# Display_RevA.net
KiCad netlist of a schematic drawn in EAGLE
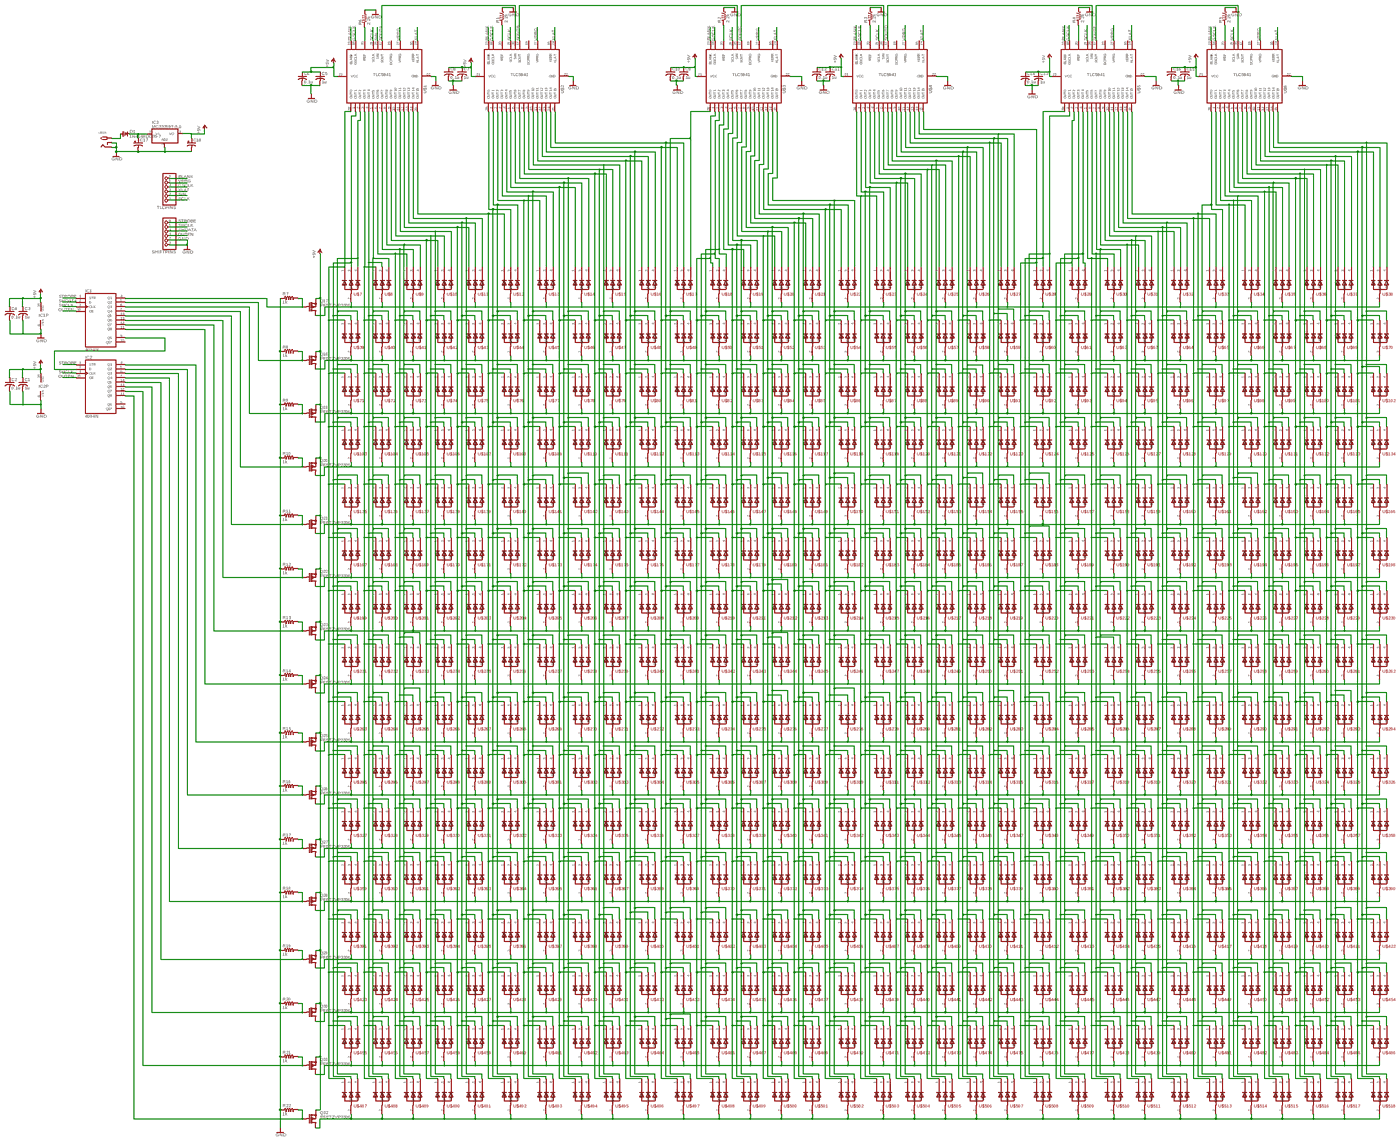
[diagram p0: schematic, sheet 1, overview]
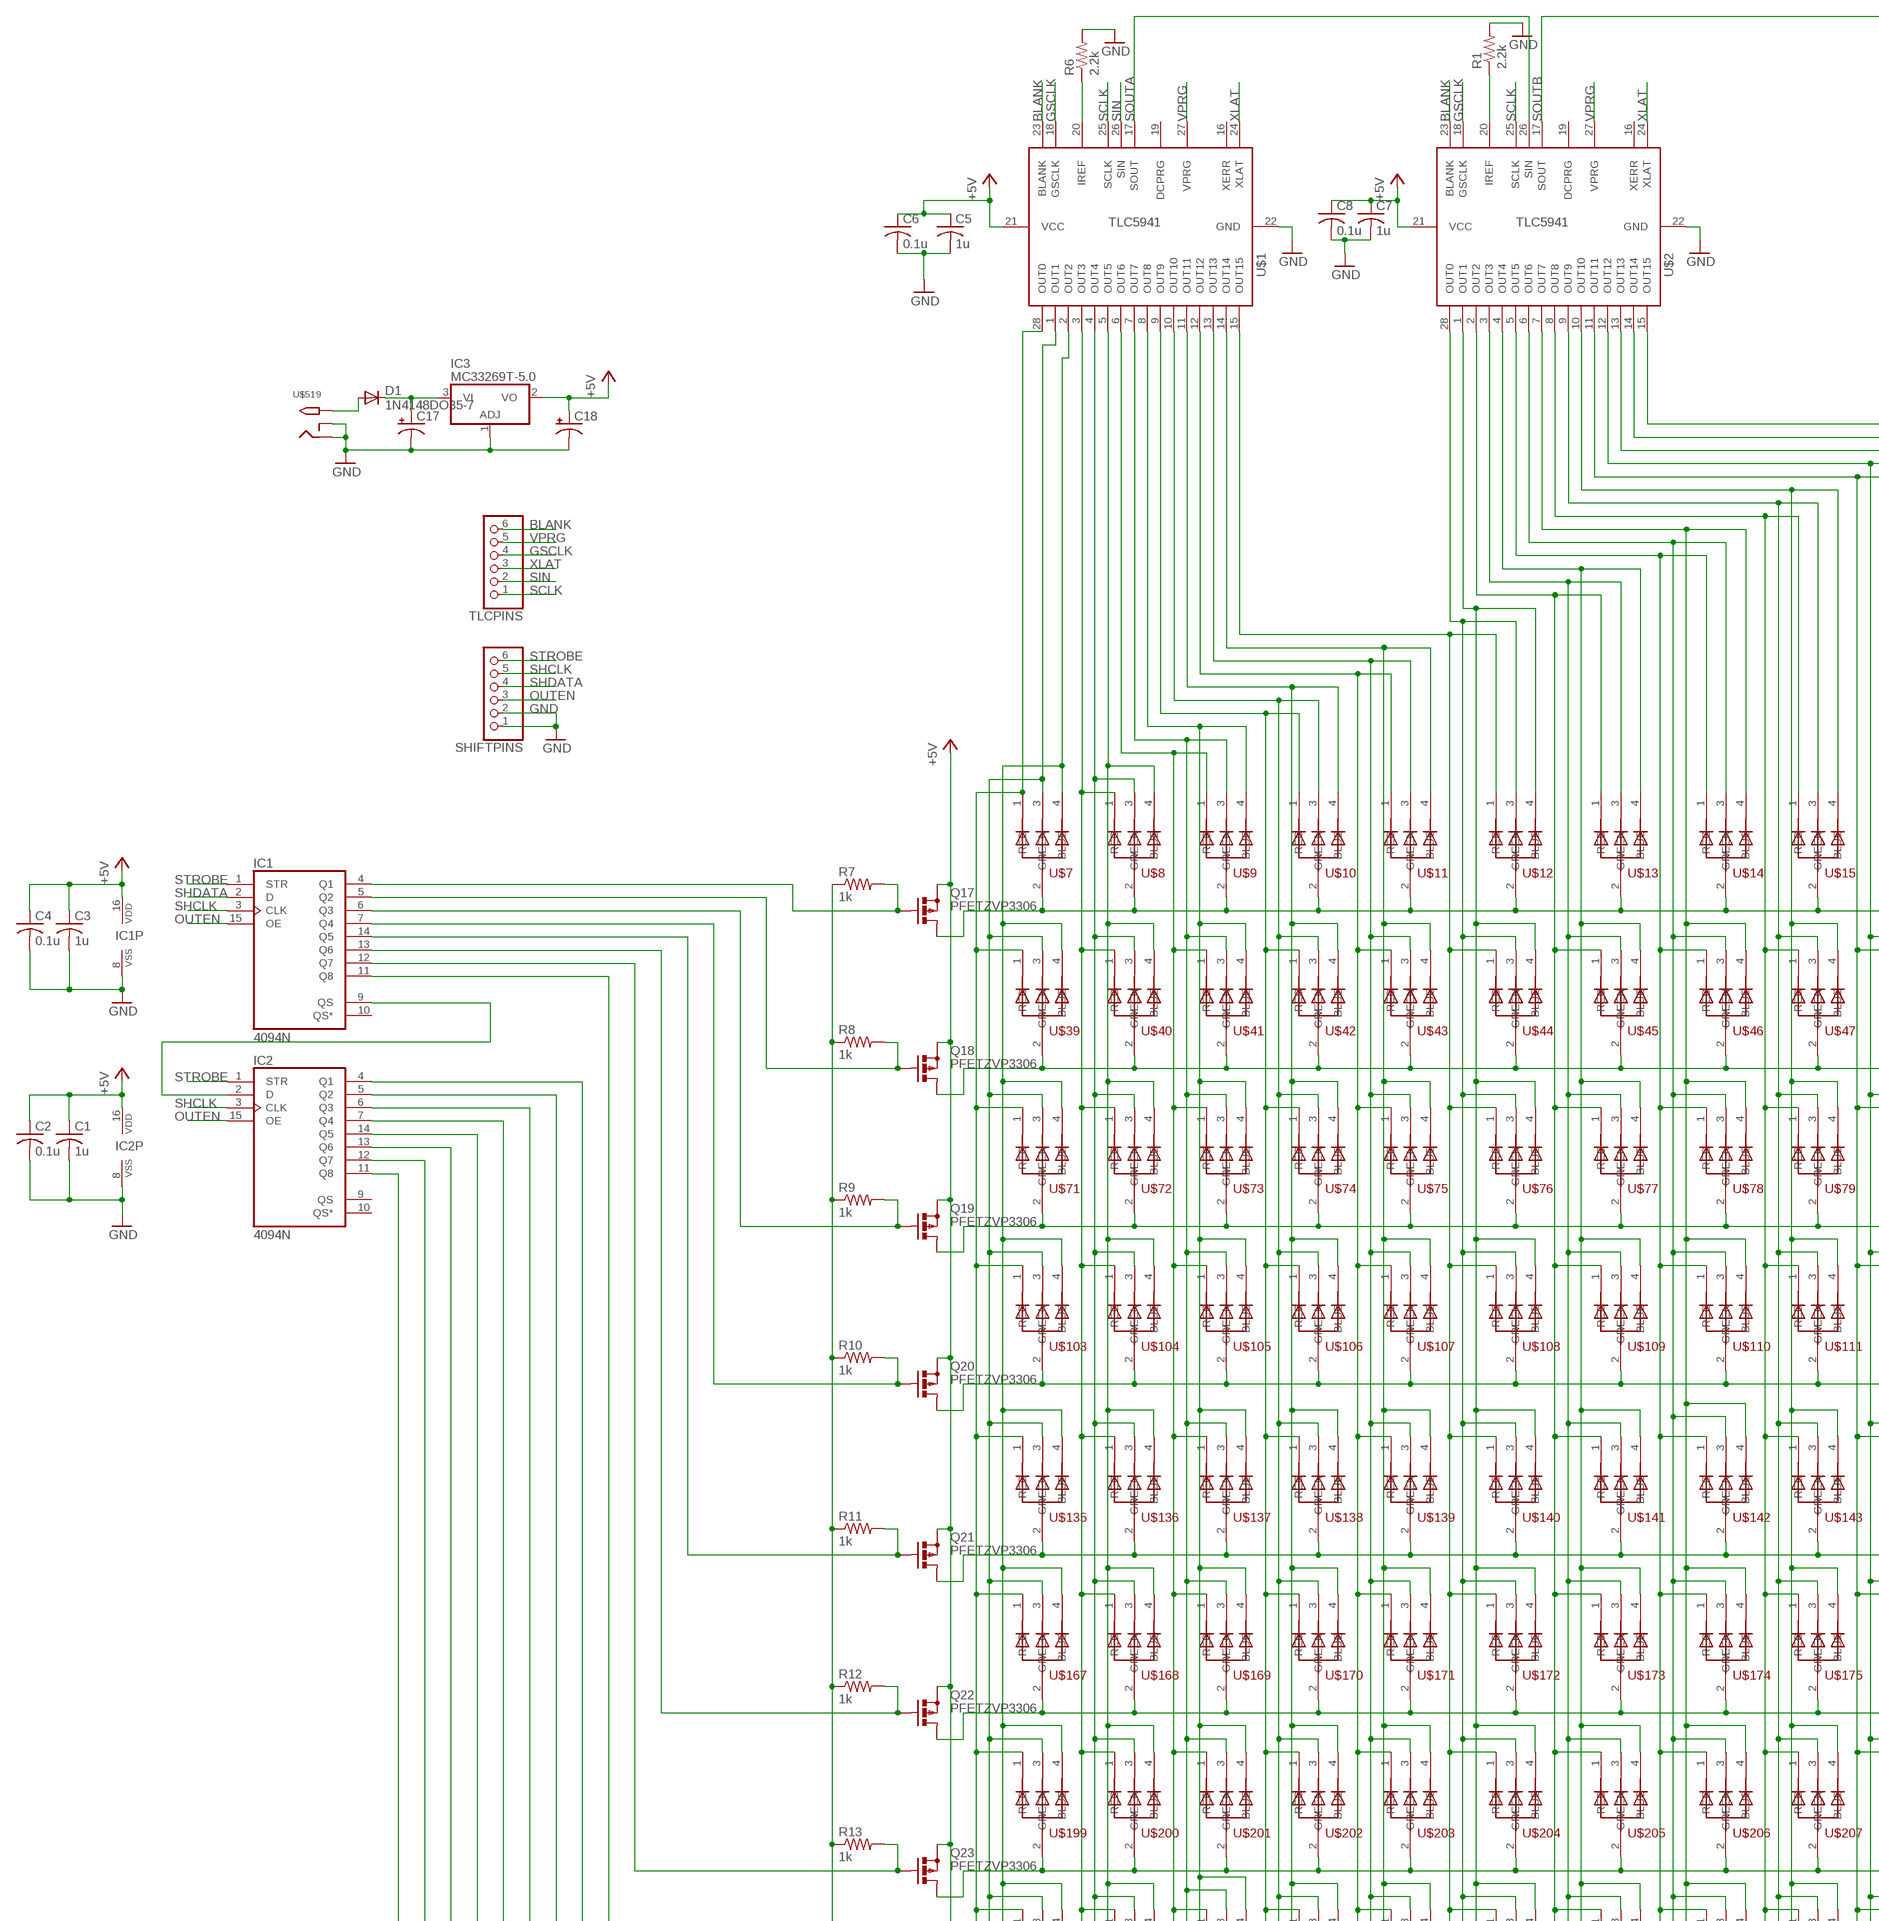
[diagram p1: schematic, sheet 1, part 1 of 4]
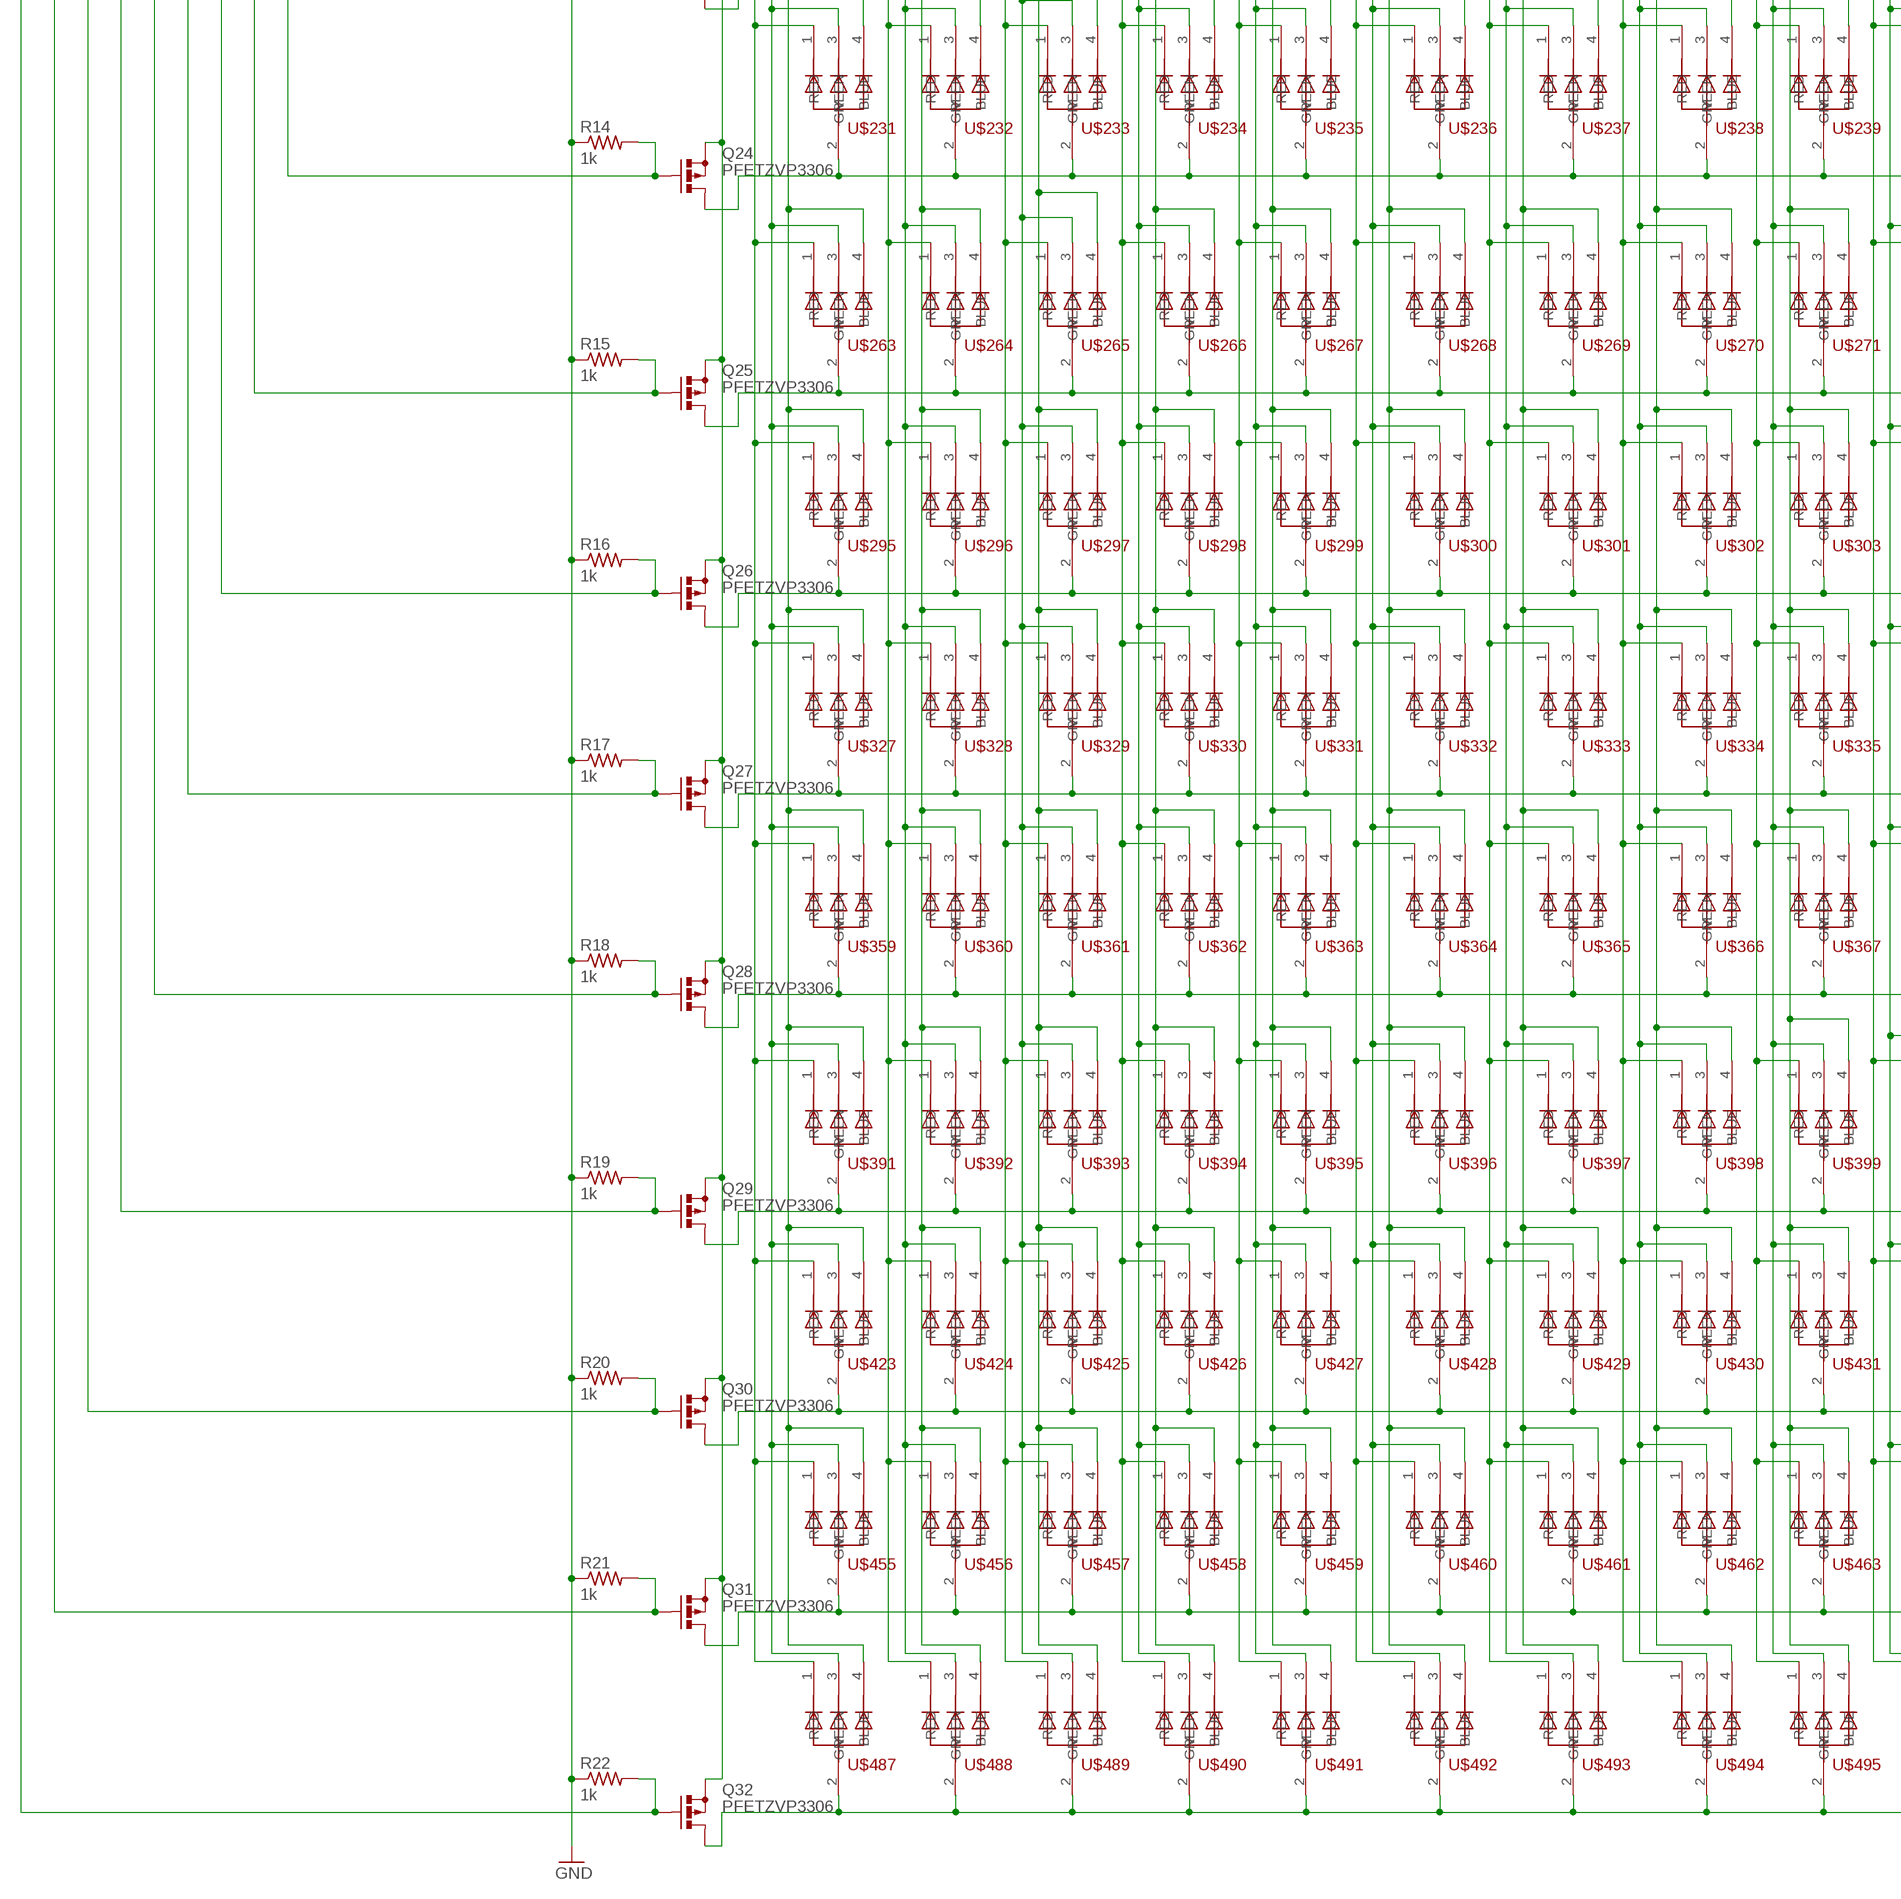
[diagram p2: schematic, sheet 1, part 2 of 4]
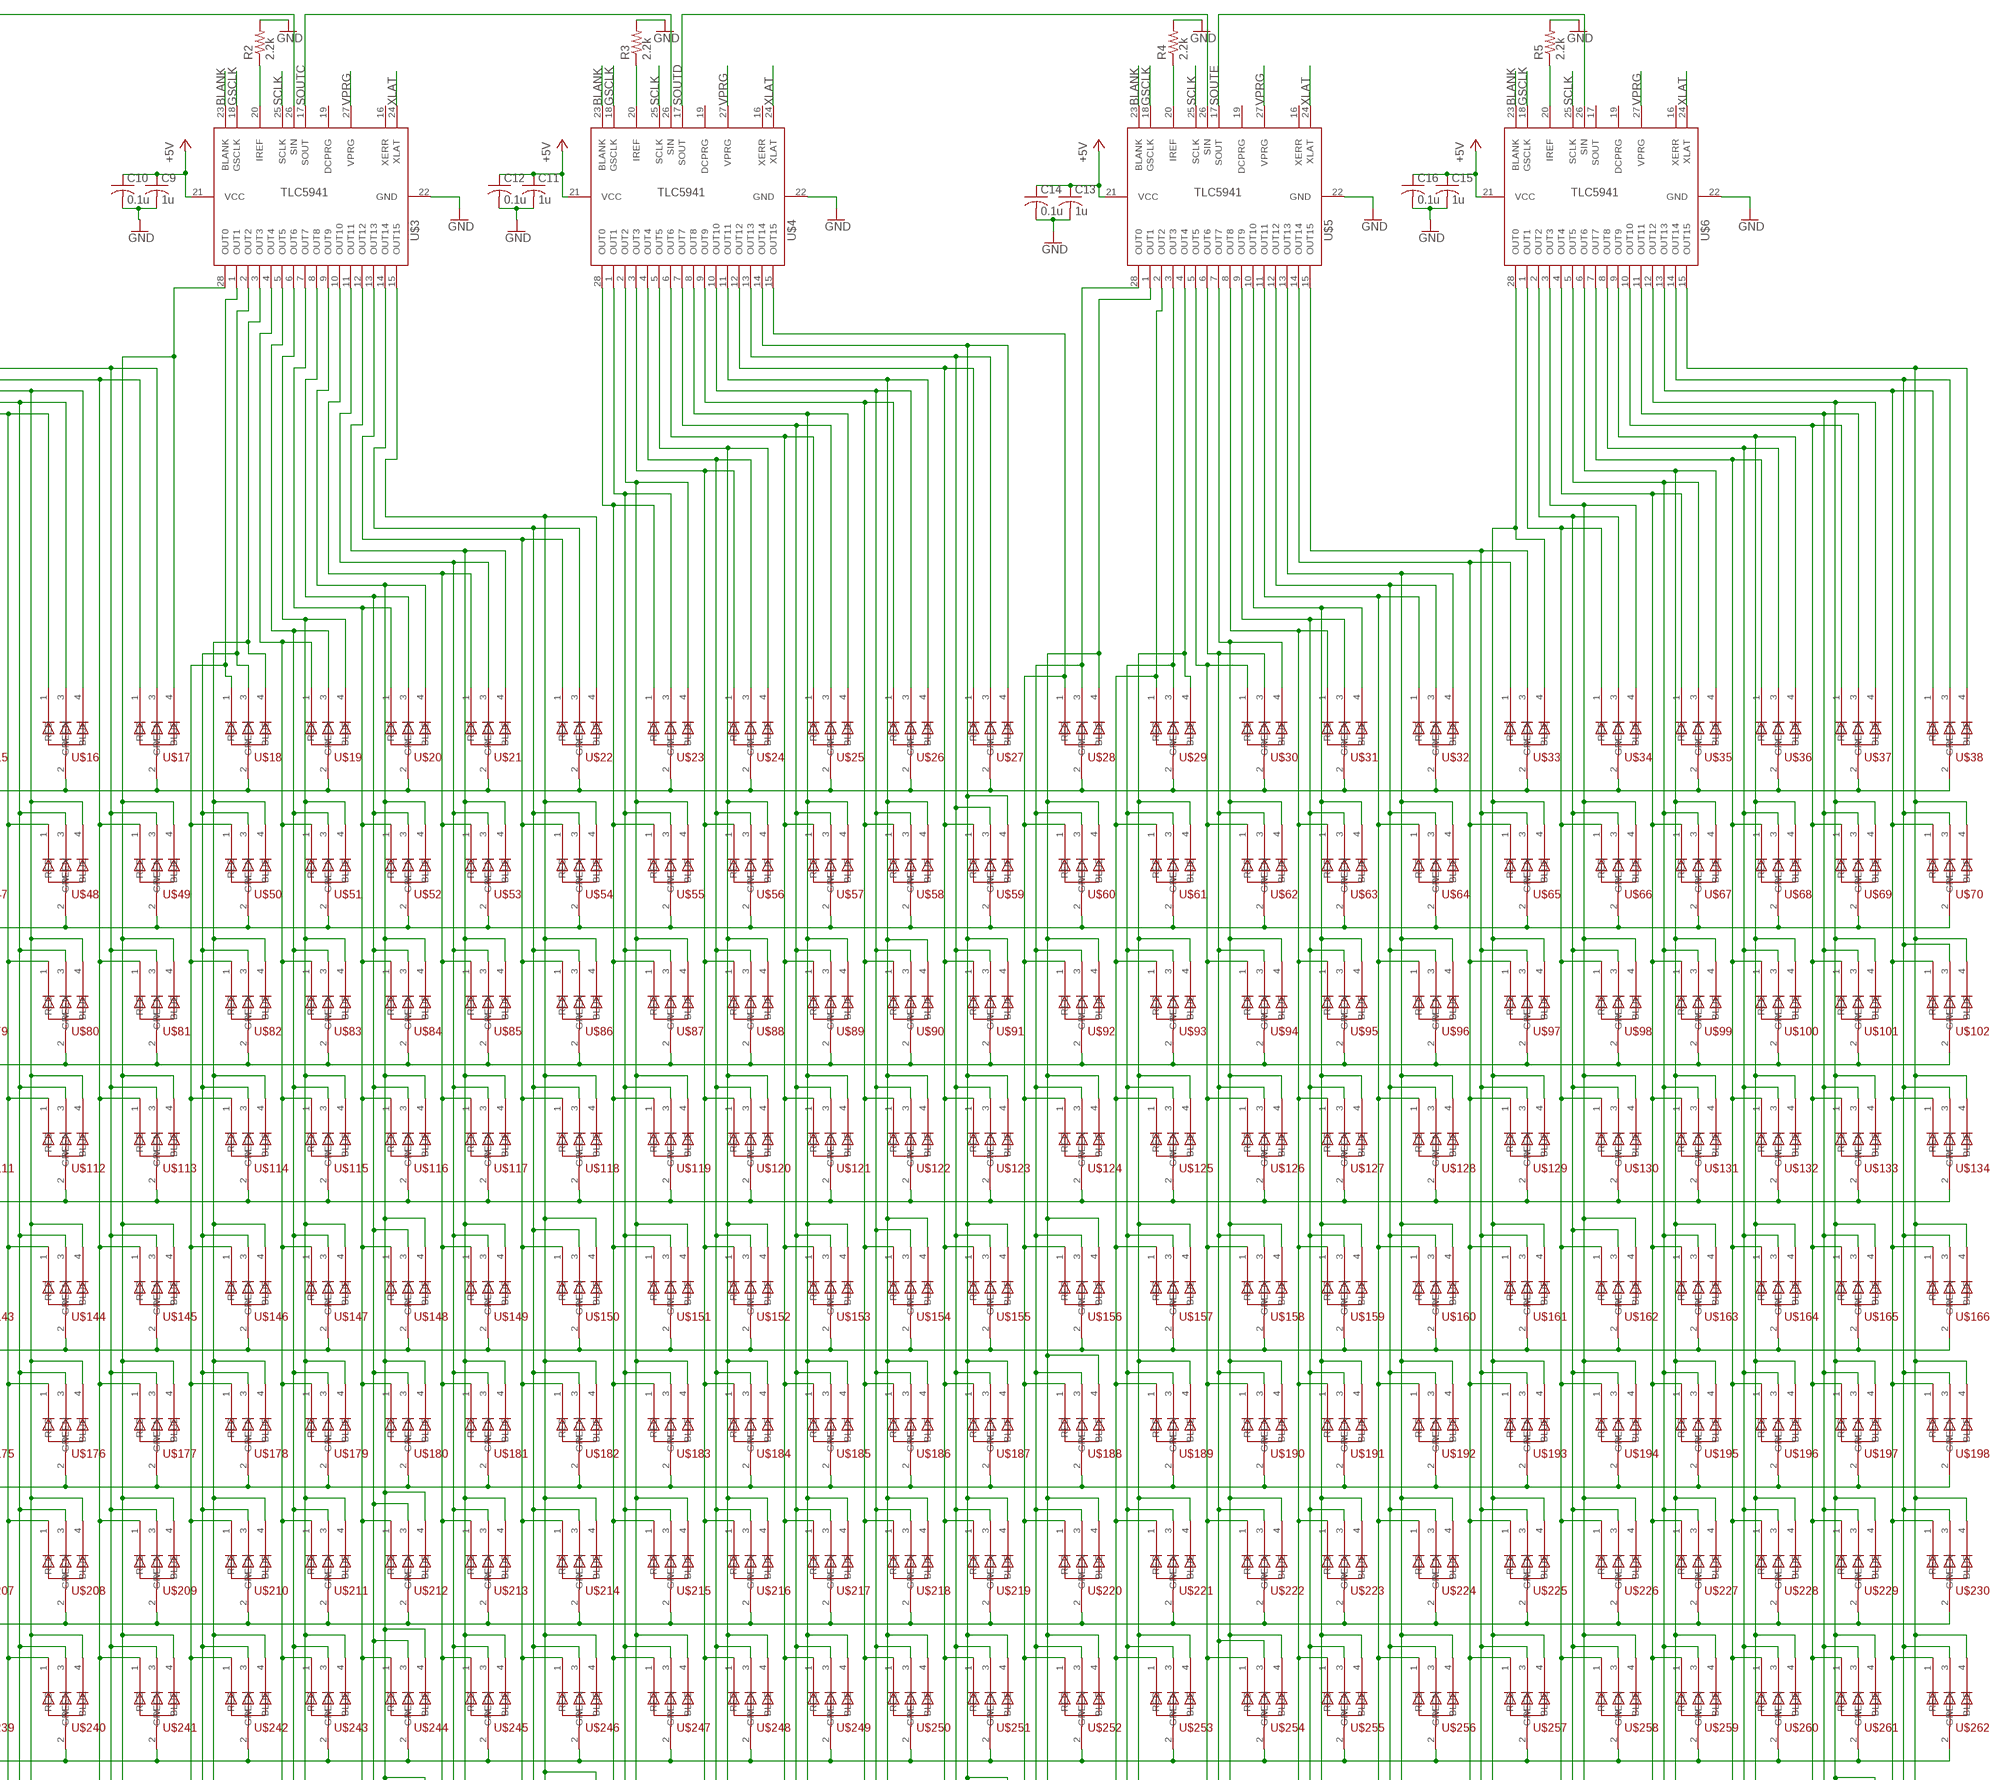
[diagram p3: schematic, sheet 1, part 3 of 4]
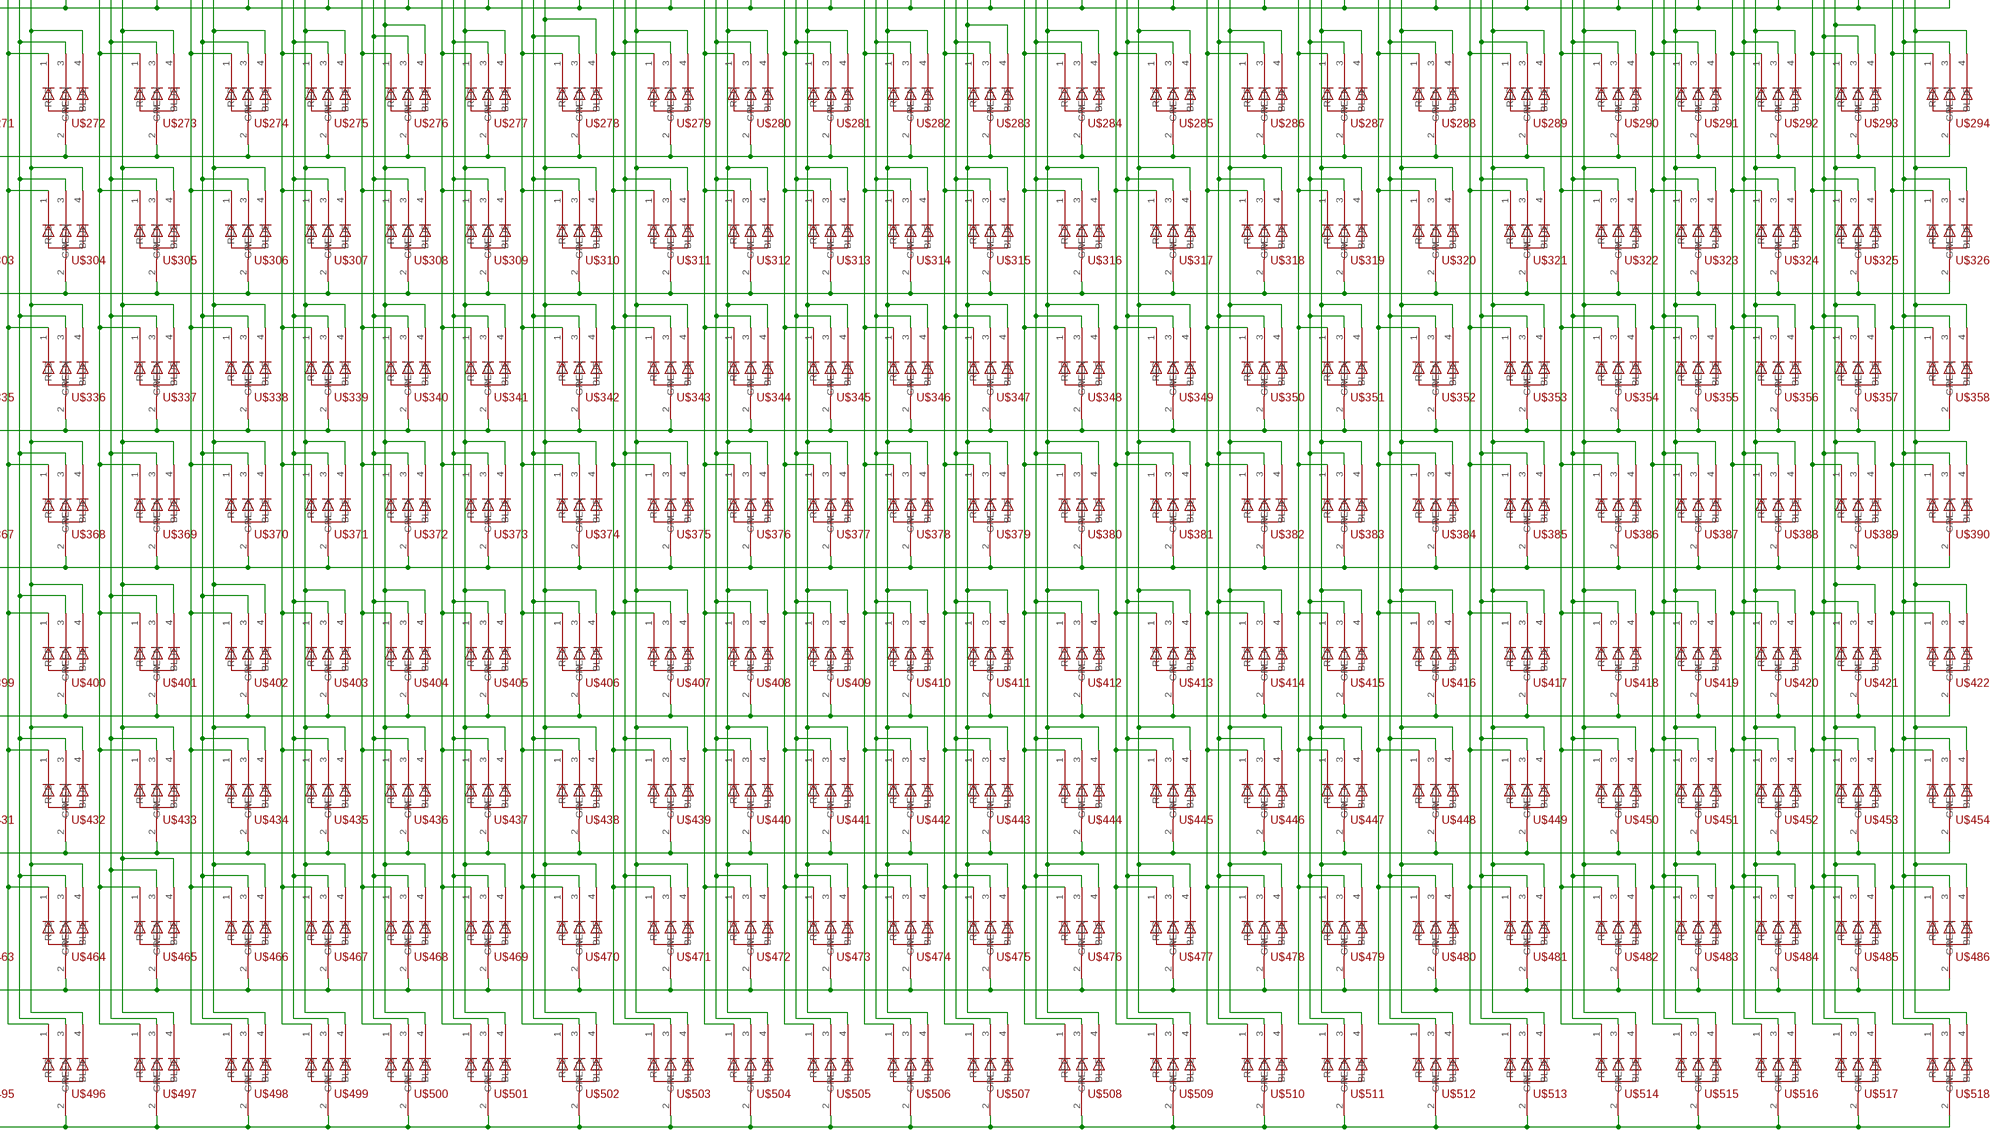
[diagram p4: schematic, sheet 1, part 4 of 4]

(export (version "E")
  (design (tool "Eeschema 10.0.6"))
  (components
    (comp (ref "C1")
      (value "1u")
      (footprint "eagle-import:C0805")
      (libsource (lib "eagle-import") (part "C-USC0805"))
    )
    (comp (ref "C2")
      (value "0.1u")
      (footprint "eagle-import:C0805")
      (libsource (lib "eagle-import") (part "C-USC0805"))
    )
    (comp (ref "C3")
      (value "1u")
      (footprint "eagle-import:C0805")
      (libsource (lib "eagle-import") (part "C-USC0805"))
    )
    (comp (ref "C4")
      (value "0.1u")
      (footprint "eagle-import:C0805")
      (libsource (lib "eagle-import") (part "C-USC0805"))
    )
    (comp (ref "C5")
      (value "1u")
      (footprint "eagle-import:C0805")
      (libsource (lib "eagle-import") (part "C-USC0805"))
    )
    (comp (ref "C6")
      (value "0.1u")
      (footprint "eagle-import:C0805")
      (libsource (lib "eagle-import") (part "C-USC0805"))
    )
    (comp (ref "C7")
      (value "1u")
      (footprint "eagle-import:C0805")
      (libsource (lib "eagle-import") (part "C-USC0805"))
    )
    (comp (ref "C8")
      (value "0.1u")
      (footprint "eagle-import:C0805")
      (libsource (lib "eagle-import") (part "C-USC0805"))
    )
    (comp (ref "C9")
      (value "1u")
      (footprint "eagle-import:C0805")
      (libsource (lib "eagle-import") (part "C-USC0805"))
    )
    (comp (ref "C10")
      (value "0.1u")
      (footprint "eagle-import:C0805")
      (libsource (lib "eagle-import") (part "C-USC0805"))
    )
    (comp (ref "C11")
      (value "1u")
      (footprint "eagle-import:C0805")
      (libsource (lib "eagle-import") (part "C-USC0805"))
    )
    (comp (ref "C12")
      (value "0.1u")
      (footprint "eagle-import:C0805")
      (libsource (lib "eagle-import") (part "C-USC0805"))
    )
    (comp (ref "C13")
      (value "1u")
      (footprint "eagle-import:C0805")
      (libsource (lib "eagle-import") (part "C-USC0805"))
    )
    (comp (ref "C14")
      (value "0.1u")
      (footprint "eagle-import:C0805")
      (libsource (lib "eagle-import") (part "C-USC0805"))
    )
    (comp (ref "C15")
      (value "1u")
      (footprint "eagle-import:C0805")
      (libsource (lib "eagle-import") (part "C-USC0805"))
    )
    (comp (ref "C16")
      (value "0.1u")
      (footprint "eagle-import:C0805")
      (libsource (lib "eagle-import") (part "C-USC0805"))
    )
    (comp (ref "C17")
      (value "CPOL-USE2.5-5")
      (footprint "eagle-import:E2,5-5")
      (libsource (lib "eagle-import") (part "CPOL-USE2.5-5"))
    )
    (comp (ref "C18")
      (value "CPOL-USE2.5-5")
      (footprint "eagle-import:E2,5-5")
      (libsource (lib "eagle-import") (part "CPOL-USE2.5-5"))
    )
    (comp (ref "D1")
      (value "1N4148DO35-7")
      (footprint "eagle-import:DO35-7")
      (libsource (lib "eagle-import") (part "1N4148DO35-7"))
    )
    (comp (ref "IC1")
      (value "4094N")
      (footprint "eagle-import:DIL16")
      (libsource (lib "eagle-import") (part "4094N"))
    )
    (comp (ref "IC2")
      (value "4094N")
      (footprint "eagle-import:DIL16")
      (libsource (lib "eagle-import") (part "4094N"))
    )
    (comp (ref "IC3")
      (value "MC33269T-5.0")
      (footprint "eagle-import:TO220V")
      (libsource (lib "eagle-import") (part "MC33269?T-5.0"))
    )
    (comp (ref "Q17")
      (value "PFETZVP3306")
      (footprint "eagle-import:TO92-OVAL")
      (libsource (lib "eagle-import") (part "PFETZVP3306"))
    )
    (comp (ref "Q18")
      (value "PFETZVP3306")
      (footprint "eagle-import:TO92-OVAL")
      (libsource (lib "eagle-import") (part "PFETZVP3306"))
    )
    (comp (ref "Q19")
      (value "PFETZVP3306")
      (footprint "eagle-import:TO92-OVAL")
      (libsource (lib "eagle-import") (part "PFETZVP3306"))
    )
    (comp (ref "Q20")
      (value "PFETZVP3306")
      (footprint "eagle-import:TO92-OVAL")
      (libsource (lib "eagle-import") (part "PFETZVP3306"))
    )
    (comp (ref "Q21")
      (value "PFETZVP3306")
      (footprint "eagle-import:TO92-OVAL")
      (libsource (lib "eagle-import") (part "PFETZVP3306"))
    )
    (comp (ref "Q22")
      (value "PFETZVP3306")
      (footprint "eagle-import:TO92-OVAL")
      (libsource (lib "eagle-import") (part "PFETZVP3306"))
    )
    (comp (ref "Q23")
      (value "PFETZVP3306")
      (footprint "eagle-import:TO92-OVAL")
      (libsource (lib "eagle-import") (part "PFETZVP3306"))
    )
    (comp (ref "Q24")
      (value "PFETZVP3306")
      (footprint "eagle-import:TO92-OVAL")
      (libsource (lib "eagle-import") (part "PFETZVP3306"))
    )
    (comp (ref "Q25")
      (value "PFETZVP3306")
      (footprint "eagle-import:TO92-OVAL")
      (libsource (lib "eagle-import") (part "PFETZVP3306"))
    )
    (comp (ref "Q26")
      (value "PFETZVP3306")
      (footprint "eagle-import:TO92-OVAL")
      (libsource (lib "eagle-import") (part "PFETZVP3306"))
    )
    (comp (ref "Q27")
      (value "PFETZVP3306")
      (footprint "eagle-import:TO92-OVAL")
      (libsource (lib "eagle-import") (part "PFETZVP3306"))
    )
    (comp (ref "Q28")
      (value "PFETZVP3306")
      (footprint "eagle-import:TO92-OVAL")
      (libsource (lib "eagle-import") (part "PFETZVP3306"))
    )
    (comp (ref "Q29")
      (value "PFETZVP3306")
      (footprint "eagle-import:TO92-OVAL")
      (libsource (lib "eagle-import") (part "PFETZVP3306"))
    )
    (comp (ref "Q30")
      (value "PFETZVP3306")
      (footprint "eagle-import:TO92-OVAL")
      (libsource (lib "eagle-import") (part "PFETZVP3306"))
    )
    (comp (ref "Q31")
      (value "PFETZVP3306")
      (footprint "eagle-import:TO92-OVAL")
      (libsource (lib "eagle-import") (part "PFETZVP3306"))
    )
    (comp (ref "Q32")
      (value "PFETZVP3306")
      (footprint "eagle-import:TO92-OVAL")
      (libsource (lib "eagle-import") (part "PFETZVP3306"))
    )
    (comp (ref "R1")
      (value "2.2k")
      (footprint "eagle-import:R0805")
      (libsource (lib "eagle-import") (part "R-US_R0805"))
    )
    (comp (ref "R2")
      (value "2.2k")
      (footprint "eagle-import:R0805")
      (libsource (lib "eagle-import") (part "R-US_R0805"))
    )
    (comp (ref "R3")
      (value "2.2k")
      (footprint "eagle-import:R0805")
      (libsource (lib "eagle-import") (part "R-US_R0805"))
    )
    (comp (ref "R4")
      (value "2.2k")
      (footprint "eagle-import:R0805")
      (libsource (lib "eagle-import") (part "R-US_R0805"))
    )
    (comp (ref "R5")
      (value "2.2k")
      (footprint "eagle-import:R0805")
      (libsource (lib "eagle-import") (part "R-US_R0805"))
    )
    (comp (ref "R6")
      (value "2.2k")
      (footprint "eagle-import:R0805")
      (libsource (lib "eagle-import") (part "R-US_R0805"))
    )
    (comp (ref "R7")
      (value "1k")
      (footprint "eagle-import:R0805")
      (libsource (lib "eagle-import") (part "R-US_R0805"))
    )
    (comp (ref "R8")
      (value "1k")
      (footprint "eagle-import:R0805")
      (libsource (lib "eagle-import") (part "R-US_R0805"))
    )
    (comp (ref "R9")
      (value "1k")
      (footprint "eagle-import:R0805")
      (libsource (lib "eagle-import") (part "R-US_R0805"))
    )
    (comp (ref "R10")
      (value "1k")
      (footprint "eagle-import:R0805")
      (libsource (lib "eagle-import") (part "R-US_R0805"))
    )
    (comp (ref "R11")
      (value "1k")
      (footprint "eagle-import:R0805")
      (libsource (lib "eagle-import") (part "R-US_R0805"))
    )
    (comp (ref "R12")
      (value "1k")
      (footprint "eagle-import:R0805")
      (libsource (lib "eagle-import") (part "R-US_R0805"))
    )
    (comp (ref "R13")
      (value "1k")
      (footprint "eagle-import:R0805")
      (libsource (lib "eagle-import") (part "R-US_R0805"))
    )
    (comp (ref "R14")
      (value "1k")
      (footprint "eagle-import:R0805")
      (libsource (lib "eagle-import") (part "R-US_R0805"))
    )
    (comp (ref "R15")
      (value "1k")
      (footprint "eagle-import:R0805")
      (libsource (lib "eagle-import") (part "R-US_R0805"))
    )
    (comp (ref "R16")
      (value "1k")
      (footprint "eagle-import:R0805")
      (libsource (lib "eagle-import") (part "R-US_R0805"))
    )
    (comp (ref "R17")
      (value "1k")
      (footprint "eagle-import:R0805")
      (libsource (lib "eagle-import") (part "R-US_R0805"))
    )
    (comp (ref "R18")
      (value "1k")
      (footprint "eagle-import:R0805")
      (libsource (lib "eagle-import") (part "R-US_R0805"))
    )
    (comp (ref "R19")
      (value "1k")
      (footprint "eagle-import:R0805")
      (libsource (lib "eagle-import") (part "R-US_R0805"))
    )
    (comp (ref "R20")
      (value "1k")
      (footprint "eagle-import:R0805")
      (libsource (lib "eagle-import") (part "R-US_R0805"))
    )
    (comp (ref "R21")
      (value "1k")
      (footprint "eagle-import:R0805")
      (libsource (lib "eagle-import") (part "R-US_R0805"))
    )
    (comp (ref "R22")
      (value "1k")
      (footprint "eagle-import:R0805")
      (libsource (lib "eagle-import") (part "R-US_R0805"))
    )
    (comp (ref "SHIFTPINS")
      (value "PINHD-1X6")
      (footprint "eagle-import:1X06")
      (libsource (lib "eagle-import") (part "PINHD-1X6"))
    )
    (comp (ref "TLCPINS")
      (value "PINHD-1X6")
      (footprint "eagle-import:1X06")
      (libsource (lib "eagle-import") (part "PINHD-1X6"))
    )
    (comp (ref "U$1")
      (value "TLC5940")
      (footprint "eagle-import:DIL28-3")
      (libsource (lib "eagle-import") (part "TLC5940"))
    )
    (comp (ref "U$2")
      (value "TLC5940")
      (footprint "eagle-import:DIL28-3")
      (libsource (lib "eagle-import") (part "TLC5940"))
    )
    (comp (ref "U$3")
      (value "TLC5940")
      (footprint "eagle-import:DIL28-3")
      (libsource (lib "eagle-import") (part "TLC5940"))
    )
    (comp (ref "U$4")
      (value "TLC5940")
      (footprint "eagle-import:DIL28-3")
      (libsource (lib "eagle-import") (part "TLC5940"))
    )
    (comp (ref "U$5")
      (value "TLC5940")
      (footprint "eagle-import:DIL28-3")
      (libsource (lib "eagle-import") (part "TLC5940"))
    )
    (comp (ref "U$6")
      (value "TLC5940")
      (footprint "eagle-import:DIL28-3")
      (libsource (lib "eagle-import") (part "TLC5940"))
    )
    (comp (ref "U$7")
      (value "RGBLEDAN")
      (footprint "eagle-import:LED5MMRGB")
      (libsource (lib "eagle-import") (part "RGBLEDAN"))
    )
    (comp (ref "U$8")
      (value "RGBLEDAN")
      (footprint "eagle-import:LED5MMRGB")
      (libsource (lib "eagle-import") (part "RGBLEDAN"))
    )
    (comp (ref "U$9")
      (value "RGBLEDAN")
      (footprint "eagle-import:LED5MMRGB")
      (libsource (lib "eagle-import") (part "RGBLEDAN"))
    )
    (comp (ref "U$10")
      (value "RGBLEDAN")
      (footprint "eagle-import:LED5MMRGB")
      (libsource (lib "eagle-import") (part "RGBLEDAN"))
    )
    (comp (ref "U$11")
      (value "RGBLEDAN")
      (footprint "eagle-import:LED5MMRGB")
      (libsource (lib "eagle-import") (part "RGBLEDAN"))
    )
    (comp (ref "U$12")
      (value "RGBLEDAN")
      (footprint "eagle-import:LED5MMRGB")
      (libsource (lib "eagle-import") (part "RGBLEDAN"))
    )
    (comp (ref "U$13")
      (value "RGBLEDAN")
      (footprint "eagle-import:LED5MMRGB")
      (libsource (lib "eagle-import") (part "RGBLEDAN"))
    )
    (comp (ref "U$14")
      (value "RGBLEDAN")
      (footprint "eagle-import:LED5MMRGB")
      (libsource (lib "eagle-import") (part "RGBLEDAN"))
    )
    (comp (ref "U$15")
      (value "RGBLEDAN")
      (footprint "eagle-import:LED5MMRGB")
      (libsource (lib "eagle-import") (part "RGBLEDAN"))
    )
    (comp (ref "U$16")
      (value "RGBLEDAN")
      (footprint "eagle-import:LED5MMRGB")
      (libsource (lib "eagle-import") (part "RGBLEDAN"))
    )
    (comp (ref "U$17")
      (value "RGBLEDAN")
      (footprint "eagle-import:LED5MMRGB")
      (libsource (lib "eagle-import") (part "RGBLEDAN"))
    )
    (comp (ref "U$18")
      (value "RGBLEDAN")
      (footprint "eagle-import:LED5MMRGB")
      (libsource (lib "eagle-import") (part "RGBLEDAN"))
    )
    (comp (ref "U$19")
      (value "RGBLEDAN")
      (footprint "eagle-import:LED5MMRGB")
      (libsource (lib "eagle-import") (part "RGBLEDAN"))
    )
    (comp (ref "U$20")
      (value "RGBLEDAN")
      (footprint "eagle-import:LED5MMRGB")
      (libsource (lib "eagle-import") (part "RGBLEDAN"))
    )
    (comp (ref "U$21")
      (value "RGBLEDAN")
      (footprint "eagle-import:LED5MMRGB")
      (libsource (lib "eagle-import") (part "RGBLEDAN"))
    )
    (comp (ref "U$22")
      (value "RGBLEDAN")
      (footprint "eagle-import:LED5MMRGB")
      (libsource (lib "eagle-import") (part "RGBLEDAN"))
    )
    (comp (ref "U$23")
      (value "RGBLEDAN")
      (footprint "eagle-import:LED5MMRGB")
      (libsource (lib "eagle-import") (part "RGBLEDAN"))
    )
    (comp (ref "U$24")
      (value "RGBLEDAN")
      (footprint "eagle-import:LED5MMRGB")
      (libsource (lib "eagle-import") (part "RGBLEDAN"))
    )
    (comp (ref "U$25")
      (value "RGBLEDAN")
      (footprint "eagle-import:LED5MMRGB")
      (libsource (lib "eagle-import") (part "RGBLEDAN"))
    )
    (comp (ref "U$26")
      (value "RGBLEDAN")
      (footprint "eagle-import:LED5MMRGB")
      (libsource (lib "eagle-import") (part "RGBLEDAN"))
    )
    (comp (ref "U$27")
      (value "RGBLEDAN")
      (footprint "eagle-import:LED5MMRGB")
      (libsource (lib "eagle-import") (part "RGBLEDAN"))
    )
    (comp (ref "U$28")
      (value "RGBLEDAN")
      (footprint "eagle-import:LED5MMRGB")
      (libsource (lib "eagle-import") (part "RGBLEDAN"))
    )
    (comp (ref "U$29")
      (value "RGBLEDAN")
      (footprint "eagle-import:LED5MMRGB")
      (libsource (lib "eagle-import") (part "RGBLEDAN"))
    )
    (comp (ref "U$30")
      (value "RGBLEDAN")
      (footprint "eagle-import:LED5MMRGB")
      (libsource (lib "eagle-import") (part "RGBLEDAN"))
    )
    (comp (ref "U$31")
      (value "RGBLEDAN")
      (footprint "eagle-import:LED5MMRGB")
      (libsource (lib "eagle-import") (part "RGBLEDAN"))
    )
    (comp (ref "U$32")
      (value "RGBLEDAN")
      (footprint "eagle-import:LED5MMRGB")
      (libsource (lib "eagle-import") (part "RGBLEDAN"))
    )
    (comp (ref "U$33")
      (value "RGBLEDAN")
      (footprint "eagle-import:LED5MMRGB")
      (libsource (lib "eagle-import") (part "RGBLEDAN"))
    )
    (comp (ref "U$34")
      (value "RGBLEDAN")
      (footprint "eagle-import:LED5MMRGB")
      (libsource (lib "eagle-import") (part "RGBLEDAN"))
    )
    (comp (ref "U$35")
      (value "RGBLEDAN")
      (footprint "eagle-import:LED5MMRGB")
      (libsource (lib "eagle-import") (part "RGBLEDAN"))
    )
    (comp (ref "U$36")
      (value "RGBLEDAN")
      (footprint "eagle-import:LED5MMRGB")
      (libsource (lib "eagle-import") (part "RGBLEDAN"))
    )
    (comp (ref "U$37")
      (value "RGBLEDAN")
      (footprint "eagle-import:LED5MMRGB")
      (libsource (lib "eagle-import") (part "RGBLEDAN"))
    )
    (comp (ref "U$38")
      (value "RGBLEDAN")
      (footprint "eagle-import:LED5MMRGB")
      (libsource (lib "eagle-import") (part "RGBLEDAN"))
    )
    (comp (ref "U$39")
      (value "RGBLEDAN")
      (footprint "eagle-import:LED5MMRGB")
      (libsource (lib "eagle-import") (part "RGBLEDAN"))
    )
    (comp (ref "U$40")
      (value "RGBLEDAN")
      (footprint "eagle-import:LED5MMRGB")
      (libsource (lib "eagle-import") (part "RGBLEDAN"))
    )
    (comp (ref "U$41")
      (value "RGBLEDAN")
      (footprint "eagle-import:LED5MMRGB")
      (libsource (lib "eagle-import") (part "RGBLEDAN"))
    )
    (comp (ref "U$42")
      (value "RGBLEDAN")
      (footprint "eagle-import:LED5MMRGB")
      (libsource (lib "eagle-import") (part "RGBLEDAN"))
    )
    (comp (ref "U$43")
      (value "RGBLEDAN")
      (footprint "eagle-import:LED5MMRGB")
      (libsource (lib "eagle-import") (part "RGBLEDAN"))
    )
    (comp (ref "U$44")
      (value "RGBLEDAN")
      (footprint "eagle-import:LED5MMRGB")
      (libsource (lib "eagle-import") (part "RGBLEDAN"))
    )
    (comp (ref "U$45")
      (value "RGBLEDAN")
      (footprint "eagle-import:LED5MMRGB")
      (libsource (lib "eagle-import") (part "RGBLEDAN"))
    )
    (comp (ref "U$46")
      (value "RGBLEDAN")
      (footprint "eagle-import:LED5MMRGB")
      (libsource (lib "eagle-import") (part "RGBLEDAN"))
    )
    (comp (ref "U$47")
      (value "RGBLEDAN")
      (footprint "eagle-import:LED5MMRGB")
      (libsource (lib "eagle-import") (part "RGBLEDAN"))
    )
    (comp (ref "U$48")
      (value "RGBLEDAN")
      (footprint "eagle-import:LED5MMRGB")
      (libsource (lib "eagle-import") (part "RGBLEDAN"))
    )
    (comp (ref "U$49")
      (value "RGBLEDAN")
      (footprint "eagle-import:LED5MMRGB")
      (libsource (lib "eagle-import") (part "RGBLEDAN"))
    )
    (comp (ref "U$50")
      (value "RGBLEDAN")
      (footprint "eagle-import:LED5MMRGB")
      (libsource (lib "eagle-import") (part "RGBLEDAN"))
    )
    (comp (ref "U$51")
      (value "RGBLEDAN")
      (footprint "eagle-import:LED5MMRGB")
      (libsource (lib "eagle-import") (part "RGBLEDAN"))
    )
    (comp (ref "U$52")
      (value "RGBLEDAN")
      (footprint "eagle-import:LED5MMRGB")
      (libsource (lib "eagle-import") (part "RGBLEDAN"))
    )
    (comp (ref "U$53")
      (value "RGBLEDAN")
      (footprint "eagle-import:LED5MMRGB")
      (libsource (lib "eagle-import") (part "RGBLEDAN"))
    )
    (comp (ref "U$54")
      (value "RGBLEDAN")
      (footprint "eagle-import:LED5MMRGB")
      (libsource (lib "eagle-import") (part "RGBLEDAN"))
    )
    (comp (ref "U$55")
      (value "RGBLEDAN")
      (footprint "eagle-import:LED5MMRGB")
      (libsource (lib "eagle-import") (part "RGBLEDAN"))
    )
    (comp (ref "U$56")
      (value "RGBLEDAN")
      (footprint "eagle-import:LED5MMRGB")
      (libsource (lib "eagle-import") (part "RGBLEDAN"))
    )
    (comp (ref "U$57")
      (value "RGBLEDAN")
      (footprint "eagle-import:LED5MMRGB")
      (libsource (lib "eagle-import") (part "RGBLEDAN"))
    )
    (comp (ref "U$58")
      (value "RGBLEDAN")
      (footprint "eagle-import:LED5MMRGB")
      (libsource (lib "eagle-import") (part "RGBLEDAN"))
    )
    (comp (ref "U$59")
      (value "RGBLEDAN")
      (footprint "eagle-import:LED5MMRGB")
      (libsource (lib "eagle-import") (part "RGBLEDAN"))
    )
    (comp (ref "U$60")
      (value "RGBLEDAN")
      (footprint "eagle-import:LED5MMRGB")
      (libsource (lib "eagle-import") (part "RGBLEDAN"))
    )
    (comp (ref "U$61")
      (value "RGBLEDAN")
      (footprint "eagle-import:LED5MMRGB")
      (libsource (lib "eagle-import") (part "RGBLEDAN"))
    )
    (comp (ref "U$62")
      (value "RGBLEDAN")
      (footprint "eagle-import:LED5MMRGB")
      (libsource (lib "eagle-import") (part "RGBLEDAN"))
    )
    (comp (ref "U$63")
      (value "RGBLEDAN")
      (footprint "eagle-import:LED5MMRGB")
      (libsource (lib "eagle-import") (part "RGBLEDAN"))
    )
    (comp (ref "U$64")
      (value "RGBLEDAN")
      (footprint "eagle-import:LED5MMRGB")
      (libsource (lib "eagle-import") (part "RGBLEDAN"))
    )
    (comp (ref "U$65")
      (value "RGBLEDAN")
      (footprint "eagle-import:LED5MMRGB")
      (libsource (lib "eagle-import") (part "RGBLEDAN"))
    )
    (comp (ref "U$66")
      (value "RGBLEDAN")
      (footprint "eagle-import:LED5MMRGB")
      (libsource (lib "eagle-import") (part "RGBLEDAN"))
    )
    (comp (ref "U$67")
      (value "RGBLEDAN")
      (footprint "eagle-import:LED5MMRGB")
      (libsource (lib "eagle-import") (part "RGBLEDAN"))
    )
    (comp (ref "U$68")
      (value "RGBLEDAN")
      (footprint "eagle-import:LED5MMRGB")
      (libsource (lib "eagle-import") (part "RGBLEDAN"))
    )
    (comp (ref "U$69")
      (value "RGBLEDAN")
      (footprint "eagle-import:LED5MMRGB")
      (libsource (lib "eagle-import") (part "RGBLEDAN"))
    )
    (comp (ref "U$70")
      (value "RGBLEDAN")
      (footprint "eagle-import:LED5MMRGB")
      (libsource (lib "eagle-import") (part "RGBLEDAN"))
    )
    (comp (ref "U$71")
      (value "RGBLEDAN")
      (footprint "eagle-import:LED5MMRGB")
      (libsource (lib "eagle-import") (part "RGBLEDAN"))
    )
    (comp (ref "U$72")
      (value "RGBLEDAN")
      (footprint "eagle-import:LED5MMRGB")
      (libsource (lib "eagle-import") (part "RGBLEDAN"))
    )
    (comp (ref "U$73")
      (value "RGBLEDAN")
      (footprint "eagle-import:LED5MMRGB")
      (libsource (lib "eagle-import") (part "RGBLEDAN"))
    )
    (comp (ref "U$74")
      (value "RGBLEDAN")
      (footprint "eagle-import:LED5MMRGB")
      (libsource (lib "eagle-import") (part "RGBLEDAN"))
    )
    (comp (ref "U$75")
      (value "RGBLEDAN")
      (footprint "eagle-import:LED5MMRGB")
      (libsource (lib "eagle-import") (part "RGBLEDAN"))
    )
    (comp (ref "U$76")
      (value "RGBLEDAN")
      (footprint "eagle-import:LED5MMRGB")
      (libsource (lib "eagle-import") (part "RGBLEDAN"))
    )
    (comp (ref "U$77")
      (value "RGBLEDAN")
      (footprint "eagle-import:LED5MMRGB")
      (libsource (lib "eagle-import") (part "RGBLEDAN"))
    )
    (comp (ref "U$78")
      (value "RGBLEDAN")
      (footprint "eagle-import:LED5MMRGB")
      (libsource (lib "eagle-import") (part "RGBLEDAN"))
    )
    (comp (ref "U$79")
      (value "RGBLEDAN")
      (footprint "eagle-import:LED5MMRGB")
      (libsource (lib "eagle-import") (part "RGBLEDAN"))
    )
    (comp (ref "U$80")
      (value "RGBLEDAN")
      (footprint "eagle-import:LED5MMRGB")
      (libsource (lib "eagle-import") (part "RGBLEDAN"))
    )
    (comp (ref "U$81")
      (value "RGBLEDAN")
      (footprint "eagle-import:LED5MMRGB")
      (libsource (lib "eagle-import") (part "RGBLEDAN"))
    )
    (comp (ref "U$82")
      (value "RGBLEDAN")
      (footprint "eagle-import:LED5MMRGB")
      (libsource (lib "eagle-import") (part "RGBLEDAN"))
    )
    (comp (ref "U$83")
      (value "RGBLEDAN")
      (footprint "eagle-import:LED5MMRGB")
      (libsource (lib "eagle-import") (part "RGBLEDAN"))
    )
    (comp (ref "U$84")
      (value "RGBLEDAN")
      (footprint "eagle-import:LED5MMRGB")
      (libsource (lib "eagle-import") (part "RGBLEDAN"))
    )
    (comp (ref "U$85")
      (value "RGBLEDAN")
      (footprint "eagle-import:LED5MMRGB")
      (libsource (lib "eagle-import") (part "RGBLEDAN"))
    )
    (comp (ref "U$86")
      (value "RGBLEDAN")
      (footprint "eagle-import:LED5MMRGB")
      (libsource (lib "eagle-import") (part "RGBLEDAN"))
    )
    (comp (ref "U$87")
      (value "RGBLEDAN")
      (footprint "eagle-import:LED5MMRGB")
      (libsource (lib "eagle-import") (part "RGBLEDAN"))
    )
    (comp (ref "U$88")
      (value "RGBLEDAN")
      (footprint "eagle-import:LED5MMRGB")
      (libsource (lib "eagle-import") (part "RGBLEDAN"))
    )
    (comp (ref "U$89")
      (value "RGBLEDAN")
      (footprint "eagle-import:LED5MMRGB")
      (libsource (lib "eagle-import") (part "RGBLEDAN"))
    )
    (comp (ref "U$90")
      (value "RGBLEDAN")
      (footprint "eagle-import:LED5MMRGB")
      (libsource (lib "eagle-import") (part "RGBLEDAN"))
    )
    (comp (ref "U$91")
      (value "RGBLEDAN")
      (footprint "eagle-import:LED5MMRGB")
      (libsource (lib "eagle-import") (part "RGBLEDAN"))
    )
    (comp (ref "U$92")
      (value "RGBLEDAN")
      (footprint "eagle-import:LED5MMRGB")
      (libsource (lib "eagle-import") (part "RGBLEDAN"))
    )
    (comp (ref "U$93")
      (value "RGBLEDAN")
      (footprint "eagle-import:LED5MMRGB")
      (libsource (lib "eagle-import") (part "RGBLEDAN"))
    )
    (comp (ref "U$94")
      (value "RGBLEDAN")
      (footprint "eagle-import:LED5MMRGB")
      (libsource (lib "eagle-import") (part "RGBLEDAN"))
    )
    (comp (ref "U$95")
      (value "RGBLEDAN")
      (footprint "eagle-import:LED5MMRGB")
      (libsource (lib "eagle-import") (part "RGBLEDAN"))
    )
    (comp (ref "U$96")
      (value "RGBLEDAN")
      (footprint "eagle-import:LED5MMRGB")
      (libsource (lib "eagle-import") (part "RGBLEDAN"))
    )
    (comp (ref "U$97")
      (value "RGBLEDAN")
      (footprint "eagle-import:LED5MMRGB")
      (libsource (lib "eagle-import") (part "RGBLEDAN"))
    )
    (comp (ref "U$98")
      (value "RGBLEDAN")
      (footprint "eagle-import:LED5MMRGB")
      (libsource (lib "eagle-import") (part "RGBLEDAN"))
    )
    (comp (ref "U$99")
      (value "RGBLEDAN")
      (footprint "eagle-import:LED5MMRGB")
      (libsource (lib "eagle-import") (part "RGBLEDAN"))
    )
    (comp (ref "U$100")
      (value "RGBLEDAN")
      (footprint "eagle-import:LED5MMRGB")
      (libsource (lib "eagle-import") (part "RGBLEDAN"))
    )
    (comp (ref "U$101")
      (value "RGBLEDAN")
      (footprint "eagle-import:LED5MMRGB")
      (libsource (lib "eagle-import") (part "RGBLEDAN"))
    )
    (comp (ref "U$102")
      (value "RGBLEDAN")
      (footprint "eagle-import:LED5MMRGB")
      (libsource (lib "eagle-import") (part "RGBLEDAN"))
    )
    (comp (ref "U$103")
      (value "RGBLEDAN")
      (footprint "eagle-import:LED5MMRGB")
      (libsource (lib "eagle-import") (part "RGBLEDAN"))
    )
    (comp (ref "U$104")
      (value "RGBLEDAN")
      (footprint "eagle-import:LED5MMRGB")
      (libsource (lib "eagle-import") (part "RGBLEDAN"))
    )
    (comp (ref "U$105")
      (value "RGBLEDAN")
      (footprint "eagle-import:LED5MMRGB")
      (libsource (lib "eagle-import") (part "RGBLEDAN"))
    )
    (comp (ref "U$106")
      (value "RGBLEDAN")
      (footprint "eagle-import:LED5MMRGB")
      (libsource (lib "eagle-import") (part "RGBLEDAN"))
    )
    (comp (ref "U$107")
      (value "RGBLEDAN")
      (footprint "eagle-import:LED5MMRGB")
      (libsource (lib "eagle-import") (part "RGBLEDAN"))
    )
    (comp (ref "U$108")
      (value "RGBLEDAN")
      (footprint "eagle-import:LED5MMRGB")
      (libsource (lib "eagle-import") (part "RGBLEDAN"))
    )
    (comp (ref "U$109")
      (value "RGBLEDAN")
      (footprint "eagle-import:LED5MMRGB")
      (libsource (lib "eagle-import") (part "RGBLEDAN"))
    )
    (comp (ref "U$110")
      (value "RGBLEDAN")
      (footprint "eagle-import:LED5MMRGB")
      (libsource (lib "eagle-import") (part "RGBLEDAN"))
    )
    (comp (ref "U$111")
      (value "RGBLEDAN")
      (footprint "eagle-import:LED5MMRGB")
      (libsource (lib "eagle-import") (part "RGBLEDAN"))
    )
    (comp (ref "U$112")
      (value "RGBLEDAN")
      (footprint "eagle-import:LED5MMRGB")
      (libsource (lib "eagle-import") (part "RGBLEDAN"))
    )
    (comp (ref "U$113")
      (value "RGBLEDAN")
      (footprint "eagle-import:LED5MMRGB")
      (libsource (lib "eagle-import") (part "RGBLEDAN"))
    )
    (comp (ref "U$114")
      (value "RGBLEDAN")
      (footprint "eagle-import:LED5MMRGB")
      (libsource (lib "eagle-import") (part "RGBLEDAN"))
    )
    (comp (ref "U$115")
      (value "RGBLEDAN")
      (footprint "eagle-import:LED5MMRGB")
      (libsource (lib "eagle-import") (part "RGBLEDAN"))
    )
    (comp (ref "U$116")
      (value "RGBLEDAN")
      (footprint "eagle-import:LED5MMRGB")
      (libsource (lib "eagle-import") (part "RGBLEDAN"))
    )
    (comp (ref "U$117")
      (value "RGBLEDAN")
      (footprint "eagle-import:LED5MMRGB")
      (libsource (lib "eagle-import") (part "RGBLEDAN"))
    )
    (comp (ref "U$118")
      (value "RGBLEDAN")
      (footprint "eagle-import:LED5MMRGB")
      (libsource (lib "eagle-import") (part "RGBLEDAN"))
    )
    (comp (ref "U$119")
      (value "RGBLEDAN")
      (footprint "eagle-import:LED5MMRGB")
      (libsource (lib "eagle-import") (part "RGBLEDAN"))
    )
    (comp (ref "U$120")
      (value "RGBLEDAN")
      (footprint "eagle-import:LED5MMRGB")
      (libsource (lib "eagle-import") (part "RGBLEDAN"))
    )
    (comp (ref "U$121")
      (value "RGBLEDAN")
      (footprint "eagle-import:LED5MMRGB")
      (libsource (lib "eagle-import") (part "RGBLEDAN"))
    )
    (comp (ref "U$122")
      (value "RGBLEDAN")
      (footprint "eagle-import:LED5MMRGB")
      (libsource (lib "eagle-import") (part "RGBLEDAN"))
    )
    (comp (ref "U$123")
      (value "RGBLEDAN")
      (footprint "eagle-import:LED5MMRGB")
      (libsource (lib "eagle-import") (part "RGBLEDAN"))
    )
    (comp (ref "U$124")
      (value "RGBLEDAN")
      (footprint "eagle-import:LED5MMRGB")
      (libsource (lib "eagle-import") (part "RGBLEDAN"))
    )
    (comp (ref "U$125")
      (value "RGBLEDAN")
      (footprint "eagle-import:LED5MMRGB")
      (libsource (lib "eagle-import") (part "RGBLEDAN"))
    )
    (comp (ref "U$126")
      (value "RGBLEDAN")
      (footprint "eagle-import:LED5MMRGB")
      (libsource (lib "eagle-import") (part "RGBLEDAN"))
    )
    (comp (ref "U$127")
      (value "RGBLEDAN")
      (footprint "eagle-import:LED5MMRGB")
      (libsource (lib "eagle-import") (part "RGBLEDAN"))
    )
    (comp (ref "U$128")
      (value "RGBLEDAN")
      (footprint "eagle-import:LED5MMRGB")
      (libsource (lib "eagle-import") (part "RGBLEDAN"))
    )
    (comp (ref "U$129")
      (value "RGBLEDAN")
      (footprint "eagle-import:LED5MMRGB")
      (libsource (lib "eagle-import") (part "RGBLEDAN"))
    )
    (comp (ref "U$130")
      (value "RGBLEDAN")
      (footprint "eagle-import:LED5MMRGB")
      (libsource (lib "eagle-import") (part "RGBLEDAN"))
    )
    (comp (ref "U$131")
      (value "RGBLEDAN")
      (footprint "eagle-import:LED5MMRGB")
      (libsource (lib "eagle-import") (part "RGBLEDAN"))
    )
    (comp (ref "U$132")
      (value "RGBLEDAN")
      (footprint "eagle-import:LED5MMRGB")
      (libsource (lib "eagle-import") (part "RGBLEDAN"))
    )
    (comp (ref "U$133")
      (value "RGBLEDAN")
      (footprint "eagle-import:LED5MMRGB")
      (libsource (lib "eagle-import") (part "RGBLEDAN"))
    )
    (comp (ref "U$134")
      (value "RGBLEDAN")
      (footprint "eagle-import:LED5MMRGB")
      (libsource (lib "eagle-import") (part "RGBLEDAN"))
    )
    (comp (ref "U$135")
      (value "RGBLEDAN")
      (footprint "eagle-import:LED5MMRGB")
      (libsource (lib "eagle-import") (part "RGBLEDAN"))
    )
    (comp (ref "U$136")
      (value "RGBLEDAN")
      (footprint "eagle-import:LED5MMRGB")
      (libsource (lib "eagle-import") (part "RGBLEDAN"))
    )
    (comp (ref "U$137")
      (value "RGBLEDAN")
      (footprint "eagle-import:LED5MMRGB")
      (libsource (lib "eagle-import") (part "RGBLEDAN"))
    )
    (comp (ref "U$138")
      (value "RGBLEDAN")
      (footprint "eagle-import:LED5MMRGB")
      (libsource (lib "eagle-import") (part "RGBLEDAN"))
    )
    (comp (ref "U$139")
      (value "RGBLEDAN")
      (footprint "eagle-import:LED5MMRGB")
      (libsource (lib "eagle-import") (part "RGBLEDAN"))
    )
    (comp (ref "U$140")
      (value "RGBLEDAN")
      (footprint "eagle-import:LED5MMRGB")
      (libsource (lib "eagle-import") (part "RGBLEDAN"))
    )
    (comp (ref "U$141")
      (value "RGBLEDAN")
      (footprint "eagle-import:LED5MMRGB")
      (libsource (lib "eagle-import") (part "RGBLEDAN"))
    )
    (comp (ref "U$142")
      (value "RGBLEDAN")
      (footprint "eagle-import:LED5MMRGB")
      (libsource (lib "eagle-import") (part "RGBLEDAN"))
    )
    (comp (ref "U$143")
      (value "RGBLEDAN")
      (footprint "eagle-import:LED5MMRGB")
      (libsource (lib "eagle-import") (part "RGBLEDAN"))
    )
    (comp (ref "U$144")
      (value "RGBLEDAN")
      (footprint "eagle-import:LED5MMRGB")
      (libsource (lib "eagle-import") (part "RGBLEDAN"))
    )
    (comp (ref "U$145")
      (value "RGBLEDAN")
      (footprint "eagle-import:LED5MMRGB")
      (libsource (lib "eagle-import") (part "RGBLEDAN"))
    )
    (comp (ref "U$146")
      (value "RGBLEDAN")
      (footprint "eagle-import:LED5MMRGB")
      (libsource (lib "eagle-import") (part "RGBLEDAN"))
    )
    (comp (ref "U$147")
      (value "RGBLEDAN")
      (footprint "eagle-import:LED5MMRGB")
      (libsource (lib "eagle-import") (part "RGBLEDAN"))
    )
    (comp (ref "U$148")
      (value "RGBLEDAN")
      (footprint "eagle-import:LED5MMRGB")
      (libsource (lib "eagle-import") (part "RGBLEDAN"))
    )
    (comp (ref "U$149")
      (value "RGBLEDAN")
      (footprint "eagle-import:LED5MMRGB")
      (libsource (lib "eagle-import") (part "RGBLEDAN"))
    )
    (comp (ref "U$150")
      (value "RGBLEDAN")
      (footprint "eagle-import:LED5MMRGB")
      (libsource (lib "eagle-import") (part "RGBLEDAN"))
    )
    (comp (ref "U$151")
      (value "RGBLEDAN")
      (footprint "eagle-import:LED5MMRGB")
      (libsource (lib "eagle-import") (part "RGBLEDAN"))
    )
    (comp (ref "U$152")
      (value "RGBLEDAN")
      (footprint "eagle-import:LED5MMRGB")
      (libsource (lib "eagle-import") (part "RGBLEDAN"))
    )
    (comp (ref "U$153")
      (value "RGBLEDAN")
      (footprint "eagle-import:LED5MMRGB")
      (libsource (lib "eagle-import") (part "RGBLEDAN"))
    )
    (comp (ref "U$154")
      (value "RGBLEDAN")
      (footprint "eagle-import:LED5MMRGB")
      (libsource (lib "eagle-import") (part "RGBLEDAN"))
    )
    (comp (ref "U$155")
      (value "RGBLEDAN")
      (footprint "eagle-import:LED5MMRGB")
      (libsource (lib "eagle-import") (part "RGBLEDAN"))
    )
    (comp (ref "U$156")
      (value "RGBLEDAN")
      (footprint "eagle-import:LED5MMRGB")
      (libsource (lib "eagle-import") (part "RGBLEDAN"))
    )
    (comp (ref "U$157")
      (value "RGBLEDAN")
      (footprint "eagle-import:LED5MMRGB")
      (libsource (lib "eagle-import") (part "RGBLEDAN"))
    )
    (comp (ref "U$158")
      (value "RGBLEDAN")
      (footprint "eagle-import:LED5MMRGB")
      (libsource (lib "eagle-import") (part "RGBLEDAN"))
    )
    (comp (ref "U$159")
      (value "RGBLEDAN")
      (footprint "eagle-import:LED5MMRGB")
      (libsource (lib "eagle-import") (part "RGBLEDAN"))
    )
    (comp (ref "U$160")
      (value "RGBLEDAN")
      (footprint "eagle-import:LED5MMRGB")
      (libsource (lib "eagle-import") (part "RGBLEDAN"))
    )
    (comp (ref "U$161")
      (value "RGBLEDAN")
      (footprint "eagle-import:LED5MMRGB")
      (libsource (lib "eagle-import") (part "RGBLEDAN"))
    )
    (comp (ref "U$162")
      (value "RGBLEDAN")
      (footprint "eagle-import:LED5MMRGB")
      (libsource (lib "eagle-import") (part "RGBLEDAN"))
    )
    (comp (ref "U$163")
      (value "RGBLEDAN")
      (footprint "eagle-import:LED5MMRGB")
      (libsource (lib "eagle-import") (part "RGBLEDAN"))
    )
    (comp (ref "U$164")
      (value "RGBLEDAN")
      (footprint "eagle-import:LED5MMRGB")
      (libsource (lib "eagle-import") (part "RGBLEDAN"))
    )
    (comp (ref "U$165")
      (value "RGBLEDAN")
      (footprint "eagle-import:LED5MMRGB")
      (libsource (lib "eagle-import") (part "RGBLEDAN"))
    )
    (comp (ref "U$166")
      (value "RGBLEDAN")
      (footprint "eagle-import:LED5MMRGB")
      (libsource (lib "eagle-import") (part "RGBLEDAN"))
    )
    (comp (ref "U$167")
      (value "RGBLEDAN")
      (footprint "eagle-import:LED5MMRGB")
      (libsource (lib "eagle-import") (part "RGBLEDAN"))
    )
    (comp (ref "U$168")
      (value "RGBLEDAN")
      (footprint "eagle-import:LED5MMRGB")
      (libsource (lib "eagle-import") (part "RGBLEDAN"))
    )
    (comp (ref "U$169")
      (value "RGBLEDAN")
      (footprint "eagle-import:LED5MMRGB")
      (libsource (lib "eagle-import") (part "RGBLEDAN"))
    )
    (comp (ref "U$170")
      (value "RGBLEDAN")
      (footprint "eagle-import:LED5MMRGB")
      (libsource (lib "eagle-import") (part "RGBLEDAN"))
    )
    (comp (ref "U$171")
      (value "RGBLEDAN")
      (footprint "eagle-import:LED5MMRGB")
      (libsource (lib "eagle-import") (part "RGBLEDAN"))
    )
    (comp (ref "U$172")
      (value "RGBLEDAN")
      (footprint "eagle-import:LED5MMRGB")
      (libsource (lib "eagle-import") (part "RGBLEDAN"))
    )
    (comp (ref "U$173")
      (value "RGBLEDAN")
      (footprint "eagle-import:LED5MMRGB")
      (libsource (lib "eagle-import") (part "RGBLEDAN"))
    )
    (comp (ref "U$174")
      (value "RGBLEDAN")
      (footprint "eagle-import:LED5MMRGB")
      (libsource (lib "eagle-import") (part "RGBLEDAN"))
    )
    (comp (ref "U$175")
      (value "RGBLEDAN")
      (footprint "eagle-import:LED5MMRGB")
      (libsource (lib "eagle-import") (part "RGBLEDAN"))
    )
    (comp (ref "U$176")
      (value "RGBLEDAN")
      (footprint "eagle-import:LED5MMRGB")
      (libsource (lib "eagle-import") (part "RGBLEDAN"))
    )
    (comp (ref "U$177")
      (value "RGBLEDAN")
      (footprint "eagle-import:LED5MMRGB")
      (libsource (lib "eagle-import") (part "RGBLEDAN"))
    )
    (comp (ref "U$178")
      (value "RGBLEDAN")
      (footprint "eagle-import:LED5MMRGB")
      (libsource (lib "eagle-import") (part "RGBLEDAN"))
    )
    (comp (ref "U$179")
      (value "RGBLEDAN")
      (footprint "eagle-import:LED5MMRGB")
      (libsource (lib "eagle-import") (part "RGBLEDAN"))
    )
    (comp (ref "U$180")
      (value "RGBLEDAN")
      (footprint "eagle-import:LED5MMRGB")
      (libsource (lib "eagle-import") (part "RGBLEDAN"))
    )
    (comp (ref "U$181")
      (value "RGBLEDAN")
      (footprint "eagle-import:LED5MMRGB")
      (libsource (lib "eagle-import") (part "RGBLEDAN"))
    )
    (comp (ref "U$182")
      (value "RGBLEDAN")
      (footprint "eagle-import:LED5MMRGB")
      (libsource (lib "eagle-import") (part "RGBLEDAN"))
    )
    (comp (ref "U$183")
      (value "RGBLEDAN")
      (footprint "eagle-import:LED5MMRGB")
      (libsource (lib "eagle-import") (part "RGBLEDAN"))
    )
    (comp (ref "U$184")
      (value "RGBLEDAN")
      (footprint "eagle-import:LED5MMRGB")
      (libsource (lib "eagle-import") (part "RGBLEDAN"))
    )
    (comp (ref "U$185")
      (value "RGBLEDAN")
      (footprint "eagle-import:LED5MMRGB")
      (libsource (lib "eagle-import") (part "RGBLEDAN"))
    )
    (comp (ref "U$186")
      (value "RGBLEDAN")
      (footprint "eagle-import:LED5MMRGB")
      (libsource (lib "eagle-import") (part "RGBLEDAN"))
    )
    (comp (ref "U$187")
      (value "RGBLEDAN")
      (footprint "eagle-import:LED5MMRGB")
      (libsource (lib "eagle-import") (part "RGBLEDAN"))
    )
    (comp (ref "U$188")
      (value "RGBLEDAN")
      (footprint "eagle-import:LED5MMRGB")
      (libsource (lib "eagle-import") (part "RGBLEDAN"))
    )
    (comp (ref "U$189")
      (value "RGBLEDAN")
      (footprint "eagle-import:LED5MMRGB")
      (libsource (lib "eagle-import") (part "RGBLEDAN"))
    )
    (comp (ref "U$190")
      (value "RGBLEDAN")
      (footprint "eagle-import:LED5MMRGB")
      (libsource (lib "eagle-import") (part "RGBLEDAN"))
    )
    (comp (ref "U$191")
      (value "RGBLEDAN")
      (footprint "eagle-import:LED5MMRGB")
      (libsource (lib "eagle-import") (part "RGBLEDAN"))
    )
    (comp (ref "U$192")
      (value "RGBLEDAN")
      (footprint "eagle-import:LED5MMRGB")
      (libsource (lib "eagle-import") (part "RGBLEDAN"))
    )
    (comp (ref "U$193")
      (value "RGBLEDAN")
      (footprint "eagle-import:LED5MMRGB")
      (libsource (lib "eagle-import") (part "RGBLEDAN"))
    )
    (comp (ref "U$194")
      (value "RGBLEDAN")
      (footprint "eagle-import:LED5MMRGB")
      (libsource (lib "eagle-import") (part "RGBLEDAN"))
    )
    (comp (ref "U$195")
      (value "RGBLEDAN")
      (footprint "eagle-import:LED5MMRGB")
      (libsource (lib "eagle-import") (part "RGBLEDAN"))
    )
    (comp (ref "U$196")
      (value "RGBLEDAN")
      (footprint "eagle-import:LED5MMRGB")
      (libsource (lib "eagle-import") (part "RGBLEDAN"))
    )
    (comp (ref "U$197")
      (value "RGBLEDAN")
      (footprint "eagle-import:LED5MMRGB")
      (libsource (lib "eagle-import") (part "RGBLEDAN"))
    )
    (comp (ref "U$198")
      (value "RGBLEDAN")
      (footprint "eagle-import:LED5MMRGB")
      (libsource (lib "eagle-import") (part "RGBLEDAN"))
    )
    (comp (ref "U$199")
      (value "RGBLEDAN")
      (footprint "eagle-import:LED5MMRGB")
      (libsource (lib "eagle-import") (part "RGBLEDAN"))
    )
    (comp (ref "U$200")
      (value "RGBLEDAN")
      (footprint "eagle-import:LED5MMRGB")
      (libsource (lib "eagle-import") (part "RGBLEDAN"))
    )
    (comp (ref "U$201")
      (value "RGBLEDAN")
      (footprint "eagle-import:LED5MMRGB")
      (libsource (lib "eagle-import") (part "RGBLEDAN"))
    )
    (comp (ref "U$202")
      (value "RGBLEDAN")
      (footprint "eagle-import:LED5MMRGB")
      (libsource (lib "eagle-import") (part "RGBLEDAN"))
    )
    (comp (ref "U$203")
      (value "RGBLEDAN")
      (footprint "eagle-import:LED5MMRGB")
      (libsource (lib "eagle-import") (part "RGBLEDAN"))
    )
    (comp (ref "U$204")
      (value "RGBLEDAN")
      (footprint "eagle-import:LED5MMRGB")
      (libsource (lib "eagle-import") (part "RGBLEDAN"))
    )
    (comp (ref "U$205")
      (value "RGBLEDAN")
      (footprint "eagle-import:LED5MMRGB")
      (libsource (lib "eagle-import") (part "RGBLEDAN"))
    )
    (comp (ref "U$206")
      (value "RGBLEDAN")
      (footprint "eagle-import:LED5MMRGB")
      (libsource (lib "eagle-import") (part "RGBLEDAN"))
    )
    (comp (ref "U$207")
      (value "RGBLEDAN")
      (footprint "eagle-import:LED5MMRGB")
      (libsource (lib "eagle-import") (part "RGBLEDAN"))
    )
    (comp (ref "U$208")
      (value "RGBLEDAN")
      (footprint "eagle-import:LED5MMRGB")
      (libsource (lib "eagle-import") (part "RGBLEDAN"))
    )
    (comp (ref "U$209")
      (value "RGBLEDAN")
      (footprint "eagle-import:LED5MMRGB")
      (libsource (lib "eagle-import") (part "RGBLEDAN"))
    )
    (comp (ref "U$210")
      (value "RGBLEDAN")
      (footprint "eagle-import:LED5MMRGB")
      (libsource (lib "eagle-import") (part "RGBLEDAN"))
    )
    (comp (ref "U$211")
      (value "RGBLEDAN")
      (footprint "eagle-import:LED5MMRGB")
      (libsource (lib "eagle-import") (part "RGBLEDAN"))
    )
    (comp (ref "U$212")
      (value "RGBLEDAN")
      (footprint "eagle-import:LED5MMRGB")
      (libsource (lib "eagle-import") (part "RGBLEDAN"))
    )
    (comp (ref "U$213")
      (value "RGBLEDAN")
      (footprint "eagle-import:LED5MMRGB")
      (libsource (lib "eagle-import") (part "RGBLEDAN"))
    )
    (comp (ref "U$214")
      (value "RGBLEDAN")
      (footprint "eagle-import:LED5MMRGB")
      (libsource (lib "eagle-import") (part "RGBLEDAN"))
    )
    (comp (ref "U$215")
      (value "RGBLEDAN")
      (footprint "eagle-import:LED5MMRGB")
      (libsource (lib "eagle-import") (part "RGBLEDAN"))
    )
    (comp (ref "U$216")
      (value "RGBLEDAN")
      (footprint "eagle-import:LED5MMRGB")
      (libsource (lib "eagle-import") (part "RGBLEDAN"))
    )
    (comp (ref "U$217")
      (value "RGBLEDAN")
      (footprint "eagle-import:LED5MMRGB")
      (libsource (lib "eagle-import") (part "RGBLEDAN"))
    )
    (comp (ref "U$218")
      (value "RGBLEDAN")
      (footprint "eagle-import:LED5MMRGB")
      (libsource (lib "eagle-import") (part "RGBLEDAN"))
    )
    (comp (ref "U$219")
      (value "RGBLEDAN")
      (footprint "eagle-import:LED5MMRGB")
      (libsource (lib "eagle-import") (part "RGBLEDAN"))
    )
    (comp (ref "U$220")
      (value "RGBLEDAN")
      (footprint "eagle-import:LED5MMRGB")
      (libsource (lib "eagle-import") (part "RGBLEDAN"))
    )
    (comp (ref "U$221")
      (value "RGBLEDAN")
      (footprint "eagle-import:LED5MMRGB")
      (libsource (lib "eagle-import") (part "RGBLEDAN"))
    )
    (comp (ref "U$222")
      (value "RGBLEDAN")
      (footprint "eagle-import:LED5MMRGB")
      (libsource (lib "eagle-import") (part "RGBLEDAN"))
    )
    (comp (ref "U$223")
      (value "RGBLEDAN")
      (footprint "eagle-import:LED5MMRGB")
      (libsource (lib "eagle-import") (part "RGBLEDAN"))
    )
    (comp (ref "U$224")
      (value "RGBLEDAN")
      (footprint "eagle-import:LED5MMRGB")
      (libsource (lib "eagle-import") (part "RGBLEDAN"))
    )
    (comp (ref "U$225")
      (value "RGBLEDAN")
      (footprint "eagle-import:LED5MMRGB")
      (libsource (lib "eagle-import") (part "RGBLEDAN"))
    )
    (comp (ref "U$226")
      (value "RGBLEDAN")
      (footprint "eagle-import:LED5MMRGB")
      (libsource (lib "eagle-import") (part "RGBLEDAN"))
    )
    (comp (ref "U$227")
      (value "RGBLEDAN")
      (footprint "eagle-import:LED5MMRGB")
      (libsource (lib "eagle-import") (part "RGBLEDAN"))
    )
    (comp (ref "U$228")
      (value "RGBLEDAN")
      (footprint "eagle-import:LED5MMRGB")
      (libsource (lib "eagle-import") (part "RGBLEDAN"))
    )
    (comp (ref "U$229")
      (value "RGBLEDAN")
      (footprint "eagle-import:LED5MMRGB")
      (libsource (lib "eagle-import") (part "RGBLEDAN"))
    )
    (comp (ref "U$230")
      (value "RGBLEDAN")
      (footprint "eagle-import:LED5MMRGB")
      (libsource (lib "eagle-import") (part "RGBLEDAN"))
    )
    (comp (ref "U$231")
      (value "RGBLEDAN")
      (footprint "eagle-import:LED5MMRGB")
      (libsource (lib "eagle-import") (part "RGBLEDAN"))
    )
    (comp (ref "U$232")
      (value "RGBLEDAN")
      (footprint "eagle-import:LED5MMRGB")
      (libsource (lib "eagle-import") (part "RGBLEDAN"))
    )
    (comp (ref "U$233")
      (value "RGBLEDAN")
      (footprint "eagle-import:LED5MMRGB")
      (libsource (lib "eagle-import") (part "RGBLEDAN"))
    )
    (comp (ref "U$234")
      (value "RGBLEDAN")
      (footprint "eagle-import:LED5MMRGB")
      (libsource (lib "eagle-import") (part "RGBLEDAN"))
    )
    (comp (ref "U$235")
      (value "RGBLEDAN")
      (footprint "eagle-import:LED5MMRGB")
      (libsource (lib "eagle-import") (part "RGBLEDAN"))
    )
    (comp (ref "U$236")
      (value "RGBLEDAN")
      (footprint "eagle-import:LED5MMRGB")
      (libsource (lib "eagle-import") (part "RGBLEDAN"))
    )
    (comp (ref "U$237")
      (value "RGBLEDAN")
      (footprint "eagle-import:LED5MMRGB")
      (libsource (lib "eagle-import") (part "RGBLEDAN"))
    )
    (comp (ref "U$238")
      (value "RGBLEDAN")
      (footprint "eagle-import:LED5MMRGB")
      (libsource (lib "eagle-import") (part "RGBLEDAN"))
    )
    (comp (ref "U$239")
      (value "RGBLEDAN")
      (footprint "eagle-import:LED5MMRGB")
      (libsource (lib "eagle-import") (part "RGBLEDAN"))
    )
    (comp (ref "U$240")
      (value "RGBLEDAN")
      (footprint "eagle-import:LED5MMRGB")
      (libsource (lib "eagle-import") (part "RGBLEDAN"))
    )
    (comp (ref "U$241")
      (value "RGBLEDAN")
      (footprint "eagle-import:LED5MMRGB")
      (libsource (lib "eagle-import") (part "RGBLEDAN"))
    )
    (comp (ref "U$242")
      (value "RGBLEDAN")
      (footprint "eagle-import:LED5MMRGB")
      (libsource (lib "eagle-import") (part "RGBLEDAN"))
    )
    (comp (ref "U$243")
      (value "RGBLEDAN")
      (footprint "eagle-import:LED5MMRGB")
      (libsource (lib "eagle-import") (part "RGBLEDAN"))
    )
    (comp (ref "U$244")
      (value "RGBLEDAN")
      (footprint "eagle-import:LED5MMRGB")
      (libsource (lib "eagle-import") (part "RGBLEDAN"))
    )
    (comp (ref "U$245")
      (value "RGBLEDAN")
      (footprint "eagle-import:LED5MMRGB")
      (libsource (lib "eagle-import") (part "RGBLEDAN"))
    )
    (comp (ref "U$246")
      (value "RGBLEDAN")
      (footprint "eagle-import:LED5MMRGB")
      (libsource (lib "eagle-import") (part "RGBLEDAN"))
    )
    (comp (ref "U$247")
      (value "RGBLEDAN")
      (footprint "eagle-import:LED5MMRGB")
      (libsource (lib "eagle-import") (part "RGBLEDAN"))
    )
    (comp (ref "U$248")
      (value "RGBLEDAN")
      (footprint "eagle-import:LED5MMRGB")
      (libsource (lib "eagle-import") (part "RGBLEDAN"))
    )
    (comp (ref "U$249")
      (value "RGBLEDAN")
      (footprint "eagle-import:LED5MMRGB")
      (libsource (lib "eagle-import") (part "RGBLEDAN"))
    )
    (comp (ref "U$250")
      (value "RGBLEDAN")
      (footprint "eagle-import:LED5MMRGB")
      (libsource (lib "eagle-import") (part "RGBLEDAN"))
    )
    (comp (ref "U$251")
      (value "RGBLEDAN")
      (footprint "eagle-import:LED5MMRGB")
      (libsource (lib "eagle-import") (part "RGBLEDAN"))
    )
    (comp (ref "U$252")
      (value "RGBLEDAN")
      (footprint "eagle-import:LED5MMRGB")
      (libsource (lib "eagle-import") (part "RGBLEDAN"))
    )
    (comp (ref "U$253")
      (value "RGBLEDAN")
      (footprint "eagle-import:LED5MMRGB")
      (libsource (lib "eagle-import") (part "RGBLEDAN"))
    )
    (comp (ref "U$254")
      (value "RGBLEDAN")
      (footprint "eagle-import:LED5MMRGB")
      (libsource (lib "eagle-import") (part "RGBLEDAN"))
    )
    (comp (ref "U$255")
      (value "RGBLEDAN")
      (footprint "eagle-import:LED5MMRGB")
      (libsource (lib "eagle-import") (part "RGBLEDAN"))
    )
    (comp (ref "U$256")
      (value "RGBLEDAN")
      (footprint "eagle-import:LED5MMRGB")
      (libsource (lib "eagle-import") (part "RGBLEDAN"))
    )
    (comp (ref "U$257")
      (value "RGBLEDAN")
      (footprint "eagle-import:LED5MMRGB")
      (libsource (lib "eagle-import") (part "RGBLEDAN"))
    )
    (comp (ref "U$258")
      (value "RGBLEDAN")
      (footprint "eagle-import:LED5MMRGB")
      (libsource (lib "eagle-import") (part "RGBLEDAN"))
    )
    (comp (ref "U$259")
      (value "RGBLEDAN")
      (footprint "eagle-import:LED5MMRGB")
      (libsource (lib "eagle-import") (part "RGBLEDAN"))
    )
    (comp (ref "U$260")
      (value "RGBLEDAN")
      (footprint "eagle-import:LED5MMRGB")
      (libsource (lib "eagle-import") (part "RGBLEDAN"))
    )
    (comp (ref "U$261")
      (value "RGBLEDAN")
      (footprint "eagle-import:LED5MMRGB")
      (libsource (lib "eagle-import") (part "RGBLEDAN"))
    )
    (comp (ref "U$262")
      (value "RGBLEDAN")
      (footprint "eagle-import:LED5MMRGB")
      (libsource (lib "eagle-import") (part "RGBLEDAN"))
    )
    (comp (ref "U$263")
      (value "RGBLEDAN")
      (footprint "eagle-import:LED5MMRGB")
      (libsource (lib "eagle-import") (part "RGBLEDAN"))
    )
    (comp (ref "U$264")
      (value "RGBLEDAN")
      (footprint "eagle-import:LED5MMRGB")
      (libsource (lib "eagle-import") (part "RGBLEDAN"))
    )
    (comp (ref "U$265")
      (value "RGBLEDAN")
      (footprint "eagle-import:LED5MMRGB")
      (libsource (lib "eagle-import") (part "RGBLEDAN"))
    )
    (comp (ref "U$266")
      (value "RGBLEDAN")
      (footprint "eagle-import:LED5MMRGB")
      (libsource (lib "eagle-import") (part "RGBLEDAN"))
    )
    (comp (ref "U$267")
      (value "RGBLEDAN")
      (footprint "eagle-import:LED5MMRGB")
      (libsource (lib "eagle-import") (part "RGBLEDAN"))
    )
    (comp (ref "U$268")
      (value "RGBLEDAN")
      (footprint "eagle-import:LED5MMRGB")
      (libsource (lib "eagle-import") (part "RGBLEDAN"))
    )
    (comp (ref "U$269")
      (value "RGBLEDAN")
      (footprint "eagle-import:LED5MMRGB")
      (libsource (lib "eagle-import") (part "RGBLEDAN"))
    )
    (comp (ref "U$270")
      (value "RGBLEDAN")
      (footprint "eagle-import:LED5MMRGB")
      (libsource (lib "eagle-import") (part "RGBLEDAN"))
    )
    (comp (ref "U$271")
      (value "RGBLEDAN")
      (footprint "eagle-import:LED5MMRGB")
      (libsource (lib "eagle-import") (part "RGBLEDAN"))
    )
    (comp (ref "U$272")
      (value "RGBLEDAN")
      (footprint "eagle-import:LED5MMRGB")
      (libsource (lib "eagle-import") (part "RGBLEDAN"))
    )
    (comp (ref "U$273")
      (value "RGBLEDAN")
      (footprint "eagle-import:LED5MMRGB")
      (libsource (lib "eagle-import") (part "RGBLEDAN"))
    )
    (comp (ref "U$274")
      (value "RGBLEDAN")
      (footprint "eagle-import:LED5MMRGB")
      (libsource (lib "eagle-import") (part "RGBLEDAN"))
    )
    (comp (ref "U$275")
      (value "RGBLEDAN")
      (footprint "eagle-import:LED5MMRGB")
      (libsource (lib "eagle-import") (part "RGBLEDAN"))
    )
    (comp (ref "U$276")
      (value "RGBLEDAN")
      (footprint "eagle-import:LED5MMRGB")
      (libsource (lib "eagle-import") (part "RGBLEDAN"))
    )
    (comp (ref "U$277")
      (value "RGBLEDAN")
      (footprint "eagle-import:LED5MMRGB")
      (libsource (lib "eagle-import") (part "RGBLEDAN"))
    )
    (comp (ref "U$278")
      (value "RGBLEDAN")
      (footprint "eagle-import:LED5MMRGB")
      (libsource (lib "eagle-import") (part "RGBLEDAN"))
    )
    (comp (ref "U$279")
      (value "RGBLEDAN")
      (footprint "eagle-import:LED5MMRGB")
      (libsource (lib "eagle-import") (part "RGBLEDAN"))
    )
    (comp (ref "U$280")
      (value "RGBLEDAN")
      (footprint "eagle-import:LED5MMRGB")
      (libsource (lib "eagle-import") (part "RGBLEDAN"))
    )
    (comp (ref "U$281")
      (value "RGBLEDAN")
      (footprint "eagle-import:LED5MMRGB")
      (libsource (lib "eagle-import") (part "RGBLEDAN"))
    )
    (comp (ref "U$282")
      (value "RGBLEDAN")
      (footprint "eagle-import:LED5MMRGB")
      (libsource (lib "eagle-import") (part "RGBLEDAN"))
    )
    (comp (ref "U$283")
      (value "RGBLEDAN")
      (footprint "eagle-import:LED5MMRGB")
      (libsource (lib "eagle-import") (part "RGBLEDAN"))
    )
    (comp (ref "U$284")
      (value "RGBLEDAN")
      (footprint "eagle-import:LED5MMRGB")
      (libsource (lib "eagle-import") (part "RGBLEDAN"))
    )
    (comp (ref "U$285")
      (value "RGBLEDAN")
      (footprint "eagle-import:LED5MMRGB")
      (libsource (lib "eagle-import") (part "RGBLEDAN"))
    )
    (comp (ref "U$286")
      (value "RGBLEDAN")
      (footprint "eagle-import:LED5MMRGB")
      (libsource (lib "eagle-import") (part "RGBLEDAN"))
    )
    (comp (ref "U$287")
      (value "RGBLEDAN")
      (footprint "eagle-import:LED5MMRGB")
      (libsource (lib "eagle-import") (part "RGBLEDAN"))
    )
    (comp (ref "U$288")
      (value "RGBLEDAN")
      (footprint "eagle-import:LED5MMRGB")
      (libsource (lib "eagle-import") (part "RGBLEDAN"))
    )
    (comp (ref "U$289")
      (value "RGBLEDAN")
      (footprint "eagle-import:LED5MMRGB")
      (libsource (lib "eagle-import") (part "RGBLEDAN"))
    )
    (comp (ref "U$290")
      (value "RGBLEDAN")
      (footprint "eagle-import:LED5MMRGB")
      (libsource (lib "eagle-import") (part "RGBLEDAN"))
    )
    (comp (ref "U$291")
      (value "RGBLEDAN")
      (footprint "eagle-import:LED5MMRGB")
      (libsource (lib "eagle-import") (part "RGBLEDAN"))
    )
    (comp (ref "U$292")
      (value "RGBLEDAN")
      (footprint "eagle-import:LED5MMRGB")
      (libsource (lib "eagle-import") (part "RGBLEDAN"))
    )
    (comp (ref "U$293")
      (value "RGBLEDAN")
      (footprint "eagle-import:LED5MMRGB")
      (libsource (lib "eagle-import") (part "RGBLEDAN"))
    )
    (comp (ref "U$294")
      (value "RGBLEDAN")
      (footprint "eagle-import:LED5MMRGB")
      (libsource (lib "eagle-import") (part "RGBLEDAN"))
    )
    (comp (ref "U$295")
      (value "RGBLEDAN")
      (footprint "eagle-import:LED5MMRGB")
      (libsource (lib "eagle-import") (part "RGBLEDAN"))
    )
    (comp (ref "U$296")
      (value "RGBLEDAN")
      (footprint "eagle-import:LED5MMRGB")
      (libsource (lib "eagle-import") (part "RGBLEDAN"))
    )
    (comp (ref "U$297")
      (value "RGBLEDAN")
      (footprint "eagle-import:LED5MMRGB")
      (libsource (lib "eagle-import") (part "RGBLEDAN"))
    )
    (comp (ref "U$298")
      (value "RGBLEDAN")
      (footprint "eagle-import:LED5MMRGB")
      (libsource (lib "eagle-import") (part "RGBLEDAN"))
    )
    (comp (ref "U$299")
      (value "RGBLEDAN")
      (footprint "eagle-import:LED5MMRGB")
      (libsource (lib "eagle-import") (part "RGBLEDAN"))
    )
    (comp (ref "U$300")
      (value "RGBLEDAN")
      (footprint "eagle-import:LED5MMRGB")
      (libsource (lib "eagle-import") (part "RGBLEDAN"))
    )
    (comp (ref "U$301")
      (value "RGBLEDAN")
      (footprint "eagle-import:LED5MMRGB")
      (libsource (lib "eagle-import") (part "RGBLEDAN"))
    )
    (comp (ref "U$302")
      (value "RGBLEDAN")
      (footprint "eagle-import:LED5MMRGB")
      (libsource (lib "eagle-import") (part "RGBLEDAN"))
    )
    (comp (ref "U$303")
      (value "RGBLEDAN")
      (footprint "eagle-import:LED5MMRGB")
      (libsource (lib "eagle-import") (part "RGBLEDAN"))
    )
    (comp (ref "U$304")
      (value "RGBLEDAN")
      (footprint "eagle-import:LED5MMRGB")
      (libsource (lib "eagle-import") (part "RGBLEDAN"))
    )
    (comp (ref "U$305")
      (value "RGBLEDAN")
      (footprint "eagle-import:LED5MMRGB")
      (libsource (lib "eagle-import") (part "RGBLEDAN"))
    )
    (comp (ref "U$306")
      (value "RGBLEDAN")
      (footprint "eagle-import:LED5MMRGB")
      (libsource (lib "eagle-import") (part "RGBLEDAN"))
    )
    (comp (ref "U$307")
      (value "RGBLEDAN")
      (footprint "eagle-import:LED5MMRGB")
      (libsource (lib "eagle-import") (part "RGBLEDAN"))
    )
    (comp (ref "U$308")
      (value "RGBLEDAN")
      (footprint "eagle-import:LED5MMRGB")
      (libsource (lib "eagle-import") (part "RGBLEDAN"))
    )
    (comp (ref "U$309")
      (value "RGBLEDAN")
      (footprint "eagle-import:LED5MMRGB")
      (libsource (lib "eagle-import") (part "RGBLEDAN"))
    )
    (comp (ref "U$310")
      (value "RGBLEDAN")
      (footprint "eagle-import:LED5MMRGB")
      (libsource (lib "eagle-import") (part "RGBLEDAN"))
    )
    (comp (ref "U$311")
      (value "RGBLEDAN")
      (footprint "eagle-import:LED5MMRGB")
      (libsource (lib "eagle-import") (part "RGBLEDAN"))
    )
    (comp (ref "U$312")
      (value "RGBLEDAN")
      (footprint "eagle-import:LED5MMRGB")
      (libsource (lib "eagle-import") (part "RGBLEDAN"))
    )
    (comp (ref "U$313")
      (value "RGBLEDAN")
      (footprint "eagle-import:LED5MMRGB")
      (libsource (lib "eagle-import") (part "RGBLEDAN"))
    )
    (comp (ref "U$314")
      (value "RGBLEDAN")
      (footprint "eagle-import:LED5MMRGB")
      (libsource (lib "eagle-import") (part "RGBLEDAN"))
    )
    (comp (ref "U$315")
      (value "RGBLEDAN")
      (footprint "eagle-import:LED5MMRGB")
      (libsource (lib "eagle-import") (part "RGBLEDAN"))
    )
    (comp (ref "U$316")
      (value "RGBLEDAN")
      (footprint "eagle-import:LED5MMRGB")
      (libsource (lib "eagle-import") (part "RGBLEDAN"))
    )
    (comp (ref "U$317")
      (value "RGBLEDAN")
      (footprint "eagle-import:LED5MMRGB")
      (libsource (lib "eagle-import") (part "RGBLEDAN"))
    )
    (comp (ref "U$318")
      (value "RGBLEDAN")
      (footprint "eagle-import:LED5MMRGB")
      (libsource (lib "eagle-import") (part "RGBLEDAN"))
    )
    (comp (ref "U$319")
      (value "RGBLEDAN")
      (footprint "eagle-import:LED5MMRGB")
      (libsource (lib "eagle-import") (part "RGBLEDAN"))
    )
    (comp (ref "U$320")
      (value "RGBLEDAN")
      (footprint "eagle-import:LED5MMRGB")
      (libsource (lib "eagle-import") (part "RGBLEDAN"))
    )
    (comp (ref "U$321")
      (value "RGBLEDAN")
      (footprint "eagle-import:LED5MMRGB")
      (libsource (lib "eagle-import") (part "RGBLEDAN"))
    )
    (comp (ref "U$322")
      (value "RGBLEDAN")
      (footprint "eagle-import:LED5MMRGB")
      (libsource (lib "eagle-import") (part "RGBLEDAN"))
    )
    (comp (ref "U$323")
      (value "RGBLEDAN")
      (footprint "eagle-import:LED5MMRGB")
      (libsource (lib "eagle-import") (part "RGBLEDAN"))
    )
    (comp (ref "U$324")
      (value "RGBLEDAN")
      (footprint "eagle-import:LED5MMRGB")
      (libsource (lib "eagle-import") (part "RGBLEDAN"))
    )
    (comp (ref "U$325")
      (value "RGBLEDAN")
      (footprint "eagle-import:LED5MMRGB")
      (libsource (lib "eagle-import") (part "RGBLEDAN"))
    )
    (comp (ref "U$326")
      (value "RGBLEDAN")
      (footprint "eagle-import:LED5MMRGB")
      (libsource (lib "eagle-import") (part "RGBLEDAN"))
    )
    (comp (ref "U$327")
      (value "RGBLEDAN")
      (footprint "eagle-import:LED5MMRGB")
      (libsource (lib "eagle-import") (part "RGBLEDAN"))
    )
    (comp (ref "U$328")
      (value "RGBLEDAN")
      (footprint "eagle-import:LED5MMRGB")
      (libsource (lib "eagle-import") (part "RGBLEDAN"))
    )
    (comp (ref "U$329")
      (value "RGBLEDAN")
      (footprint "eagle-import:LED5MMRGB")
      (libsource (lib "eagle-import") (part "RGBLEDAN"))
    )
    (comp (ref "U$330")
      (value "RGBLEDAN")
      (footprint "eagle-import:LED5MMRGB")
      (libsource (lib "eagle-import") (part "RGBLEDAN"))
    )
    (comp (ref "U$331")
      (value "RGBLEDAN")
      (footprint "eagle-import:LED5MMRGB")
      (libsource (lib "eagle-import") (part "RGBLEDAN"))
    )
    (comp (ref "U$332")
      (value "RGBLEDAN")
      (footprint "eagle-import:LED5MMRGB")
      (libsource (lib "eagle-import") (part "RGBLEDAN"))
    )
    (comp (ref "U$333")
      (value "RGBLEDAN")
      (footprint "eagle-import:LED5MMRGB")
      (libsource (lib "eagle-import") (part "RGBLEDAN"))
    )
    (comp (ref "U$334")
      (value "RGBLEDAN")
      (footprint "eagle-import:LED5MMRGB")
      (libsource (lib "eagle-import") (part "RGBLEDAN"))
    )
    (comp (ref "U$335")
      (value "RGBLEDAN")
      (footprint "eagle-import:LED5MMRGB")
      (libsource (lib "eagle-import") (part "RGBLEDAN"))
    )
    (comp (ref "U$336")
      (value "RGBLEDAN")
      (footprint "eagle-import:LED5MMRGB")
      (libsource (lib "eagle-import") (part "RGBLEDAN"))
    )
    (comp (ref "U$337")
      (value "RGBLEDAN")
      (footprint "eagle-import:LED5MMRGB")
      (libsource (lib "eagle-import") (part "RGBLEDAN"))
    )
    (comp (ref "U$338")
      (value "RGBLEDAN")
      (footprint "eagle-import:LED5MMRGB")
      (libsource (lib "eagle-import") (part "RGBLEDAN"))
    )
    (comp (ref "U$339")
      (value "RGBLEDAN")
      (footprint "eagle-import:LED5MMRGB")
      (libsource (lib "eagle-import") (part "RGBLEDAN"))
    )
    (comp (ref "U$340")
      (value "RGBLEDAN")
      (footprint "eagle-import:LED5MMRGB")
      (libsource (lib "eagle-import") (part "RGBLEDAN"))
    )
    (comp (ref "U$341")
      (value "RGBLEDAN")
      (footprint "eagle-import:LED5MMRGB")
      (libsource (lib "eagle-import") (part "RGBLEDAN"))
    )
    (comp (ref "U$342")
      (value "RGBLEDAN")
      (footprint "eagle-import:LED5MMRGB")
      (libsource (lib "eagle-import") (part "RGBLEDAN"))
    )
    (comp (ref "U$343")
      (value "RGBLEDAN")
      (footprint "eagle-import:LED5MMRGB")
      (libsource (lib "eagle-import") (part "RGBLEDAN"))
    )
    (comp (ref "U$344")
      (value "RGBLEDAN")
      (footprint "eagle-import:LED5MMRGB")
      (libsource (lib "eagle-import") (part "RGBLEDAN"))
    )
    (comp (ref "U$345")
      (value "RGBLEDAN")
      (footprint "eagle-import:LED5MMRGB")
      (libsource (lib "eagle-import") (part "RGBLEDAN"))
    )
    (comp (ref "U$346")
      (value "RGBLEDAN")
      (footprint "eagle-import:LED5MMRGB")
      (libsource (lib "eagle-import") (part "RGBLEDAN"))
    )
    (comp (ref "U$347")
      (value "RGBLEDAN")
      (footprint "eagle-import:LED5MMRGB")
      (libsource (lib "eagle-import") (part "RGBLEDAN"))
    )
    (comp (ref "U$348")
      (value "RGBLEDAN")
      (footprint "eagle-import:LED5MMRGB")
      (libsource (lib "eagle-import") (part "RGBLEDAN"))
    )
    (comp (ref "U$349")
      (value "RGBLEDAN")
      (footprint "eagle-import:LED5MMRGB")
      (libsource (lib "eagle-import") (part "RGBLEDAN"))
    )
    (comp (ref "U$350")
      (value "RGBLEDAN")
      (footprint "eagle-import:LED5MMRGB")
      (libsource (lib "eagle-import") (part "RGBLEDAN"))
    )
    (comp (ref "U$351")
      (value "RGBLEDAN")
      (footprint "eagle-import:LED5MMRGB")
      (libsource (lib "eagle-import") (part "RGBLEDAN"))
    )
    (comp (ref "U$352")
      (value "RGBLEDAN")
      (footprint "eagle-import:LED5MMRGB")
      (libsource (lib "eagle-import") (part "RGBLEDAN"))
    )
    (comp (ref "U$353")
      (value "RGBLEDAN")
      (footprint "eagle-import:LED5MMRGB")
      (libsource (lib "eagle-import") (part "RGBLEDAN"))
    )
    (comp (ref "U$354")
      (value "RGBLEDAN")
      (footprint "eagle-import:LED5MMRGB")
      (libsource (lib "eagle-import") (part "RGBLEDAN"))
    )
    (comp (ref "U$355")
      (value "RGBLEDAN")
      (footprint "eagle-import:LED5MMRGB")
      (libsource (lib "eagle-import") (part "RGBLEDAN"))
    )
    (comp (ref "U$356")
      (value "RGBLEDAN")
      (footprint "eagle-import:LED5MMRGB")
      (libsource (lib "eagle-import") (part "RGBLEDAN"))
    )
    (comp (ref "U$357")
      (value "RGBLEDAN")
      (footprint "eagle-import:LED5MMRGB")
      (libsource (lib "eagle-import") (part "RGBLEDAN"))
    )
    (comp (ref "U$358")
      (value "RGBLEDAN")
      (footprint "eagle-import:LED5MMRGB")
      (libsource (lib "eagle-import") (part "RGBLEDAN"))
    )
    (comp (ref "U$359")
      (value "RGBLEDAN")
      (footprint "eagle-import:LED5MMRGB")
      (libsource (lib "eagle-import") (part "RGBLEDAN"))
    )
    (comp (ref "U$360")
      (value "RGBLEDAN")
      (footprint "eagle-import:LED5MMRGB")
      (libsource (lib "eagle-import") (part "RGBLEDAN"))
    )
    (comp (ref "U$361")
      (value "RGBLEDAN")
      (footprint "eagle-import:LED5MMRGB")
      (libsource (lib "eagle-import") (part "RGBLEDAN"))
    )
    (comp (ref "U$362")
      (value "RGBLEDAN")
      (footprint "eagle-import:LED5MMRGB")
      (libsource (lib "eagle-import") (part "RGBLEDAN"))
    )
    (comp (ref "U$363")
      (value "RGBLEDAN")
      (footprint "eagle-import:LED5MMRGB")
      (libsource (lib "eagle-import") (part "RGBLEDAN"))
    )
    (comp (ref "U$364")
      (value "RGBLEDAN")
      (footprint "eagle-import:LED5MMRGB")
      (libsource (lib "eagle-import") (part "RGBLEDAN"))
    )
    (comp (ref "U$365")
      (value "RGBLEDAN")
      (footprint "eagle-import:LED5MMRGB")
      (libsource (lib "eagle-import") (part "RGBLEDAN"))
    )
    (comp (ref "U$366")
      (value "RGBLEDAN")
      (footprint "eagle-import:LED5MMRGB")
      (libsource (lib "eagle-import") (part "RGBLEDAN"))
    )
    (comp (ref "U$367")
      (value "RGBLEDAN")
      (footprint "eagle-import:LED5MMRGB")
      (libsource (lib "eagle-import") (part "RGBLEDAN"))
    )
    (comp (ref "U$368")
      (value "RGBLEDAN")
      (footprint "eagle-import:LED5MMRGB")
      (libsource (lib "eagle-import") (part "RGBLEDAN"))
    )
    (comp (ref "U$369")
      (value "RGBLEDAN")
      (footprint "eagle-import:LED5MMRGB")
      (libsource (lib "eagle-import") (part "RGBLEDAN"))
    )
    (comp (ref "U$370")
      (value "RGBLEDAN")
      (footprint "eagle-import:LED5MMRGB")
      (libsource (lib "eagle-import") (part "RGBLEDAN"))
    )
    (comp (ref "U$371")
      (value "RGBLEDAN")
      (footprint "eagle-import:LED5MMRGB")
      (libsource (lib "eagle-import") (part "RGBLEDAN"))
    )
    (comp (ref "U$372")
      (value "RGBLEDAN")
      (footprint "eagle-import:LED5MMRGB")
      (libsource (lib "eagle-import") (part "RGBLEDAN"))
    )
    (comp (ref "U$373")
      (value "RGBLEDAN")
      (footprint "eagle-import:LED5MMRGB")
      (libsource (lib "eagle-import") (part "RGBLEDAN"))
    )
    (comp (ref "U$374")
      (value "RGBLEDAN")
      (footprint "eagle-import:LED5MMRGB")
      (libsource (lib "eagle-import") (part "RGBLEDAN"))
    )
    (comp (ref "U$375")
      (value "RGBLEDAN")
      (footprint "eagle-import:LED5MMRGB")
      (libsource (lib "eagle-import") (part "RGBLEDAN"))
    )
    (comp (ref "U$376")
      (value "RGBLEDAN")
      (footprint "eagle-import:LED5MMRGB")
      (libsource (lib "eagle-import") (part "RGBLEDAN"))
    )
    (comp (ref "U$377")
      (value "RGBLEDAN")
      (footprint "eagle-import:LED5MMRGB")
      (libsource (lib "eagle-import") (part "RGBLEDAN"))
    )
    (comp (ref "U$378")
      (value "RGBLEDAN")
      (footprint "eagle-import:LED5MMRGB")
      (libsource (lib "eagle-import") (part "RGBLEDAN"))
    )
    (comp (ref "U$379")
      (value "RGBLEDAN")
      (footprint "eagle-import:LED5MMRGB")
      (libsource (lib "eagle-import") (part "RGBLEDAN"))
    )
    (comp (ref "U$380")
      (value "RGBLEDAN")
      (footprint "eagle-import:LED5MMRGB")
      (libsource (lib "eagle-import") (part "RGBLEDAN"))
    )
    (comp (ref "U$381")
      (value "RGBLEDAN")
      (footprint "eagle-import:LED5MMRGB")
      (libsource (lib "eagle-import") (part "RGBLEDAN"))
    )
    (comp (ref "U$382")
      (value "RGBLEDAN")
      (footprint "eagle-import:LED5MMRGB")
      (libsource (lib "eagle-import") (part "RGBLEDAN"))
    )
    (comp (ref "U$383")
      (value "RGBLEDAN")
      (footprint "eagle-import:LED5MMRGB")
      (libsource (lib "eagle-import") (part "RGBLEDAN"))
    )
    (comp (ref "U$384")
      (value "RGBLEDAN")
      (footprint "eagle-import:LED5MMRGB")
      (libsource (lib "eagle-import") (part "RGBLEDAN"))
    )
    (comp (ref "U$385")
      (value "RGBLEDAN")
      (footprint "eagle-import:LED5MMRGB")
      (libsource (lib "eagle-import") (part "RGBLEDAN"))
    )
    (comp (ref "U$386")
      (value "RGBLEDAN")
      (footprint "eagle-import:LED5MMRGB")
      (libsource (lib "eagle-import") (part "RGBLEDAN"))
    )
    (comp (ref "U$387")
      (value "RGBLEDAN")
      (footprint "eagle-import:LED5MMRGB")
      (libsource (lib "eagle-import") (part "RGBLEDAN"))
    )
    (comp (ref "U$388")
      (value "RGBLEDAN")
      (footprint "eagle-import:LED5MMRGB")
      (libsource (lib "eagle-import") (part "RGBLEDAN"))
    )
    (comp (ref "U$389")
      (value "RGBLEDAN")
      (footprint "eagle-import:LED5MMRGB")
      (libsource (lib "eagle-import") (part "RGBLEDAN"))
    )
    (comp (ref "U$390")
      (value "RGBLEDAN")
      (footprint "eagle-import:LED5MMRGB")
      (libsource (lib "eagle-import") (part "RGBLEDAN"))
    )
    (comp (ref "U$391")
      (value "RGBLEDAN")
      (footprint "eagle-import:LED5MMRGB")
      (libsource (lib "eagle-import") (part "RGBLEDAN"))
    )
    (comp (ref "U$392")
      (value "RGBLEDAN")
      (footprint "eagle-import:LED5MMRGB")
      (libsource (lib "eagle-import") (part "RGBLEDAN"))
    )
    (comp (ref "U$393")
      (value "RGBLEDAN")
      (footprint "eagle-import:LED5MMRGB")
      (libsource (lib "eagle-import") (part "RGBLEDAN"))
    )
    (comp (ref "U$394")
      (value "RGBLEDAN")
      (footprint "eagle-import:LED5MMRGB")
      (libsource (lib "eagle-import") (part "RGBLEDAN"))
    )
    (comp (ref "U$395")
      (value "RGBLEDAN")
      (footprint "eagle-import:LED5MMRGB")
      (libsource (lib "eagle-import") (part "RGBLEDAN"))
    )
    (comp (ref "U$396")
      (value "RGBLEDAN")
      (footprint "eagle-import:LED5MMRGB")
      (libsource (lib "eagle-import") (part "RGBLEDAN"))
    )
    (comp (ref "U$397")
      (value "RGBLEDAN")
      (footprint "eagle-import:LED5MMRGB")
      (libsource (lib "eagle-import") (part "RGBLEDAN"))
    )
    (comp (ref "U$398")
      (value "RGBLEDAN")
      (footprint "eagle-import:LED5MMRGB")
      (libsource (lib "eagle-import") (part "RGBLEDAN"))
    )
    (comp (ref "U$399")
      (value "RGBLEDAN")
      (footprint "eagle-import:LED5MMRGB")
      (libsource (lib "eagle-import") (part "RGBLEDAN"))
    )
    (comp (ref "U$400")
      (value "RGBLEDAN")
      (footprint "eagle-import:LED5MMRGB")
      (libsource (lib "eagle-import") (part "RGBLEDAN"))
    )
    (comp (ref "U$401")
      (value "RGBLEDAN")
      (footprint "eagle-import:LED5MMRGB")
      (libsource (lib "eagle-import") (part "RGBLEDAN"))
    )
    (comp (ref "U$402")
      (value "RGBLEDAN")
      (footprint "eagle-import:LED5MMRGB")
      (libsource (lib "eagle-import") (part "RGBLEDAN"))
    )
    (comp (ref "U$403")
      (value "RGBLEDAN")
      (footprint "eagle-import:LED5MMRGB")
      (libsource (lib "eagle-import") (part "RGBLEDAN"))
    )
    (comp (ref "U$404")
      (value "RGBLEDAN")
      (footprint "eagle-import:LED5MMRGB")
      (libsource (lib "eagle-import") (part "RGBLEDAN"))
    )
    (comp (ref "U$405")
      (value "RGBLEDAN")
      (footprint "eagle-import:LED5MMRGB")
      (libsource (lib "eagle-import") (part "RGBLEDAN"))
    )
    (comp (ref "U$406")
      (value "RGBLEDAN")
      (footprint "eagle-import:LED5MMRGB")
      (libsource (lib "eagle-import") (part "RGBLEDAN"))
    )
    (comp (ref "U$407")
      (value "RGBLEDAN")
      (footprint "eagle-import:LED5MMRGB")
      (libsource (lib "eagle-import") (part "RGBLEDAN"))
    )
    (comp (ref "U$408")
      (value "RGBLEDAN")
      (footprint "eagle-import:LED5MMRGB")
      (libsource (lib "eagle-import") (part "RGBLEDAN"))
    )
    (comp (ref "U$409")
      (value "RGBLEDAN")
      (footprint "eagle-import:LED5MMRGB")
      (libsource (lib "eagle-import") (part "RGBLEDAN"))
    )
    (comp (ref "U$410")
      (value "RGBLEDAN")
      (footprint "eagle-import:LED5MMRGB")
      (libsource (lib "eagle-import") (part "RGBLEDAN"))
    )
    (comp (ref "U$411")
      (value "RGBLEDAN")
      (footprint "eagle-import:LED5MMRGB")
      (libsource (lib "eagle-import") (part "RGBLEDAN"))
    )
    (comp (ref "U$412")
      (value "RGBLEDAN")
      (footprint "eagle-import:LED5MMRGB")
      (libsource (lib "eagle-import") (part "RGBLEDAN"))
    )
    (comp (ref "U$413")
      (value "RGBLEDAN")
      (footprint "eagle-import:LED5MMRGB")
      (libsource (lib "eagle-import") (part "RGBLEDAN"))
    )
    (comp (ref "U$414")
      (value "RGBLEDAN")
      (footprint "eagle-import:LED5MMRGB")
      (libsource (lib "eagle-import") (part "RGBLEDAN"))
    )
    (comp (ref "U$415")
      (value "RGBLEDAN")
      (footprint "eagle-import:LED5MMRGB")
      (libsource (lib "eagle-import") (part "RGBLEDAN"))
    )
    (comp (ref "U$416")
      (value "RGBLEDAN")
      (footprint "eagle-import:LED5MMRGB")
      (libsource (lib "eagle-import") (part "RGBLEDAN"))
    )
    (comp (ref "U$417")
      (value "RGBLEDAN")
      (footprint "eagle-import:LED5MMRGB")
      (libsource (lib "eagle-import") (part "RGBLEDAN"))
    )
    (comp (ref "U$418")
      (value "RGBLEDAN")
      (footprint "eagle-import:LED5MMRGB")
      (libsource (lib "eagle-import") (part "RGBLEDAN"))
    )
    (comp (ref "U$419")
      (value "RGBLEDAN")
      (footprint "eagle-import:LED5MMRGB")
      (libsource (lib "eagle-import") (part "RGBLEDAN"))
    )
    (comp (ref "U$420")
      (value "RGBLEDAN")
      (footprint "eagle-import:LED5MMRGB")
      (libsource (lib "eagle-import") (part "RGBLEDAN"))
    )
    (comp (ref "U$421")
      (value "RGBLEDAN")
      (footprint "eagle-import:LED5MMRGB")
      (libsource (lib "eagle-import") (part "RGBLEDAN"))
    )
    (comp (ref "U$422")
      (value "RGBLEDAN")
      (footprint "eagle-import:LED5MMRGB")
      (libsource (lib "eagle-import") (part "RGBLEDAN"))
    )
    (comp (ref "U$423")
      (value "RGBLEDAN")
      (footprint "eagle-import:LED5MMRGB")
      (libsource (lib "eagle-import") (part "RGBLEDAN"))
    )
    (comp (ref "U$424")
      (value "RGBLEDAN")
      (footprint "eagle-import:LED5MMRGB")
      (libsource (lib "eagle-import") (part "RGBLEDAN"))
    )
    (comp (ref "U$425")
      (value "RGBLEDAN")
      (footprint "eagle-import:LED5MMRGB")
      (libsource (lib "eagle-import") (part "RGBLEDAN"))
    )
    (comp (ref "U$426")
      (value "RGBLEDAN")
      (footprint "eagle-import:LED5MMRGB")
      (libsource (lib "eagle-import") (part "RGBLEDAN"))
    )
    (comp (ref "U$427")
      (value "RGBLEDAN")
      (footprint "eagle-import:LED5MMRGB")
      (libsource (lib "eagle-import") (part "RGBLEDAN"))
    )
    (comp (ref "U$428")
      (value "RGBLEDAN")
      (footprint "eagle-import:LED5MMRGB")
      (libsource (lib "eagle-import") (part "RGBLEDAN"))
    )
    (comp (ref "U$429")
      (value "RGBLEDAN")
      (footprint "eagle-import:LED5MMRGB")
      (libsource (lib "eagle-import") (part "RGBLEDAN"))
    )
    (comp (ref "U$430")
      (value "RGBLEDAN")
      (footprint "eagle-import:LED5MMRGB")
      (libsource (lib "eagle-import") (part "RGBLEDAN"))
    )
    (comp (ref "U$431")
      (value "RGBLEDAN")
      (footprint "eagle-import:LED5MMRGB")
      (libsource (lib "eagle-import") (part "RGBLEDAN"))
    )
    (comp (ref "U$432")
      (value "RGBLEDAN")
      (footprint "eagle-import:LED5MMRGB")
      (libsource (lib "eagle-import") (part "RGBLEDAN"))
    )
    (comp (ref "U$433")
      (value "RGBLEDAN")
      (footprint "eagle-import:LED5MMRGB")
      (libsource (lib "eagle-import") (part "RGBLEDAN"))
    )
    (comp (ref "U$434")
      (value "RGBLEDAN")
      (footprint "eagle-import:LED5MMRGB")
      (libsource (lib "eagle-import") (part "RGBLEDAN"))
    )
    (comp (ref "U$435")
      (value "RGBLEDAN")
      (footprint "eagle-import:LED5MMRGB")
      (libsource (lib "eagle-import") (part "RGBLEDAN"))
    )
    (comp (ref "U$436")
      (value "RGBLEDAN")
      (footprint "eagle-import:LED5MMRGB")
      (libsource (lib "eagle-import") (part "RGBLEDAN"))
    )
    (comp (ref "U$437")
      (value "RGBLEDAN")
      (footprint "eagle-import:LED5MMRGB")
      (libsource (lib "eagle-import") (part "RGBLEDAN"))
    )
    (comp (ref "U$438")
      (value "RGBLEDAN")
      (footprint "eagle-import:LED5MMRGB")
      (libsource (lib "eagle-import") (part "RGBLEDAN"))
    )
    (comp (ref "U$439")
      (value "RGBLEDAN")
      (footprint "eagle-import:LED5MMRGB")
      (libsource (lib "eagle-import") (part "RGBLEDAN"))
    )
    (comp (ref "U$440")
      (value "RGBLEDAN")
      (footprint "eagle-import:LED5MMRGB")
      (libsource (lib "eagle-import") (part "RGBLEDAN"))
    )
    (comp (ref "U$441")
      (value "RGBLEDAN")
      (footprint "eagle-import:LED5MMRGB")
      (libsource (lib "eagle-import") (part "RGBLEDAN"))
    )
    (comp (ref "U$442")
      (value "RGBLEDAN")
      (footprint "eagle-import:LED5MMRGB")
      (libsource (lib "eagle-import") (part "RGBLEDAN"))
    )
    (comp (ref "U$443")
      (value "RGBLEDAN")
      (footprint "eagle-import:LED5MMRGB")
      (libsource (lib "eagle-import") (part "RGBLEDAN"))
    )
    (comp (ref "U$444")
      (value "RGBLEDAN")
      (footprint "eagle-import:LED5MMRGB")
      (libsource (lib "eagle-import") (part "RGBLEDAN"))
    )
    (comp (ref "U$445")
      (value "RGBLEDAN")
      (footprint "eagle-import:LED5MMRGB")
      (libsource (lib "eagle-import") (part "RGBLEDAN"))
    )
    (comp (ref "U$446")
      (value "RGBLEDAN")
      (footprint "eagle-import:LED5MMRGB")
      (libsource (lib "eagle-import") (part "RGBLEDAN"))
    )
    (comp (ref "U$447")
      (value "RGBLEDAN")
      (footprint "eagle-import:LED5MMRGB")
      (libsource (lib "eagle-import") (part "RGBLEDAN"))
    )
    (comp (ref "U$448")
      (value "RGBLEDAN")
      (footprint "eagle-import:LED5MMRGB")
      (libsource (lib "eagle-import") (part "RGBLEDAN"))
    )
    (comp (ref "U$449")
      (value "RGBLEDAN")
      (footprint "eagle-import:LED5MMRGB")
      (libsource (lib "eagle-import") (part "RGBLEDAN"))
    )
    (comp (ref "U$450")
      (value "RGBLEDAN")
      (footprint "eagle-import:LED5MMRGB")
      (libsource (lib "eagle-import") (part "RGBLEDAN"))
    )
    (comp (ref "U$451")
      (value "RGBLEDAN")
      (footprint "eagle-import:LED5MMRGB")
      (libsource (lib "eagle-import") (part "RGBLEDAN"))
    )
    (comp (ref "U$452")
      (value "RGBLEDAN")
      (footprint "eagle-import:LED5MMRGB")
      (libsource (lib "eagle-import") (part "RGBLEDAN"))
    )
    (comp (ref "U$453")
      (value "RGBLEDAN")
      (footprint "eagle-import:LED5MMRGB")
      (libsource (lib "eagle-import") (part "RGBLEDAN"))
    )
    (comp (ref "U$454")
      (value "RGBLEDAN")
      (footprint "eagle-import:LED5MMRGB")
      (libsource (lib "eagle-import") (part "RGBLEDAN"))
    )
    (comp (ref "U$455")
      (value "RGBLEDAN")
      (footprint "eagle-import:LED5MMRGB")
      (libsource (lib "eagle-import") (part "RGBLEDAN"))
    )
    (comp (ref "U$456")
      (value "RGBLEDAN")
      (footprint "eagle-import:LED5MMRGB")
      (libsource (lib "eagle-import") (part "RGBLEDAN"))
    )
    (comp (ref "U$457")
      (value "RGBLEDAN")
      (footprint "eagle-import:LED5MMRGB")
      (libsource (lib "eagle-import") (part "RGBLEDAN"))
    )
    (comp (ref "U$458")
      (value "RGBLEDAN")
      (footprint "eagle-import:LED5MMRGB")
      (libsource (lib "eagle-import") (part "RGBLEDAN"))
    )
    (comp (ref "U$459")
      (value "RGBLEDAN")
      (footprint "eagle-import:LED5MMRGB")
      (libsource (lib "eagle-import") (part "RGBLEDAN"))
    )
    (comp (ref "U$460")
      (value "RGBLEDAN")
      (footprint "eagle-import:LED5MMRGB")
      (libsource (lib "eagle-import") (part "RGBLEDAN"))
    )
    (comp (ref "U$461")
      (value "RGBLEDAN")
      (footprint "eagle-import:LED5MMRGB")
      (libsource (lib "eagle-import") (part "RGBLEDAN"))
    )
    (comp (ref "U$462")
      (value "RGBLEDAN")
      (footprint "eagle-import:LED5MMRGB")
      (libsource (lib "eagle-import") (part "RGBLEDAN"))
    )
    (comp (ref "U$463")
      (value "RGBLEDAN")
      (footprint "eagle-import:LED5MMRGB")
      (libsource (lib "eagle-import") (part "RGBLEDAN"))
    )
    (comp (ref "U$464")
      (value "RGBLEDAN")
      (footprint "eagle-import:LED5MMRGB")
      (libsource (lib "eagle-import") (part "RGBLEDAN"))
    )
    (comp (ref "U$465")
      (value "RGBLEDAN")
      (footprint "eagle-import:LED5MMRGB")
      (libsource (lib "eagle-import") (part "RGBLEDAN"))
    )
    (comp (ref "U$466")
      (value "RGBLEDAN")
      (footprint "eagle-import:LED5MMRGB")
      (libsource (lib "eagle-import") (part "RGBLEDAN"))
    )
    (comp (ref "U$467")
      (value "RGBLEDAN")
      (footprint "eagle-import:LED5MMRGB")
      (libsource (lib "eagle-import") (part "RGBLEDAN"))
    )
    (comp (ref "U$468")
      (value "RGBLEDAN")
      (footprint "eagle-import:LED5MMRGB")
      (libsource (lib "eagle-import") (part "RGBLEDAN"))
    )
    (comp (ref "U$469")
      (value "RGBLEDAN")
      (footprint "eagle-import:LED5MMRGB")
      (libsource (lib "eagle-import") (part "RGBLEDAN"))
    )
    (comp (ref "U$470")
      (value "RGBLEDAN")
      (footprint "eagle-import:LED5MMRGB")
      (libsource (lib "eagle-import") (part "RGBLEDAN"))
    )
    (comp (ref "U$471")
      (value "RGBLEDAN")
      (footprint "eagle-import:LED5MMRGB")
      (libsource (lib "eagle-import") (part "RGBLEDAN"))
    )
    (comp (ref "U$472")
      (value "RGBLEDAN")
      (footprint "eagle-import:LED5MMRGB")
      (libsource (lib "eagle-import") (part "RGBLEDAN"))
    )
    (comp (ref "U$473")
      (value "RGBLEDAN")
      (footprint "eagle-import:LED5MMRGB")
      (libsource (lib "eagle-import") (part "RGBLEDAN"))
    )
    (comp (ref "U$474")
      (value "RGBLEDAN")
      (footprint "eagle-import:LED5MMRGB")
      (libsource (lib "eagle-import") (part "RGBLEDAN"))
    )
    (comp (ref "U$475")
      (value "RGBLEDAN")
      (footprint "eagle-import:LED5MMRGB")
      (libsource (lib "eagle-import") (part "RGBLEDAN"))
    )
    (comp (ref "U$476")
      (value "RGBLEDAN")
      (footprint "eagle-import:LED5MMRGB")
      (libsource (lib "eagle-import") (part "RGBLEDAN"))
    )
    (comp (ref "U$477")
      (value "RGBLEDAN")
      (footprint "eagle-import:LED5MMRGB")
      (libsource (lib "eagle-import") (part "RGBLEDAN"))
    )
    (comp (ref "U$478")
      (value "RGBLEDAN")
      (footprint "eagle-import:LED5MMRGB")
      (libsource (lib "eagle-import") (part "RGBLEDAN"))
    )
    (comp (ref "U$479")
      (value "RGBLEDAN")
      (footprint "eagle-import:LED5MMRGB")
      (libsource (lib "eagle-import") (part "RGBLEDAN"))
    )
    (comp (ref "U$480")
      (value "RGBLEDAN")
      (footprint "eagle-import:LED5MMRGB")
      (libsource (lib "eagle-import") (part "RGBLEDAN"))
    )
    (comp (ref "U$481")
      (value "RGBLEDAN")
      (footprint "eagle-import:LED5MMRGB")
      (libsource (lib "eagle-import") (part "RGBLEDAN"))
    )
    (comp (ref "U$482")
      (value "RGBLEDAN")
      (footprint "eagle-import:LED5MMRGB")
      (libsource (lib "eagle-import") (part "RGBLEDAN"))
    )
    (comp (ref "U$483")
      (value "RGBLEDAN")
      (footprint "eagle-import:LED5MMRGB")
      (libsource (lib "eagle-import") (part "RGBLEDAN"))
    )
    (comp (ref "U$484")
      (value "RGBLEDAN")
      (footprint "eagle-import:LED5MMRGB")
      (libsource (lib "eagle-import") (part "RGBLEDAN"))
    )
    (comp (ref "U$485")
      (value "RGBLEDAN")
      (footprint "eagle-import:LED5MMRGB")
      (libsource (lib "eagle-import") (part "RGBLEDAN"))
    )
    (comp (ref "U$486")
      (value "RGBLEDAN")
      (footprint "eagle-import:LED5MMRGB")
      (libsource (lib "eagle-import") (part "RGBLEDAN"))
    )
    (comp (ref "U$487")
      (value "RGBLEDAN")
      (footprint "eagle-import:LED5MMRGB")
      (libsource (lib "eagle-import") (part "RGBLEDAN"))
    )
    (comp (ref "U$488")
      (value "RGBLEDAN")
      (footprint "eagle-import:LED5MMRGB")
      (libsource (lib "eagle-import") (part "RGBLEDAN"))
    )
    (comp (ref "U$489")
      (value "RGBLEDAN")
      (footprint "eagle-import:LED5MMRGB")
      (libsource (lib "eagle-import") (part "RGBLEDAN"))
    )
    (comp (ref "U$490")
      (value "RGBLEDAN")
      (footprint "eagle-import:LED5MMRGB")
      (libsource (lib "eagle-import") (part "RGBLEDAN"))
    )
    (comp (ref "U$491")
      (value "RGBLEDAN")
      (footprint "eagle-import:LED5MMRGB")
      (libsource (lib "eagle-import") (part "RGBLEDAN"))
    )
    (comp (ref "U$492")
      (value "RGBLEDAN")
      (footprint "eagle-import:LED5MMRGB")
      (libsource (lib "eagle-import") (part "RGBLEDAN"))
    )
    (comp (ref "U$493")
      (value "RGBLEDAN")
      (footprint "eagle-import:LED5MMRGB")
      (libsource (lib "eagle-import") (part "RGBLEDAN"))
    )
    (comp (ref "U$494")
      (value "RGBLEDAN")
      (footprint "eagle-import:LED5MMRGB")
      (libsource (lib "eagle-import") (part "RGBLEDAN"))
    )
    (comp (ref "U$495")
      (value "RGBLEDAN")
      (footprint "eagle-import:LED5MMRGB")
      (libsource (lib "eagle-import") (part "RGBLEDAN"))
    )
    (comp (ref "U$496")
      (value "RGBLEDAN")
      (footprint "eagle-import:LED5MMRGB")
      (libsource (lib "eagle-import") (part "RGBLEDAN"))
    )
    (comp (ref "U$497")
      (value "RGBLEDAN")
      (footprint "eagle-import:LED5MMRGB")
      (libsource (lib "eagle-import") (part "RGBLEDAN"))
    )
    (comp (ref "U$498")
      (value "RGBLEDAN")
      (footprint "eagle-import:LED5MMRGB")
      (libsource (lib "eagle-import") (part "RGBLEDAN"))
    )
    (comp (ref "U$499")
      (value "RGBLEDAN")
      (footprint "eagle-import:LED5MMRGB")
      (libsource (lib "eagle-import") (part "RGBLEDAN"))
    )
    (comp (ref "U$500")
      (value "RGBLEDAN")
      (footprint "eagle-import:LED5MMRGB")
      (libsource (lib "eagle-import") (part "RGBLEDAN"))
    )
    (comp (ref "U$501")
      (value "RGBLEDAN")
      (footprint "eagle-import:LED5MMRGB")
      (libsource (lib "eagle-import") (part "RGBLEDAN"))
    )
    (comp (ref "U$502")
      (value "RGBLEDAN")
      (footprint "eagle-import:LED5MMRGB")
      (libsource (lib "eagle-import") (part "RGBLEDAN"))
    )
    (comp (ref "U$503")
      (value "RGBLEDAN")
      (footprint "eagle-import:LED5MMRGB")
      (libsource (lib "eagle-import") (part "RGBLEDAN"))
    )
    (comp (ref "U$504")
      (value "RGBLEDAN")
      (footprint "eagle-import:LED5MMRGB")
      (libsource (lib "eagle-import") (part "RGBLEDAN"))
    )
    (comp (ref "U$505")
      (value "RGBLEDAN")
      (footprint "eagle-import:LED5MMRGB")
      (libsource (lib "eagle-import") (part "RGBLEDAN"))
    )
    (comp (ref "U$506")
      (value "RGBLEDAN")
      (footprint "eagle-import:LED5MMRGB")
      (libsource (lib "eagle-import") (part "RGBLEDAN"))
    )
    (comp (ref "U$507")
      (value "RGBLEDAN")
      (footprint "eagle-import:LED5MMRGB")
      (libsource (lib "eagle-import") (part "RGBLEDAN"))
    )
    (comp (ref "U$508")
      (value "RGBLEDAN")
      (footprint "eagle-import:LED5MMRGB")
      (libsource (lib "eagle-import") (part "RGBLEDAN"))
    )
    (comp (ref "U$509")
      (value "RGBLEDAN")
      (footprint "eagle-import:LED5MMRGB")
      (libsource (lib "eagle-import") (part "RGBLEDAN"))
    )
    (comp (ref "U$510")
      (value "RGBLEDAN")
      (footprint "eagle-import:LED5MMRGB")
      (libsource (lib "eagle-import") (part "RGBLEDAN"))
    )
    (comp (ref "U$511")
      (value "RGBLEDAN")
      (footprint "eagle-import:LED5MMRGB")
      (libsource (lib "eagle-import") (part "RGBLEDAN"))
    )
    (comp (ref "U$512")
      (value "RGBLEDAN")
      (footprint "eagle-import:LED5MMRGB")
      (libsource (lib "eagle-import") (part "RGBLEDAN"))
    )
    (comp (ref "U$513")
      (value "RGBLEDAN")
      (footprint "eagle-import:LED5MMRGB")
      (libsource (lib "eagle-import") (part "RGBLEDAN"))
    )
    (comp (ref "U$514")
      (value "RGBLEDAN")
      (footprint "eagle-import:LED5MMRGB")
      (libsource (lib "eagle-import") (part "RGBLEDAN"))
    )
    (comp (ref "U$515")
      (value "RGBLEDAN")
      (footprint "eagle-import:LED5MMRGB")
      (libsource (lib "eagle-import") (part "RGBLEDAN"))
    )
    (comp (ref "U$516")
      (value "RGBLEDAN")
      (footprint "eagle-import:LED5MMRGB")
      (libsource (lib "eagle-import") (part "RGBLEDAN"))
    )
    (comp (ref "U$517")
      (value "RGBLEDAN")
      (footprint "eagle-import:LED5MMRGB")
      (libsource (lib "eagle-import") (part "RGBLEDAN"))
    )
    (comp (ref "U$518")
      (value "RGBLEDAN")
      (footprint "eagle-import:LED5MMRGB")
      (libsource (lib "eagle-import") (part "RGBLEDAN"))
    )
    (comp (ref "U$519")
      (value "2.1MMJACKTHM")
      (footprint "eagle-import:PJ-102A")
      (libsource (lib "eagle-import") (part "2.1MMJACKTHM"))
    )
  )
  (nets
    (net (code "1") (name "+5V") (class "Default")
      (node (ref "C1") (pin "1") (pinfunction "1_1") (pintype "passive"))
      (node (ref "C10") (pin "1") (pinfunction "1_1") (pintype "passive"))
      (node (ref "C11") (pin "1") (pinfunction "1_1") (pintype "passive"))
      (node (ref "C12") (pin "1") (pinfunction "1_1") (pintype "passive"))
      (node (ref "C13") (pin "1") (pinfunction "1_1") (pintype "passive"))
      (node (ref "C14") (pin "1") (pinfunction "1_1") (pintype "passive"))
      (node (ref "C15") (pin "1") (pinfunction "1_1") (pintype "passive"))
      (node (ref "C16") (pin "1") (pinfunction "1_1") (pintype "passive"))
      (node (ref "C18") (pin "+") (pinfunction "+_+") (pintype "passive"))
      (node (ref "C2") (pin "1") (pinfunction "1_1") (pintype "passive"))
      (node (ref "C3") (pin "1") (pinfunction "1_1") (pintype "passive"))
      (node (ref "C4") (pin "1") (pinfunction "1_1") (pintype "passive"))
      (node (ref "C5") (pin "1") (pinfunction "1_1") (pintype "passive"))
      (node (ref "C6") (pin "1") (pinfunction "1_1") (pintype "passive"))
      (node (ref "C7") (pin "1") (pinfunction "1_1") (pintype "passive"))
      (node (ref "C8") (pin "1") (pinfunction "1_1") (pintype "passive"))
      (node (ref "C9") (pin "1") (pinfunction "1_1") (pintype "passive"))
      (node (ref "IC1") (pin "16") (pinfunction "VDD_16") (pintype "power_in"))
      (node (ref "IC2") (pin "16") (pinfunction "VDD_16") (pintype "power_in"))
      (node (ref "IC3") (pin "2") (pinfunction "VO_2") (pintype "passive"))
      (node (ref "Q17") (pin "1") (pinfunction "S_1") (pintype "passive"))
      (node (ref "Q18") (pin "1") (pinfunction "S_1") (pintype "passive"))
      (node (ref "Q19") (pin "1") (pinfunction "S_1") (pintype "passive"))
      (node (ref "Q20") (pin "1") (pinfunction "S_1") (pintype "passive"))
      (node (ref "Q21") (pin "1") (pinfunction "S_1") (pintype "passive"))
      (node (ref "Q22") (pin "1") (pinfunction "S_1") (pintype "passive"))
      (node (ref "Q23") (pin "1") (pinfunction "S_1") (pintype "passive"))
      (node (ref "Q24") (pin "1") (pinfunction "S_1") (pintype "passive"))
      (node (ref "Q25") (pin "1") (pinfunction "S_1") (pintype "passive"))
      (node (ref "Q26") (pin "1") (pinfunction "S_1") (pintype "passive"))
      (node (ref "Q27") (pin "1") (pinfunction "S_1") (pintype "passive"))
      (node (ref "Q28") (pin "1") (pinfunction "S_1") (pintype "passive"))
      (node (ref "Q29") (pin "1") (pinfunction "S_1") (pintype "passive"))
      (node (ref "Q30") (pin "1") (pinfunction "S_1") (pintype "passive"))
      (node (ref "Q31") (pin "1") (pinfunction "S_1") (pintype "passive"))
      (node (ref "Q32") (pin "1") (pinfunction "S_1") (pintype "passive"))
      (node (ref "U$1") (pin "21") (pinfunction "VCC_21") (pintype "power_in"))
      (node (ref "U$2") (pin "21") (pinfunction "VCC_21") (pintype "power_in"))
      (node (ref "U$3") (pin "21") (pinfunction "VCC_21") (pintype "power_in"))
      (node (ref "U$4") (pin "21") (pinfunction "VCC_21") (pintype "power_in"))
      (node (ref "U$5") (pin "21") (pinfunction "VCC_21") (pintype "power_in"))
      (node (ref "U$6") (pin "21") (pinfunction "VCC_21") (pintype "power_in"))
    )
    (net (code "2") (name "/BLANK") (class "Default")
      (node (ref "TLCPINS") (pin "6") (pinfunction "6_6") (pintype "passive"))
      (node (ref "U$1") (pin "23") (pinfunction "BLANK_23") (pintype "input"))
      (node (ref "U$2") (pin "23") (pinfunction "BLANK_23") (pintype "input"))
      (node (ref "U$3") (pin "23") (pinfunction "BLANK_23") (pintype "input"))
      (node (ref "U$4") (pin "23") (pinfunction "BLANK_23") (pintype "input"))
      (node (ref "U$5") (pin "23") (pinfunction "BLANK_23") (pintype "input"))
      (node (ref "U$6") (pin "23") (pinfunction "BLANK_23") (pintype "input"))
    )
    (net (code "3") (name "/GSCLK") (class "Default")
      (node (ref "TLCPINS") (pin "4") (pinfunction "4_4") (pintype "passive"))
      (node (ref "U$1") (pin "18") (pinfunction "GSCLK_18") (pintype "input"))
      (node (ref "U$2") (pin "18") (pinfunction "GSCLK_18") (pintype "input"))
      (node (ref "U$3") (pin "18") (pinfunction "GSCLK_18") (pintype "input"))
      (node (ref "U$4") (pin "18") (pinfunction "GSCLK_18") (pintype "input"))
      (node (ref "U$5") (pin "18") (pinfunction "GSCLK_18") (pintype "input"))
      (node (ref "U$6") (pin "18") (pinfunction "GSCLK_18") (pintype "input"))
    )
    (net (code "4") (name "/OUTEN") (class "Default")
      (node (ref "IC1") (pin "15") (pinfunction "OE_15") (pintype "input"))
      (node (ref "IC2") (pin "15") (pinfunction "OE_15") (pintype "input"))
      (node (ref "SHIFTPINS") (pin "3") (pinfunction "3_3") (pintype "passive"))
    )
    (net (code "5") (name "/SCLK") (class "Default")
      (node (ref "TLCPINS") (pin "1") (pinfunction "1_1") (pintype "passive"))
      (node (ref "U$1") (pin "25") (pinfunction "SCLK_25") (pintype "input"))
      (node (ref "U$2") (pin "25") (pinfunction "SCLK_25") (pintype "input"))
      (node (ref "U$3") (pin "25") (pinfunction "SCLK_25") (pintype "input"))
      (node (ref "U$4") (pin "25") (pinfunction "SCLK_25") (pintype "input"))
      (node (ref "U$5") (pin "25") (pinfunction "SCLK_25") (pintype "input"))
      (node (ref "U$6") (pin "25") (pinfunction "SCLK_25") (pintype "input"))
    )
    (net (code "6") (name "/SHCLK") (class "Default")
      (node (ref "IC1") (pin "3") (pinfunction "CLK_3") (pintype "input"))
      (node (ref "IC2") (pin "3") (pinfunction "CLK_3") (pintype "input"))
      (node (ref "SHIFTPINS") (pin "5") (pinfunction "5_5") (pintype "passive"))
    )
    (net (code "7") (name "/SHDATA") (class "Default")
      (node (ref "IC1") (pin "2") (pinfunction "D_2") (pintype "input"))
      (node (ref "SHIFTPINS") (pin "4") (pinfunction "4_4") (pintype "passive"))
    )
    (net (code "8") (name "/SIN") (class "Default")
      (node (ref "TLCPINS") (pin "2") (pinfunction "2_2") (pintype "passive"))
      (node (ref "U$1") (pin "26") (pinfunction "SIN_26") (pintype "input"))
    )
    (net (code "9") (name "/SOUTA") (class "Default")
      (node (ref "U$1") (pin "17") (pinfunction "SOUT_17") (pintype "output"))
      (node (ref "U$2") (pin "26") (pinfunction "SIN_26") (pintype "input"))
    )
    (net (code "10") (name "/SOUTB") (class "Default")
      (node (ref "U$2") (pin "17") (pinfunction "SOUT_17") (pintype "output"))
      (node (ref "U$3") (pin "26") (pinfunction "SIN_26") (pintype "input"))
    )
    (net (code "11") (name "/SOUTC") (class "Default")
      (node (ref "U$3") (pin "17") (pinfunction "SOUT_17") (pintype "output"))
      (node (ref "U$4") (pin "26") (pinfunction "SIN_26") (pintype "input"))
    )
    (net (code "12") (name "/SOUTD") (class "Default")
      (node (ref "U$4") (pin "17") (pinfunction "SOUT_17") (pintype "output"))
      (node (ref "U$5") (pin "26") (pinfunction "SIN_26") (pintype "input"))
    )
    (net (code "13") (name "/SOUTE") (class "Default")
      (node (ref "U$5") (pin "17") (pinfunction "SOUT_17") (pintype "output"))
      (node (ref "U$6") (pin "26") (pinfunction "SIN_26") (pintype "input"))
    )
    (net (code "14") (name "/STROBE") (class "Default")
      (node (ref "IC1") (pin "1") (pinfunction "STR_1") (pintype "input"))
      (node (ref "IC2") (pin "1") (pinfunction "STR_1") (pintype "input"))
      (node (ref "SHIFTPINS") (pin "6") (pinfunction "6_6") (pintype "passive"))
    )
    (net (code "15") (name "/VPRG") (class "Default")
      (node (ref "TLCPINS") (pin "5") (pinfunction "5_5") (pintype "passive"))
      (node (ref "U$1") (pin "27") (pinfunction "VPRG_27") (pintype "input"))
      (node (ref "U$2") (pin "27") (pinfunction "VPRG_27") (pintype "input"))
      (node (ref "U$3") (pin "27") (pinfunction "VPRG_27") (pintype "input"))
      (node (ref "U$4") (pin "27") (pinfunction "VPRG_27") (pintype "input"))
      (node (ref "U$5") (pin "27") (pinfunction "VPRG_27") (pintype "input"))
      (node (ref "U$6") (pin "27") (pinfunction "VPRG_27") (pintype "input"))
    )
    (net (code "16") (name "/XLAT") (class "Default")
      (node (ref "TLCPINS") (pin "3") (pinfunction "3_3") (pintype "passive"))
      (node (ref "U$1") (pin "24") (pinfunction "XLAT_24") (pintype "input"))
      (node (ref "U$2") (pin "24") (pinfunction "XLAT_24") (pintype "input"))
      (node (ref "U$3") (pin "24") (pinfunction "XLAT_24") (pintype "input"))
      (node (ref "U$4") (pin "24") (pinfunction "XLAT_24") (pintype "input"))
      (node (ref "U$5") (pin "24") (pinfunction "XLAT_24") (pintype "input"))
      (node (ref "U$6") (pin "24") (pinfunction "XLAT_24") (pintype "input"))
    )
    (net (code "17") (name "GND") (class "Default")
      (node (ref "C1") (pin "2") (pinfunction "2_2") (pintype "passive"))
      (node (ref "C10") (pin "2") (pinfunction "2_2") (pintype "passive"))
      (node (ref "C11") (pin "2") (pinfunction "2_2") (pintype "passive"))
      (node (ref "C12") (pin "2") (pinfunction "2_2") (pintype "passive"))
      (node (ref "C13") (pin "2") (pinfunction "2_2") (pintype "passive"))
      (node (ref "C14") (pin "2") (pinfunction "2_2") (pintype "passive"))
      (node (ref "C15") (pin "2") (pinfunction "2_2") (pintype "passive"))
      (node (ref "C16") (pin "2") (pinfunction "2_2") (pintype "passive"))
      (node (ref "C17") (pin "-") (pinfunction "-_-") (pintype "passive"))
      (node (ref "C18") (pin "-") (pinfunction "-_-") (pintype "passive"))
      (node (ref "C2") (pin "2") (pinfunction "2_2") (pintype "passive"))
      (node (ref "C3") (pin "2") (pinfunction "2_2") (pintype "passive"))
      (node (ref "C4") (pin "2") (pinfunction "2_2") (pintype "passive"))
      (node (ref "C5") (pin "2") (pinfunction "2_2") (pintype "passive"))
      (node (ref "C6") (pin "2") (pinfunction "2_2") (pintype "passive"))
      (node (ref "C7") (pin "2") (pinfunction "2_2") (pintype "passive"))
      (node (ref "C8") (pin "2") (pinfunction "2_2") (pintype "passive"))
      (node (ref "C9") (pin "2") (pinfunction "2_2") (pintype "passive"))
      (node (ref "IC1") (pin "8") (pinfunction "VSS_8") (pintype "power_in"))
      (node (ref "IC2") (pin "8") (pinfunction "VSS_8") (pintype "power_in"))
      (node (ref "IC3") (pin "1") (pinfunction "ADJ_1") (pintype "input"))
      (node (ref "R1") (pin "2") (pinfunction "2_2") (pintype "passive"))
      (node (ref "R10") (pin "1") (pinfunction "1_1") (pintype "passive"))
      (node (ref "R11") (pin "1") (pinfunction "1_1") (pintype "passive"))
      (node (ref "R12") (pin "1") (pinfunction "1_1") (pintype "passive"))
      (node (ref "R13") (pin "1") (pinfunction "1_1") (pintype "passive"))
      (node (ref "R14") (pin "1") (pinfunction "1_1") (pintype "passive"))
      (node (ref "R15") (pin "1") (pinfunction "1_1") (pintype "passive"))
      (node (ref "R16") (pin "1") (pinfunction "1_1") (pintype "passive"))
      (node (ref "R17") (pin "1") (pinfunction "1_1") (pintype "passive"))
      (node (ref "R18") (pin "1") (pinfunction "1_1") (pintype "passive"))
      (node (ref "R19") (pin "1") (pinfunction "1_1") (pintype "passive"))
      (node (ref "R2") (pin "2") (pinfunction "2_2") (pintype "passive"))
      (node (ref "R20") (pin "1") (pinfunction "1_1") (pintype "passive"))
      (node (ref "R21") (pin "1") (pinfunction "1_1") (pintype "passive"))
      (node (ref "R22") (pin "1") (pinfunction "1_1") (pintype "passive"))
      (node (ref "R3") (pin "2") (pinfunction "2_2") (pintype "passive"))
      (node (ref "R4") (pin "2") (pinfunction "2_2") (pintype "passive"))
      (node (ref "R5") (pin "2") (pinfunction "2_2") (pintype "passive"))
      (node (ref "R6") (pin "2") (pinfunction "2_2") (pintype "passive"))
      (node (ref "R7") (pin "1") (pinfunction "1_1") (pintype "passive"))
      (node (ref "R8") (pin "1") (pinfunction "1_1") (pintype "passive"))
      (node (ref "R9") (pin "1") (pinfunction "1_1") (pintype "passive"))
      (node (ref "SHIFTPINS") (pin "1") (pinfunction "1_1") (pintype "passive"))
      (node (ref "SHIFTPINS") (pin "2") (pinfunction "2_2") (pintype "passive"))
      (node (ref "U$1") (pin "22") (pinfunction "GND_22") (pintype "power_in"))
      (node (ref "U$2") (pin "22") (pinfunction "GND_22") (pintype "power_in"))
      (node (ref "U$3") (pin "22") (pinfunction "GND_22") (pintype "power_in"))
      (node (ref "U$4") (pin "22") (pinfunction "GND_22") (pintype "power_in"))
      (node (ref "U$5") (pin "22") (pinfunction "GND_22") (pintype "power_in"))
      (node (ref "U$519") (pin "RING") (pinfunction "RING_RING") (pintype "bidirectional"))
      (node (ref "U$519") (pin "RING_SW") (pinfunction "RING_SW_RING_SW") (pintype "bidirectional"))
      (node (ref "U$6") (pin "22") (pinfunction "GND_22") (pintype "power_in"))
    )
    (net (code "18") (name "Net-(D1-PadA)") (class "Default")
      (node (ref "D1") (pin "A") (pinfunction "A_A") (pintype "passive"))
      (node (ref "U$519") (pin "TIP") (pinfunction "TIP_TIP") (pintype "bidirectional"))
    )
    (net (code "19") (name "Net-(IC1A-Q1)") (class "Default")
      (node (ref "IC1") (pin "4") (pinfunction "Q1_4") (pintype "output"))
      (node (ref "Q17") (pin "2") (pinfunction "G_2") (pintype "passive"))
      (node (ref "R7") (pin "2") (pinfunction "2_2") (pintype "passive"))
    )
    (net (code "20") (name "Net-(IC1A-Q2)") (class "Default")
      (node (ref "IC1") (pin "5") (pinfunction "Q2_5") (pintype "output"))
      (node (ref "Q18") (pin "2") (pinfunction "G_2") (pintype "passive"))
      (node (ref "R8") (pin "2") (pinfunction "2_2") (pintype "passive"))
    )
    (net (code "21") (name "Net-(IC1A-Q3)") (class "Default")
      (node (ref "IC1") (pin "6") (pinfunction "Q3_6") (pintype "output"))
      (node (ref "Q19") (pin "2") (pinfunction "G_2") (pintype "passive"))
      (node (ref "R9") (pin "2") (pinfunction "2_2") (pintype "passive"))
    )
    (net (code "22") (name "Net-(IC1A-Q4)") (class "Default")
      (node (ref "IC1") (pin "7") (pinfunction "Q4_7") (pintype "output"))
      (node (ref "Q20") (pin "2") (pinfunction "G_2") (pintype "passive"))
      (node (ref "R10") (pin "2") (pinfunction "2_2") (pintype "passive"))
    )
    (net (code "23") (name "Net-(IC1A-Q5)") (class "Default")
      (node (ref "IC1") (pin "14") (pinfunction "Q5_14") (pintype "output"))
      (node (ref "Q21") (pin "2") (pinfunction "G_2") (pintype "passive"))
      (node (ref "R11") (pin "2") (pinfunction "2_2") (pintype "passive"))
    )
    (net (code "24") (name "Net-(IC1A-Q6)") (class "Default")
      (node (ref "IC1") (pin "13") (pinfunction "Q6_13") (pintype "output"))
      (node (ref "Q22") (pin "2") (pinfunction "G_2") (pintype "passive"))
      (node (ref "R12") (pin "2") (pinfunction "2_2") (pintype "passive"))
    )
    (net (code "25") (name "Net-(IC1A-Q7)") (class "Default")
      (node (ref "IC1") (pin "12") (pinfunction "Q7_12") (pintype "output"))
      (node (ref "Q23") (pin "2") (pinfunction "G_2") (pintype "passive"))
      (node (ref "R13") (pin "2") (pinfunction "2_2") (pintype "passive"))
    )
    (net (code "26") (name "Net-(IC1A-Q8)") (class "Default")
      (node (ref "IC1") (pin "11") (pinfunction "Q8_11") (pintype "output"))
      (node (ref "Q24") (pin "2") (pinfunction "G_2") (pintype "passive"))
      (node (ref "R14") (pin "2") (pinfunction "2_2") (pintype "passive"))
    )
    (net (code "27") (name "Net-(IC1A-QS)") (class "Default")
      (node (ref "IC1") (pin "9") (pinfunction "QS_9") (pintype "output"))
      (node (ref "IC2") (pin "2") (pinfunction "D_2") (pintype "input"))
    )
    (net (code "28") (name "Net-(IC2A-Q1)") (class "Default")
      (node (ref "IC2") (pin "4") (pinfunction "Q1_4") (pintype "output"))
      (node (ref "Q25") (pin "2") (pinfunction "G_2") (pintype "passive"))
      (node (ref "R15") (pin "2") (pinfunction "2_2") (pintype "passive"))
    )
    (net (code "29") (name "Net-(IC2A-Q2)") (class "Default")
      (node (ref "IC2") (pin "5") (pinfunction "Q2_5") (pintype "output"))
      (node (ref "Q26") (pin "2") (pinfunction "G_2") (pintype "passive"))
      (node (ref "R16") (pin "2") (pinfunction "2_2") (pintype "passive"))
    )
    (net (code "30") (name "Net-(IC2A-Q3)") (class "Default")
      (node (ref "IC2") (pin "6") (pinfunction "Q3_6") (pintype "output"))
      (node (ref "Q27") (pin "2") (pinfunction "G_2") (pintype "passive"))
      (node (ref "R17") (pin "2") (pinfunction "2_2") (pintype "passive"))
    )
    (net (code "31") (name "Net-(IC2A-Q4)") (class "Default")
      (node (ref "IC2") (pin "7") (pinfunction "Q4_7") (pintype "output"))
      (node (ref "Q28") (pin "2") (pinfunction "G_2") (pintype "passive"))
      (node (ref "R18") (pin "2") (pinfunction "2_2") (pintype "passive"))
    )
    (net (code "32") (name "Net-(IC2A-Q5)") (class "Default")
      (node (ref "IC2") (pin "14") (pinfunction "Q5_14") (pintype "output"))
      (node (ref "Q29") (pin "2") (pinfunction "G_2") (pintype "passive"))
      (node (ref "R19") (pin "2") (pinfunction "2_2") (pintype "passive"))
    )
    (net (code "33") (name "Net-(IC2A-Q6)") (class "Default")
      (node (ref "IC2") (pin "13") (pinfunction "Q6_13") (pintype "output"))
      (node (ref "Q30") (pin "2") (pinfunction "G_2") (pintype "passive"))
      (node (ref "R20") (pin "2") (pinfunction "2_2") (pintype "passive"))
    )
    (net (code "34") (name "Net-(IC2A-Q7)") (class "Default")
      (node (ref "IC2") (pin "12") (pinfunction "Q7_12") (pintype "output"))
      (node (ref "Q31") (pin "2") (pinfunction "G_2") (pintype "passive"))
      (node (ref "R21") (pin "2") (pinfunction "2_2") (pintype "passive"))
    )
    (net (code "35") (name "Net-(IC2A-Q8)") (class "Default")
      (node (ref "IC2") (pin "11") (pinfunction "Q8_11") (pintype "output"))
      (node (ref "Q32") (pin "2") (pinfunction "G_2") (pintype "passive"))
      (node (ref "R22") (pin "2") (pinfunction "2_2") (pintype "passive"))
    )
    (net (code "36") (name "Net-(IC3-VI)") (class "Default")
      (node (ref "C17") (pin "+") (pinfunction "+_+") (pintype "passive"))
      (node (ref "D1") (pin "C") (pinfunction "C_C") (pintype "passive"))
      (node (ref "IC3") (pin "3") (pinfunction "VI_3") (pintype "input"))
    )
    (net (code "37") (name "Net-(Q17-D)") (class "Default")
      (node (ref "Q17") (pin "3") (pinfunction "D_3") (pintype "passive"))
      (node (ref "U$10") (pin "2") (pinfunction "V_2") (pintype "bidirectional"))
      (node (ref "U$11") (pin "2") (pinfunction "V_2") (pintype "bidirectional"))
      (node (ref "U$12") (pin "2") (pinfunction "V_2") (pintype "bidirectional"))
      (node (ref "U$13") (pin "2") (pinfunction "V_2") (pintype "bidirectional"))
      (node (ref "U$14") (pin "2") (pinfunction "V_2") (pintype "bidirectional"))
      (node (ref "U$15") (pin "2") (pinfunction "V_2") (pintype "bidirectional"))
      (node (ref "U$16") (pin "2") (pinfunction "V_2") (pintype "bidirectional"))
      (node (ref "U$17") (pin "2") (pinfunction "V_2") (pintype "bidirectional"))
      (node (ref "U$18") (pin "2") (pinfunction "V_2") (pintype "bidirectional"))
      (node (ref "U$19") (pin "2") (pinfunction "V_2") (pintype "bidirectional"))
      (node (ref "U$20") (pin "2") (pinfunction "V_2") (pintype "bidirectional"))
      (node (ref "U$21") (pin "2") (pinfunction "V_2") (pintype "bidirectional"))
      (node (ref "U$22") (pin "2") (pinfunction "V_2") (pintype "bidirectional"))
      (node (ref "U$23") (pin "2") (pinfunction "V_2") (pintype "bidirectional"))
      (node (ref "U$24") (pin "2") (pinfunction "V_2") (pintype "bidirectional"))
      (node (ref "U$25") (pin "2") (pinfunction "V_2") (pintype "bidirectional"))
      (node (ref "U$26") (pin "2") (pinfunction "V_2") (pintype "bidirectional"))
      (node (ref "U$27") (pin "2") (pinfunction "V_2") (pintype "bidirectional"))
      (node (ref "U$28") (pin "2") (pinfunction "V_2") (pintype "bidirectional"))
      (node (ref "U$29") (pin "2") (pinfunction "V_2") (pintype "bidirectional"))
      (node (ref "U$30") (pin "2") (pinfunction "V_2") (pintype "bidirectional"))
      (node (ref "U$31") (pin "2") (pinfunction "V_2") (pintype "bidirectional"))
      (node (ref "U$32") (pin "2") (pinfunction "V_2") (pintype "bidirectional"))
      (node (ref "U$33") (pin "2") (pinfunction "V_2") (pintype "bidirectional"))
      (node (ref "U$34") (pin "2") (pinfunction "V_2") (pintype "bidirectional"))
      (node (ref "U$35") (pin "2") (pinfunction "V_2") (pintype "bidirectional"))
      (node (ref "U$36") (pin "2") (pinfunction "V_2") (pintype "bidirectional"))
      (node (ref "U$37") (pin "2") (pinfunction "V_2") (pintype "bidirectional"))
      (node (ref "U$38") (pin "2") (pinfunction "V_2") (pintype "bidirectional"))
      (node (ref "U$7") (pin "2") (pinfunction "V_2") (pintype "bidirectional"))
      (node (ref "U$8") (pin "2") (pinfunction "V_2") (pintype "bidirectional"))
      (node (ref "U$9") (pin "2") (pinfunction "V_2") (pintype "bidirectional"))
    )
    (net (code "38") (name "Net-(Q18-D)") (class "Default")
      (node (ref "Q18") (pin "3") (pinfunction "D_3") (pintype "passive"))
      (node (ref "U$39") (pin "2") (pinfunction "V_2") (pintype "bidirectional"))
      (node (ref "U$40") (pin "2") (pinfunction "V_2") (pintype "bidirectional"))
      (node (ref "U$41") (pin "2") (pinfunction "V_2") (pintype "bidirectional"))
      (node (ref "U$42") (pin "2") (pinfunction "V_2") (pintype "bidirectional"))
      (node (ref "U$43") (pin "2") (pinfunction "V_2") (pintype "bidirectional"))
      (node (ref "U$44") (pin "2") (pinfunction "V_2") (pintype "bidirectional"))
      (node (ref "U$45") (pin "2") (pinfunction "V_2") (pintype "bidirectional"))
      (node (ref "U$46") (pin "2") (pinfunction "V_2") (pintype "bidirectional"))
      (node (ref "U$47") (pin "2") (pinfunction "V_2") (pintype "bidirectional"))
      (node (ref "U$48") (pin "2") (pinfunction "V_2") (pintype "bidirectional"))
      (node (ref "U$49") (pin "2") (pinfunction "V_2") (pintype "bidirectional"))
      (node (ref "U$50") (pin "2") (pinfunction "V_2") (pintype "bidirectional"))
      (node (ref "U$51") (pin "2") (pinfunction "V_2") (pintype "bidirectional"))
      (node (ref "U$52") (pin "2") (pinfunction "V_2") (pintype "bidirectional"))
      (node (ref "U$53") (pin "2") (pinfunction "V_2") (pintype "bidirectional"))
      (node (ref "U$54") (pin "2") (pinfunction "V_2") (pintype "bidirectional"))
      (node (ref "U$55") (pin "2") (pinfunction "V_2") (pintype "bidirectional"))
      (node (ref "U$56") (pin "2") (pinfunction "V_2") (pintype "bidirectional"))
      (node (ref "U$57") (pin "2") (pinfunction "V_2") (pintype "bidirectional"))
      (node (ref "U$58") (pin "2") (pinfunction "V_2") (pintype "bidirectional"))
      (node (ref "U$59") (pin "2") (pinfunction "V_2") (pintype "bidirectional"))
      (node (ref "U$60") (pin "2") (pinfunction "V_2") (pintype "bidirectional"))
      (node (ref "U$61") (pin "2") (pinfunction "V_2") (pintype "bidirectional"))
      (node (ref "U$62") (pin "2") (pinfunction "V_2") (pintype "bidirectional"))
      (node (ref "U$63") (pin "2") (pinfunction "V_2") (pintype "bidirectional"))
      (node (ref "U$64") (pin "2") (pinfunction "V_2") (pintype "bidirectional"))
      (node (ref "U$65") (pin "2") (pinfunction "V_2") (pintype "bidirectional"))
      (node (ref "U$66") (pin "2") (pinfunction "V_2") (pintype "bidirectional"))
      (node (ref "U$67") (pin "2") (pinfunction "V_2") (pintype "bidirectional"))
      (node (ref "U$68") (pin "2") (pinfunction "V_2") (pintype "bidirectional"))
      (node (ref "U$69") (pin "2") (pinfunction "V_2") (pintype "bidirectional"))
      (node (ref "U$70") (pin "2") (pinfunction "V_2") (pintype "bidirectional"))
    )
    (net (code "39") (name "Net-(Q19-D)") (class "Default")
      (node (ref "Q19") (pin "3") (pinfunction "D_3") (pintype "passive"))
      (node (ref "U$100") (pin "2") (pinfunction "V_2") (pintype "bidirectional"))
      (node (ref "U$101") (pin "2") (pinfunction "V_2") (pintype "bidirectional"))
      (node (ref "U$102") (pin "2") (pinfunction "V_2") (pintype "bidirectional"))
      (node (ref "U$71") (pin "2") (pinfunction "V_2") (pintype "bidirectional"))
      (node (ref "U$72") (pin "2") (pinfunction "V_2") (pintype "bidirectional"))
      (node (ref "U$73") (pin "2") (pinfunction "V_2") (pintype "bidirectional"))
      (node (ref "U$74") (pin "2") (pinfunction "V_2") (pintype "bidirectional"))
      (node (ref "U$75") (pin "2") (pinfunction "V_2") (pintype "bidirectional"))
      (node (ref "U$76") (pin "2") (pinfunction "V_2") (pintype "bidirectional"))
      (node (ref "U$77") (pin "2") (pinfunction "V_2") (pintype "bidirectional"))
      (node (ref "U$78") (pin "2") (pinfunction "V_2") (pintype "bidirectional"))
      (node (ref "U$79") (pin "2") (pinfunction "V_2") (pintype "bidirectional"))
      (node (ref "U$80") (pin "2") (pinfunction "V_2") (pintype "bidirectional"))
      (node (ref "U$81") (pin "2") (pinfunction "V_2") (pintype "bidirectional"))
      (node (ref "U$82") (pin "2") (pinfunction "V_2") (pintype "bidirectional"))
      (node (ref "U$83") (pin "2") (pinfunction "V_2") (pintype "bidirectional"))
      (node (ref "U$84") (pin "2") (pinfunction "V_2") (pintype "bidirectional"))
      (node (ref "U$85") (pin "2") (pinfunction "V_2") (pintype "bidirectional"))
      (node (ref "U$86") (pin "2") (pinfunction "V_2") (pintype "bidirectional"))
      (node (ref "U$87") (pin "2") (pinfunction "V_2") (pintype "bidirectional"))
      (node (ref "U$88") (pin "2") (pinfunction "V_2") (pintype "bidirectional"))
      (node (ref "U$89") (pin "2") (pinfunction "V_2") (pintype "bidirectional"))
      (node (ref "U$90") (pin "2") (pinfunction "V_2") (pintype "bidirectional"))
      (node (ref "U$91") (pin "2") (pinfunction "V_2") (pintype "bidirectional"))
      (node (ref "U$92") (pin "2") (pinfunction "V_2") (pintype "bidirectional"))
      (node (ref "U$93") (pin "2") (pinfunction "V_2") (pintype "bidirectional"))
      (node (ref "U$94") (pin "2") (pinfunction "V_2") (pintype "bidirectional"))
      (node (ref "U$95") (pin "2") (pinfunction "V_2") (pintype "bidirectional"))
      (node (ref "U$96") (pin "2") (pinfunction "V_2") (pintype "bidirectional"))
      (node (ref "U$97") (pin "2") (pinfunction "V_2") (pintype "bidirectional"))
      (node (ref "U$98") (pin "2") (pinfunction "V_2") (pintype "bidirectional"))
      (node (ref "U$99") (pin "2") (pinfunction "V_2") (pintype "bidirectional"))
    )
    (net (code "40") (name "Net-(Q20-D)") (class "Default")
      (node (ref "Q20") (pin "3") (pinfunction "D_3") (pintype "passive"))
      (node (ref "U$103") (pin "2") (pinfunction "V_2") (pintype "bidirectional"))
      (node (ref "U$104") (pin "2") (pinfunction "V_2") (pintype "bidirectional"))
      (node (ref "U$105") (pin "2") (pinfunction "V_2") (pintype "bidirectional"))
      (node (ref "U$106") (pin "2") (pinfunction "V_2") (pintype "bidirectional"))
      (node (ref "U$107") (pin "2") (pinfunction "V_2") (pintype "bidirectional"))
      (node (ref "U$108") (pin "2") (pinfunction "V_2") (pintype "bidirectional"))
      (node (ref "U$109") (pin "2") (pinfunction "V_2") (pintype "bidirectional"))
      (node (ref "U$110") (pin "2") (pinfunction "V_2") (pintype "bidirectional"))
      (node (ref "U$111") (pin "2") (pinfunction "V_2") (pintype "bidirectional"))
      (node (ref "U$112") (pin "2") (pinfunction "V_2") (pintype "bidirectional"))
      (node (ref "U$113") (pin "2") (pinfunction "V_2") (pintype "bidirectional"))
      (node (ref "U$114") (pin "2") (pinfunction "V_2") (pintype "bidirectional"))
      (node (ref "U$115") (pin "2") (pinfunction "V_2") (pintype "bidirectional"))
      (node (ref "U$116") (pin "2") (pinfunction "V_2") (pintype "bidirectional"))
      (node (ref "U$117") (pin "2") (pinfunction "V_2") (pintype "bidirectional"))
      (node (ref "U$118") (pin "2") (pinfunction "V_2") (pintype "bidirectional"))
      (node (ref "U$119") (pin "2") (pinfunction "V_2") (pintype "bidirectional"))
      (node (ref "U$120") (pin "2") (pinfunction "V_2") (pintype "bidirectional"))
      (node (ref "U$121") (pin "2") (pinfunction "V_2") (pintype "bidirectional"))
      (node (ref "U$122") (pin "2") (pinfunction "V_2") (pintype "bidirectional"))
      (node (ref "U$123") (pin "2") (pinfunction "V_2") (pintype "bidirectional"))
      (node (ref "U$124") (pin "2") (pinfunction "V_2") (pintype "bidirectional"))
      (node (ref "U$125") (pin "2") (pinfunction "V_2") (pintype "bidirectional"))
      (node (ref "U$126") (pin "2") (pinfunction "V_2") (pintype "bidirectional"))
      (node (ref "U$127") (pin "2") (pinfunction "V_2") (pintype "bidirectional"))
      (node (ref "U$128") (pin "2") (pinfunction "V_2") (pintype "bidirectional"))
      (node (ref "U$129") (pin "2") (pinfunction "V_2") (pintype "bidirectional"))
      (node (ref "U$130") (pin "2") (pinfunction "V_2") (pintype "bidirectional"))
      (node (ref "U$131") (pin "2") (pinfunction "V_2") (pintype "bidirectional"))
      (node (ref "U$132") (pin "2") (pinfunction "V_2") (pintype "bidirectional"))
      (node (ref "U$133") (pin "2") (pinfunction "V_2") (pintype "bidirectional"))
      (node (ref "U$134") (pin "2") (pinfunction "V_2") (pintype "bidirectional"))
    )
    (net (code "41") (name "Net-(Q21-D)") (class "Default")
      (node (ref "Q21") (pin "3") (pinfunction "D_3") (pintype "passive"))
      (node (ref "U$135") (pin "2") (pinfunction "V_2") (pintype "bidirectional"))
      (node (ref "U$136") (pin "2") (pinfunction "V_2") (pintype "bidirectional"))
      (node (ref "U$137") (pin "2") (pinfunction "V_2") (pintype "bidirectional"))
      (node (ref "U$138") (pin "2") (pinfunction "V_2") (pintype "bidirectional"))
      (node (ref "U$139") (pin "2") (pinfunction "V_2") (pintype "bidirectional"))
      (node (ref "U$140") (pin "2") (pinfunction "V_2") (pintype "bidirectional"))
      (node (ref "U$141") (pin "2") (pinfunction "V_2") (pintype "bidirectional"))
      (node (ref "U$142") (pin "2") (pinfunction "V_2") (pintype "bidirectional"))
      (node (ref "U$143") (pin "2") (pinfunction "V_2") (pintype "bidirectional"))
      (node (ref "U$144") (pin "2") (pinfunction "V_2") (pintype "bidirectional"))
      (node (ref "U$145") (pin "2") (pinfunction "V_2") (pintype "bidirectional"))
      (node (ref "U$146") (pin "2") (pinfunction "V_2") (pintype "bidirectional"))
      (node (ref "U$147") (pin "2") (pinfunction "V_2") (pintype "bidirectional"))
      (node (ref "U$148") (pin "2") (pinfunction "V_2") (pintype "bidirectional"))
      (node (ref "U$149") (pin "2") (pinfunction "V_2") (pintype "bidirectional"))
      (node (ref "U$150") (pin "2") (pinfunction "V_2") (pintype "bidirectional"))
      (node (ref "U$151") (pin "2") (pinfunction "V_2") (pintype "bidirectional"))
      (node (ref "U$152") (pin "2") (pinfunction "V_2") (pintype "bidirectional"))
      (node (ref "U$153") (pin "2") (pinfunction "V_2") (pintype "bidirectional"))
      (node (ref "U$154") (pin "2") (pinfunction "V_2") (pintype "bidirectional"))
      (node (ref "U$155") (pin "2") (pinfunction "V_2") (pintype "bidirectional"))
      (node (ref "U$156") (pin "2") (pinfunction "V_2") (pintype "bidirectional"))
      (node (ref "U$157") (pin "2") (pinfunction "V_2") (pintype "bidirectional"))
      (node (ref "U$158") (pin "2") (pinfunction "V_2") (pintype "bidirectional"))
      (node (ref "U$159") (pin "2") (pinfunction "V_2") (pintype "bidirectional"))
      (node (ref "U$160") (pin "2") (pinfunction "V_2") (pintype "bidirectional"))
      (node (ref "U$161") (pin "2") (pinfunction "V_2") (pintype "bidirectional"))
      (node (ref "U$162") (pin "2") (pinfunction "V_2") (pintype "bidirectional"))
      (node (ref "U$163") (pin "2") (pinfunction "V_2") (pintype "bidirectional"))
      (node (ref "U$164") (pin "2") (pinfunction "V_2") (pintype "bidirectional"))
      (node (ref "U$165") (pin "2") (pinfunction "V_2") (pintype "bidirectional"))
      (node (ref "U$166") (pin "2") (pinfunction "V_2") (pintype "bidirectional"))
    )
    (net (code "42") (name "Net-(Q22-D)") (class "Default")
      (node (ref "Q22") (pin "3") (pinfunction "D_3") (pintype "passive"))
      (node (ref "U$167") (pin "2") (pinfunction "V_2") (pintype "bidirectional"))
      (node (ref "U$168") (pin "2") (pinfunction "V_2") (pintype "bidirectional"))
      (node (ref "U$169") (pin "2") (pinfunction "V_2") (pintype "bidirectional"))
      (node (ref "U$170") (pin "2") (pinfunction "V_2") (pintype "bidirectional"))
      (node (ref "U$171") (pin "2") (pinfunction "V_2") (pintype "bidirectional"))
      (node (ref "U$172") (pin "2") (pinfunction "V_2") (pintype "bidirectional"))
      (node (ref "U$173") (pin "2") (pinfunction "V_2") (pintype "bidirectional"))
      (node (ref "U$174") (pin "2") (pinfunction "V_2") (pintype "bidirectional"))
      (node (ref "U$175") (pin "2") (pinfunction "V_2") (pintype "bidirectional"))
      (node (ref "U$176") (pin "2") (pinfunction "V_2") (pintype "bidirectional"))
      (node (ref "U$177") (pin "2") (pinfunction "V_2") (pintype "bidirectional"))
      (node (ref "U$178") (pin "2") (pinfunction "V_2") (pintype "bidirectional"))
      (node (ref "U$179") (pin "2") (pinfunction "V_2") (pintype "bidirectional"))
      (node (ref "U$180") (pin "2") (pinfunction "V_2") (pintype "bidirectional"))
      (node (ref "U$181") (pin "2") (pinfunction "V_2") (pintype "bidirectional"))
      (node (ref "U$182") (pin "2") (pinfunction "V_2") (pintype "bidirectional"))
      (node (ref "U$183") (pin "2") (pinfunction "V_2") (pintype "bidirectional"))
      (node (ref "U$184") (pin "2") (pinfunction "V_2") (pintype "bidirectional"))
      (node (ref "U$185") (pin "2") (pinfunction "V_2") (pintype "bidirectional"))
      (node (ref "U$186") (pin "2") (pinfunction "V_2") (pintype "bidirectional"))
      (node (ref "U$187") (pin "2") (pinfunction "V_2") (pintype "bidirectional"))
      (node (ref "U$188") (pin "2") (pinfunction "V_2") (pintype "bidirectional"))
      (node (ref "U$189") (pin "2") (pinfunction "V_2") (pintype "bidirectional"))
      (node (ref "U$190") (pin "2") (pinfunction "V_2") (pintype "bidirectional"))
      (node (ref "U$191") (pin "2") (pinfunction "V_2") (pintype "bidirectional"))
      (node (ref "U$192") (pin "2") (pinfunction "V_2") (pintype "bidirectional"))
      (node (ref "U$193") (pin "2") (pinfunction "V_2") (pintype "bidirectional"))
      (node (ref "U$194") (pin "2") (pinfunction "V_2") (pintype "bidirectional"))
      (node (ref "U$195") (pin "2") (pinfunction "V_2") (pintype "bidirectional"))
      (node (ref "U$196") (pin "2") (pinfunction "V_2") (pintype "bidirectional"))
      (node (ref "U$197") (pin "2") (pinfunction "V_2") (pintype "bidirectional"))
      (node (ref "U$198") (pin "2") (pinfunction "V_2") (pintype "bidirectional"))
    )
    (net (code "43") (name "Net-(Q23-D)") (class "Default")
      (node (ref "Q23") (pin "3") (pinfunction "D_3") (pintype "passive"))
      (node (ref "U$199") (pin "2") (pinfunction "V_2") (pintype "bidirectional"))
      (node (ref "U$200") (pin "2") (pinfunction "V_2") (pintype "bidirectional"))
      (node (ref "U$201") (pin "2") (pinfunction "V_2") (pintype "bidirectional"))
      (node (ref "U$202") (pin "2") (pinfunction "V_2") (pintype "bidirectional"))
      (node (ref "U$203") (pin "2") (pinfunction "V_2") (pintype "bidirectional"))
      (node (ref "U$204") (pin "2") (pinfunction "V_2") (pintype "bidirectional"))
      (node (ref "U$205") (pin "2") (pinfunction "V_2") (pintype "bidirectional"))
      (node (ref "U$206") (pin "2") (pinfunction "V_2") (pintype "bidirectional"))
      (node (ref "U$207") (pin "2") (pinfunction "V_2") (pintype "bidirectional"))
      (node (ref "U$208") (pin "2") (pinfunction "V_2") (pintype "bidirectional"))
      (node (ref "U$209") (pin "2") (pinfunction "V_2") (pintype "bidirectional"))
      (node (ref "U$210") (pin "2") (pinfunction "V_2") (pintype "bidirectional"))
      (node (ref "U$211") (pin "2") (pinfunction "V_2") (pintype "bidirectional"))
      (node (ref "U$212") (pin "2") (pinfunction "V_2") (pintype "bidirectional"))
      (node (ref "U$213") (pin "2") (pinfunction "V_2") (pintype "bidirectional"))
      (node (ref "U$214") (pin "2") (pinfunction "V_2") (pintype "bidirectional"))
      (node (ref "U$215") (pin "2") (pinfunction "V_2") (pintype "bidirectional"))
      (node (ref "U$216") (pin "2") (pinfunction "V_2") (pintype "bidirectional"))
      (node (ref "U$217") (pin "2") (pinfunction "V_2") (pintype "bidirectional"))
      (node (ref "U$218") (pin "2") (pinfunction "V_2") (pintype "bidirectional"))
      (node (ref "U$219") (pin "2") (pinfunction "V_2") (pintype "bidirectional"))
      (node (ref "U$220") (pin "2") (pinfunction "V_2") (pintype "bidirectional"))
      (node (ref "U$221") (pin "2") (pinfunction "V_2") (pintype "bidirectional"))
      (node (ref "U$222") (pin "2") (pinfunction "V_2") (pintype "bidirectional"))
      (node (ref "U$223") (pin "2") (pinfunction "V_2") (pintype "bidirectional"))
      (node (ref "U$224") (pin "2") (pinfunction "V_2") (pintype "bidirectional"))
      (node (ref "U$225") (pin "2") (pinfunction "V_2") (pintype "bidirectional"))
      (node (ref "U$226") (pin "2") (pinfunction "V_2") (pintype "bidirectional"))
      (node (ref "U$227") (pin "2") (pinfunction "V_2") (pintype "bidirectional"))
      (node (ref "U$228") (pin "2") (pinfunction "V_2") (pintype "bidirectional"))
      (node (ref "U$229") (pin "2") (pinfunction "V_2") (pintype "bidirectional"))
      (node (ref "U$230") (pin "2") (pinfunction "V_2") (pintype "bidirectional"))
    )
    (net (code "44") (name "Net-(Q24-D)") (class "Default")
      (node (ref "Q24") (pin "3") (pinfunction "D_3") (pintype "passive"))
      (node (ref "U$231") (pin "2") (pinfunction "V_2") (pintype "bidirectional"))
      (node (ref "U$232") (pin "2") (pinfunction "V_2") (pintype "bidirectional"))
      (node (ref "U$233") (pin "2") (pinfunction "V_2") (pintype "bidirectional"))
      (node (ref "U$234") (pin "2") (pinfunction "V_2") (pintype "bidirectional"))
      (node (ref "U$235") (pin "2") (pinfunction "V_2") (pintype "bidirectional"))
      (node (ref "U$236") (pin "2") (pinfunction "V_2") (pintype "bidirectional"))
      (node (ref "U$237") (pin "2") (pinfunction "V_2") (pintype "bidirectional"))
      (node (ref "U$238") (pin "2") (pinfunction "V_2") (pintype "bidirectional"))
      (node (ref "U$239") (pin "2") (pinfunction "V_2") (pintype "bidirectional"))
      (node (ref "U$240") (pin "2") (pinfunction "V_2") (pintype "bidirectional"))
      (node (ref "U$241") (pin "2") (pinfunction "V_2") (pintype "bidirectional"))
      (node (ref "U$242") (pin "2") (pinfunction "V_2") (pintype "bidirectional"))
      (node (ref "U$243") (pin "2") (pinfunction "V_2") (pintype "bidirectional"))
      (node (ref "U$244") (pin "2") (pinfunction "V_2") (pintype "bidirectional"))
      (node (ref "U$245") (pin "2") (pinfunction "V_2") (pintype "bidirectional"))
      (node (ref "U$246") (pin "2") (pinfunction "V_2") (pintype "bidirectional"))
      (node (ref "U$247") (pin "2") (pinfunction "V_2") (pintype "bidirectional"))
      (node (ref "U$248") (pin "2") (pinfunction "V_2") (pintype "bidirectional"))
      (node (ref "U$249") (pin "2") (pinfunction "V_2") (pintype "bidirectional"))
      (node (ref "U$250") (pin "2") (pinfunction "V_2") (pintype "bidirectional"))
      (node (ref "U$251") (pin "2") (pinfunction "V_2") (pintype "bidirectional"))
      (node (ref "U$252") (pin "2") (pinfunction "V_2") (pintype "bidirectional"))
      (node (ref "U$253") (pin "2") (pinfunction "V_2") (pintype "bidirectional"))
      (node (ref "U$254") (pin "2") (pinfunction "V_2") (pintype "bidirectional"))
      (node (ref "U$255") (pin "2") (pinfunction "V_2") (pintype "bidirectional"))
      (node (ref "U$256") (pin "2") (pinfunction "V_2") (pintype "bidirectional"))
      (node (ref "U$257") (pin "2") (pinfunction "V_2") (pintype "bidirectional"))
      (node (ref "U$258") (pin "2") (pinfunction "V_2") (pintype "bidirectional"))
      (node (ref "U$259") (pin "2") (pinfunction "V_2") (pintype "bidirectional"))
      (node (ref "U$260") (pin "2") (pinfunction "V_2") (pintype "bidirectional"))
      (node (ref "U$261") (pin "2") (pinfunction "V_2") (pintype "bidirectional"))
      (node (ref "U$262") (pin "2") (pinfunction "V_2") (pintype "bidirectional"))
    )
    (net (code "45") (name "Net-(Q25-D)") (class "Default")
      (node (ref "Q25") (pin "3") (pinfunction "D_3") (pintype "passive"))
      (node (ref "U$263") (pin "2") (pinfunction "V_2") (pintype "bidirectional"))
      (node (ref "U$264") (pin "2") (pinfunction "V_2") (pintype "bidirectional"))
      (node (ref "U$265") (pin "2") (pinfunction "V_2") (pintype "bidirectional"))
      (node (ref "U$266") (pin "2") (pinfunction "V_2") (pintype "bidirectional"))
      (node (ref "U$267") (pin "2") (pinfunction "V_2") (pintype "bidirectional"))
      (node (ref "U$268") (pin "2") (pinfunction "V_2") (pintype "bidirectional"))
      (node (ref "U$269") (pin "2") (pinfunction "V_2") (pintype "bidirectional"))
      (node (ref "U$270") (pin "2") (pinfunction "V_2") (pintype "bidirectional"))
      (node (ref "U$271") (pin "2") (pinfunction "V_2") (pintype "bidirectional"))
      (node (ref "U$272") (pin "2") (pinfunction "V_2") (pintype "bidirectional"))
      (node (ref "U$273") (pin "2") (pinfunction "V_2") (pintype "bidirectional"))
      (node (ref "U$274") (pin "2") (pinfunction "V_2") (pintype "bidirectional"))
      (node (ref "U$275") (pin "2") (pinfunction "V_2") (pintype "bidirectional"))
      (node (ref "U$276") (pin "2") (pinfunction "V_2") (pintype "bidirectional"))
      (node (ref "U$277") (pin "2") (pinfunction "V_2") (pintype "bidirectional"))
      (node (ref "U$278") (pin "2") (pinfunction "V_2") (pintype "bidirectional"))
      (node (ref "U$279") (pin "2") (pinfunction "V_2") (pintype "bidirectional"))
      (node (ref "U$280") (pin "2") (pinfunction "V_2") (pintype "bidirectional"))
      (node (ref "U$281") (pin "2") (pinfunction "V_2") (pintype "bidirectional"))
      (node (ref "U$282") (pin "2") (pinfunction "V_2") (pintype "bidirectional"))
      (node (ref "U$283") (pin "2") (pinfunction "V_2") (pintype "bidirectional"))
      (node (ref "U$284") (pin "2") (pinfunction "V_2") (pintype "bidirectional"))
      (node (ref "U$285") (pin "2") (pinfunction "V_2") (pintype "bidirectional"))
      (node (ref "U$286") (pin "2") (pinfunction "V_2") (pintype "bidirectional"))
      (node (ref "U$287") (pin "2") (pinfunction "V_2") (pintype "bidirectional"))
      (node (ref "U$288") (pin "2") (pinfunction "V_2") (pintype "bidirectional"))
      (node (ref "U$289") (pin "2") (pinfunction "V_2") (pintype "bidirectional"))
      (node (ref "U$290") (pin "2") (pinfunction "V_2") (pintype "bidirectional"))
      (node (ref "U$291") (pin "2") (pinfunction "V_2") (pintype "bidirectional"))
      (node (ref "U$292") (pin "2") (pinfunction "V_2") (pintype "bidirectional"))
      (node (ref "U$293") (pin "2") (pinfunction "V_2") (pintype "bidirectional"))
      (node (ref "U$294") (pin "2") (pinfunction "V_2") (pintype "bidirectional"))
    )
    (net (code "46") (name "Net-(Q26-D)") (class "Default")
      (node (ref "Q26") (pin "3") (pinfunction "D_3") (pintype "passive"))
      (node (ref "U$295") (pin "2") (pinfunction "V_2") (pintype "bidirectional"))
      (node (ref "U$296") (pin "2") (pinfunction "V_2") (pintype "bidirectional"))
      (node (ref "U$297") (pin "2") (pinfunction "V_2") (pintype "bidirectional"))
      (node (ref "U$298") (pin "2") (pinfunction "V_2") (pintype "bidirectional"))
      (node (ref "U$299") (pin "2") (pinfunction "V_2") (pintype "bidirectional"))
      (node (ref "U$300") (pin "2") (pinfunction "V_2") (pintype "bidirectional"))
      (node (ref "U$301") (pin "2") (pinfunction "V_2") (pintype "bidirectional"))
      (node (ref "U$302") (pin "2") (pinfunction "V_2") (pintype "bidirectional"))
      (node (ref "U$303") (pin "2") (pinfunction "V_2") (pintype "bidirectional"))
      (node (ref "U$304") (pin "2") (pinfunction "V_2") (pintype "bidirectional"))
      (node (ref "U$305") (pin "2") (pinfunction "V_2") (pintype "bidirectional"))
      (node (ref "U$306") (pin "2") (pinfunction "V_2") (pintype "bidirectional"))
      (node (ref "U$307") (pin "2") (pinfunction "V_2") (pintype "bidirectional"))
      (node (ref "U$308") (pin "2") (pinfunction "V_2") (pintype "bidirectional"))
      (node (ref "U$309") (pin "2") (pinfunction "V_2") (pintype "bidirectional"))
      (node (ref "U$310") (pin "2") (pinfunction "V_2") (pintype "bidirectional"))
      (node (ref "U$311") (pin "2") (pinfunction "V_2") (pintype "bidirectional"))
      (node (ref "U$312") (pin "2") (pinfunction "V_2") (pintype "bidirectional"))
      (node (ref "U$313") (pin "2") (pinfunction "V_2") (pintype "bidirectional"))
      (node (ref "U$314") (pin "2") (pinfunction "V_2") (pintype "bidirectional"))
      (node (ref "U$315") (pin "2") (pinfunction "V_2") (pintype "bidirectional"))
      (node (ref "U$316") (pin "2") (pinfunction "V_2") (pintype "bidirectional"))
      (node (ref "U$317") (pin "2") (pinfunction "V_2") (pintype "bidirectional"))
      (node (ref "U$318") (pin "2") (pinfunction "V_2") (pintype "bidirectional"))
      (node (ref "U$319") (pin "2") (pinfunction "V_2") (pintype "bidirectional"))
      (node (ref "U$320") (pin "2") (pinfunction "V_2") (pintype "bidirectional"))
      (node (ref "U$321") (pin "2") (pinfunction "V_2") (pintype "bidirectional"))
      (node (ref "U$322") (pin "2") (pinfunction "V_2") (pintype "bidirectional"))
      (node (ref "U$323") (pin "2") (pinfunction "V_2") (pintype "bidirectional"))
      (node (ref "U$324") (pin "2") (pinfunction "V_2") (pintype "bidirectional"))
      (node (ref "U$325") (pin "2") (pinfunction "V_2") (pintype "bidirectional"))
      (node (ref "U$326") (pin "2") (pinfunction "V_2") (pintype "bidirectional"))
    )
    (net (code "47") (name "Net-(Q27-D)") (class "Default")
      (node (ref "Q27") (pin "3") (pinfunction "D_3") (pintype "passive"))
      (node (ref "U$327") (pin "2") (pinfunction "V_2") (pintype "bidirectional"))
      (node (ref "U$328") (pin "2") (pinfunction "V_2") (pintype "bidirectional"))
      (node (ref "U$329") (pin "2") (pinfunction "V_2") (pintype "bidirectional"))
      (node (ref "U$330") (pin "2") (pinfunction "V_2") (pintype "bidirectional"))
      (node (ref "U$331") (pin "2") (pinfunction "V_2") (pintype "bidirectional"))
      (node (ref "U$332") (pin "2") (pinfunction "V_2") (pintype "bidirectional"))
      (node (ref "U$333") (pin "2") (pinfunction "V_2") (pintype "bidirectional"))
      (node (ref "U$334") (pin "2") (pinfunction "V_2") (pintype "bidirectional"))
      (node (ref "U$335") (pin "2") (pinfunction "V_2") (pintype "bidirectional"))
      (node (ref "U$336") (pin "2") (pinfunction "V_2") (pintype "bidirectional"))
      (node (ref "U$337") (pin "2") (pinfunction "V_2") (pintype "bidirectional"))
      (node (ref "U$338") (pin "2") (pinfunction "V_2") (pintype "bidirectional"))
      (node (ref "U$339") (pin "2") (pinfunction "V_2") (pintype "bidirectional"))
      (node (ref "U$340") (pin "2") (pinfunction "V_2") (pintype "bidirectional"))
      (node (ref "U$341") (pin "2") (pinfunction "V_2") (pintype "bidirectional"))
      (node (ref "U$342") (pin "2") (pinfunction "V_2") (pintype "bidirectional"))
      (node (ref "U$343") (pin "2") (pinfunction "V_2") (pintype "bidirectional"))
      (node (ref "U$344") (pin "2") (pinfunction "V_2") (pintype "bidirectional"))
      (node (ref "U$345") (pin "2") (pinfunction "V_2") (pintype "bidirectional"))
      (node (ref "U$346") (pin "2") (pinfunction "V_2") (pintype "bidirectional"))
      (node (ref "U$347") (pin "2") (pinfunction "V_2") (pintype "bidirectional"))
      (node (ref "U$348") (pin "2") (pinfunction "V_2") (pintype "bidirectional"))
      (node (ref "U$349") (pin "2") (pinfunction "V_2") (pintype "bidirectional"))
      (node (ref "U$350") (pin "2") (pinfunction "V_2") (pintype "bidirectional"))
      (node (ref "U$351") (pin "2") (pinfunction "V_2") (pintype "bidirectional"))
      (node (ref "U$352") (pin "2") (pinfunction "V_2") (pintype "bidirectional"))
      (node (ref "U$353") (pin "2") (pinfunction "V_2") (pintype "bidirectional"))
      (node (ref "U$354") (pin "2") (pinfunction "V_2") (pintype "bidirectional"))
      (node (ref "U$355") (pin "2") (pinfunction "V_2") (pintype "bidirectional"))
      (node (ref "U$356") (pin "2") (pinfunction "V_2") (pintype "bidirectional"))
      (node (ref "U$357") (pin "2") (pinfunction "V_2") (pintype "bidirectional"))
      (node (ref "U$358") (pin "2") (pinfunction "V_2") (pintype "bidirectional"))
    )
    (net (code "48") (name "Net-(Q28-D)") (class "Default")
      (node (ref "Q28") (pin "3") (pinfunction "D_3") (pintype "passive"))
      (node (ref "U$359") (pin "2") (pinfunction "V_2") (pintype "bidirectional"))
      (node (ref "U$360") (pin "2") (pinfunction "V_2") (pintype "bidirectional"))
      (node (ref "U$361") (pin "2") (pinfunction "V_2") (pintype "bidirectional"))
      (node (ref "U$362") (pin "2") (pinfunction "V_2") (pintype "bidirectional"))
      (node (ref "U$363") (pin "2") (pinfunction "V_2") (pintype "bidirectional"))
      (node (ref "U$364") (pin "2") (pinfunction "V_2") (pintype "bidirectional"))
      (node (ref "U$365") (pin "2") (pinfunction "V_2") (pintype "bidirectional"))
      (node (ref "U$366") (pin "2") (pinfunction "V_2") (pintype "bidirectional"))
      (node (ref "U$367") (pin "2") (pinfunction "V_2") (pintype "bidirectional"))
      (node (ref "U$368") (pin "2") (pinfunction "V_2") (pintype "bidirectional"))
      (node (ref "U$369") (pin "2") (pinfunction "V_2") (pintype "bidirectional"))
      (node (ref "U$370") (pin "2") (pinfunction "V_2") (pintype "bidirectional"))
      (node (ref "U$371") (pin "2") (pinfunction "V_2") (pintype "bidirectional"))
      (node (ref "U$372") (pin "2") (pinfunction "V_2") (pintype "bidirectional"))
      (node (ref "U$373") (pin "2") (pinfunction "V_2") (pintype "bidirectional"))
      (node (ref "U$374") (pin "2") (pinfunction "V_2") (pintype "bidirectional"))
      (node (ref "U$375") (pin "2") (pinfunction "V_2") (pintype "bidirectional"))
      (node (ref "U$376") (pin "2") (pinfunction "V_2") (pintype "bidirectional"))
      (node (ref "U$377") (pin "2") (pinfunction "V_2") (pintype "bidirectional"))
      (node (ref "U$378") (pin "2") (pinfunction "V_2") (pintype "bidirectional"))
      (node (ref "U$379") (pin "2") (pinfunction "V_2") (pintype "bidirectional"))
      (node (ref "U$380") (pin "2") (pinfunction "V_2") (pintype "bidirectional"))
      (node (ref "U$381") (pin "2") (pinfunction "V_2") (pintype "bidirectional"))
      (node (ref "U$382") (pin "2") (pinfunction "V_2") (pintype "bidirectional"))
      (node (ref "U$383") (pin "2") (pinfunction "V_2") (pintype "bidirectional"))
      (node (ref "U$384") (pin "2") (pinfunction "V_2") (pintype "bidirectional"))
      (node (ref "U$385") (pin "2") (pinfunction "V_2") (pintype "bidirectional"))
      (node (ref "U$386") (pin "2") (pinfunction "V_2") (pintype "bidirectional"))
      (node (ref "U$387") (pin "2") (pinfunction "V_2") (pintype "bidirectional"))
      (node (ref "U$388") (pin "2") (pinfunction "V_2") (pintype "bidirectional"))
      (node (ref "U$389") (pin "2") (pinfunction "V_2") (pintype "bidirectional"))
      (node (ref "U$390") (pin "2") (pinfunction "V_2") (pintype "bidirectional"))
    )
    (net (code "49") (name "Net-(Q29-D)") (class "Default")
      (node (ref "Q29") (pin "3") (pinfunction "D_3") (pintype "passive"))
      (node (ref "U$391") (pin "2") (pinfunction "V_2") (pintype "bidirectional"))
      (node (ref "U$392") (pin "2") (pinfunction "V_2") (pintype "bidirectional"))
      (node (ref "U$393") (pin "2") (pinfunction "V_2") (pintype "bidirectional"))
      (node (ref "U$394") (pin "2") (pinfunction "V_2") (pintype "bidirectional"))
      (node (ref "U$395") (pin "2") (pinfunction "V_2") (pintype "bidirectional"))
      (node (ref "U$396") (pin "2") (pinfunction "V_2") (pintype "bidirectional"))
      (node (ref "U$397") (pin "2") (pinfunction "V_2") (pintype "bidirectional"))
      (node (ref "U$398") (pin "2") (pinfunction "V_2") (pintype "bidirectional"))
      (node (ref "U$399") (pin "2") (pinfunction "V_2") (pintype "bidirectional"))
      (node (ref "U$400") (pin "2") (pinfunction "V_2") (pintype "bidirectional"))
      (node (ref "U$401") (pin "2") (pinfunction "V_2") (pintype "bidirectional"))
      (node (ref "U$402") (pin "2") (pinfunction "V_2") (pintype "bidirectional"))
      (node (ref "U$403") (pin "2") (pinfunction "V_2") (pintype "bidirectional"))
      (node (ref "U$404") (pin "2") (pinfunction "V_2") (pintype "bidirectional"))
      (node (ref "U$405") (pin "2") (pinfunction "V_2") (pintype "bidirectional"))
      (node (ref "U$406") (pin "2") (pinfunction "V_2") (pintype "bidirectional"))
      (node (ref "U$407") (pin "2") (pinfunction "V_2") (pintype "bidirectional"))
      (node (ref "U$408") (pin "2") (pinfunction "V_2") (pintype "bidirectional"))
      (node (ref "U$409") (pin "2") (pinfunction "V_2") (pintype "bidirectional"))
      (node (ref "U$410") (pin "2") (pinfunction "V_2") (pintype "bidirectional"))
      (node (ref "U$411") (pin "2") (pinfunction "V_2") (pintype "bidirectional"))
      (node (ref "U$412") (pin "2") (pinfunction "V_2") (pintype "bidirectional"))
      (node (ref "U$413") (pin "2") (pinfunction "V_2") (pintype "bidirectional"))
      (node (ref "U$414") (pin "2") (pinfunction "V_2") (pintype "bidirectional"))
      (node (ref "U$415") (pin "2") (pinfunction "V_2") (pintype "bidirectional"))
      (node (ref "U$416") (pin "2") (pinfunction "V_2") (pintype "bidirectional"))
      (node (ref "U$417") (pin "2") (pinfunction "V_2") (pintype "bidirectional"))
      (node (ref "U$418") (pin "2") (pinfunction "V_2") (pintype "bidirectional"))
      (node (ref "U$419") (pin "2") (pinfunction "V_2") (pintype "bidirectional"))
      (node (ref "U$420") (pin "2") (pinfunction "V_2") (pintype "bidirectional"))
      (node (ref "U$421") (pin "2") (pinfunction "V_2") (pintype "bidirectional"))
      (node (ref "U$422") (pin "2") (pinfunction "V_2") (pintype "bidirectional"))
    )
    (net (code "50") (name "Net-(Q30-D)") (class "Default")
      (node (ref "Q30") (pin "3") (pinfunction "D_3") (pintype "passive"))
      (node (ref "U$423") (pin "2") (pinfunction "V_2") (pintype "bidirectional"))
      (node (ref "U$424") (pin "2") (pinfunction "V_2") (pintype "bidirectional"))
      (node (ref "U$425") (pin "2") (pinfunction "V_2") (pintype "bidirectional"))
      (node (ref "U$426") (pin "2") (pinfunction "V_2") (pintype "bidirectional"))
      (node (ref "U$427") (pin "2") (pinfunction "V_2") (pintype "bidirectional"))
      (node (ref "U$428") (pin "2") (pinfunction "V_2") (pintype "bidirectional"))
      (node (ref "U$429") (pin "2") (pinfunction "V_2") (pintype "bidirectional"))
      (node (ref "U$430") (pin "2") (pinfunction "V_2") (pintype "bidirectional"))
      (node (ref "U$431") (pin "2") (pinfunction "V_2") (pintype "bidirectional"))
      (node (ref "U$432") (pin "2") (pinfunction "V_2") (pintype "bidirectional"))
      (node (ref "U$433") (pin "2") (pinfunction "V_2") (pintype "bidirectional"))
      (node (ref "U$434") (pin "2") (pinfunction "V_2") (pintype "bidirectional"))
      (node (ref "U$435") (pin "2") (pinfunction "V_2") (pintype "bidirectional"))
      (node (ref "U$436") (pin "2") (pinfunction "V_2") (pintype "bidirectional"))
      (node (ref "U$437") (pin "2") (pinfunction "V_2") (pintype "bidirectional"))
      (node (ref "U$438") (pin "2") (pinfunction "V_2") (pintype "bidirectional"))
      (node (ref "U$439") (pin "2") (pinfunction "V_2") (pintype "bidirectional"))
      (node (ref "U$440") (pin "2") (pinfunction "V_2") (pintype "bidirectional"))
      (node (ref "U$441") (pin "2") (pinfunction "V_2") (pintype "bidirectional"))
      (node (ref "U$442") (pin "2") (pinfunction "V_2") (pintype "bidirectional"))
      (node (ref "U$443") (pin "2") (pinfunction "V_2") (pintype "bidirectional"))
      (node (ref "U$444") (pin "2") (pinfunction "V_2") (pintype "bidirectional"))
      (node (ref "U$445") (pin "2") (pinfunction "V_2") (pintype "bidirectional"))
      (node (ref "U$446") (pin "2") (pinfunction "V_2") (pintype "bidirectional"))
      (node (ref "U$447") (pin "2") (pinfunction "V_2") (pintype "bidirectional"))
      (node (ref "U$448") (pin "2") (pinfunction "V_2") (pintype "bidirectional"))
      (node (ref "U$449") (pin "2") (pinfunction "V_2") (pintype "bidirectional"))
      (node (ref "U$450") (pin "2") (pinfunction "V_2") (pintype "bidirectional"))
      (node (ref "U$451") (pin "2") (pinfunction "V_2") (pintype "bidirectional"))
      (node (ref "U$452") (pin "2") (pinfunction "V_2") (pintype "bidirectional"))
      (node (ref "U$453") (pin "2") (pinfunction "V_2") (pintype "bidirectional"))
      (node (ref "U$454") (pin "2") (pinfunction "V_2") (pintype "bidirectional"))
    )
    (net (code "51") (name "Net-(Q31-D)") (class "Default")
      (node (ref "Q31") (pin "3") (pinfunction "D_3") (pintype "passive"))
      (node (ref "U$455") (pin "2") (pinfunction "V_2") (pintype "bidirectional"))
      (node (ref "U$456") (pin "2") (pinfunction "V_2") (pintype "bidirectional"))
      (node (ref "U$457") (pin "2") (pinfunction "V_2") (pintype "bidirectional"))
      (node (ref "U$458") (pin "2") (pinfunction "V_2") (pintype "bidirectional"))
      (node (ref "U$459") (pin "2") (pinfunction "V_2") (pintype "bidirectional"))
      (node (ref "U$460") (pin "2") (pinfunction "V_2") (pintype "bidirectional"))
      (node (ref "U$461") (pin "2") (pinfunction "V_2") (pintype "bidirectional"))
      (node (ref "U$462") (pin "2") (pinfunction "V_2") (pintype "bidirectional"))
      (node (ref "U$463") (pin "2") (pinfunction "V_2") (pintype "bidirectional"))
      (node (ref "U$464") (pin "2") (pinfunction "V_2") (pintype "bidirectional"))
      (node (ref "U$465") (pin "2") (pinfunction "V_2") (pintype "bidirectional"))
      (node (ref "U$466") (pin "2") (pinfunction "V_2") (pintype "bidirectional"))
      (node (ref "U$467") (pin "2") (pinfunction "V_2") (pintype "bidirectional"))
      (node (ref "U$468") (pin "2") (pinfunction "V_2") (pintype "bidirectional"))
      (node (ref "U$469") (pin "2") (pinfunction "V_2") (pintype "bidirectional"))
      (node (ref "U$470") (pin "2") (pinfunction "V_2") (pintype "bidirectional"))
      (node (ref "U$471") (pin "2") (pinfunction "V_2") (pintype "bidirectional"))
      (node (ref "U$472") (pin "2") (pinfunction "V_2") (pintype "bidirectional"))
      (node (ref "U$473") (pin "2") (pinfunction "V_2") (pintype "bidirectional"))
      (node (ref "U$474") (pin "2") (pinfunction "V_2") (pintype "bidirectional"))
      (node (ref "U$475") (pin "2") (pinfunction "V_2") (pintype "bidirectional"))
      (node (ref "U$476") (pin "2") (pinfunction "V_2") (pintype "bidirectional"))
      (node (ref "U$477") (pin "2") (pinfunction "V_2") (pintype "bidirectional"))
      (node (ref "U$478") (pin "2") (pinfunction "V_2") (pintype "bidirectional"))
      (node (ref "U$479") (pin "2") (pinfunction "V_2") (pintype "bidirectional"))
      (node (ref "U$480") (pin "2") (pinfunction "V_2") (pintype "bidirectional"))
      (node (ref "U$481") (pin "2") (pinfunction "V_2") (pintype "bidirectional"))
      (node (ref "U$482") (pin "2") (pinfunction "V_2") (pintype "bidirectional"))
      (node (ref "U$483") (pin "2") (pinfunction "V_2") (pintype "bidirectional"))
      (node (ref "U$484") (pin "2") (pinfunction "V_2") (pintype "bidirectional"))
      (node (ref "U$485") (pin "2") (pinfunction "V_2") (pintype "bidirectional"))
      (node (ref "U$486") (pin "2") (pinfunction "V_2") (pintype "bidirectional"))
    )
    (net (code "52") (name "Net-(Q32-D)") (class "Default")
      (node (ref "Q32") (pin "3") (pinfunction "D_3") (pintype "passive"))
      (node (ref "U$487") (pin "2") (pinfunction "V_2") (pintype "bidirectional"))
      (node (ref "U$488") (pin "2") (pinfunction "V_2") (pintype "bidirectional"))
      (node (ref "U$489") (pin "2") (pinfunction "V_2") (pintype "bidirectional"))
      (node (ref "U$490") (pin "2") (pinfunction "V_2") (pintype "bidirectional"))
      (node (ref "U$491") (pin "2") (pinfunction "V_2") (pintype "bidirectional"))
      (node (ref "U$492") (pin "2") (pinfunction "V_2") (pintype "bidirectional"))
      (node (ref "U$493") (pin "2") (pinfunction "V_2") (pintype "bidirectional"))
      (node (ref "U$494") (pin "2") (pinfunction "V_2") (pintype "bidirectional"))
      (node (ref "U$495") (pin "2") (pinfunction "V_2") (pintype "bidirectional"))
      (node (ref "U$496") (pin "2") (pinfunction "V_2") (pintype "bidirectional"))
      (node (ref "U$497") (pin "2") (pinfunction "V_2") (pintype "bidirectional"))
      (node (ref "U$498") (pin "2") (pinfunction "V_2") (pintype "bidirectional"))
      (node (ref "U$499") (pin "2") (pinfunction "V_2") (pintype "bidirectional"))
      (node (ref "U$500") (pin "2") (pinfunction "V_2") (pintype "bidirectional"))
      (node (ref "U$501") (pin "2") (pinfunction "V_2") (pintype "bidirectional"))
      (node (ref "U$502") (pin "2") (pinfunction "V_2") (pintype "bidirectional"))
      (node (ref "U$503") (pin "2") (pinfunction "V_2") (pintype "bidirectional"))
      (node (ref "U$504") (pin "2") (pinfunction "V_2") (pintype "bidirectional"))
      (node (ref "U$505") (pin "2") (pinfunction "V_2") (pintype "bidirectional"))
      (node (ref "U$506") (pin "2") (pinfunction "V_2") (pintype "bidirectional"))
      (node (ref "U$507") (pin "2") (pinfunction "V_2") (pintype "bidirectional"))
      (node (ref "U$508") (pin "2") (pinfunction "V_2") (pintype "bidirectional"))
      (node (ref "U$509") (pin "2") (pinfunction "V_2") (pintype "bidirectional"))
      (node (ref "U$510") (pin "2") (pinfunction "V_2") (pintype "bidirectional"))
      (node (ref "U$511") (pin "2") (pinfunction "V_2") (pintype "bidirectional"))
      (node (ref "U$512") (pin "2") (pinfunction "V_2") (pintype "bidirectional"))
      (node (ref "U$513") (pin "2") (pinfunction "V_2") (pintype "bidirectional"))
      (node (ref "U$514") (pin "2") (pinfunction "V_2") (pintype "bidirectional"))
      (node (ref "U$515") (pin "2") (pinfunction "V_2") (pintype "bidirectional"))
      (node (ref "U$516") (pin "2") (pinfunction "V_2") (pintype "bidirectional"))
      (node (ref "U$517") (pin "2") (pinfunction "V_2") (pintype "bidirectional"))
      (node (ref "U$518") (pin "2") (pinfunction "V_2") (pintype "bidirectional"))
    )
    (net (code "53") (name "Net-(U$1-IREF)") (class "Default")
      (node (ref "R6") (pin "1") (pinfunction "1_1") (pintype "passive"))
      (node (ref "U$1") (pin "20") (pinfunction "IREF_20") (pintype "bidirectional"))
    )
    (net (code "54") (name "Net-(U$1-OUT0)") (class "Default")
      (node (ref "U$1") (pin "28") (pinfunction "OUT0_28") (pintype "output"))
      (node (ref "U$103") (pin "1") (pinfunction "RED_1") (pintype "bidirectional"))
      (node (ref "U$135") (pin "1") (pinfunction "RED_1") (pintype "bidirectional"))
      (node (ref "U$167") (pin "1") (pinfunction "RED_1") (pintype "bidirectional"))
      (node (ref "U$199") (pin "1") (pinfunction "RED_1") (pintype "bidirectional"))
      (node (ref "U$231") (pin "1") (pinfunction "RED_1") (pintype "bidirectional"))
      (node (ref "U$263") (pin "1") (pinfunction "RED_1") (pintype "bidirectional"))
      (node (ref "U$295") (pin "1") (pinfunction "RED_1") (pintype "bidirectional"))
      (node (ref "U$327") (pin "1") (pinfunction "RED_1") (pintype "bidirectional"))
      (node (ref "U$359") (pin "1") (pinfunction "RED_1") (pintype "bidirectional"))
      (node (ref "U$39") (pin "1") (pinfunction "RED_1") (pintype "bidirectional"))
      (node (ref "U$391") (pin "1") (pinfunction "RED_1") (pintype "bidirectional"))
      (node (ref "U$423") (pin "1") (pinfunction "RED_1") (pintype "bidirectional"))
      (node (ref "U$455") (pin "1") (pinfunction "RED_1") (pintype "bidirectional"))
      (node (ref "U$487") (pin "1") (pinfunction "RED_1") (pintype "bidirectional"))
      (node (ref "U$7") (pin "1") (pinfunction "RED_1") (pintype "bidirectional"))
      (node (ref "U$71") (pin "1") (pinfunction "RED_1") (pintype "bidirectional"))
    )
    (net (code "55") (name "Net-(U$1-OUT1)") (class "Default")
      (node (ref "U$1") (pin "1") (pinfunction "OUT1_1") (pintype "output"))
      (node (ref "U$103") (pin "3") (pinfunction "GREEN_3") (pintype "bidirectional"))
      (node (ref "U$135") (pin "3") (pinfunction "GREEN_3") (pintype "bidirectional"))
      (node (ref "U$167") (pin "3") (pinfunction "GREEN_3") (pintype "bidirectional"))
      (node (ref "U$199") (pin "3") (pinfunction "GREEN_3") (pintype "bidirectional"))
      (node (ref "U$231") (pin "3") (pinfunction "GREEN_3") (pintype "bidirectional"))
      (node (ref "U$263") (pin "3") (pinfunction "GREEN_3") (pintype "bidirectional"))
      (node (ref "U$295") (pin "3") (pinfunction "GREEN_3") (pintype "bidirectional"))
      (node (ref "U$327") (pin "3") (pinfunction "GREEN_3") (pintype "bidirectional"))
      (node (ref "U$359") (pin "3") (pinfunction "GREEN_3") (pintype "bidirectional"))
      (node (ref "U$39") (pin "3") (pinfunction "GREEN_3") (pintype "bidirectional"))
      (node (ref "U$391") (pin "3") (pinfunction "GREEN_3") (pintype "bidirectional"))
      (node (ref "U$423") (pin "3") (pinfunction "GREEN_3") (pintype "bidirectional"))
      (node (ref "U$455") (pin "3") (pinfunction "GREEN_3") (pintype "bidirectional"))
      (node (ref "U$487") (pin "3") (pinfunction "GREEN_3") (pintype "bidirectional"))
      (node (ref "U$7") (pin "3") (pinfunction "GREEN_3") (pintype "bidirectional"))
      (node (ref "U$71") (pin "3") (pinfunction "GREEN_3") (pintype "bidirectional"))
    )
    (net (code "56") (name "Net-(U$1-OUT2)") (class "Default")
      (node (ref "U$1") (pin "2") (pinfunction "OUT2_2") (pintype "output"))
      (node (ref "U$103") (pin "4") (pinfunction "BLUE_4") (pintype "bidirectional"))
      (node (ref "U$135") (pin "4") (pinfunction "BLUE_4") (pintype "bidirectional"))
      (node (ref "U$167") (pin "4") (pinfunction "BLUE_4") (pintype "bidirectional"))
      (node (ref "U$199") (pin "4") (pinfunction "BLUE_4") (pintype "bidirectional"))
      (node (ref "U$231") (pin "4") (pinfunction "BLUE_4") (pintype "bidirectional"))
      (node (ref "U$263") (pin "4") (pinfunction "BLUE_4") (pintype "bidirectional"))
      (node (ref "U$295") (pin "4") (pinfunction "BLUE_4") (pintype "bidirectional"))
      (node (ref "U$327") (pin "4") (pinfunction "BLUE_4") (pintype "bidirectional"))
      (node (ref "U$359") (pin "4") (pinfunction "BLUE_4") (pintype "bidirectional"))
      (node (ref "U$39") (pin "4") (pinfunction "BLUE_4") (pintype "bidirectional"))
      (node (ref "U$391") (pin "4") (pinfunction "BLUE_4") (pintype "bidirectional"))
      (node (ref "U$423") (pin "4") (pinfunction "BLUE_4") (pintype "bidirectional"))
      (node (ref "U$455") (pin "4") (pinfunction "BLUE_4") (pintype "bidirectional"))
      (node (ref "U$487") (pin "4") (pinfunction "BLUE_4") (pintype "bidirectional"))
      (node (ref "U$7") (pin "4") (pinfunction "BLUE_4") (pintype "bidirectional"))
      (node (ref "U$71") (pin "4") (pinfunction "BLUE_4") (pintype "bidirectional"))
    )
    (net (code "57") (name "Net-(U$1-OUT3)") (class "Default")
      (node (ref "U$1") (pin "3") (pinfunction "OUT3_3") (pintype "output"))
      (node (ref "U$104") (pin "1") (pinfunction "RED_1") (pintype "bidirectional"))
      (node (ref "U$136") (pin "1") (pinfunction "RED_1") (pintype "bidirectional"))
      (node (ref "U$168") (pin "1") (pinfunction "RED_1") (pintype "bidirectional"))
      (node (ref "U$200") (pin "1") (pinfunction "RED_1") (pintype "bidirectional"))
      (node (ref "U$232") (pin "1") (pinfunction "RED_1") (pintype "bidirectional"))
      (node (ref "U$264") (pin "1") (pinfunction "RED_1") (pintype "bidirectional"))
      (node (ref "U$296") (pin "1") (pinfunction "RED_1") (pintype "bidirectional"))
      (node (ref "U$328") (pin "1") (pinfunction "RED_1") (pintype "bidirectional"))
      (node (ref "U$360") (pin "1") (pinfunction "RED_1") (pintype "bidirectional"))
      (node (ref "U$392") (pin "1") (pinfunction "RED_1") (pintype "bidirectional"))
      (node (ref "U$40") (pin "1") (pinfunction "RED_1") (pintype "bidirectional"))
      (node (ref "U$424") (pin "1") (pinfunction "RED_1") (pintype "bidirectional"))
      (node (ref "U$456") (pin "1") (pinfunction "RED_1") (pintype "bidirectional"))
      (node (ref "U$488") (pin "1") (pinfunction "RED_1") (pintype "bidirectional"))
      (node (ref "U$72") (pin "1") (pinfunction "RED_1") (pintype "bidirectional"))
      (node (ref "U$8") (pin "1") (pinfunction "RED_1") (pintype "bidirectional"))
    )
    (net (code "58") (name "Net-(U$1-OUT4)") (class "Default")
      (node (ref "U$1") (pin "4") (pinfunction "OUT4_4") (pintype "output"))
      (node (ref "U$104") (pin "3") (pinfunction "GREEN_3") (pintype "bidirectional"))
      (node (ref "U$136") (pin "3") (pinfunction "GREEN_3") (pintype "bidirectional"))
      (node (ref "U$168") (pin "3") (pinfunction "GREEN_3") (pintype "bidirectional"))
      (node (ref "U$200") (pin "3") (pinfunction "GREEN_3") (pintype "bidirectional"))
      (node (ref "U$232") (pin "3") (pinfunction "GREEN_3") (pintype "bidirectional"))
      (node (ref "U$264") (pin "3") (pinfunction "GREEN_3") (pintype "bidirectional"))
      (node (ref "U$296") (pin "3") (pinfunction "GREEN_3") (pintype "bidirectional"))
      (node (ref "U$328") (pin "3") (pinfunction "GREEN_3") (pintype "bidirectional"))
      (node (ref "U$360") (pin "3") (pinfunction "GREEN_3") (pintype "bidirectional"))
      (node (ref "U$392") (pin "3") (pinfunction "GREEN_3") (pintype "bidirectional"))
      (node (ref "U$40") (pin "3") (pinfunction "GREEN_3") (pintype "bidirectional"))
      (node (ref "U$424") (pin "3") (pinfunction "GREEN_3") (pintype "bidirectional"))
      (node (ref "U$456") (pin "3") (pinfunction "GREEN_3") (pintype "bidirectional"))
      (node (ref "U$488") (pin "3") (pinfunction "GREEN_3") (pintype "bidirectional"))
      (node (ref "U$72") (pin "3") (pinfunction "GREEN_3") (pintype "bidirectional"))
      (node (ref "U$8") (pin "3") (pinfunction "GREEN_3") (pintype "bidirectional"))
    )
    (net (code "59") (name "Net-(U$1-OUT5)") (class "Default")
      (node (ref "U$1") (pin "5") (pinfunction "OUT5_5") (pintype "output"))
      (node (ref "U$104") (pin "4") (pinfunction "BLUE_4") (pintype "bidirectional"))
      (node (ref "U$136") (pin "4") (pinfunction "BLUE_4") (pintype "bidirectional"))
      (node (ref "U$168") (pin "4") (pinfunction "BLUE_4") (pintype "bidirectional"))
      (node (ref "U$200") (pin "4") (pinfunction "BLUE_4") (pintype "bidirectional"))
      (node (ref "U$232") (pin "4") (pinfunction "BLUE_4") (pintype "bidirectional"))
      (node (ref "U$264") (pin "4") (pinfunction "BLUE_4") (pintype "bidirectional"))
      (node (ref "U$296") (pin "4") (pinfunction "BLUE_4") (pintype "bidirectional"))
      (node (ref "U$328") (pin "4") (pinfunction "BLUE_4") (pintype "bidirectional"))
      (node (ref "U$360") (pin "4") (pinfunction "BLUE_4") (pintype "bidirectional"))
      (node (ref "U$392") (pin "4") (pinfunction "BLUE_4") (pintype "bidirectional"))
      (node (ref "U$40") (pin "4") (pinfunction "BLUE_4") (pintype "bidirectional"))
      (node (ref "U$424") (pin "4") (pinfunction "BLUE_4") (pintype "bidirectional"))
      (node (ref "U$456") (pin "4") (pinfunction "BLUE_4") (pintype "bidirectional"))
      (node (ref "U$488") (pin "4") (pinfunction "BLUE_4") (pintype "bidirectional"))
      (node (ref "U$72") (pin "4") (pinfunction "BLUE_4") (pintype "bidirectional"))
      (node (ref "U$8") (pin "4") (pinfunction "BLUE_4") (pintype "bidirectional"))
    )
    (net (code "60") (name "Net-(U$1-OUT6)") (class "Default")
      (node (ref "U$1") (pin "6") (pinfunction "OUT6_6") (pintype "output"))
      (node (ref "U$105") (pin "1") (pinfunction "RED_1") (pintype "bidirectional"))
      (node (ref "U$137") (pin "1") (pinfunction "RED_1") (pintype "bidirectional"))
      (node (ref "U$169") (pin "1") (pinfunction "RED_1") (pintype "bidirectional"))
      (node (ref "U$201") (pin "1") (pinfunction "RED_1") (pintype "bidirectional"))
      (node (ref "U$233") (pin "1") (pinfunction "RED_1") (pintype "bidirectional"))
      (node (ref "U$265") (pin "1") (pinfunction "RED_1") (pintype "bidirectional"))
      (node (ref "U$297") (pin "1") (pinfunction "RED_1") (pintype "bidirectional"))
      (node (ref "U$329") (pin "1") (pinfunction "RED_1") (pintype "bidirectional"))
      (node (ref "U$361") (pin "1") (pinfunction "RED_1") (pintype "bidirectional"))
      (node (ref "U$393") (pin "1") (pinfunction "RED_1") (pintype "bidirectional"))
      (node (ref "U$41") (pin "1") (pinfunction "RED_1") (pintype "bidirectional"))
      (node (ref "U$425") (pin "1") (pinfunction "RED_1") (pintype "bidirectional"))
      (node (ref "U$457") (pin "1") (pinfunction "RED_1") (pintype "bidirectional"))
      (node (ref "U$489") (pin "1") (pinfunction "RED_1") (pintype "bidirectional"))
      (node (ref "U$73") (pin "1") (pinfunction "RED_1") (pintype "bidirectional"))
      (node (ref "U$9") (pin "1") (pinfunction "RED_1") (pintype "bidirectional"))
    )
    (net (code "61") (name "Net-(U$1-OUT7)") (class "Default")
      (node (ref "U$1") (pin "7") (pinfunction "OUT7_7") (pintype "output"))
      (node (ref "U$105") (pin "3") (pinfunction "GREEN_3") (pintype "bidirectional"))
      (node (ref "U$137") (pin "3") (pinfunction "GREEN_3") (pintype "bidirectional"))
      (node (ref "U$169") (pin "3") (pinfunction "GREEN_3") (pintype "bidirectional"))
      (node (ref "U$201") (pin "3") (pinfunction "GREEN_3") (pintype "bidirectional"))
      (node (ref "U$233") (pin "3") (pinfunction "GREEN_3") (pintype "bidirectional"))
      (node (ref "U$265") (pin "3") (pinfunction "GREEN_3") (pintype "bidirectional"))
      (node (ref "U$297") (pin "3") (pinfunction "GREEN_3") (pintype "bidirectional"))
      (node (ref "U$329") (pin "3") (pinfunction "GREEN_3") (pintype "bidirectional"))
      (node (ref "U$361") (pin "3") (pinfunction "GREEN_3") (pintype "bidirectional"))
      (node (ref "U$393") (pin "3") (pinfunction "GREEN_3") (pintype "bidirectional"))
      (node (ref "U$41") (pin "3") (pinfunction "GREEN_3") (pintype "bidirectional"))
      (node (ref "U$425") (pin "3") (pinfunction "GREEN_3") (pintype "bidirectional"))
      (node (ref "U$457") (pin "3") (pinfunction "GREEN_3") (pintype "bidirectional"))
      (node (ref "U$489") (pin "3") (pinfunction "GREEN_3") (pintype "bidirectional"))
      (node (ref "U$73") (pin "3") (pinfunction "GREEN_3") (pintype "bidirectional"))
      (node (ref "U$9") (pin "3") (pinfunction "GREEN_3") (pintype "bidirectional"))
    )
    (net (code "62") (name "Net-(U$1-OUT8)") (class "Default")
      (node (ref "U$1") (pin "8") (pinfunction "OUT8_8") (pintype "output"))
      (node (ref "U$105") (pin "4") (pinfunction "BLUE_4") (pintype "bidirectional"))
      (node (ref "U$137") (pin "4") (pinfunction "BLUE_4") (pintype "bidirectional"))
      (node (ref "U$169") (pin "4") (pinfunction "BLUE_4") (pintype "bidirectional"))
      (node (ref "U$201") (pin "4") (pinfunction "BLUE_4") (pintype "bidirectional"))
      (node (ref "U$233") (pin "4") (pinfunction "BLUE_4") (pintype "bidirectional"))
      (node (ref "U$265") (pin "4") (pinfunction "BLUE_4") (pintype "bidirectional"))
      (node (ref "U$297") (pin "4") (pinfunction "BLUE_4") (pintype "bidirectional"))
      (node (ref "U$329") (pin "4") (pinfunction "BLUE_4") (pintype "bidirectional"))
      (node (ref "U$361") (pin "4") (pinfunction "BLUE_4") (pintype "bidirectional"))
      (node (ref "U$393") (pin "4") (pinfunction "BLUE_4") (pintype "bidirectional"))
      (node (ref "U$41") (pin "4") (pinfunction "BLUE_4") (pintype "bidirectional"))
      (node (ref "U$425") (pin "4") (pinfunction "BLUE_4") (pintype "bidirectional"))
      (node (ref "U$457") (pin "4") (pinfunction "BLUE_4") (pintype "bidirectional"))
      (node (ref "U$489") (pin "4") (pinfunction "BLUE_4") (pintype "bidirectional"))
      (node (ref "U$73") (pin "4") (pinfunction "BLUE_4") (pintype "bidirectional"))
      (node (ref "U$9") (pin "4") (pinfunction "BLUE_4") (pintype "bidirectional"))
    )
    (net (code "63") (name "Net-(U$1-OUT9)") (class "Default")
      (node (ref "U$1") (pin "9") (pinfunction "OUT9_9") (pintype "output"))
      (node (ref "U$10") (pin "1") (pinfunction "RED_1") (pintype "bidirectional"))
      (node (ref "U$106") (pin "1") (pinfunction "RED_1") (pintype "bidirectional"))
      (node (ref "U$138") (pin "1") (pinfunction "RED_1") (pintype "bidirectional"))
      (node (ref "U$170") (pin "1") (pinfunction "RED_1") (pintype "bidirectional"))
      (node (ref "U$202") (pin "1") (pinfunction "RED_1") (pintype "bidirectional"))
      (node (ref "U$234") (pin "1") (pinfunction "RED_1") (pintype "bidirectional"))
      (node (ref "U$266") (pin "1") (pinfunction "RED_1") (pintype "bidirectional"))
      (node (ref "U$298") (pin "1") (pinfunction "RED_1") (pintype "bidirectional"))
      (node (ref "U$330") (pin "1") (pinfunction "RED_1") (pintype "bidirectional"))
      (node (ref "U$362") (pin "1") (pinfunction "RED_1") (pintype "bidirectional"))
      (node (ref "U$394") (pin "1") (pinfunction "RED_1") (pintype "bidirectional"))
      (node (ref "U$42") (pin "1") (pinfunction "RED_1") (pintype "bidirectional"))
      (node (ref "U$426") (pin "1") (pinfunction "RED_1") (pintype "bidirectional"))
      (node (ref "U$458") (pin "1") (pinfunction "RED_1") (pintype "bidirectional"))
      (node (ref "U$490") (pin "1") (pinfunction "RED_1") (pintype "bidirectional"))
      (node (ref "U$74") (pin "1") (pinfunction "RED_1") (pintype "bidirectional"))
    )
    (net (code "64") (name "Net-(U$1-OUT10)") (class "Default")
      (node (ref "U$1") (pin "10") (pinfunction "OUT10_10") (pintype "output"))
      (node (ref "U$10") (pin "3") (pinfunction "GREEN_3") (pintype "bidirectional"))
      (node (ref "U$106") (pin "3") (pinfunction "GREEN_3") (pintype "bidirectional"))
      (node (ref "U$138") (pin "3") (pinfunction "GREEN_3") (pintype "bidirectional"))
      (node (ref "U$170") (pin "3") (pinfunction "GREEN_3") (pintype "bidirectional"))
      (node (ref "U$202") (pin "3") (pinfunction "GREEN_3") (pintype "bidirectional"))
      (node (ref "U$234") (pin "3") (pinfunction "GREEN_3") (pintype "bidirectional"))
      (node (ref "U$266") (pin "3") (pinfunction "GREEN_3") (pintype "bidirectional"))
      (node (ref "U$298") (pin "3") (pinfunction "GREEN_3") (pintype "bidirectional"))
      (node (ref "U$330") (pin "3") (pinfunction "GREEN_3") (pintype "bidirectional"))
      (node (ref "U$362") (pin "3") (pinfunction "GREEN_3") (pintype "bidirectional"))
      (node (ref "U$394") (pin "3") (pinfunction "GREEN_3") (pintype "bidirectional"))
      (node (ref "U$42") (pin "3") (pinfunction "GREEN_3") (pintype "bidirectional"))
      (node (ref "U$426") (pin "3") (pinfunction "GREEN_3") (pintype "bidirectional"))
      (node (ref "U$458") (pin "3") (pinfunction "GREEN_3") (pintype "bidirectional"))
      (node (ref "U$490") (pin "3") (pinfunction "GREEN_3") (pintype "bidirectional"))
      (node (ref "U$74") (pin "3") (pinfunction "GREEN_3") (pintype "bidirectional"))
    )
    (net (code "65") (name "Net-(U$1-OUT11)") (class "Default")
      (node (ref "U$1") (pin "11") (pinfunction "OUT11_11") (pintype "output"))
      (node (ref "U$10") (pin "4") (pinfunction "BLUE_4") (pintype "bidirectional"))
      (node (ref "U$106") (pin "4") (pinfunction "BLUE_4") (pintype "bidirectional"))
      (node (ref "U$138") (pin "4") (pinfunction "BLUE_4") (pintype "bidirectional"))
      (node (ref "U$170") (pin "4") (pinfunction "BLUE_4") (pintype "bidirectional"))
      (node (ref "U$202") (pin "4") (pinfunction "BLUE_4") (pintype "bidirectional"))
      (node (ref "U$234") (pin "4") (pinfunction "BLUE_4") (pintype "bidirectional"))
      (node (ref "U$266") (pin "4") (pinfunction "BLUE_4") (pintype "bidirectional"))
      (node (ref "U$298") (pin "4") (pinfunction "BLUE_4") (pintype "bidirectional"))
      (node (ref "U$330") (pin "4") (pinfunction "BLUE_4") (pintype "bidirectional"))
      (node (ref "U$362") (pin "4") (pinfunction "BLUE_4") (pintype "bidirectional"))
      (node (ref "U$394") (pin "4") (pinfunction "BLUE_4") (pintype "bidirectional"))
      (node (ref "U$42") (pin "4") (pinfunction "BLUE_4") (pintype "bidirectional"))
      (node (ref "U$426") (pin "4") (pinfunction "BLUE_4") (pintype "bidirectional"))
      (node (ref "U$458") (pin "4") (pinfunction "BLUE_4") (pintype "bidirectional"))
      (node (ref "U$490") (pin "4") (pinfunction "BLUE_4") (pintype "bidirectional"))
      (node (ref "U$74") (pin "4") (pinfunction "BLUE_4") (pintype "bidirectional"))
    )
    (net (code "66") (name "Net-(U$1-OUT12)") (class "Default")
      (node (ref "U$1") (pin "12") (pinfunction "OUT12_12") (pintype "output"))
      (node (ref "U$107") (pin "1") (pinfunction "RED_1") (pintype "bidirectional"))
      (node (ref "U$11") (pin "1") (pinfunction "RED_1") (pintype "bidirectional"))
      (node (ref "U$139") (pin "1") (pinfunction "RED_1") (pintype "bidirectional"))
      (node (ref "U$171") (pin "1") (pinfunction "RED_1") (pintype "bidirectional"))
      (node (ref "U$203") (pin "1") (pinfunction "RED_1") (pintype "bidirectional"))
      (node (ref "U$235") (pin "1") (pinfunction "RED_1") (pintype "bidirectional"))
      (node (ref "U$267") (pin "1") (pinfunction "RED_1") (pintype "bidirectional"))
      (node (ref "U$299") (pin "1") (pinfunction "RED_1") (pintype "bidirectional"))
      (node (ref "U$331") (pin "1") (pinfunction "RED_1") (pintype "bidirectional"))
      (node (ref "U$363") (pin "1") (pinfunction "RED_1") (pintype "bidirectional"))
      (node (ref "U$395") (pin "1") (pinfunction "RED_1") (pintype "bidirectional"))
      (node (ref "U$427") (pin "1") (pinfunction "RED_1") (pintype "bidirectional"))
      (node (ref "U$43") (pin "1") (pinfunction "RED_1") (pintype "bidirectional"))
      (node (ref "U$459") (pin "1") (pinfunction "RED_1") (pintype "bidirectional"))
      (node (ref "U$491") (pin "1") (pinfunction "RED_1") (pintype "bidirectional"))
      (node (ref "U$75") (pin "1") (pinfunction "RED_1") (pintype "bidirectional"))
    )
    (net (code "67") (name "Net-(U$1-OUT13)") (class "Default")
      (node (ref "U$1") (pin "13") (pinfunction "OUT13_13") (pintype "output"))
      (node (ref "U$107") (pin "3") (pinfunction "GREEN_3") (pintype "bidirectional"))
      (node (ref "U$11") (pin "3") (pinfunction "GREEN_3") (pintype "bidirectional"))
      (node (ref "U$139") (pin "3") (pinfunction "GREEN_3") (pintype "bidirectional"))
      (node (ref "U$171") (pin "3") (pinfunction "GREEN_3") (pintype "bidirectional"))
      (node (ref "U$203") (pin "3") (pinfunction "GREEN_3") (pintype "bidirectional"))
      (node (ref "U$235") (pin "3") (pinfunction "GREEN_3") (pintype "bidirectional"))
      (node (ref "U$267") (pin "3") (pinfunction "GREEN_3") (pintype "bidirectional"))
      (node (ref "U$299") (pin "3") (pinfunction "GREEN_3") (pintype "bidirectional"))
      (node (ref "U$331") (pin "3") (pinfunction "GREEN_3") (pintype "bidirectional"))
      (node (ref "U$363") (pin "3") (pinfunction "GREEN_3") (pintype "bidirectional"))
      (node (ref "U$395") (pin "3") (pinfunction "GREEN_3") (pintype "bidirectional"))
      (node (ref "U$427") (pin "3") (pinfunction "GREEN_3") (pintype "bidirectional"))
      (node (ref "U$43") (pin "3") (pinfunction "GREEN_3") (pintype "bidirectional"))
      (node (ref "U$459") (pin "3") (pinfunction "GREEN_3") (pintype "bidirectional"))
      (node (ref "U$491") (pin "3") (pinfunction "GREEN_3") (pintype "bidirectional"))
      (node (ref "U$75") (pin "3") (pinfunction "GREEN_3") (pintype "bidirectional"))
    )
    (net (code "68") (name "Net-(U$1-OUT14)") (class "Default")
      (node (ref "U$1") (pin "14") (pinfunction "OUT14_14") (pintype "output"))
      (node (ref "U$107") (pin "4") (pinfunction "BLUE_4") (pintype "bidirectional"))
      (node (ref "U$11") (pin "4") (pinfunction "BLUE_4") (pintype "bidirectional"))
      (node (ref "U$139") (pin "4") (pinfunction "BLUE_4") (pintype "bidirectional"))
      (node (ref "U$171") (pin "4") (pinfunction "BLUE_4") (pintype "bidirectional"))
      (node (ref "U$203") (pin "4") (pinfunction "BLUE_4") (pintype "bidirectional"))
      (node (ref "U$235") (pin "4") (pinfunction "BLUE_4") (pintype "bidirectional"))
      (node (ref "U$267") (pin "4") (pinfunction "BLUE_4") (pintype "bidirectional"))
      (node (ref "U$299") (pin "4") (pinfunction "BLUE_4") (pintype "bidirectional"))
      (node (ref "U$331") (pin "4") (pinfunction "BLUE_4") (pintype "bidirectional"))
      (node (ref "U$363") (pin "4") (pinfunction "BLUE_4") (pintype "bidirectional"))
      (node (ref "U$395") (pin "4") (pinfunction "BLUE_4") (pintype "bidirectional"))
      (node (ref "U$427") (pin "4") (pinfunction "BLUE_4") (pintype "bidirectional"))
      (node (ref "U$43") (pin "4") (pinfunction "BLUE_4") (pintype "bidirectional"))
      (node (ref "U$459") (pin "4") (pinfunction "BLUE_4") (pintype "bidirectional"))
      (node (ref "U$491") (pin "4") (pinfunction "BLUE_4") (pintype "bidirectional"))
      (node (ref "U$75") (pin "4") (pinfunction "BLUE_4") (pintype "bidirectional"))
    )
    (net (code "69") (name "Net-(U$1-OUT15)") (class "Default")
      (node (ref "U$1") (pin "15") (pinfunction "OUT15_15") (pintype "output"))
      (node (ref "U$108") (pin "1") (pinfunction "RED_1") (pintype "bidirectional"))
      (node (ref "U$12") (pin "1") (pinfunction "RED_1") (pintype "bidirectional"))
      (node (ref "U$140") (pin "1") (pinfunction "RED_1") (pintype "bidirectional"))
      (node (ref "U$172") (pin "1") (pinfunction "RED_1") (pintype "bidirectional"))
      (node (ref "U$204") (pin "1") (pinfunction "RED_1") (pintype "bidirectional"))
      (node (ref "U$236") (pin "1") (pinfunction "RED_1") (pintype "bidirectional"))
      (node (ref "U$268") (pin "1") (pinfunction "RED_1") (pintype "bidirectional"))
      (node (ref "U$300") (pin "1") (pinfunction "RED_1") (pintype "bidirectional"))
      (node (ref "U$332") (pin "1") (pinfunction "RED_1") (pintype "bidirectional"))
      (node (ref "U$364") (pin "1") (pinfunction "RED_1") (pintype "bidirectional"))
      (node (ref "U$396") (pin "1") (pinfunction "RED_1") (pintype "bidirectional"))
      (node (ref "U$428") (pin "1") (pinfunction "RED_1") (pintype "bidirectional"))
      (node (ref "U$44") (pin "1") (pinfunction "RED_1") (pintype "bidirectional"))
      (node (ref "U$460") (pin "1") (pinfunction "RED_1") (pintype "bidirectional"))
      (node (ref "U$492") (pin "1") (pinfunction "RED_1") (pintype "bidirectional"))
      (node (ref "U$76") (pin "1") (pinfunction "RED_1") (pintype "bidirectional"))
    )
    (net (code "70") (name "Net-(U$2-IREF)") (class "Default")
      (node (ref "R1") (pin "1") (pinfunction "1_1") (pintype "passive"))
      (node (ref "U$2") (pin "20") (pinfunction "IREF_20") (pintype "bidirectional"))
    )
    (net (code "71") (name "Net-(U$3-IREF)") (class "Default")
      (node (ref "R2") (pin "1") (pinfunction "1_1") (pintype "passive"))
      (node (ref "U$3") (pin "20") (pinfunction "IREF_20") (pintype "bidirectional"))
    )
    (net (code "72") (name "Net-(U$4-IREF)") (class "Default")
      (node (ref "R3") (pin "1") (pinfunction "1_1") (pintype "passive"))
      (node (ref "U$4") (pin "20") (pinfunction "IREF_20") (pintype "bidirectional"))
    )
    (net (code "73") (name "Net-(U$5-IREF)") (class "Default")
      (node (ref "R4") (pin "1") (pinfunction "1_1") (pintype "passive"))
      (node (ref "U$5") (pin "20") (pinfunction "IREF_20") (pintype "bidirectional"))
    )
    (net (code "74") (name "Net-(U$6-IREF)") (class "Default")
      (node (ref "R5") (pin "1") (pinfunction "1_1") (pintype "passive"))
      (node (ref "U$6") (pin "20") (pinfunction "IREF_20") (pintype "bidirectional"))
    )
    (net (code "75") (name "Net-(U$100-BLUE)") (class "Default")
      (node (ref "U$100") (pin "4") (pinfunction "BLUE_4") (pintype "bidirectional"))
      (node (ref "U$132") (pin "4") (pinfunction "BLUE_4") (pintype "bidirectional"))
      (node (ref "U$164") (pin "4") (pinfunction "BLUE_4") (pintype "bidirectional"))
      (node (ref "U$196") (pin "4") (pinfunction "BLUE_4") (pintype "bidirectional"))
      (node (ref "U$228") (pin "4") (pinfunction "BLUE_4") (pintype "bidirectional"))
      (node (ref "U$260") (pin "4") (pinfunction "BLUE_4") (pintype "bidirectional"))
      (node (ref "U$292") (pin "4") (pinfunction "BLUE_4") (pintype "bidirectional"))
      (node (ref "U$324") (pin "4") (pinfunction "BLUE_4") (pintype "bidirectional"))
      (node (ref "U$356") (pin "4") (pinfunction "BLUE_4") (pintype "bidirectional"))
      (node (ref "U$36") (pin "4") (pinfunction "BLUE_4") (pintype "bidirectional"))
      (node (ref "U$388") (pin "4") (pinfunction "BLUE_4") (pintype "bidirectional"))
      (node (ref "U$420") (pin "4") (pinfunction "BLUE_4") (pintype "bidirectional"))
      (node (ref "U$452") (pin "4") (pinfunction "BLUE_4") (pintype "bidirectional"))
      (node (ref "U$484") (pin "4") (pinfunction "BLUE_4") (pintype "bidirectional"))
      (node (ref "U$516") (pin "4") (pinfunction "BLUE_4") (pintype "bidirectional"))
      (node (ref "U$6") (pin "9") (pinfunction "OUT9_9") (pintype "output"))
      (node (ref "U$68") (pin "4") (pinfunction "BLUE_4") (pintype "bidirectional"))
    )
    (net (code "76") (name "Net-(U$100-GREEN)") (class "Default")
      (node (ref "U$100") (pin "3") (pinfunction "GREEN_3") (pintype "bidirectional"))
      (node (ref "U$132") (pin "3") (pinfunction "GREEN_3") (pintype "bidirectional"))
      (node (ref "U$164") (pin "3") (pinfunction "GREEN_3") (pintype "bidirectional"))
      (node (ref "U$196") (pin "3") (pinfunction "GREEN_3") (pintype "bidirectional"))
      (node (ref "U$228") (pin "3") (pinfunction "GREEN_3") (pintype "bidirectional"))
      (node (ref "U$260") (pin "3") (pinfunction "GREEN_3") (pintype "bidirectional"))
      (node (ref "U$292") (pin "3") (pinfunction "GREEN_3") (pintype "bidirectional"))
      (node (ref "U$324") (pin "3") (pinfunction "GREEN_3") (pintype "bidirectional"))
      (node (ref "U$356") (pin "3") (pinfunction "GREEN_3") (pintype "bidirectional"))
      (node (ref "U$36") (pin "3") (pinfunction "GREEN_3") (pintype "bidirectional"))
      (node (ref "U$388") (pin "3") (pinfunction "GREEN_3") (pintype "bidirectional"))
      (node (ref "U$420") (pin "3") (pinfunction "GREEN_3") (pintype "bidirectional"))
      (node (ref "U$452") (pin "3") (pinfunction "GREEN_3") (pintype "bidirectional"))
      (node (ref "U$484") (pin "3") (pinfunction "GREEN_3") (pintype "bidirectional"))
      (node (ref "U$516") (pin "3") (pinfunction "GREEN_3") (pintype "bidirectional"))
      (node (ref "U$6") (pin "8") (pinfunction "OUT8_8") (pintype "output"))
      (node (ref "U$68") (pin "3") (pinfunction "GREEN_3") (pintype "bidirectional"))
    )
    (net (code "77") (name "Net-(U$100-RED)") (class "Default")
      (node (ref "U$100") (pin "1") (pinfunction "RED_1") (pintype "bidirectional"))
      (node (ref "U$132") (pin "1") (pinfunction "RED_1") (pintype "bidirectional"))
      (node (ref "U$164") (pin "1") (pinfunction "RED_1") (pintype "bidirectional"))
      (node (ref "U$196") (pin "1") (pinfunction "RED_1") (pintype "bidirectional"))
      (node (ref "U$228") (pin "1") (pinfunction "RED_1") (pintype "bidirectional"))
      (node (ref "U$260") (pin "1") (pinfunction "RED_1") (pintype "bidirectional"))
      (node (ref "U$292") (pin "1") (pinfunction "RED_1") (pintype "bidirectional"))
      (node (ref "U$324") (pin "1") (pinfunction "RED_1") (pintype "bidirectional"))
      (node (ref "U$356") (pin "1") (pinfunction "RED_1") (pintype "bidirectional"))
      (node (ref "U$36") (pin "1") (pinfunction "RED_1") (pintype "bidirectional"))
      (node (ref "U$388") (pin "1") (pinfunction "RED_1") (pintype "bidirectional"))
      (node (ref "U$420") (pin "1") (pinfunction "RED_1") (pintype "bidirectional"))
      (node (ref "U$452") (pin "1") (pinfunction "RED_1") (pintype "bidirectional"))
      (node (ref "U$484") (pin "1") (pinfunction "RED_1") (pintype "bidirectional"))
      (node (ref "U$516") (pin "1") (pinfunction "RED_1") (pintype "bidirectional"))
      (node (ref "U$6") (pin "7") (pinfunction "OUT7_7") (pintype "output"))
      (node (ref "U$68") (pin "1") (pinfunction "RED_1") (pintype "bidirectional"))
    )
    (net (code "78") (name "Net-(U$101-BLUE)") (class "Default")
      (node (ref "U$101") (pin "4") (pinfunction "BLUE_4") (pintype "bidirectional"))
      (node (ref "U$133") (pin "4") (pinfunction "BLUE_4") (pintype "bidirectional"))
      (node (ref "U$165") (pin "4") (pinfunction "BLUE_4") (pintype "bidirectional"))
      (node (ref "U$197") (pin "4") (pinfunction "BLUE_4") (pintype "bidirectional"))
      (node (ref "U$229") (pin "4") (pinfunction "BLUE_4") (pintype "bidirectional"))
      (node (ref "U$261") (pin "4") (pinfunction "BLUE_4") (pintype "bidirectional"))
      (node (ref "U$293") (pin "4") (pinfunction "BLUE_4") (pintype "bidirectional"))
      (node (ref "U$325") (pin "4") (pinfunction "BLUE_4") (pintype "bidirectional"))
      (node (ref "U$357") (pin "4") (pinfunction "BLUE_4") (pintype "bidirectional"))
      (node (ref "U$37") (pin "4") (pinfunction "BLUE_4") (pintype "bidirectional"))
      (node (ref "U$389") (pin "4") (pinfunction "BLUE_4") (pintype "bidirectional"))
      (node (ref "U$421") (pin "4") (pinfunction "BLUE_4") (pintype "bidirectional"))
      (node (ref "U$453") (pin "4") (pinfunction "BLUE_4") (pintype "bidirectional"))
      (node (ref "U$485") (pin "4") (pinfunction "BLUE_4") (pintype "bidirectional"))
      (node (ref "U$517") (pin "4") (pinfunction "BLUE_4") (pintype "bidirectional"))
      (node (ref "U$6") (pin "12") (pinfunction "OUT12_12") (pintype "output"))
      (node (ref "U$69") (pin "4") (pinfunction "BLUE_4") (pintype "bidirectional"))
    )
    (net (code "79") (name "Net-(U$101-GREEN)") (class "Default")
      (node (ref "U$101") (pin "3") (pinfunction "GREEN_3") (pintype "bidirectional"))
      (node (ref "U$133") (pin "3") (pinfunction "GREEN_3") (pintype "bidirectional"))
      (node (ref "U$165") (pin "3") (pinfunction "GREEN_3") (pintype "bidirectional"))
      (node (ref "U$197") (pin "3") (pinfunction "GREEN_3") (pintype "bidirectional"))
      (node (ref "U$229") (pin "3") (pinfunction "GREEN_3") (pintype "bidirectional"))
      (node (ref "U$261") (pin "3") (pinfunction "GREEN_3") (pintype "bidirectional"))
      (node (ref "U$293") (pin "3") (pinfunction "GREEN_3") (pintype "bidirectional"))
      (node (ref "U$325") (pin "3") (pinfunction "GREEN_3") (pintype "bidirectional"))
      (node (ref "U$357") (pin "3") (pinfunction "GREEN_3") (pintype "bidirectional"))
      (node (ref "U$37") (pin "3") (pinfunction "GREEN_3") (pintype "bidirectional"))
      (node (ref "U$389") (pin "3") (pinfunction "GREEN_3") (pintype "bidirectional"))
      (node (ref "U$421") (pin "3") (pinfunction "GREEN_3") (pintype "bidirectional"))
      (node (ref "U$453") (pin "3") (pinfunction "GREEN_3") (pintype "bidirectional"))
      (node (ref "U$485") (pin "3") (pinfunction "GREEN_3") (pintype "bidirectional"))
      (node (ref "U$517") (pin "3") (pinfunction "GREEN_3") (pintype "bidirectional"))
      (node (ref "U$6") (pin "11") (pinfunction "OUT11_11") (pintype "output"))
      (node (ref "U$69") (pin "3") (pinfunction "GREEN_3") (pintype "bidirectional"))
    )
    (net (code "80") (name "Net-(U$101-RED)") (class "Default")
      (node (ref "U$101") (pin "1") (pinfunction "RED_1") (pintype "bidirectional"))
      (node (ref "U$133") (pin "1") (pinfunction "RED_1") (pintype "bidirectional"))
      (node (ref "U$165") (pin "1") (pinfunction "RED_1") (pintype "bidirectional"))
      (node (ref "U$197") (pin "1") (pinfunction "RED_1") (pintype "bidirectional"))
      (node (ref "U$229") (pin "1") (pinfunction "RED_1") (pintype "bidirectional"))
      (node (ref "U$261") (pin "1") (pinfunction "RED_1") (pintype "bidirectional"))
      (node (ref "U$293") (pin "1") (pinfunction "RED_1") (pintype "bidirectional"))
      (node (ref "U$325") (pin "1") (pinfunction "RED_1") (pintype "bidirectional"))
      (node (ref "U$357") (pin "1") (pinfunction "RED_1") (pintype "bidirectional"))
      (node (ref "U$37") (pin "1") (pinfunction "RED_1") (pintype "bidirectional"))
      (node (ref "U$389") (pin "1") (pinfunction "RED_1") (pintype "bidirectional"))
      (node (ref "U$421") (pin "1") (pinfunction "RED_1") (pintype "bidirectional"))
      (node (ref "U$453") (pin "1") (pinfunction "RED_1") (pintype "bidirectional"))
      (node (ref "U$485") (pin "1") (pinfunction "RED_1") (pintype "bidirectional"))
      (node (ref "U$517") (pin "1") (pinfunction "RED_1") (pintype "bidirectional"))
      (node (ref "U$6") (pin "10") (pinfunction "OUT10_10") (pintype "output"))
      (node (ref "U$69") (pin "1") (pinfunction "RED_1") (pintype "bidirectional"))
    )
    (net (code "81") (name "Net-(U$102-BLUE)") (class "Default")
      (node (ref "U$102") (pin "4") (pinfunction "BLUE_4") (pintype "bidirectional"))
      (node (ref "U$134") (pin "4") (pinfunction "BLUE_4") (pintype "bidirectional"))
      (node (ref "U$166") (pin "4") (pinfunction "BLUE_4") (pintype "bidirectional"))
      (node (ref "U$198") (pin "4") (pinfunction "BLUE_4") (pintype "bidirectional"))
      (node (ref "U$230") (pin "4") (pinfunction "BLUE_4") (pintype "bidirectional"))
      (node (ref "U$262") (pin "4") (pinfunction "BLUE_4") (pintype "bidirectional"))
      (node (ref "U$294") (pin "4") (pinfunction "BLUE_4") (pintype "bidirectional"))
      (node (ref "U$326") (pin "4") (pinfunction "BLUE_4") (pintype "bidirectional"))
      (node (ref "U$358") (pin "4") (pinfunction "BLUE_4") (pintype "bidirectional"))
      (node (ref "U$38") (pin "4") (pinfunction "BLUE_4") (pintype "bidirectional"))
      (node (ref "U$390") (pin "4") (pinfunction "BLUE_4") (pintype "bidirectional"))
      (node (ref "U$422") (pin "4") (pinfunction "BLUE_4") (pintype "bidirectional"))
      (node (ref "U$454") (pin "4") (pinfunction "BLUE_4") (pintype "bidirectional"))
      (node (ref "U$486") (pin "4") (pinfunction "BLUE_4") (pintype "bidirectional"))
      (node (ref "U$518") (pin "4") (pinfunction "BLUE_4") (pintype "bidirectional"))
      (node (ref "U$6") (pin "15") (pinfunction "OUT15_15") (pintype "output"))
      (node (ref "U$70") (pin "4") (pinfunction "BLUE_4") (pintype "bidirectional"))
    )
    (net (code "82") (name "Net-(U$102-GREEN)") (class "Default")
      (node (ref "U$102") (pin "3") (pinfunction "GREEN_3") (pintype "bidirectional"))
      (node (ref "U$134") (pin "3") (pinfunction "GREEN_3") (pintype "bidirectional"))
      (node (ref "U$166") (pin "3") (pinfunction "GREEN_3") (pintype "bidirectional"))
      (node (ref "U$198") (pin "3") (pinfunction "GREEN_3") (pintype "bidirectional"))
      (node (ref "U$230") (pin "3") (pinfunction "GREEN_3") (pintype "bidirectional"))
      (node (ref "U$262") (pin "3") (pinfunction "GREEN_3") (pintype "bidirectional"))
      (node (ref "U$294") (pin "3") (pinfunction "GREEN_3") (pintype "bidirectional"))
      (node (ref "U$326") (pin "3") (pinfunction "GREEN_3") (pintype "bidirectional"))
      (node (ref "U$358") (pin "3") (pinfunction "GREEN_3") (pintype "bidirectional"))
      (node (ref "U$38") (pin "3") (pinfunction "GREEN_3") (pintype "bidirectional"))
      (node (ref "U$390") (pin "3") (pinfunction "GREEN_3") (pintype "bidirectional"))
      (node (ref "U$422") (pin "3") (pinfunction "GREEN_3") (pintype "bidirectional"))
      (node (ref "U$454") (pin "3") (pinfunction "GREEN_3") (pintype "bidirectional"))
      (node (ref "U$486") (pin "3") (pinfunction "GREEN_3") (pintype "bidirectional"))
      (node (ref "U$518") (pin "3") (pinfunction "GREEN_3") (pintype "bidirectional"))
      (node (ref "U$6") (pin "14") (pinfunction "OUT14_14") (pintype "output"))
      (node (ref "U$70") (pin "3") (pinfunction "GREEN_3") (pintype "bidirectional"))
    )
    (net (code "83") (name "Net-(U$102-RED)") (class "Default")
      (node (ref "U$102") (pin "1") (pinfunction "RED_1") (pintype "bidirectional"))
      (node (ref "U$134") (pin "1") (pinfunction "RED_1") (pintype "bidirectional"))
      (node (ref "U$166") (pin "1") (pinfunction "RED_1") (pintype "bidirectional"))
      (node (ref "U$198") (pin "1") (pinfunction "RED_1") (pintype "bidirectional"))
      (node (ref "U$230") (pin "1") (pinfunction "RED_1") (pintype "bidirectional"))
      (node (ref "U$262") (pin "1") (pinfunction "RED_1") (pintype "bidirectional"))
      (node (ref "U$294") (pin "1") (pinfunction "RED_1") (pintype "bidirectional"))
      (node (ref "U$326") (pin "1") (pinfunction "RED_1") (pintype "bidirectional"))
      (node (ref "U$358") (pin "1") (pinfunction "RED_1") (pintype "bidirectional"))
      (node (ref "U$38") (pin "1") (pinfunction "RED_1") (pintype "bidirectional"))
      (node (ref "U$390") (pin "1") (pinfunction "RED_1") (pintype "bidirectional"))
      (node (ref "U$422") (pin "1") (pinfunction "RED_1") (pintype "bidirectional"))
      (node (ref "U$454") (pin "1") (pinfunction "RED_1") (pintype "bidirectional"))
      (node (ref "U$486") (pin "1") (pinfunction "RED_1") (pintype "bidirectional"))
      (node (ref "U$518") (pin "1") (pinfunction "RED_1") (pintype "bidirectional"))
      (node (ref "U$6") (pin "13") (pinfunction "OUT13_13") (pintype "output"))
      (node (ref "U$70") (pin "1") (pinfunction "RED_1") (pintype "bidirectional"))
    )
    (net (code "84") (name "Net-(U$108-BLUE)") (class "Default")
      (node (ref "U$108") (pin "4") (pinfunction "BLUE_4") (pintype "bidirectional"))
      (node (ref "U$12") (pin "4") (pinfunction "BLUE_4") (pintype "bidirectional"))
      (node (ref "U$140") (pin "4") (pinfunction "BLUE_4") (pintype "bidirectional"))
      (node (ref "U$172") (pin "4") (pinfunction "BLUE_4") (pintype "bidirectional"))
      (node (ref "U$2") (pin "1") (pinfunction "OUT1_1") (pintype "output"))
      (node (ref "U$204") (pin "4") (pinfunction "BLUE_4") (pintype "bidirectional"))
      (node (ref "U$236") (pin "4") (pinfunction "BLUE_4") (pintype "bidirectional"))
      (node (ref "U$268") (pin "4") (pinfunction "BLUE_4") (pintype "bidirectional"))
      (node (ref "U$300") (pin "4") (pinfunction "BLUE_4") (pintype "bidirectional"))
      (node (ref "U$332") (pin "4") (pinfunction "BLUE_4") (pintype "bidirectional"))
      (node (ref "U$364") (pin "4") (pinfunction "BLUE_4") (pintype "bidirectional"))
      (node (ref "U$396") (pin "4") (pinfunction "BLUE_4") (pintype "bidirectional"))
      (node (ref "U$428") (pin "4") (pinfunction "BLUE_4") (pintype "bidirectional"))
      (node (ref "U$44") (pin "4") (pinfunction "BLUE_4") (pintype "bidirectional"))
      (node (ref "U$460") (pin "4") (pinfunction "BLUE_4") (pintype "bidirectional"))
      (node (ref "U$492") (pin "4") (pinfunction "BLUE_4") (pintype "bidirectional"))
      (node (ref "U$76") (pin "4") (pinfunction "BLUE_4") (pintype "bidirectional"))
    )
    (net (code "85") (name "Net-(U$108-GREEN)") (class "Default")
      (node (ref "U$108") (pin "3") (pinfunction "GREEN_3") (pintype "bidirectional"))
      (node (ref "U$12") (pin "3") (pinfunction "GREEN_3") (pintype "bidirectional"))
      (node (ref "U$140") (pin "3") (pinfunction "GREEN_3") (pintype "bidirectional"))
      (node (ref "U$172") (pin "3") (pinfunction "GREEN_3") (pintype "bidirectional"))
      (node (ref "U$2") (pin "28") (pinfunction "OUT0_28") (pintype "output"))
      (node (ref "U$204") (pin "3") (pinfunction "GREEN_3") (pintype "bidirectional"))
      (node (ref "U$236") (pin "3") (pinfunction "GREEN_3") (pintype "bidirectional"))
      (node (ref "U$268") (pin "3") (pinfunction "GREEN_3") (pintype "bidirectional"))
      (node (ref "U$300") (pin "3") (pinfunction "GREEN_3") (pintype "bidirectional"))
      (node (ref "U$332") (pin "3") (pinfunction "GREEN_3") (pintype "bidirectional"))
      (node (ref "U$364") (pin "3") (pinfunction "GREEN_3") (pintype "bidirectional"))
      (node (ref "U$396") (pin "3") (pinfunction "GREEN_3") (pintype "bidirectional"))
      (node (ref "U$428") (pin "3") (pinfunction "GREEN_3") (pintype "bidirectional"))
      (node (ref "U$44") (pin "3") (pinfunction "GREEN_3") (pintype "bidirectional"))
      (node (ref "U$460") (pin "3") (pinfunction "GREEN_3") (pintype "bidirectional"))
      (node (ref "U$492") (pin "3") (pinfunction "GREEN_3") (pintype "bidirectional"))
      (node (ref "U$76") (pin "3") (pinfunction "GREEN_3") (pintype "bidirectional"))
    )
    (net (code "86") (name "Net-(U$109-BLUE)") (class "Default")
      (node (ref "U$109") (pin "4") (pinfunction "BLUE_4") (pintype "bidirectional"))
      (node (ref "U$13") (pin "4") (pinfunction "BLUE_4") (pintype "bidirectional"))
      (node (ref "U$141") (pin "4") (pinfunction "BLUE_4") (pintype "bidirectional"))
      (node (ref "U$173") (pin "4") (pinfunction "BLUE_4") (pintype "bidirectional"))
      (node (ref "U$2") (pin "4") (pinfunction "OUT4_4") (pintype "output"))
      (node (ref "U$205") (pin "4") (pinfunction "BLUE_4") (pintype "bidirectional"))
      (node (ref "U$237") (pin "4") (pinfunction "BLUE_4") (pintype "bidirectional"))
      (node (ref "U$269") (pin "4") (pinfunction "BLUE_4") (pintype "bidirectional"))
      (node (ref "U$301") (pin "4") (pinfunction "BLUE_4") (pintype "bidirectional"))
      (node (ref "U$333") (pin "4") (pinfunction "BLUE_4") (pintype "bidirectional"))
      (node (ref "U$365") (pin "4") (pinfunction "BLUE_4") (pintype "bidirectional"))
      (node (ref "U$397") (pin "4") (pinfunction "BLUE_4") (pintype "bidirectional"))
      (node (ref "U$429") (pin "4") (pinfunction "BLUE_4") (pintype "bidirectional"))
      (node (ref "U$45") (pin "4") (pinfunction "BLUE_4") (pintype "bidirectional"))
      (node (ref "U$461") (pin "4") (pinfunction "BLUE_4") (pintype "bidirectional"))
      (node (ref "U$493") (pin "4") (pinfunction "BLUE_4") (pintype "bidirectional"))
      (node (ref "U$77") (pin "4") (pinfunction "BLUE_4") (pintype "bidirectional"))
    )
    (net (code "87") (name "Net-(U$109-GREEN)") (class "Default")
      (node (ref "U$109") (pin "3") (pinfunction "GREEN_3") (pintype "bidirectional"))
      (node (ref "U$13") (pin "3") (pinfunction "GREEN_3") (pintype "bidirectional"))
      (node (ref "U$141") (pin "3") (pinfunction "GREEN_3") (pintype "bidirectional"))
      (node (ref "U$173") (pin "3") (pinfunction "GREEN_3") (pintype "bidirectional"))
      (node (ref "U$2") (pin "3") (pinfunction "OUT3_3") (pintype "output"))
      (node (ref "U$205") (pin "3") (pinfunction "GREEN_3") (pintype "bidirectional"))
      (node (ref "U$237") (pin "3") (pinfunction "GREEN_3") (pintype "bidirectional"))
      (node (ref "U$269") (pin "3") (pinfunction "GREEN_3") (pintype "bidirectional"))
      (node (ref "U$301") (pin "3") (pinfunction "GREEN_3") (pintype "bidirectional"))
      (node (ref "U$333") (pin "3") (pinfunction "GREEN_3") (pintype "bidirectional"))
      (node (ref "U$365") (pin "3") (pinfunction "GREEN_3") (pintype "bidirectional"))
      (node (ref "U$397") (pin "3") (pinfunction "GREEN_3") (pintype "bidirectional"))
      (node (ref "U$429") (pin "3") (pinfunction "GREEN_3") (pintype "bidirectional"))
      (node (ref "U$45") (pin "3") (pinfunction "GREEN_3") (pintype "bidirectional"))
      (node (ref "U$461") (pin "3") (pinfunction "GREEN_3") (pintype "bidirectional"))
      (node (ref "U$493") (pin "3") (pinfunction "GREEN_3") (pintype "bidirectional"))
      (node (ref "U$77") (pin "3") (pinfunction "GREEN_3") (pintype "bidirectional"))
    )
    (net (code "88") (name "Net-(U$109-RED)") (class "Default")
      (node (ref "U$109") (pin "1") (pinfunction "RED_1") (pintype "bidirectional"))
      (node (ref "U$13") (pin "1") (pinfunction "RED_1") (pintype "bidirectional"))
      (node (ref "U$141") (pin "1") (pinfunction "RED_1") (pintype "bidirectional"))
      (node (ref "U$173") (pin "1") (pinfunction "RED_1") (pintype "bidirectional"))
      (node (ref "U$2") (pin "2") (pinfunction "OUT2_2") (pintype "output"))
      (node (ref "U$205") (pin "1") (pinfunction "RED_1") (pintype "bidirectional"))
      (node (ref "U$237") (pin "1") (pinfunction "RED_1") (pintype "bidirectional"))
      (node (ref "U$269") (pin "1") (pinfunction "RED_1") (pintype "bidirectional"))
      (node (ref "U$301") (pin "1") (pinfunction "RED_1") (pintype "bidirectional"))
      (node (ref "U$333") (pin "1") (pinfunction "RED_1") (pintype "bidirectional"))
      (node (ref "U$365") (pin "1") (pinfunction "RED_1") (pintype "bidirectional"))
      (node (ref "U$397") (pin "1") (pinfunction "RED_1") (pintype "bidirectional"))
      (node (ref "U$429") (pin "1") (pinfunction "RED_1") (pintype "bidirectional"))
      (node (ref "U$45") (pin "1") (pinfunction "RED_1") (pintype "bidirectional"))
      (node (ref "U$461") (pin "1") (pinfunction "RED_1") (pintype "bidirectional"))
      (node (ref "U$493") (pin "1") (pinfunction "RED_1") (pintype "bidirectional"))
      (node (ref "U$77") (pin "1") (pinfunction "RED_1") (pintype "bidirectional"))
    )
    (net (code "89") (name "Net-(U$110-BLUE)") (class "Default")
      (node (ref "U$110") (pin "4") (pinfunction "BLUE_4") (pintype "bidirectional"))
      (node (ref "U$14") (pin "4") (pinfunction "BLUE_4") (pintype "bidirectional"))
      (node (ref "U$142") (pin "4") (pinfunction "BLUE_4") (pintype "bidirectional"))
      (node (ref "U$174") (pin "4") (pinfunction "BLUE_4") (pintype "bidirectional"))
      (node (ref "U$2") (pin "7") (pinfunction "OUT7_7") (pintype "output"))
      (node (ref "U$206") (pin "4") (pinfunction "BLUE_4") (pintype "bidirectional"))
      (node (ref "U$238") (pin "4") (pinfunction "BLUE_4") (pintype "bidirectional"))
      (node (ref "U$270") (pin "4") (pinfunction "BLUE_4") (pintype "bidirectional"))
      (node (ref "U$302") (pin "4") (pinfunction "BLUE_4") (pintype "bidirectional"))
      (node (ref "U$334") (pin "4") (pinfunction "BLUE_4") (pintype "bidirectional"))
      (node (ref "U$366") (pin "4") (pinfunction "BLUE_4") (pintype "bidirectional"))
      (node (ref "U$398") (pin "4") (pinfunction "BLUE_4") (pintype "bidirectional"))
      (node (ref "U$430") (pin "4") (pinfunction "BLUE_4") (pintype "bidirectional"))
      (node (ref "U$46") (pin "4") (pinfunction "BLUE_4") (pintype "bidirectional"))
      (node (ref "U$462") (pin "4") (pinfunction "BLUE_4") (pintype "bidirectional"))
      (node (ref "U$494") (pin "4") (pinfunction "BLUE_4") (pintype "bidirectional"))
      (node (ref "U$78") (pin "4") (pinfunction "BLUE_4") (pintype "bidirectional"))
    )
    (net (code "90") (name "Net-(U$110-GREEN)") (class "Default")
      (node (ref "U$110") (pin "3") (pinfunction "GREEN_3") (pintype "bidirectional"))
      (node (ref "U$14") (pin "3") (pinfunction "GREEN_3") (pintype "bidirectional"))
      (node (ref "U$142") (pin "3") (pinfunction "GREEN_3") (pintype "bidirectional"))
      (node (ref "U$174") (pin "3") (pinfunction "GREEN_3") (pintype "bidirectional"))
      (node (ref "U$2") (pin "6") (pinfunction "OUT6_6") (pintype "output"))
      (node (ref "U$206") (pin "3") (pinfunction "GREEN_3") (pintype "bidirectional"))
      (node (ref "U$238") (pin "3") (pinfunction "GREEN_3") (pintype "bidirectional"))
      (node (ref "U$270") (pin "3") (pinfunction "GREEN_3") (pintype "bidirectional"))
      (node (ref "U$302") (pin "3") (pinfunction "GREEN_3") (pintype "bidirectional"))
      (node (ref "U$334") (pin "3") (pinfunction "GREEN_3") (pintype "bidirectional"))
      (node (ref "U$366") (pin "3") (pinfunction "GREEN_3") (pintype "bidirectional"))
      (node (ref "U$398") (pin "3") (pinfunction "GREEN_3") (pintype "bidirectional"))
      (node (ref "U$430") (pin "3") (pinfunction "GREEN_3") (pintype "bidirectional"))
      (node (ref "U$46") (pin "3") (pinfunction "GREEN_3") (pintype "bidirectional"))
      (node (ref "U$462") (pin "3") (pinfunction "GREEN_3") (pintype "bidirectional"))
      (node (ref "U$494") (pin "3") (pinfunction "GREEN_3") (pintype "bidirectional"))
      (node (ref "U$78") (pin "3") (pinfunction "GREEN_3") (pintype "bidirectional"))
    )
    (net (code "91") (name "Net-(U$110-RED)") (class "Default")
      (node (ref "U$110") (pin "1") (pinfunction "RED_1") (pintype "bidirectional"))
      (node (ref "U$14") (pin "1") (pinfunction "RED_1") (pintype "bidirectional"))
      (node (ref "U$142") (pin "1") (pinfunction "RED_1") (pintype "bidirectional"))
      (node (ref "U$174") (pin "1") (pinfunction "RED_1") (pintype "bidirectional"))
      (node (ref "U$2") (pin "5") (pinfunction "OUT5_5") (pintype "output"))
      (node (ref "U$206") (pin "1") (pinfunction "RED_1") (pintype "bidirectional"))
      (node (ref "U$238") (pin "1") (pinfunction "RED_1") (pintype "bidirectional"))
      (node (ref "U$270") (pin "1") (pinfunction "RED_1") (pintype "bidirectional"))
      (node (ref "U$302") (pin "1") (pinfunction "RED_1") (pintype "bidirectional"))
      (node (ref "U$334") (pin "1") (pinfunction "RED_1") (pintype "bidirectional"))
      (node (ref "U$366") (pin "1") (pinfunction "RED_1") (pintype "bidirectional"))
      (node (ref "U$398") (pin "1") (pinfunction "RED_1") (pintype "bidirectional"))
      (node (ref "U$430") (pin "1") (pinfunction "RED_1") (pintype "bidirectional"))
      (node (ref "U$46") (pin "1") (pinfunction "RED_1") (pintype "bidirectional"))
      (node (ref "U$462") (pin "1") (pinfunction "RED_1") (pintype "bidirectional"))
      (node (ref "U$494") (pin "1") (pinfunction "RED_1") (pintype "bidirectional"))
      (node (ref "U$78") (pin "1") (pinfunction "RED_1") (pintype "bidirectional"))
    )
    (net (code "92") (name "Net-(U$111-BLUE)") (class "Default")
      (node (ref "U$111") (pin "4") (pinfunction "BLUE_4") (pintype "bidirectional"))
      (node (ref "U$143") (pin "4") (pinfunction "BLUE_4") (pintype "bidirectional"))
      (node (ref "U$15") (pin "4") (pinfunction "BLUE_4") (pintype "bidirectional"))
      (node (ref "U$175") (pin "4") (pinfunction "BLUE_4") (pintype "bidirectional"))
      (node (ref "U$2") (pin "10") (pinfunction "OUT10_10") (pintype "output"))
      (node (ref "U$207") (pin "4") (pinfunction "BLUE_4") (pintype "bidirectional"))
      (node (ref "U$239") (pin "4") (pinfunction "BLUE_4") (pintype "bidirectional"))
      (node (ref "U$271") (pin "4") (pinfunction "BLUE_4") (pintype "bidirectional"))
      (node (ref "U$303") (pin "4") (pinfunction "BLUE_4") (pintype "bidirectional"))
      (node (ref "U$335") (pin "4") (pinfunction "BLUE_4") (pintype "bidirectional"))
      (node (ref "U$367") (pin "4") (pinfunction "BLUE_4") (pintype "bidirectional"))
      (node (ref "U$399") (pin "4") (pinfunction "BLUE_4") (pintype "bidirectional"))
      (node (ref "U$431") (pin "4") (pinfunction "BLUE_4") (pintype "bidirectional"))
      (node (ref "U$463") (pin "4") (pinfunction "BLUE_4") (pintype "bidirectional"))
      (node (ref "U$47") (pin "4") (pinfunction "BLUE_4") (pintype "bidirectional"))
      (node (ref "U$495") (pin "4") (pinfunction "BLUE_4") (pintype "bidirectional"))
      (node (ref "U$79") (pin "4") (pinfunction "BLUE_4") (pintype "bidirectional"))
    )
    (net (code "93") (name "Net-(U$111-GREEN)") (class "Default")
      (node (ref "U$111") (pin "3") (pinfunction "GREEN_3") (pintype "bidirectional"))
      (node (ref "U$143") (pin "3") (pinfunction "GREEN_3") (pintype "bidirectional"))
      (node (ref "U$15") (pin "3") (pinfunction "GREEN_3") (pintype "bidirectional"))
      (node (ref "U$175") (pin "3") (pinfunction "GREEN_3") (pintype "bidirectional"))
      (node (ref "U$2") (pin "9") (pinfunction "OUT9_9") (pintype "output"))
      (node (ref "U$207") (pin "3") (pinfunction "GREEN_3") (pintype "bidirectional"))
      (node (ref "U$239") (pin "3") (pinfunction "GREEN_3") (pintype "bidirectional"))
      (node (ref "U$271") (pin "3") (pinfunction "GREEN_3") (pintype "bidirectional"))
      (node (ref "U$303") (pin "3") (pinfunction "GREEN_3") (pintype "bidirectional"))
      (node (ref "U$335") (pin "3") (pinfunction "GREEN_3") (pintype "bidirectional"))
      (node (ref "U$367") (pin "3") (pinfunction "GREEN_3") (pintype "bidirectional"))
      (node (ref "U$399") (pin "3") (pinfunction "GREEN_3") (pintype "bidirectional"))
      (node (ref "U$431") (pin "3") (pinfunction "GREEN_3") (pintype "bidirectional"))
      (node (ref "U$463") (pin "3") (pinfunction "GREEN_3") (pintype "bidirectional"))
      (node (ref "U$47") (pin "3") (pinfunction "GREEN_3") (pintype "bidirectional"))
      (node (ref "U$495") (pin "3") (pinfunction "GREEN_3") (pintype "bidirectional"))
      (node (ref "U$79") (pin "3") (pinfunction "GREEN_3") (pintype "bidirectional"))
    )
    (net (code "94") (name "Net-(U$111-RED)") (class "Default")
      (node (ref "U$111") (pin "1") (pinfunction "RED_1") (pintype "bidirectional"))
      (node (ref "U$143") (pin "1") (pinfunction "RED_1") (pintype "bidirectional"))
      (node (ref "U$15") (pin "1") (pinfunction "RED_1") (pintype "bidirectional"))
      (node (ref "U$175") (pin "1") (pinfunction "RED_1") (pintype "bidirectional"))
      (node (ref "U$2") (pin "8") (pinfunction "OUT8_8") (pintype "output"))
      (node (ref "U$207") (pin "1") (pinfunction "RED_1") (pintype "bidirectional"))
      (node (ref "U$239") (pin "1") (pinfunction "RED_1") (pintype "bidirectional"))
      (node (ref "U$271") (pin "1") (pinfunction "RED_1") (pintype "bidirectional"))
      (node (ref "U$303") (pin "1") (pinfunction "RED_1") (pintype "bidirectional"))
      (node (ref "U$335") (pin "1") (pinfunction "RED_1") (pintype "bidirectional"))
      (node (ref "U$367") (pin "1") (pinfunction "RED_1") (pintype "bidirectional"))
      (node (ref "U$399") (pin "1") (pinfunction "RED_1") (pintype "bidirectional"))
      (node (ref "U$431") (pin "1") (pinfunction "RED_1") (pintype "bidirectional"))
      (node (ref "U$463") (pin "1") (pinfunction "RED_1") (pintype "bidirectional"))
      (node (ref "U$47") (pin "1") (pinfunction "RED_1") (pintype "bidirectional"))
      (node (ref "U$495") (pin "1") (pinfunction "RED_1") (pintype "bidirectional"))
      (node (ref "U$79") (pin "1") (pinfunction "RED_1") (pintype "bidirectional"))
    )
    (net (code "95") (name "Net-(U$112-BLUE)") (class "Default")
      (node (ref "U$112") (pin "4") (pinfunction "BLUE_4") (pintype "bidirectional"))
      (node (ref "U$144") (pin "4") (pinfunction "BLUE_4") (pintype "bidirectional"))
      (node (ref "U$16") (pin "4") (pinfunction "BLUE_4") (pintype "bidirectional"))
      (node (ref "U$176") (pin "4") (pinfunction "BLUE_4") (pintype "bidirectional"))
      (node (ref "U$2") (pin "13") (pinfunction "OUT13_13") (pintype "output"))
      (node (ref "U$208") (pin "4") (pinfunction "BLUE_4") (pintype "bidirectional"))
      (node (ref "U$240") (pin "4") (pinfunction "BLUE_4") (pintype "bidirectional"))
      (node (ref "U$272") (pin "4") (pinfunction "BLUE_4") (pintype "bidirectional"))
      (node (ref "U$304") (pin "4") (pinfunction "BLUE_4") (pintype "bidirectional"))
      (node (ref "U$336") (pin "4") (pinfunction "BLUE_4") (pintype "bidirectional"))
      (node (ref "U$368") (pin "4") (pinfunction "BLUE_4") (pintype "bidirectional"))
      (node (ref "U$400") (pin "4") (pinfunction "BLUE_4") (pintype "bidirectional"))
      (node (ref "U$432") (pin "4") (pinfunction "BLUE_4") (pintype "bidirectional"))
      (node (ref "U$464") (pin "4") (pinfunction "BLUE_4") (pintype "bidirectional"))
      (node (ref "U$48") (pin "4") (pinfunction "BLUE_4") (pintype "bidirectional"))
      (node (ref "U$496") (pin "4") (pinfunction "BLUE_4") (pintype "bidirectional"))
      (node (ref "U$80") (pin "4") (pinfunction "BLUE_4") (pintype "bidirectional"))
    )
    (net (code "96") (name "Net-(U$112-GREEN)") (class "Default")
      (node (ref "U$112") (pin "3") (pinfunction "GREEN_3") (pintype "bidirectional"))
      (node (ref "U$144") (pin "3") (pinfunction "GREEN_3") (pintype "bidirectional"))
      (node (ref "U$16") (pin "3") (pinfunction "GREEN_3") (pintype "bidirectional"))
      (node (ref "U$176") (pin "3") (pinfunction "GREEN_3") (pintype "bidirectional"))
      (node (ref "U$2") (pin "12") (pinfunction "OUT12_12") (pintype "output"))
      (node (ref "U$208") (pin "3") (pinfunction "GREEN_3") (pintype "bidirectional"))
      (node (ref "U$240") (pin "3") (pinfunction "GREEN_3") (pintype "bidirectional"))
      (node (ref "U$272") (pin "3") (pinfunction "GREEN_3") (pintype "bidirectional"))
      (node (ref "U$304") (pin "3") (pinfunction "GREEN_3") (pintype "bidirectional"))
      (node (ref "U$336") (pin "3") (pinfunction "GREEN_3") (pintype "bidirectional"))
      (node (ref "U$368") (pin "3") (pinfunction "GREEN_3") (pintype "bidirectional"))
      (node (ref "U$400") (pin "3") (pinfunction "GREEN_3") (pintype "bidirectional"))
      (node (ref "U$432") (pin "3") (pinfunction "GREEN_3") (pintype "bidirectional"))
      (node (ref "U$464") (pin "3") (pinfunction "GREEN_3") (pintype "bidirectional"))
      (node (ref "U$48") (pin "3") (pinfunction "GREEN_3") (pintype "bidirectional"))
      (node (ref "U$496") (pin "3") (pinfunction "GREEN_3") (pintype "bidirectional"))
      (node (ref "U$80") (pin "3") (pinfunction "GREEN_3") (pintype "bidirectional"))
    )
    (net (code "97") (name "Net-(U$112-RED)") (class "Default")
      (node (ref "U$112") (pin "1") (pinfunction "RED_1") (pintype "bidirectional"))
      (node (ref "U$144") (pin "1") (pinfunction "RED_1") (pintype "bidirectional"))
      (node (ref "U$16") (pin "1") (pinfunction "RED_1") (pintype "bidirectional"))
      (node (ref "U$176") (pin "1") (pinfunction "RED_1") (pintype "bidirectional"))
      (node (ref "U$2") (pin "11") (pinfunction "OUT11_11") (pintype "output"))
      (node (ref "U$208") (pin "1") (pinfunction "RED_1") (pintype "bidirectional"))
      (node (ref "U$240") (pin "1") (pinfunction "RED_1") (pintype "bidirectional"))
      (node (ref "U$272") (pin "1") (pinfunction "RED_1") (pintype "bidirectional"))
      (node (ref "U$304") (pin "1") (pinfunction "RED_1") (pintype "bidirectional"))
      (node (ref "U$336") (pin "1") (pinfunction "RED_1") (pintype "bidirectional"))
      (node (ref "U$368") (pin "1") (pinfunction "RED_1") (pintype "bidirectional"))
      (node (ref "U$400") (pin "1") (pinfunction "RED_1") (pintype "bidirectional"))
      (node (ref "U$432") (pin "1") (pinfunction "RED_1") (pintype "bidirectional"))
      (node (ref "U$464") (pin "1") (pinfunction "RED_1") (pintype "bidirectional"))
      (node (ref "U$48") (pin "1") (pinfunction "RED_1") (pintype "bidirectional"))
      (node (ref "U$496") (pin "1") (pinfunction "RED_1") (pintype "bidirectional"))
      (node (ref "U$80") (pin "1") (pinfunction "RED_1") (pintype "bidirectional"))
    )
    (net (code "98") (name "Net-(U$113-BLUE)") (class "Default")
      (node (ref "U$113") (pin "4") (pinfunction "BLUE_4") (pintype "bidirectional"))
      (node (ref "U$145") (pin "4") (pinfunction "BLUE_4") (pintype "bidirectional"))
      (node (ref "U$17") (pin "4") (pinfunction "BLUE_4") (pintype "bidirectional"))
      (node (ref "U$177") (pin "4") (pinfunction "BLUE_4") (pintype "bidirectional"))
      (node (ref "U$209") (pin "4") (pinfunction "BLUE_4") (pintype "bidirectional"))
      (node (ref "U$241") (pin "4") (pinfunction "BLUE_4") (pintype "bidirectional"))
      (node (ref "U$273") (pin "4") (pinfunction "BLUE_4") (pintype "bidirectional"))
      (node (ref "U$3") (pin "28") (pinfunction "OUT0_28") (pintype "output"))
      (node (ref "U$305") (pin "4") (pinfunction "BLUE_4") (pintype "bidirectional"))
      (node (ref "U$337") (pin "4") (pinfunction "BLUE_4") (pintype "bidirectional"))
      (node (ref "U$369") (pin "4") (pinfunction "BLUE_4") (pintype "bidirectional"))
      (node (ref "U$401") (pin "4") (pinfunction "BLUE_4") (pintype "bidirectional"))
      (node (ref "U$433") (pin "4") (pinfunction "BLUE_4") (pintype "bidirectional"))
      (node (ref "U$465") (pin "4") (pinfunction "BLUE_4") (pintype "bidirectional"))
      (node (ref "U$49") (pin "4") (pinfunction "BLUE_4") (pintype "bidirectional"))
      (node (ref "U$497") (pin "4") (pinfunction "BLUE_4") (pintype "bidirectional"))
      (node (ref "U$81") (pin "4") (pinfunction "BLUE_4") (pintype "bidirectional"))
    )
    (net (code "99") (name "Net-(U$113-GREEN)") (class "Default")
      (node (ref "U$113") (pin "3") (pinfunction "GREEN_3") (pintype "bidirectional"))
      (node (ref "U$145") (pin "3") (pinfunction "GREEN_3") (pintype "bidirectional"))
      (node (ref "U$17") (pin "3") (pinfunction "GREEN_3") (pintype "bidirectional"))
      (node (ref "U$177") (pin "3") (pinfunction "GREEN_3") (pintype "bidirectional"))
      (node (ref "U$2") (pin "15") (pinfunction "OUT15_15") (pintype "output"))
      (node (ref "U$209") (pin "3") (pinfunction "GREEN_3") (pintype "bidirectional"))
      (node (ref "U$241") (pin "3") (pinfunction "GREEN_3") (pintype "bidirectional"))
      (node (ref "U$273") (pin "3") (pinfunction "GREEN_3") (pintype "bidirectional"))
      (node (ref "U$305") (pin "3") (pinfunction "GREEN_3") (pintype "bidirectional"))
      (node (ref "U$337") (pin "3") (pinfunction "GREEN_3") (pintype "bidirectional"))
      (node (ref "U$369") (pin "3") (pinfunction "GREEN_3") (pintype "bidirectional"))
      (node (ref "U$401") (pin "3") (pinfunction "GREEN_3") (pintype "bidirectional"))
      (node (ref "U$433") (pin "3") (pinfunction "GREEN_3") (pintype "bidirectional"))
      (node (ref "U$465") (pin "3") (pinfunction "GREEN_3") (pintype "bidirectional"))
      (node (ref "U$49") (pin "3") (pinfunction "GREEN_3") (pintype "bidirectional"))
      (node (ref "U$497") (pin "3") (pinfunction "GREEN_3") (pintype "bidirectional"))
      (node (ref "U$81") (pin "3") (pinfunction "GREEN_3") (pintype "bidirectional"))
    )
    (net (code "100") (name "Net-(U$113-RED)") (class "Default")
      (node (ref "U$113") (pin "1") (pinfunction "RED_1") (pintype "bidirectional"))
      (node (ref "U$145") (pin "1") (pinfunction "RED_1") (pintype "bidirectional"))
      (node (ref "U$17") (pin "1") (pinfunction "RED_1") (pintype "bidirectional"))
      (node (ref "U$177") (pin "1") (pinfunction "RED_1") (pintype "bidirectional"))
      (node (ref "U$2") (pin "14") (pinfunction "OUT14_14") (pintype "output"))
      (node (ref "U$209") (pin "1") (pinfunction "RED_1") (pintype "bidirectional"))
      (node (ref "U$241") (pin "1") (pinfunction "RED_1") (pintype "bidirectional"))
      (node (ref "U$273") (pin "1") (pinfunction "RED_1") (pintype "bidirectional"))
      (node (ref "U$305") (pin "1") (pinfunction "RED_1") (pintype "bidirectional"))
      (node (ref "U$337") (pin "1") (pinfunction "RED_1") (pintype "bidirectional"))
      (node (ref "U$369") (pin "1") (pinfunction "RED_1") (pintype "bidirectional"))
      (node (ref "U$401") (pin "1") (pinfunction "RED_1") (pintype "bidirectional"))
      (node (ref "U$433") (pin "1") (pinfunction "RED_1") (pintype "bidirectional"))
      (node (ref "U$465") (pin "1") (pinfunction "RED_1") (pintype "bidirectional"))
      (node (ref "U$49") (pin "1") (pinfunction "RED_1") (pintype "bidirectional"))
      (node (ref "U$497") (pin "1") (pinfunction "RED_1") (pintype "bidirectional"))
      (node (ref "U$81") (pin "1") (pinfunction "RED_1") (pintype "bidirectional"))
    )
    (net (code "101") (name "Net-(U$114-BLUE)") (class "Default")
      (node (ref "U$114") (pin "4") (pinfunction "BLUE_4") (pintype "bidirectional"))
      (node (ref "U$146") (pin "4") (pinfunction "BLUE_4") (pintype "bidirectional"))
      (node (ref "U$178") (pin "4") (pinfunction "BLUE_4") (pintype "bidirectional"))
      (node (ref "U$18") (pin "4") (pinfunction "BLUE_4") (pintype "bidirectional"))
      (node (ref "U$210") (pin "4") (pinfunction "BLUE_4") (pintype "bidirectional"))
      (node (ref "U$242") (pin "4") (pinfunction "BLUE_4") (pintype "bidirectional"))
      (node (ref "U$274") (pin "4") (pinfunction "BLUE_4") (pintype "bidirectional"))
      (node (ref "U$3") (pin "3") (pinfunction "OUT3_3") (pintype "output"))
      (node (ref "U$306") (pin "4") (pinfunction "BLUE_4") (pintype "bidirectional"))
      (node (ref "U$338") (pin "4") (pinfunction "BLUE_4") (pintype "bidirectional"))
      (node (ref "U$370") (pin "4") (pinfunction "BLUE_4") (pintype "bidirectional"))
      (node (ref "U$402") (pin "4") (pinfunction "BLUE_4") (pintype "bidirectional"))
      (node (ref "U$434") (pin "4") (pinfunction "BLUE_4") (pintype "bidirectional"))
      (node (ref "U$466") (pin "4") (pinfunction "BLUE_4") (pintype "bidirectional"))
      (node (ref "U$498") (pin "4") (pinfunction "BLUE_4") (pintype "bidirectional"))
      (node (ref "U$50") (pin "4") (pinfunction "BLUE_4") (pintype "bidirectional"))
      (node (ref "U$82") (pin "4") (pinfunction "BLUE_4") (pintype "bidirectional"))
    )
    (net (code "102") (name "Net-(U$114-GREEN)") (class "Default")
      (node (ref "U$114") (pin "3") (pinfunction "GREEN_3") (pintype "bidirectional"))
      (node (ref "U$146") (pin "3") (pinfunction "GREEN_3") (pintype "bidirectional"))
      (node (ref "U$178") (pin "3") (pinfunction "GREEN_3") (pintype "bidirectional"))
      (node (ref "U$18") (pin "3") (pinfunction "GREEN_3") (pintype "bidirectional"))
      (node (ref "U$210") (pin "3") (pinfunction "GREEN_3") (pintype "bidirectional"))
      (node (ref "U$242") (pin "3") (pinfunction "GREEN_3") (pintype "bidirectional"))
      (node (ref "U$274") (pin "3") (pinfunction "GREEN_3") (pintype "bidirectional"))
      (node (ref "U$3") (pin "2") (pinfunction "OUT2_2") (pintype "output"))
      (node (ref "U$306") (pin "3") (pinfunction "GREEN_3") (pintype "bidirectional"))
      (node (ref "U$338") (pin "3") (pinfunction "GREEN_3") (pintype "bidirectional"))
      (node (ref "U$370") (pin "3") (pinfunction "GREEN_3") (pintype "bidirectional"))
      (node (ref "U$402") (pin "3") (pinfunction "GREEN_3") (pintype "bidirectional"))
      (node (ref "U$434") (pin "3") (pinfunction "GREEN_3") (pintype "bidirectional"))
      (node (ref "U$466") (pin "3") (pinfunction "GREEN_3") (pintype "bidirectional"))
      (node (ref "U$498") (pin "3") (pinfunction "GREEN_3") (pintype "bidirectional"))
      (node (ref "U$50") (pin "3") (pinfunction "GREEN_3") (pintype "bidirectional"))
      (node (ref "U$82") (pin "3") (pinfunction "GREEN_3") (pintype "bidirectional"))
    )
    (net (code "103") (name "Net-(U$114-RED)") (class "Default")
      (node (ref "U$114") (pin "1") (pinfunction "RED_1") (pintype "bidirectional"))
      (node (ref "U$146") (pin "1") (pinfunction "RED_1") (pintype "bidirectional"))
      (node (ref "U$178") (pin "1") (pinfunction "RED_1") (pintype "bidirectional"))
      (node (ref "U$18") (pin "1") (pinfunction "RED_1") (pintype "bidirectional"))
      (node (ref "U$210") (pin "1") (pinfunction "RED_1") (pintype "bidirectional"))
      (node (ref "U$242") (pin "1") (pinfunction "RED_1") (pintype "bidirectional"))
      (node (ref "U$274") (pin "1") (pinfunction "RED_1") (pintype "bidirectional"))
      (node (ref "U$3") (pin "1") (pinfunction "OUT1_1") (pintype "output"))
      (node (ref "U$306") (pin "1") (pinfunction "RED_1") (pintype "bidirectional"))
      (node (ref "U$338") (pin "1") (pinfunction "RED_1") (pintype "bidirectional"))
      (node (ref "U$370") (pin "1") (pinfunction "RED_1") (pintype "bidirectional"))
      (node (ref "U$402") (pin "1") (pinfunction "RED_1") (pintype "bidirectional"))
      (node (ref "U$434") (pin "1") (pinfunction "RED_1") (pintype "bidirectional"))
      (node (ref "U$466") (pin "1") (pinfunction "RED_1") (pintype "bidirectional"))
      (node (ref "U$498") (pin "1") (pinfunction "RED_1") (pintype "bidirectional"))
      (node (ref "U$50") (pin "1") (pinfunction "RED_1") (pintype "bidirectional"))
      (node (ref "U$82") (pin "1") (pinfunction "RED_1") (pintype "bidirectional"))
    )
    (net (code "104") (name "Net-(U$115-BLUE)") (class "Default")
      (node (ref "U$115") (pin "4") (pinfunction "BLUE_4") (pintype "bidirectional"))
      (node (ref "U$147") (pin "4") (pinfunction "BLUE_4") (pintype "bidirectional"))
      (node (ref "U$179") (pin "4") (pinfunction "BLUE_4") (pintype "bidirectional"))
      (node (ref "U$19") (pin "4") (pinfunction "BLUE_4") (pintype "bidirectional"))
      (node (ref "U$211") (pin "4") (pinfunction "BLUE_4") (pintype "bidirectional"))
      (node (ref "U$243") (pin "4") (pinfunction "BLUE_4") (pintype "bidirectional"))
      (node (ref "U$275") (pin "4") (pinfunction "BLUE_4") (pintype "bidirectional"))
      (node (ref "U$3") (pin "6") (pinfunction "OUT6_6") (pintype "output"))
      (node (ref "U$307") (pin "4") (pinfunction "BLUE_4") (pintype "bidirectional"))
      (node (ref "U$339") (pin "4") (pinfunction "BLUE_4") (pintype "bidirectional"))
      (node (ref "U$371") (pin "4") (pinfunction "BLUE_4") (pintype "bidirectional"))
      (node (ref "U$403") (pin "4") (pinfunction "BLUE_4") (pintype "bidirectional"))
      (node (ref "U$435") (pin "4") (pinfunction "BLUE_4") (pintype "bidirectional"))
      (node (ref "U$467") (pin "4") (pinfunction "BLUE_4") (pintype "bidirectional"))
      (node (ref "U$499") (pin "4") (pinfunction "BLUE_4") (pintype "bidirectional"))
      (node (ref "U$51") (pin "4") (pinfunction "BLUE_4") (pintype "bidirectional"))
      (node (ref "U$83") (pin "4") (pinfunction "BLUE_4") (pintype "bidirectional"))
    )
    (net (code "105") (name "Net-(U$115-GREEN)") (class "Default")
      (node (ref "U$115") (pin "3") (pinfunction "GREEN_3") (pintype "bidirectional"))
      (node (ref "U$147") (pin "3") (pinfunction "GREEN_3") (pintype "bidirectional"))
      (node (ref "U$179") (pin "3") (pinfunction "GREEN_3") (pintype "bidirectional"))
      (node (ref "U$19") (pin "3") (pinfunction "GREEN_3") (pintype "bidirectional"))
      (node (ref "U$211") (pin "3") (pinfunction "GREEN_3") (pintype "bidirectional"))
      (node (ref "U$243") (pin "3") (pinfunction "GREEN_3") (pintype "bidirectional"))
      (node (ref "U$275") (pin "3") (pinfunction "GREEN_3") (pintype "bidirectional"))
      (node (ref "U$3") (pin "5") (pinfunction "OUT5_5") (pintype "output"))
      (node (ref "U$307") (pin "3") (pinfunction "GREEN_3") (pintype "bidirectional"))
      (node (ref "U$339") (pin "3") (pinfunction "GREEN_3") (pintype "bidirectional"))
      (node (ref "U$371") (pin "3") (pinfunction "GREEN_3") (pintype "bidirectional"))
      (node (ref "U$403") (pin "3") (pinfunction "GREEN_3") (pintype "bidirectional"))
      (node (ref "U$435") (pin "3") (pinfunction "GREEN_3") (pintype "bidirectional"))
      (node (ref "U$467") (pin "3") (pinfunction "GREEN_3") (pintype "bidirectional"))
      (node (ref "U$499") (pin "3") (pinfunction "GREEN_3") (pintype "bidirectional"))
      (node (ref "U$51") (pin "3") (pinfunction "GREEN_3") (pintype "bidirectional"))
      (node (ref "U$83") (pin "3") (pinfunction "GREEN_3") (pintype "bidirectional"))
    )
    (net (code "106") (name "Net-(U$115-RED)") (class "Default")
      (node (ref "U$115") (pin "1") (pinfunction "RED_1") (pintype "bidirectional"))
      (node (ref "U$147") (pin "1") (pinfunction "RED_1") (pintype "bidirectional"))
      (node (ref "U$179") (pin "1") (pinfunction "RED_1") (pintype "bidirectional"))
      (node (ref "U$19") (pin "1") (pinfunction "RED_1") (pintype "bidirectional"))
      (node (ref "U$211") (pin "1") (pinfunction "RED_1") (pintype "bidirectional"))
      (node (ref "U$243") (pin "1") (pinfunction "RED_1") (pintype "bidirectional"))
      (node (ref "U$275") (pin "1") (pinfunction "RED_1") (pintype "bidirectional"))
      (node (ref "U$3") (pin "4") (pinfunction "OUT4_4") (pintype "output"))
      (node (ref "U$307") (pin "1") (pinfunction "RED_1") (pintype "bidirectional"))
      (node (ref "U$339") (pin "1") (pinfunction "RED_1") (pintype "bidirectional"))
      (node (ref "U$371") (pin "1") (pinfunction "RED_1") (pintype "bidirectional"))
      (node (ref "U$403") (pin "1") (pinfunction "RED_1") (pintype "bidirectional"))
      (node (ref "U$435") (pin "1") (pinfunction "RED_1") (pintype "bidirectional"))
      (node (ref "U$467") (pin "1") (pinfunction "RED_1") (pintype "bidirectional"))
      (node (ref "U$499") (pin "1") (pinfunction "RED_1") (pintype "bidirectional"))
      (node (ref "U$51") (pin "1") (pinfunction "RED_1") (pintype "bidirectional"))
      (node (ref "U$83") (pin "1") (pinfunction "RED_1") (pintype "bidirectional"))
    )
    (net (code "107") (name "Net-(U$116-BLUE)") (class "Default")
      (node (ref "U$116") (pin "4") (pinfunction "BLUE_4") (pintype "bidirectional"))
      (node (ref "U$148") (pin "4") (pinfunction "BLUE_4") (pintype "bidirectional"))
      (node (ref "U$180") (pin "4") (pinfunction "BLUE_4") (pintype "bidirectional"))
      (node (ref "U$20") (pin "4") (pinfunction "BLUE_4") (pintype "bidirectional"))
      (node (ref "U$212") (pin "4") (pinfunction "BLUE_4") (pintype "bidirectional"))
      (node (ref "U$244") (pin "4") (pinfunction "BLUE_4") (pintype "bidirectional"))
      (node (ref "U$276") (pin "4") (pinfunction "BLUE_4") (pintype "bidirectional"))
      (node (ref "U$3") (pin "9") (pinfunction "OUT9_9") (pintype "output"))
      (node (ref "U$308") (pin "4") (pinfunction "BLUE_4") (pintype "bidirectional"))
      (node (ref "U$340") (pin "4") (pinfunction "BLUE_4") (pintype "bidirectional"))
      (node (ref "U$372") (pin "4") (pinfunction "BLUE_4") (pintype "bidirectional"))
      (node (ref "U$404") (pin "4") (pinfunction "BLUE_4") (pintype "bidirectional"))
      (node (ref "U$436") (pin "4") (pinfunction "BLUE_4") (pintype "bidirectional"))
      (node (ref "U$468") (pin "4") (pinfunction "BLUE_4") (pintype "bidirectional"))
      (node (ref "U$500") (pin "4") (pinfunction "BLUE_4") (pintype "bidirectional"))
      (node (ref "U$52") (pin "4") (pinfunction "BLUE_4") (pintype "bidirectional"))
      (node (ref "U$84") (pin "4") (pinfunction "BLUE_4") (pintype "bidirectional"))
    )
    (net (code "108") (name "Net-(U$116-GREEN)") (class "Default")
      (node (ref "U$116") (pin "3") (pinfunction "GREEN_3") (pintype "bidirectional"))
      (node (ref "U$148") (pin "3") (pinfunction "GREEN_3") (pintype "bidirectional"))
      (node (ref "U$180") (pin "3") (pinfunction "GREEN_3") (pintype "bidirectional"))
      (node (ref "U$20") (pin "3") (pinfunction "GREEN_3") (pintype "bidirectional"))
      (node (ref "U$212") (pin "3") (pinfunction "GREEN_3") (pintype "bidirectional"))
      (node (ref "U$244") (pin "3") (pinfunction "GREEN_3") (pintype "bidirectional"))
      (node (ref "U$276") (pin "3") (pinfunction "GREEN_3") (pintype "bidirectional"))
      (node (ref "U$3") (pin "8") (pinfunction "OUT8_8") (pintype "output"))
      (node (ref "U$308") (pin "3") (pinfunction "GREEN_3") (pintype "bidirectional"))
      (node (ref "U$340") (pin "3") (pinfunction "GREEN_3") (pintype "bidirectional"))
      (node (ref "U$372") (pin "3") (pinfunction "GREEN_3") (pintype "bidirectional"))
      (node (ref "U$404") (pin "3") (pinfunction "GREEN_3") (pintype "bidirectional"))
      (node (ref "U$436") (pin "3") (pinfunction "GREEN_3") (pintype "bidirectional"))
      (node (ref "U$468") (pin "3") (pinfunction "GREEN_3") (pintype "bidirectional"))
      (node (ref "U$500") (pin "3") (pinfunction "GREEN_3") (pintype "bidirectional"))
      (node (ref "U$52") (pin "3") (pinfunction "GREEN_3") (pintype "bidirectional"))
      (node (ref "U$84") (pin "3") (pinfunction "GREEN_3") (pintype "bidirectional"))
    )
    (net (code "109") (name "Net-(U$116-RED)") (class "Default")
      (node (ref "U$116") (pin "1") (pinfunction "RED_1") (pintype "bidirectional"))
      (node (ref "U$148") (pin "1") (pinfunction "RED_1") (pintype "bidirectional"))
      (node (ref "U$180") (pin "1") (pinfunction "RED_1") (pintype "bidirectional"))
      (node (ref "U$20") (pin "1") (pinfunction "RED_1") (pintype "bidirectional"))
      (node (ref "U$212") (pin "1") (pinfunction "RED_1") (pintype "bidirectional"))
      (node (ref "U$244") (pin "1") (pinfunction "RED_1") (pintype "bidirectional"))
      (node (ref "U$276") (pin "1") (pinfunction "RED_1") (pintype "bidirectional"))
      (node (ref "U$3") (pin "7") (pinfunction "OUT7_7") (pintype "output"))
      (node (ref "U$308") (pin "1") (pinfunction "RED_1") (pintype "bidirectional"))
      (node (ref "U$340") (pin "1") (pinfunction "RED_1") (pintype "bidirectional"))
      (node (ref "U$372") (pin "1") (pinfunction "RED_1") (pintype "bidirectional"))
      (node (ref "U$404") (pin "1") (pinfunction "RED_1") (pintype "bidirectional"))
      (node (ref "U$436") (pin "1") (pinfunction "RED_1") (pintype "bidirectional"))
      (node (ref "U$468") (pin "1") (pinfunction "RED_1") (pintype "bidirectional"))
      (node (ref "U$500") (pin "1") (pinfunction "RED_1") (pintype "bidirectional"))
      (node (ref "U$52") (pin "1") (pinfunction "RED_1") (pintype "bidirectional"))
      (node (ref "U$84") (pin "1") (pinfunction "RED_1") (pintype "bidirectional"))
    )
    (net (code "110") (name "Net-(U$117-BLUE)") (class "Default")
      (node (ref "U$117") (pin "4") (pinfunction "BLUE_4") (pintype "bidirectional"))
      (node (ref "U$149") (pin "4") (pinfunction "BLUE_4") (pintype "bidirectional"))
      (node (ref "U$181") (pin "4") (pinfunction "BLUE_4") (pintype "bidirectional"))
      (node (ref "U$21") (pin "4") (pinfunction "BLUE_4") (pintype "bidirectional"))
      (node (ref "U$213") (pin "4") (pinfunction "BLUE_4") (pintype "bidirectional"))
      (node (ref "U$245") (pin "4") (pinfunction "BLUE_4") (pintype "bidirectional"))
      (node (ref "U$277") (pin "4") (pinfunction "BLUE_4") (pintype "bidirectional"))
      (node (ref "U$3") (pin "12") (pinfunction "OUT12_12") (pintype "output"))
      (node (ref "U$309") (pin "4") (pinfunction "BLUE_4") (pintype "bidirectional"))
      (node (ref "U$341") (pin "4") (pinfunction "BLUE_4") (pintype "bidirectional"))
      (node (ref "U$373") (pin "4") (pinfunction "BLUE_4") (pintype "bidirectional"))
      (node (ref "U$405") (pin "4") (pinfunction "BLUE_4") (pintype "bidirectional"))
      (node (ref "U$437") (pin "4") (pinfunction "BLUE_4") (pintype "bidirectional"))
      (node (ref "U$469") (pin "4") (pinfunction "BLUE_4") (pintype "bidirectional"))
      (node (ref "U$501") (pin "4") (pinfunction "BLUE_4") (pintype "bidirectional"))
      (node (ref "U$53") (pin "4") (pinfunction "BLUE_4") (pintype "bidirectional"))
      (node (ref "U$85") (pin "4") (pinfunction "BLUE_4") (pintype "bidirectional"))
    )
    (net (code "111") (name "Net-(U$117-GREEN)") (class "Default")
      (node (ref "U$117") (pin "3") (pinfunction "GREEN_3") (pintype "bidirectional"))
      (node (ref "U$149") (pin "3") (pinfunction "GREEN_3") (pintype "bidirectional"))
      (node (ref "U$181") (pin "3") (pinfunction "GREEN_3") (pintype "bidirectional"))
      (node (ref "U$21") (pin "3") (pinfunction "GREEN_3") (pintype "bidirectional"))
      (node (ref "U$213") (pin "3") (pinfunction "GREEN_3") (pintype "bidirectional"))
      (node (ref "U$245") (pin "3") (pinfunction "GREEN_3") (pintype "bidirectional"))
      (node (ref "U$277") (pin "3") (pinfunction "GREEN_3") (pintype "bidirectional"))
      (node (ref "U$3") (pin "11") (pinfunction "OUT11_11") (pintype "output"))
      (node (ref "U$309") (pin "3") (pinfunction "GREEN_3") (pintype "bidirectional"))
      (node (ref "U$341") (pin "3") (pinfunction "GREEN_3") (pintype "bidirectional"))
      (node (ref "U$373") (pin "3") (pinfunction "GREEN_3") (pintype "bidirectional"))
      (node (ref "U$405") (pin "3") (pinfunction "GREEN_3") (pintype "bidirectional"))
      (node (ref "U$437") (pin "3") (pinfunction "GREEN_3") (pintype "bidirectional"))
      (node (ref "U$469") (pin "3") (pinfunction "GREEN_3") (pintype "bidirectional"))
      (node (ref "U$501") (pin "3") (pinfunction "GREEN_3") (pintype "bidirectional"))
      (node (ref "U$53") (pin "3") (pinfunction "GREEN_3") (pintype "bidirectional"))
      (node (ref "U$85") (pin "3") (pinfunction "GREEN_3") (pintype "bidirectional"))
    )
    (net (code "112") (name "Net-(U$117-RED)") (class "Default")
      (node (ref "U$117") (pin "1") (pinfunction "RED_1") (pintype "bidirectional"))
      (node (ref "U$149") (pin "1") (pinfunction "RED_1") (pintype "bidirectional"))
      (node (ref "U$181") (pin "1") (pinfunction "RED_1") (pintype "bidirectional"))
      (node (ref "U$21") (pin "1") (pinfunction "RED_1") (pintype "bidirectional"))
      (node (ref "U$213") (pin "1") (pinfunction "RED_1") (pintype "bidirectional"))
      (node (ref "U$245") (pin "1") (pinfunction "RED_1") (pintype "bidirectional"))
      (node (ref "U$277") (pin "1") (pinfunction "RED_1") (pintype "bidirectional"))
      (node (ref "U$3") (pin "10") (pinfunction "OUT10_10") (pintype "output"))
      (node (ref "U$309") (pin "1") (pinfunction "RED_1") (pintype "bidirectional"))
      (node (ref "U$341") (pin "1") (pinfunction "RED_1") (pintype "bidirectional"))
      (node (ref "U$373") (pin "1") (pinfunction "RED_1") (pintype "bidirectional"))
      (node (ref "U$405") (pin "1") (pinfunction "RED_1") (pintype "bidirectional"))
      (node (ref "U$437") (pin "1") (pinfunction "RED_1") (pintype "bidirectional"))
      (node (ref "U$469") (pin "1") (pinfunction "RED_1") (pintype "bidirectional"))
      (node (ref "U$501") (pin "1") (pinfunction "RED_1") (pintype "bidirectional"))
      (node (ref "U$53") (pin "1") (pinfunction "RED_1") (pintype "bidirectional"))
      (node (ref "U$85") (pin "1") (pinfunction "RED_1") (pintype "bidirectional"))
    )
    (net (code "113") (name "Net-(U$118-BLUE)") (class "Default")
      (node (ref "U$118") (pin "4") (pinfunction "BLUE_4") (pintype "bidirectional"))
      (node (ref "U$150") (pin "4") (pinfunction "BLUE_4") (pintype "bidirectional"))
      (node (ref "U$182") (pin "4") (pinfunction "BLUE_4") (pintype "bidirectional"))
      (node (ref "U$214") (pin "4") (pinfunction "BLUE_4") (pintype "bidirectional"))
      (node (ref "U$22") (pin "4") (pinfunction "BLUE_4") (pintype "bidirectional"))
      (node (ref "U$246") (pin "4") (pinfunction "BLUE_4") (pintype "bidirectional"))
      (node (ref "U$278") (pin "4") (pinfunction "BLUE_4") (pintype "bidirectional"))
      (node (ref "U$3") (pin "15") (pinfunction "OUT15_15") (pintype "output"))
      (node (ref "U$310") (pin "4") (pinfunction "BLUE_4") (pintype "bidirectional"))
      (node (ref "U$342") (pin "4") (pinfunction "BLUE_4") (pintype "bidirectional"))
      (node (ref "U$374") (pin "4") (pinfunction "BLUE_4") (pintype "bidirectional"))
      (node (ref "U$406") (pin "4") (pinfunction "BLUE_4") (pintype "bidirectional"))
      (node (ref "U$438") (pin "4") (pinfunction "BLUE_4") (pintype "bidirectional"))
      (node (ref "U$470") (pin "4") (pinfunction "BLUE_4") (pintype "bidirectional"))
      (node (ref "U$502") (pin "4") (pinfunction "BLUE_4") (pintype "bidirectional"))
      (node (ref "U$54") (pin "4") (pinfunction "BLUE_4") (pintype "bidirectional"))
      (node (ref "U$86") (pin "4") (pinfunction "BLUE_4") (pintype "bidirectional"))
    )
    (net (code "114") (name "Net-(U$118-GREEN)") (class "Default")
      (node (ref "U$118") (pin "3") (pinfunction "GREEN_3") (pintype "bidirectional"))
      (node (ref "U$150") (pin "3") (pinfunction "GREEN_3") (pintype "bidirectional"))
      (node (ref "U$182") (pin "3") (pinfunction "GREEN_3") (pintype "bidirectional"))
      (node (ref "U$214") (pin "3") (pinfunction "GREEN_3") (pintype "bidirectional"))
      (node (ref "U$22") (pin "3") (pinfunction "GREEN_3") (pintype "bidirectional"))
      (node (ref "U$246") (pin "3") (pinfunction "GREEN_3") (pintype "bidirectional"))
      (node (ref "U$278") (pin "3") (pinfunction "GREEN_3") (pintype "bidirectional"))
      (node (ref "U$3") (pin "14") (pinfunction "OUT14_14") (pintype "output"))
      (node (ref "U$310") (pin "3") (pinfunction "GREEN_3") (pintype "bidirectional"))
      (node (ref "U$342") (pin "3") (pinfunction "GREEN_3") (pintype "bidirectional"))
      (node (ref "U$374") (pin "3") (pinfunction "GREEN_3") (pintype "bidirectional"))
      (node (ref "U$406") (pin "3") (pinfunction "GREEN_3") (pintype "bidirectional"))
      (node (ref "U$438") (pin "3") (pinfunction "GREEN_3") (pintype "bidirectional"))
      (node (ref "U$470") (pin "3") (pinfunction "GREEN_3") (pintype "bidirectional"))
      (node (ref "U$502") (pin "3") (pinfunction "GREEN_3") (pintype "bidirectional"))
      (node (ref "U$54") (pin "3") (pinfunction "GREEN_3") (pintype "bidirectional"))
      (node (ref "U$86") (pin "3") (pinfunction "GREEN_3") (pintype "bidirectional"))
    )
    (net (code "115") (name "Net-(U$118-RED)") (class "Default")
      (node (ref "U$118") (pin "1") (pinfunction "RED_1") (pintype "bidirectional"))
      (node (ref "U$150") (pin "1") (pinfunction "RED_1") (pintype "bidirectional"))
      (node (ref "U$182") (pin "1") (pinfunction "RED_1") (pintype "bidirectional"))
      (node (ref "U$214") (pin "1") (pinfunction "RED_1") (pintype "bidirectional"))
      (node (ref "U$22") (pin "1") (pinfunction "RED_1") (pintype "bidirectional"))
      (node (ref "U$246") (pin "1") (pinfunction "RED_1") (pintype "bidirectional"))
      (node (ref "U$278") (pin "1") (pinfunction "RED_1") (pintype "bidirectional"))
      (node (ref "U$3") (pin "13") (pinfunction "OUT13_13") (pintype "output"))
      (node (ref "U$310") (pin "1") (pinfunction "RED_1") (pintype "bidirectional"))
      (node (ref "U$342") (pin "1") (pinfunction "RED_1") (pintype "bidirectional"))
      (node (ref "U$374") (pin "1") (pinfunction "RED_1") (pintype "bidirectional"))
      (node (ref "U$406") (pin "1") (pinfunction "RED_1") (pintype "bidirectional"))
      (node (ref "U$438") (pin "1") (pinfunction "RED_1") (pintype "bidirectional"))
      (node (ref "U$470") (pin "1") (pinfunction "RED_1") (pintype "bidirectional"))
      (node (ref "U$502") (pin "1") (pinfunction "RED_1") (pintype "bidirectional"))
      (node (ref "U$54") (pin "1") (pinfunction "RED_1") (pintype "bidirectional"))
      (node (ref "U$86") (pin "1") (pinfunction "RED_1") (pintype "bidirectional"))
    )
    (net (code "116") (name "Net-(U$119-BLUE)") (class "Default")
      (node (ref "U$119") (pin "4") (pinfunction "BLUE_4") (pintype "bidirectional"))
      (node (ref "U$151") (pin "4") (pinfunction "BLUE_4") (pintype "bidirectional"))
      (node (ref "U$183") (pin "4") (pinfunction "BLUE_4") (pintype "bidirectional"))
      (node (ref "U$215") (pin "4") (pinfunction "BLUE_4") (pintype "bidirectional"))
      (node (ref "U$23") (pin "4") (pinfunction "BLUE_4") (pintype "bidirectional"))
      (node (ref "U$247") (pin "4") (pinfunction "BLUE_4") (pintype "bidirectional"))
      (node (ref "U$279") (pin "4") (pinfunction "BLUE_4") (pintype "bidirectional"))
      (node (ref "U$311") (pin "4") (pinfunction "BLUE_4") (pintype "bidirectional"))
      (node (ref "U$343") (pin "4") (pinfunction "BLUE_4") (pintype "bidirectional"))
      (node (ref "U$375") (pin "4") (pinfunction "BLUE_4") (pintype "bidirectional"))
      (node (ref "U$4") (pin "2") (pinfunction "OUT2_2") (pintype "output"))
      (node (ref "U$407") (pin "4") (pinfunction "BLUE_4") (pintype "bidirectional"))
      (node (ref "U$439") (pin "4") (pinfunction "BLUE_4") (pintype "bidirectional"))
      (node (ref "U$471") (pin "4") (pinfunction "BLUE_4") (pintype "bidirectional"))
      (node (ref "U$503") (pin "4") (pinfunction "BLUE_4") (pintype "bidirectional"))
      (node (ref "U$55") (pin "4") (pinfunction "BLUE_4") (pintype "bidirectional"))
      (node (ref "U$87") (pin "4") (pinfunction "BLUE_4") (pintype "bidirectional"))
    )
    (net (code "117") (name "Net-(U$119-GREEN)") (class "Default")
      (node (ref "U$119") (pin "3") (pinfunction "GREEN_3") (pintype "bidirectional"))
      (node (ref "U$151") (pin "3") (pinfunction "GREEN_3") (pintype "bidirectional"))
      (node (ref "U$183") (pin "3") (pinfunction "GREEN_3") (pintype "bidirectional"))
      (node (ref "U$215") (pin "3") (pinfunction "GREEN_3") (pintype "bidirectional"))
      (node (ref "U$23") (pin "3") (pinfunction "GREEN_3") (pintype "bidirectional"))
      (node (ref "U$247") (pin "3") (pinfunction "GREEN_3") (pintype "bidirectional"))
      (node (ref "U$279") (pin "3") (pinfunction "GREEN_3") (pintype "bidirectional"))
      (node (ref "U$311") (pin "3") (pinfunction "GREEN_3") (pintype "bidirectional"))
      (node (ref "U$343") (pin "3") (pinfunction "GREEN_3") (pintype "bidirectional"))
      (node (ref "U$375") (pin "3") (pinfunction "GREEN_3") (pintype "bidirectional"))
      (node (ref "U$4") (pin "1") (pinfunction "OUT1_1") (pintype "output"))
      (node (ref "U$407") (pin "3") (pinfunction "GREEN_3") (pintype "bidirectional"))
      (node (ref "U$439") (pin "3") (pinfunction "GREEN_3") (pintype "bidirectional"))
      (node (ref "U$471") (pin "3") (pinfunction "GREEN_3") (pintype "bidirectional"))
      (node (ref "U$503") (pin "3") (pinfunction "GREEN_3") (pintype "bidirectional"))
      (node (ref "U$55") (pin "3") (pinfunction "GREEN_3") (pintype "bidirectional"))
      (node (ref "U$87") (pin "3") (pinfunction "GREEN_3") (pintype "bidirectional"))
    )
    (net (code "118") (name "Net-(U$119-RED)") (class "Default")
      (node (ref "U$119") (pin "1") (pinfunction "RED_1") (pintype "bidirectional"))
      (node (ref "U$151") (pin "1") (pinfunction "RED_1") (pintype "bidirectional"))
      (node (ref "U$183") (pin "1") (pinfunction "RED_1") (pintype "bidirectional"))
      (node (ref "U$215") (pin "1") (pinfunction "RED_1") (pintype "bidirectional"))
      (node (ref "U$23") (pin "1") (pinfunction "RED_1") (pintype "bidirectional"))
      (node (ref "U$247") (pin "1") (pinfunction "RED_1") (pintype "bidirectional"))
      (node (ref "U$279") (pin "1") (pinfunction "RED_1") (pintype "bidirectional"))
      (node (ref "U$311") (pin "1") (pinfunction "RED_1") (pintype "bidirectional"))
      (node (ref "U$343") (pin "1") (pinfunction "RED_1") (pintype "bidirectional"))
      (node (ref "U$375") (pin "1") (pinfunction "RED_1") (pintype "bidirectional"))
      (node (ref "U$4") (pin "28") (pinfunction "OUT0_28") (pintype "output"))
      (node (ref "U$407") (pin "1") (pinfunction "RED_1") (pintype "bidirectional"))
      (node (ref "U$439") (pin "1") (pinfunction "RED_1") (pintype "bidirectional"))
      (node (ref "U$471") (pin "1") (pinfunction "RED_1") (pintype "bidirectional"))
      (node (ref "U$503") (pin "1") (pinfunction "RED_1") (pintype "bidirectional"))
      (node (ref "U$55") (pin "1") (pinfunction "RED_1") (pintype "bidirectional"))
      (node (ref "U$87") (pin "1") (pinfunction "RED_1") (pintype "bidirectional"))
    )
    (net (code "119") (name "Net-(U$120-BLUE)") (class "Default")
      (node (ref "U$120") (pin "4") (pinfunction "BLUE_4") (pintype "bidirectional"))
      (node (ref "U$152") (pin "4") (pinfunction "BLUE_4") (pintype "bidirectional"))
      (node (ref "U$184") (pin "4") (pinfunction "BLUE_4") (pintype "bidirectional"))
      (node (ref "U$216") (pin "4") (pinfunction "BLUE_4") (pintype "bidirectional"))
      (node (ref "U$24") (pin "4") (pinfunction "BLUE_4") (pintype "bidirectional"))
      (node (ref "U$248") (pin "4") (pinfunction "BLUE_4") (pintype "bidirectional"))
      (node (ref "U$280") (pin "4") (pinfunction "BLUE_4") (pintype "bidirectional"))
      (node (ref "U$312") (pin "4") (pinfunction "BLUE_4") (pintype "bidirectional"))
      (node (ref "U$344") (pin "4") (pinfunction "BLUE_4") (pintype "bidirectional"))
      (node (ref "U$376") (pin "4") (pinfunction "BLUE_4") (pintype "bidirectional"))
      (node (ref "U$4") (pin "5") (pinfunction "OUT5_5") (pintype "output"))
      (node (ref "U$408") (pin "4") (pinfunction "BLUE_4") (pintype "bidirectional"))
      (node (ref "U$440") (pin "4") (pinfunction "BLUE_4") (pintype "bidirectional"))
      (node (ref "U$472") (pin "4") (pinfunction "BLUE_4") (pintype "bidirectional"))
      (node (ref "U$504") (pin "4") (pinfunction "BLUE_4") (pintype "bidirectional"))
      (node (ref "U$56") (pin "4") (pinfunction "BLUE_4") (pintype "bidirectional"))
      (node (ref "U$88") (pin "4") (pinfunction "BLUE_4") (pintype "bidirectional"))
    )
    (net (code "120") (name "Net-(U$120-GREEN)") (class "Default")
      (node (ref "U$120") (pin "3") (pinfunction "GREEN_3") (pintype "bidirectional"))
      (node (ref "U$152") (pin "3") (pinfunction "GREEN_3") (pintype "bidirectional"))
      (node (ref "U$184") (pin "3") (pinfunction "GREEN_3") (pintype "bidirectional"))
      (node (ref "U$216") (pin "3") (pinfunction "GREEN_3") (pintype "bidirectional"))
      (node (ref "U$24") (pin "3") (pinfunction "GREEN_3") (pintype "bidirectional"))
      (node (ref "U$248") (pin "3") (pinfunction "GREEN_3") (pintype "bidirectional"))
      (node (ref "U$280") (pin "3") (pinfunction "GREEN_3") (pintype "bidirectional"))
      (node (ref "U$312") (pin "3") (pinfunction "GREEN_3") (pintype "bidirectional"))
      (node (ref "U$344") (pin "3") (pinfunction "GREEN_3") (pintype "bidirectional"))
      (node (ref "U$376") (pin "3") (pinfunction "GREEN_3") (pintype "bidirectional"))
      (node (ref "U$4") (pin "4") (pinfunction "OUT4_4") (pintype "output"))
      (node (ref "U$408") (pin "3") (pinfunction "GREEN_3") (pintype "bidirectional"))
      (node (ref "U$440") (pin "3") (pinfunction "GREEN_3") (pintype "bidirectional"))
      (node (ref "U$472") (pin "3") (pinfunction "GREEN_3") (pintype "bidirectional"))
      (node (ref "U$504") (pin "3") (pinfunction "GREEN_3") (pintype "bidirectional"))
      (node (ref "U$56") (pin "3") (pinfunction "GREEN_3") (pintype "bidirectional"))
      (node (ref "U$88") (pin "3") (pinfunction "GREEN_3") (pintype "bidirectional"))
    )
    (net (code "121") (name "Net-(U$120-RED)") (class "Default")
      (node (ref "U$120") (pin "1") (pinfunction "RED_1") (pintype "bidirectional"))
      (node (ref "U$152") (pin "1") (pinfunction "RED_1") (pintype "bidirectional"))
      (node (ref "U$184") (pin "1") (pinfunction "RED_1") (pintype "bidirectional"))
      (node (ref "U$216") (pin "1") (pinfunction "RED_1") (pintype "bidirectional"))
      (node (ref "U$24") (pin "1") (pinfunction "RED_1") (pintype "bidirectional"))
      (node (ref "U$248") (pin "1") (pinfunction "RED_1") (pintype "bidirectional"))
      (node (ref "U$280") (pin "1") (pinfunction "RED_1") (pintype "bidirectional"))
      (node (ref "U$312") (pin "1") (pinfunction "RED_1") (pintype "bidirectional"))
      (node (ref "U$344") (pin "1") (pinfunction "RED_1") (pintype "bidirectional"))
      (node (ref "U$376") (pin "1") (pinfunction "RED_1") (pintype "bidirectional"))
      (node (ref "U$4") (pin "3") (pinfunction "OUT3_3") (pintype "output"))
      (node (ref "U$408") (pin "1") (pinfunction "RED_1") (pintype "bidirectional"))
      (node (ref "U$440") (pin "1") (pinfunction "RED_1") (pintype "bidirectional"))
      (node (ref "U$472") (pin "1") (pinfunction "RED_1") (pintype "bidirectional"))
      (node (ref "U$504") (pin "1") (pinfunction "RED_1") (pintype "bidirectional"))
      (node (ref "U$56") (pin "1") (pinfunction "RED_1") (pintype "bidirectional"))
      (node (ref "U$88") (pin "1") (pinfunction "RED_1") (pintype "bidirectional"))
    )
    (net (code "122") (name "Net-(U$121-BLUE)") (class "Default")
      (node (ref "U$121") (pin "4") (pinfunction "BLUE_4") (pintype "bidirectional"))
      (node (ref "U$153") (pin "4") (pinfunction "BLUE_4") (pintype "bidirectional"))
      (node (ref "U$185") (pin "4") (pinfunction "BLUE_4") (pintype "bidirectional"))
      (node (ref "U$217") (pin "4") (pinfunction "BLUE_4") (pintype "bidirectional"))
      (node (ref "U$249") (pin "4") (pinfunction "BLUE_4") (pintype "bidirectional"))
      (node (ref "U$25") (pin "4") (pinfunction "BLUE_4") (pintype "bidirectional"))
      (node (ref "U$281") (pin "4") (pinfunction "BLUE_4") (pintype "bidirectional"))
      (node (ref "U$313") (pin "4") (pinfunction "BLUE_4") (pintype "bidirectional"))
      (node (ref "U$345") (pin "4") (pinfunction "BLUE_4") (pintype "bidirectional"))
      (node (ref "U$377") (pin "4") (pinfunction "BLUE_4") (pintype "bidirectional"))
      (node (ref "U$4") (pin "8") (pinfunction "OUT8_8") (pintype "output"))
      (node (ref "U$409") (pin "4") (pinfunction "BLUE_4") (pintype "bidirectional"))
      (node (ref "U$441") (pin "4") (pinfunction "BLUE_4") (pintype "bidirectional"))
      (node (ref "U$473") (pin "4") (pinfunction "BLUE_4") (pintype "bidirectional"))
      (node (ref "U$505") (pin "4") (pinfunction "BLUE_4") (pintype "bidirectional"))
      (node (ref "U$57") (pin "4") (pinfunction "BLUE_4") (pintype "bidirectional"))
      (node (ref "U$89") (pin "4") (pinfunction "BLUE_4") (pintype "bidirectional"))
    )
    (net (code "123") (name "Net-(U$121-GREEN)") (class "Default")
      (node (ref "U$121") (pin "3") (pinfunction "GREEN_3") (pintype "bidirectional"))
      (node (ref "U$153") (pin "3") (pinfunction "GREEN_3") (pintype "bidirectional"))
      (node (ref "U$185") (pin "3") (pinfunction "GREEN_3") (pintype "bidirectional"))
      (node (ref "U$217") (pin "3") (pinfunction "GREEN_3") (pintype "bidirectional"))
      (node (ref "U$249") (pin "3") (pinfunction "GREEN_3") (pintype "bidirectional"))
      (node (ref "U$25") (pin "3") (pinfunction "GREEN_3") (pintype "bidirectional"))
      (node (ref "U$281") (pin "3") (pinfunction "GREEN_3") (pintype "bidirectional"))
      (node (ref "U$313") (pin "3") (pinfunction "GREEN_3") (pintype "bidirectional"))
      (node (ref "U$345") (pin "3") (pinfunction "GREEN_3") (pintype "bidirectional"))
      (node (ref "U$377") (pin "3") (pinfunction "GREEN_3") (pintype "bidirectional"))
      (node (ref "U$4") (pin "7") (pinfunction "OUT7_7") (pintype "output"))
      (node (ref "U$409") (pin "3") (pinfunction "GREEN_3") (pintype "bidirectional"))
      (node (ref "U$441") (pin "3") (pinfunction "GREEN_3") (pintype "bidirectional"))
      (node (ref "U$473") (pin "3") (pinfunction "GREEN_3") (pintype "bidirectional"))
      (node (ref "U$505") (pin "3") (pinfunction "GREEN_3") (pintype "bidirectional"))
      (node (ref "U$57") (pin "3") (pinfunction "GREEN_3") (pintype "bidirectional"))
      (node (ref "U$89") (pin "3") (pinfunction "GREEN_3") (pintype "bidirectional"))
    )
    (net (code "124") (name "Net-(U$121-RED)") (class "Default")
      (node (ref "U$121") (pin "1") (pinfunction "RED_1") (pintype "bidirectional"))
      (node (ref "U$153") (pin "1") (pinfunction "RED_1") (pintype "bidirectional"))
      (node (ref "U$185") (pin "1") (pinfunction "RED_1") (pintype "bidirectional"))
      (node (ref "U$217") (pin "1") (pinfunction "RED_1") (pintype "bidirectional"))
      (node (ref "U$249") (pin "1") (pinfunction "RED_1") (pintype "bidirectional"))
      (node (ref "U$25") (pin "1") (pinfunction "RED_1") (pintype "bidirectional"))
      (node (ref "U$281") (pin "1") (pinfunction "RED_1") (pintype "bidirectional"))
      (node (ref "U$313") (pin "1") (pinfunction "RED_1") (pintype "bidirectional"))
      (node (ref "U$345") (pin "1") (pinfunction "RED_1") (pintype "bidirectional"))
      (node (ref "U$377") (pin "1") (pinfunction "RED_1") (pintype "bidirectional"))
      (node (ref "U$4") (pin "6") (pinfunction "OUT6_6") (pintype "output"))
      (node (ref "U$409") (pin "1") (pinfunction "RED_1") (pintype "bidirectional"))
      (node (ref "U$441") (pin "1") (pinfunction "RED_1") (pintype "bidirectional"))
      (node (ref "U$473") (pin "1") (pinfunction "RED_1") (pintype "bidirectional"))
      (node (ref "U$505") (pin "1") (pinfunction "RED_1") (pintype "bidirectional"))
      (node (ref "U$57") (pin "1") (pinfunction "RED_1") (pintype "bidirectional"))
      (node (ref "U$89") (pin "1") (pinfunction "RED_1") (pintype "bidirectional"))
    )
    (net (code "125") (name "Net-(U$122-BLUE)") (class "Default")
      (node (ref "U$122") (pin "4") (pinfunction "BLUE_4") (pintype "bidirectional"))
      (node (ref "U$154") (pin "4") (pinfunction "BLUE_4") (pintype "bidirectional"))
      (node (ref "U$186") (pin "4") (pinfunction "BLUE_4") (pintype "bidirectional"))
      (node (ref "U$218") (pin "4") (pinfunction "BLUE_4") (pintype "bidirectional"))
      (node (ref "U$250") (pin "4") (pinfunction "BLUE_4") (pintype "bidirectional"))
      (node (ref "U$26") (pin "4") (pinfunction "BLUE_4") (pintype "bidirectional"))
      (node (ref "U$282") (pin "4") (pinfunction "BLUE_4") (pintype "bidirectional"))
      (node (ref "U$314") (pin "4") (pinfunction "BLUE_4") (pintype "bidirectional"))
      (node (ref "U$346") (pin "4") (pinfunction "BLUE_4") (pintype "bidirectional"))
      (node (ref "U$378") (pin "4") (pinfunction "BLUE_4") (pintype "bidirectional"))
      (node (ref "U$4") (pin "11") (pinfunction "OUT11_11") (pintype "output"))
      (node (ref "U$410") (pin "4") (pinfunction "BLUE_4") (pintype "bidirectional"))
      (node (ref "U$442") (pin "4") (pinfunction "BLUE_4") (pintype "bidirectional"))
      (node (ref "U$474") (pin "4") (pinfunction "BLUE_4") (pintype "bidirectional"))
      (node (ref "U$506") (pin "4") (pinfunction "BLUE_4") (pintype "bidirectional"))
      (node (ref "U$58") (pin "4") (pinfunction "BLUE_4") (pintype "bidirectional"))
      (node (ref "U$90") (pin "4") (pinfunction "BLUE_4") (pintype "bidirectional"))
    )
    (net (code "126") (name "Net-(U$122-GREEN)") (class "Default")
      (node (ref "U$122") (pin "3") (pinfunction "GREEN_3") (pintype "bidirectional"))
      (node (ref "U$154") (pin "3") (pinfunction "GREEN_3") (pintype "bidirectional"))
      (node (ref "U$186") (pin "3") (pinfunction "GREEN_3") (pintype "bidirectional"))
      (node (ref "U$218") (pin "3") (pinfunction "GREEN_3") (pintype "bidirectional"))
      (node (ref "U$250") (pin "3") (pinfunction "GREEN_3") (pintype "bidirectional"))
      (node (ref "U$26") (pin "3") (pinfunction "GREEN_3") (pintype "bidirectional"))
      (node (ref "U$282") (pin "3") (pinfunction "GREEN_3") (pintype "bidirectional"))
      (node (ref "U$314") (pin "3") (pinfunction "GREEN_3") (pintype "bidirectional"))
      (node (ref "U$346") (pin "3") (pinfunction "GREEN_3") (pintype "bidirectional"))
      (node (ref "U$378") (pin "3") (pinfunction "GREEN_3") (pintype "bidirectional"))
      (node (ref "U$4") (pin "10") (pinfunction "OUT10_10") (pintype "output"))
      (node (ref "U$410") (pin "3") (pinfunction "GREEN_3") (pintype "bidirectional"))
      (node (ref "U$442") (pin "3") (pinfunction "GREEN_3") (pintype "bidirectional"))
      (node (ref "U$474") (pin "3") (pinfunction "GREEN_3") (pintype "bidirectional"))
      (node (ref "U$506") (pin "3") (pinfunction "GREEN_3") (pintype "bidirectional"))
      (node (ref "U$58") (pin "3") (pinfunction "GREEN_3") (pintype "bidirectional"))
      (node (ref "U$90") (pin "3") (pinfunction "GREEN_3") (pintype "bidirectional"))
    )
    (net (code "127") (name "Net-(U$122-RED)") (class "Default")
      (node (ref "U$122") (pin "1") (pinfunction "RED_1") (pintype "bidirectional"))
      (node (ref "U$154") (pin "1") (pinfunction "RED_1") (pintype "bidirectional"))
      (node (ref "U$186") (pin "1") (pinfunction "RED_1") (pintype "bidirectional"))
      (node (ref "U$218") (pin "1") (pinfunction "RED_1") (pintype "bidirectional"))
      (node (ref "U$250") (pin "1") (pinfunction "RED_1") (pintype "bidirectional"))
      (node (ref "U$26") (pin "1") (pinfunction "RED_1") (pintype "bidirectional"))
      (node (ref "U$282") (pin "1") (pinfunction "RED_1") (pintype "bidirectional"))
      (node (ref "U$314") (pin "1") (pinfunction "RED_1") (pintype "bidirectional"))
      (node (ref "U$346") (pin "1") (pinfunction "RED_1") (pintype "bidirectional"))
      (node (ref "U$378") (pin "1") (pinfunction "RED_1") (pintype "bidirectional"))
      (node (ref "U$4") (pin "9") (pinfunction "OUT9_9") (pintype "output"))
      (node (ref "U$410") (pin "1") (pinfunction "RED_1") (pintype "bidirectional"))
      (node (ref "U$442") (pin "1") (pinfunction "RED_1") (pintype "bidirectional"))
      (node (ref "U$474") (pin "1") (pinfunction "RED_1") (pintype "bidirectional"))
      (node (ref "U$506") (pin "1") (pinfunction "RED_1") (pintype "bidirectional"))
      (node (ref "U$58") (pin "1") (pinfunction "RED_1") (pintype "bidirectional"))
      (node (ref "U$90") (pin "1") (pinfunction "RED_1") (pintype "bidirectional"))
    )
    (net (code "128") (name "Net-(U$123-BLUE)") (class "Default")
      (node (ref "U$123") (pin "4") (pinfunction "BLUE_4") (pintype "bidirectional"))
      (node (ref "U$155") (pin "4") (pinfunction "BLUE_4") (pintype "bidirectional"))
      (node (ref "U$187") (pin "4") (pinfunction "BLUE_4") (pintype "bidirectional"))
      (node (ref "U$219") (pin "4") (pinfunction "BLUE_4") (pintype "bidirectional"))
      (node (ref "U$251") (pin "4") (pinfunction "BLUE_4") (pintype "bidirectional"))
      (node (ref "U$27") (pin "4") (pinfunction "BLUE_4") (pintype "bidirectional"))
      (node (ref "U$283") (pin "4") (pinfunction "BLUE_4") (pintype "bidirectional"))
      (node (ref "U$315") (pin "4") (pinfunction "BLUE_4") (pintype "bidirectional"))
      (node (ref "U$347") (pin "4") (pinfunction "BLUE_4") (pintype "bidirectional"))
      (node (ref "U$379") (pin "4") (pinfunction "BLUE_4") (pintype "bidirectional"))
      (node (ref "U$4") (pin "14") (pinfunction "OUT14_14") (pintype "output"))
      (node (ref "U$411") (pin "4") (pinfunction "BLUE_4") (pintype "bidirectional"))
      (node (ref "U$443") (pin "4") (pinfunction "BLUE_4") (pintype "bidirectional"))
      (node (ref "U$475") (pin "4") (pinfunction "BLUE_4") (pintype "bidirectional"))
      (node (ref "U$507") (pin "4") (pinfunction "BLUE_4") (pintype "bidirectional"))
      (node (ref "U$59") (pin "4") (pinfunction "BLUE_4") (pintype "bidirectional"))
      (node (ref "U$91") (pin "4") (pinfunction "BLUE_4") (pintype "bidirectional"))
    )
    (net (code "129") (name "Net-(U$123-GREEN)") (class "Default")
      (node (ref "U$123") (pin "3") (pinfunction "GREEN_3") (pintype "bidirectional"))
      (node (ref "U$155") (pin "3") (pinfunction "GREEN_3") (pintype "bidirectional"))
      (node (ref "U$187") (pin "3") (pinfunction "GREEN_3") (pintype "bidirectional"))
      (node (ref "U$219") (pin "3") (pinfunction "GREEN_3") (pintype "bidirectional"))
      (node (ref "U$251") (pin "3") (pinfunction "GREEN_3") (pintype "bidirectional"))
      (node (ref "U$27") (pin "3") (pinfunction "GREEN_3") (pintype "bidirectional"))
      (node (ref "U$283") (pin "3") (pinfunction "GREEN_3") (pintype "bidirectional"))
      (node (ref "U$315") (pin "3") (pinfunction "GREEN_3") (pintype "bidirectional"))
      (node (ref "U$347") (pin "3") (pinfunction "GREEN_3") (pintype "bidirectional"))
      (node (ref "U$379") (pin "3") (pinfunction "GREEN_3") (pintype "bidirectional"))
      (node (ref "U$4") (pin "13") (pinfunction "OUT13_13") (pintype "output"))
      (node (ref "U$411") (pin "3") (pinfunction "GREEN_3") (pintype "bidirectional"))
      (node (ref "U$443") (pin "3") (pinfunction "GREEN_3") (pintype "bidirectional"))
      (node (ref "U$475") (pin "3") (pinfunction "GREEN_3") (pintype "bidirectional"))
      (node (ref "U$507") (pin "3") (pinfunction "GREEN_3") (pintype "bidirectional"))
      (node (ref "U$59") (pin "3") (pinfunction "GREEN_3") (pintype "bidirectional"))
      (node (ref "U$91") (pin "3") (pinfunction "GREEN_3") (pintype "bidirectional"))
    )
    (net (code "130") (name "Net-(U$123-RED)") (class "Default")
      (node (ref "U$123") (pin "1") (pinfunction "RED_1") (pintype "bidirectional"))
      (node (ref "U$155") (pin "1") (pinfunction "RED_1") (pintype "bidirectional"))
      (node (ref "U$187") (pin "1") (pinfunction "RED_1") (pintype "bidirectional"))
      (node (ref "U$219") (pin "1") (pinfunction "RED_1") (pintype "bidirectional"))
      (node (ref "U$251") (pin "1") (pinfunction "RED_1") (pintype "bidirectional"))
      (node (ref "U$27") (pin "1") (pinfunction "RED_1") (pintype "bidirectional"))
      (node (ref "U$283") (pin "1") (pinfunction "RED_1") (pintype "bidirectional"))
      (node (ref "U$315") (pin "1") (pinfunction "RED_1") (pintype "bidirectional"))
      (node (ref "U$347") (pin "1") (pinfunction "RED_1") (pintype "bidirectional"))
      (node (ref "U$379") (pin "1") (pinfunction "RED_1") (pintype "bidirectional"))
      (node (ref "U$4") (pin "12") (pinfunction "OUT12_12") (pintype "output"))
      (node (ref "U$411") (pin "1") (pinfunction "RED_1") (pintype "bidirectional"))
      (node (ref "U$443") (pin "1") (pinfunction "RED_1") (pintype "bidirectional"))
      (node (ref "U$475") (pin "1") (pinfunction "RED_1") (pintype "bidirectional"))
      (node (ref "U$507") (pin "1") (pinfunction "RED_1") (pintype "bidirectional"))
      (node (ref "U$59") (pin "1") (pinfunction "RED_1") (pintype "bidirectional"))
      (node (ref "U$91") (pin "1") (pinfunction "RED_1") (pintype "bidirectional"))
    )
    (net (code "131") (name "Net-(U$124-BLUE)") (class "Default")
      (node (ref "U$124") (pin "4") (pinfunction "BLUE_4") (pintype "bidirectional"))
      (node (ref "U$156") (pin "4") (pinfunction "BLUE_4") (pintype "bidirectional"))
      (node (ref "U$188") (pin "4") (pinfunction "BLUE_4") (pintype "bidirectional"))
      (node (ref "U$220") (pin "4") (pinfunction "BLUE_4") (pintype "bidirectional"))
      (node (ref "U$252") (pin "4") (pinfunction "BLUE_4") (pintype "bidirectional"))
      (node (ref "U$28") (pin "4") (pinfunction "BLUE_4") (pintype "bidirectional"))
      (node (ref "U$284") (pin "4") (pinfunction "BLUE_4") (pintype "bidirectional"))
      (node (ref "U$316") (pin "4") (pinfunction "BLUE_4") (pintype "bidirectional"))
      (node (ref "U$348") (pin "4") (pinfunction "BLUE_4") (pintype "bidirectional"))
      (node (ref "U$380") (pin "4") (pinfunction "BLUE_4") (pintype "bidirectional"))
      (node (ref "U$412") (pin "4") (pinfunction "BLUE_4") (pintype "bidirectional"))
      (node (ref "U$444") (pin "4") (pinfunction "BLUE_4") (pintype "bidirectional"))
      (node (ref "U$476") (pin "4") (pinfunction "BLUE_4") (pintype "bidirectional"))
      (node (ref "U$5") (pin "1") (pinfunction "OUT1_1") (pintype "output"))
      (node (ref "U$508") (pin "4") (pinfunction "BLUE_4") (pintype "bidirectional"))
      (node (ref "U$60") (pin "4") (pinfunction "BLUE_4") (pintype "bidirectional"))
      (node (ref "U$92") (pin "4") (pinfunction "BLUE_4") (pintype "bidirectional"))
    )
    (net (code "132") (name "Net-(U$124-GREEN)") (class "Default")
      (node (ref "U$124") (pin "3") (pinfunction "GREEN_3") (pintype "bidirectional"))
      (node (ref "U$156") (pin "3") (pinfunction "GREEN_3") (pintype "bidirectional"))
      (node (ref "U$188") (pin "3") (pinfunction "GREEN_3") (pintype "bidirectional"))
      (node (ref "U$220") (pin "3") (pinfunction "GREEN_3") (pintype "bidirectional"))
      (node (ref "U$252") (pin "3") (pinfunction "GREEN_3") (pintype "bidirectional"))
      (node (ref "U$28") (pin "3") (pinfunction "GREEN_3") (pintype "bidirectional"))
      (node (ref "U$284") (pin "3") (pinfunction "GREEN_3") (pintype "bidirectional"))
      (node (ref "U$316") (pin "3") (pinfunction "GREEN_3") (pintype "bidirectional"))
      (node (ref "U$348") (pin "3") (pinfunction "GREEN_3") (pintype "bidirectional"))
      (node (ref "U$380") (pin "3") (pinfunction "GREEN_3") (pintype "bidirectional"))
      (node (ref "U$412") (pin "3") (pinfunction "GREEN_3") (pintype "bidirectional"))
      (node (ref "U$444") (pin "3") (pinfunction "GREEN_3") (pintype "bidirectional"))
      (node (ref "U$476") (pin "3") (pinfunction "GREEN_3") (pintype "bidirectional"))
      (node (ref "U$5") (pin "28") (pinfunction "OUT0_28") (pintype "output"))
      (node (ref "U$508") (pin "3") (pinfunction "GREEN_3") (pintype "bidirectional"))
      (node (ref "U$60") (pin "3") (pinfunction "GREEN_3") (pintype "bidirectional"))
      (node (ref "U$92") (pin "3") (pinfunction "GREEN_3") (pintype "bidirectional"))
    )
    (net (code "133") (name "Net-(U$124-RED)") (class "Default")
      (node (ref "U$124") (pin "1") (pinfunction "RED_1") (pintype "bidirectional"))
      (node (ref "U$156") (pin "1") (pinfunction "RED_1") (pintype "bidirectional"))
      (node (ref "U$188") (pin "1") (pinfunction "RED_1") (pintype "bidirectional"))
      (node (ref "U$220") (pin "1") (pinfunction "RED_1") (pintype "bidirectional"))
      (node (ref "U$252") (pin "1") (pinfunction "RED_1") (pintype "bidirectional"))
      (node (ref "U$28") (pin "1") (pinfunction "RED_1") (pintype "bidirectional"))
      (node (ref "U$284") (pin "1") (pinfunction "RED_1") (pintype "bidirectional"))
      (node (ref "U$316") (pin "1") (pinfunction "RED_1") (pintype "bidirectional"))
      (node (ref "U$348") (pin "1") (pinfunction "RED_1") (pintype "bidirectional"))
      (node (ref "U$380") (pin "1") (pinfunction "RED_1") (pintype "bidirectional"))
      (node (ref "U$4") (pin "15") (pinfunction "OUT15_15") (pintype "output"))
      (node (ref "U$412") (pin "1") (pinfunction "RED_1") (pintype "bidirectional"))
      (node (ref "U$444") (pin "1") (pinfunction "RED_1") (pintype "bidirectional"))
      (node (ref "U$476") (pin "1") (pinfunction "RED_1") (pintype "bidirectional"))
      (node (ref "U$508") (pin "1") (pinfunction "RED_1") (pintype "bidirectional"))
      (node (ref "U$60") (pin "1") (pinfunction "RED_1") (pintype "bidirectional"))
      (node (ref "U$92") (pin "1") (pinfunction "RED_1") (pintype "bidirectional"))
    )
    (net (code "134") (name "Net-(U$125-BLUE)") (class "Default")
      (node (ref "U$125") (pin "4") (pinfunction "BLUE_4") (pintype "bidirectional"))
      (node (ref "U$157") (pin "4") (pinfunction "BLUE_4") (pintype "bidirectional"))
      (node (ref "U$189") (pin "4") (pinfunction "BLUE_4") (pintype "bidirectional"))
      (node (ref "U$221") (pin "4") (pinfunction "BLUE_4") (pintype "bidirectional"))
      (node (ref "U$253") (pin "4") (pinfunction "BLUE_4") (pintype "bidirectional"))
      (node (ref "U$285") (pin "4") (pinfunction "BLUE_4") (pintype "bidirectional"))
      (node (ref "U$29") (pin "4") (pinfunction "BLUE_4") (pintype "bidirectional"))
      (node (ref "U$317") (pin "4") (pinfunction "BLUE_4") (pintype "bidirectional"))
      (node (ref "U$349") (pin "4") (pinfunction "BLUE_4") (pintype "bidirectional"))
      (node (ref "U$381") (pin "4") (pinfunction "BLUE_4") (pintype "bidirectional"))
      (node (ref "U$413") (pin "4") (pinfunction "BLUE_4") (pintype "bidirectional"))
      (node (ref "U$445") (pin "4") (pinfunction "BLUE_4") (pintype "bidirectional"))
      (node (ref "U$477") (pin "4") (pinfunction "BLUE_4") (pintype "bidirectional"))
      (node (ref "U$5") (pin "4") (pinfunction "OUT4_4") (pintype "output"))
      (node (ref "U$509") (pin "4") (pinfunction "BLUE_4") (pintype "bidirectional"))
      (node (ref "U$61") (pin "4") (pinfunction "BLUE_4") (pintype "bidirectional"))
      (node (ref "U$93") (pin "4") (pinfunction "BLUE_4") (pintype "bidirectional"))
    )
    (net (code "135") (name "Net-(U$125-GREEN)") (class "Default")
      (node (ref "U$125") (pin "3") (pinfunction "GREEN_3") (pintype "bidirectional"))
      (node (ref "U$157") (pin "3") (pinfunction "GREEN_3") (pintype "bidirectional"))
      (node (ref "U$189") (pin "3") (pinfunction "GREEN_3") (pintype "bidirectional"))
      (node (ref "U$221") (pin "3") (pinfunction "GREEN_3") (pintype "bidirectional"))
      (node (ref "U$253") (pin "3") (pinfunction "GREEN_3") (pintype "bidirectional"))
      (node (ref "U$285") (pin "3") (pinfunction "GREEN_3") (pintype "bidirectional"))
      (node (ref "U$29") (pin "3") (pinfunction "GREEN_3") (pintype "bidirectional"))
      (node (ref "U$317") (pin "3") (pinfunction "GREEN_3") (pintype "bidirectional"))
      (node (ref "U$349") (pin "3") (pinfunction "GREEN_3") (pintype "bidirectional"))
      (node (ref "U$381") (pin "3") (pinfunction "GREEN_3") (pintype "bidirectional"))
      (node (ref "U$413") (pin "3") (pinfunction "GREEN_3") (pintype "bidirectional"))
      (node (ref "U$445") (pin "3") (pinfunction "GREEN_3") (pintype "bidirectional"))
      (node (ref "U$477") (pin "3") (pinfunction "GREEN_3") (pintype "bidirectional"))
      (node (ref "U$5") (pin "3") (pinfunction "OUT3_3") (pintype "output"))
      (node (ref "U$509") (pin "3") (pinfunction "GREEN_3") (pintype "bidirectional"))
      (node (ref "U$61") (pin "3") (pinfunction "GREEN_3") (pintype "bidirectional"))
      (node (ref "U$93") (pin "3") (pinfunction "GREEN_3") (pintype "bidirectional"))
    )
    (net (code "136") (name "Net-(U$125-RED)") (class "Default")
      (node (ref "U$125") (pin "1") (pinfunction "RED_1") (pintype "bidirectional"))
      (node (ref "U$157") (pin "1") (pinfunction "RED_1") (pintype "bidirectional"))
      (node (ref "U$189") (pin "1") (pinfunction "RED_1") (pintype "bidirectional"))
      (node (ref "U$221") (pin "1") (pinfunction "RED_1") (pintype "bidirectional"))
      (node (ref "U$253") (pin "1") (pinfunction "RED_1") (pintype "bidirectional"))
      (node (ref "U$285") (pin "1") (pinfunction "RED_1") (pintype "bidirectional"))
      (node (ref "U$29") (pin "1") (pinfunction "RED_1") (pintype "bidirectional"))
      (node (ref "U$317") (pin "1") (pinfunction "RED_1") (pintype "bidirectional"))
      (node (ref "U$349") (pin "1") (pinfunction "RED_1") (pintype "bidirectional"))
      (node (ref "U$381") (pin "1") (pinfunction "RED_1") (pintype "bidirectional"))
      (node (ref "U$413") (pin "1") (pinfunction "RED_1") (pintype "bidirectional"))
      (node (ref "U$445") (pin "1") (pinfunction "RED_1") (pintype "bidirectional"))
      (node (ref "U$477") (pin "1") (pinfunction "RED_1") (pintype "bidirectional"))
      (node (ref "U$5") (pin "2") (pinfunction "OUT2_2") (pintype "output"))
      (node (ref "U$509") (pin "1") (pinfunction "RED_1") (pintype "bidirectional"))
      (node (ref "U$61") (pin "1") (pinfunction "RED_1") (pintype "bidirectional"))
      (node (ref "U$93") (pin "1") (pinfunction "RED_1") (pintype "bidirectional"))
    )
    (net (code "137") (name "Net-(U$126-BLUE)") (class "Default")
      (node (ref "U$126") (pin "4") (pinfunction "BLUE_4") (pintype "bidirectional"))
      (node (ref "U$158") (pin "4") (pinfunction "BLUE_4") (pintype "bidirectional"))
      (node (ref "U$190") (pin "4") (pinfunction "BLUE_4") (pintype "bidirectional"))
      (node (ref "U$222") (pin "4") (pinfunction "BLUE_4") (pintype "bidirectional"))
      (node (ref "U$254") (pin "4") (pinfunction "BLUE_4") (pintype "bidirectional"))
      (node (ref "U$286") (pin "4") (pinfunction "BLUE_4") (pintype "bidirectional"))
      (node (ref "U$30") (pin "4") (pinfunction "BLUE_4") (pintype "bidirectional"))
      (node (ref "U$318") (pin "4") (pinfunction "BLUE_4") (pintype "bidirectional"))
      (node (ref "U$350") (pin "4") (pinfunction "BLUE_4") (pintype "bidirectional"))
      (node (ref "U$382") (pin "4") (pinfunction "BLUE_4") (pintype "bidirectional"))
      (node (ref "U$414") (pin "4") (pinfunction "BLUE_4") (pintype "bidirectional"))
      (node (ref "U$446") (pin "4") (pinfunction "BLUE_4") (pintype "bidirectional"))
      (node (ref "U$478") (pin "4") (pinfunction "BLUE_4") (pintype "bidirectional"))
      (node (ref "U$5") (pin "7") (pinfunction "OUT7_7") (pintype "output"))
      (node (ref "U$510") (pin "4") (pinfunction "BLUE_4") (pintype "bidirectional"))
      (node (ref "U$62") (pin "4") (pinfunction "BLUE_4") (pintype "bidirectional"))
      (node (ref "U$94") (pin "4") (pinfunction "BLUE_4") (pintype "bidirectional"))
    )
    (net (code "138") (name "Net-(U$126-GREEN)") (class "Default")
      (node (ref "U$126") (pin "3") (pinfunction "GREEN_3") (pintype "bidirectional"))
      (node (ref "U$158") (pin "3") (pinfunction "GREEN_3") (pintype "bidirectional"))
      (node (ref "U$190") (pin "3") (pinfunction "GREEN_3") (pintype "bidirectional"))
      (node (ref "U$222") (pin "3") (pinfunction "GREEN_3") (pintype "bidirectional"))
      (node (ref "U$254") (pin "3") (pinfunction "GREEN_3") (pintype "bidirectional"))
      (node (ref "U$286") (pin "3") (pinfunction "GREEN_3") (pintype "bidirectional"))
      (node (ref "U$30") (pin "3") (pinfunction "GREEN_3") (pintype "bidirectional"))
      (node (ref "U$318") (pin "3") (pinfunction "GREEN_3") (pintype "bidirectional"))
      (node (ref "U$350") (pin "3") (pinfunction "GREEN_3") (pintype "bidirectional"))
      (node (ref "U$382") (pin "3") (pinfunction "GREEN_3") (pintype "bidirectional"))
      (node (ref "U$414") (pin "3") (pinfunction "GREEN_3") (pintype "bidirectional"))
      (node (ref "U$446") (pin "3") (pinfunction "GREEN_3") (pintype "bidirectional"))
      (node (ref "U$478") (pin "3") (pinfunction "GREEN_3") (pintype "bidirectional"))
      (node (ref "U$5") (pin "6") (pinfunction "OUT6_6") (pintype "output"))
      (node (ref "U$510") (pin "3") (pinfunction "GREEN_3") (pintype "bidirectional"))
      (node (ref "U$62") (pin "3") (pinfunction "GREEN_3") (pintype "bidirectional"))
      (node (ref "U$94") (pin "3") (pinfunction "GREEN_3") (pintype "bidirectional"))
    )
    (net (code "139") (name "Net-(U$126-RED)") (class "Default")
      (node (ref "U$126") (pin "1") (pinfunction "RED_1") (pintype "bidirectional"))
      (node (ref "U$158") (pin "1") (pinfunction "RED_1") (pintype "bidirectional"))
      (node (ref "U$190") (pin "1") (pinfunction "RED_1") (pintype "bidirectional"))
      (node (ref "U$222") (pin "1") (pinfunction "RED_1") (pintype "bidirectional"))
      (node (ref "U$254") (pin "1") (pinfunction "RED_1") (pintype "bidirectional"))
      (node (ref "U$286") (pin "1") (pinfunction "RED_1") (pintype "bidirectional"))
      (node (ref "U$30") (pin "1") (pinfunction "RED_1") (pintype "bidirectional"))
      (node (ref "U$318") (pin "1") (pinfunction "RED_1") (pintype "bidirectional"))
      (node (ref "U$350") (pin "1") (pinfunction "RED_1") (pintype "bidirectional"))
      (node (ref "U$382") (pin "1") (pinfunction "RED_1") (pintype "bidirectional"))
      (node (ref "U$414") (pin "1") (pinfunction "RED_1") (pintype "bidirectional"))
      (node (ref "U$446") (pin "1") (pinfunction "RED_1") (pintype "bidirectional"))
      (node (ref "U$478") (pin "1") (pinfunction "RED_1") (pintype "bidirectional"))
      (node (ref "U$5") (pin "5") (pinfunction "OUT5_5") (pintype "output"))
      (node (ref "U$510") (pin "1") (pinfunction "RED_1") (pintype "bidirectional"))
      (node (ref "U$62") (pin "1") (pinfunction "RED_1") (pintype "bidirectional"))
      (node (ref "U$94") (pin "1") (pinfunction "RED_1") (pintype "bidirectional"))
    )
    (net (code "140") (name "Net-(U$127-BLUE)") (class "Default")
      (node (ref "U$127") (pin "4") (pinfunction "BLUE_4") (pintype "bidirectional"))
      (node (ref "U$159") (pin "4") (pinfunction "BLUE_4") (pintype "bidirectional"))
      (node (ref "U$191") (pin "4") (pinfunction "BLUE_4") (pintype "bidirectional"))
      (node (ref "U$223") (pin "4") (pinfunction "BLUE_4") (pintype "bidirectional"))
      (node (ref "U$255") (pin "4") (pinfunction "BLUE_4") (pintype "bidirectional"))
      (node (ref "U$287") (pin "4") (pinfunction "BLUE_4") (pintype "bidirectional"))
      (node (ref "U$31") (pin "4") (pinfunction "BLUE_4") (pintype "bidirectional"))
      (node (ref "U$319") (pin "4") (pinfunction "BLUE_4") (pintype "bidirectional"))
      (node (ref "U$351") (pin "4") (pinfunction "BLUE_4") (pintype "bidirectional"))
      (node (ref "U$383") (pin "4") (pinfunction "BLUE_4") (pintype "bidirectional"))
      (node (ref "U$415") (pin "4") (pinfunction "BLUE_4") (pintype "bidirectional"))
      (node (ref "U$447") (pin "4") (pinfunction "BLUE_4") (pintype "bidirectional"))
      (node (ref "U$479") (pin "4") (pinfunction "BLUE_4") (pintype "bidirectional"))
      (node (ref "U$5") (pin "10") (pinfunction "OUT10_10") (pintype "output"))
      (node (ref "U$511") (pin "4") (pinfunction "BLUE_4") (pintype "bidirectional"))
      (node (ref "U$63") (pin "4") (pinfunction "BLUE_4") (pintype "bidirectional"))
      (node (ref "U$95") (pin "4") (pinfunction "BLUE_4") (pintype "bidirectional"))
    )
    (net (code "141") (name "Net-(U$127-GREEN)") (class "Default")
      (node (ref "U$127") (pin "3") (pinfunction "GREEN_3") (pintype "bidirectional"))
      (node (ref "U$159") (pin "3") (pinfunction "GREEN_3") (pintype "bidirectional"))
      (node (ref "U$191") (pin "3") (pinfunction "GREEN_3") (pintype "bidirectional"))
      (node (ref "U$223") (pin "3") (pinfunction "GREEN_3") (pintype "bidirectional"))
      (node (ref "U$255") (pin "3") (pinfunction "GREEN_3") (pintype "bidirectional"))
      (node (ref "U$287") (pin "3") (pinfunction "GREEN_3") (pintype "bidirectional"))
      (node (ref "U$31") (pin "3") (pinfunction "GREEN_3") (pintype "bidirectional"))
      (node (ref "U$319") (pin "3") (pinfunction "GREEN_3") (pintype "bidirectional"))
      (node (ref "U$351") (pin "3") (pinfunction "GREEN_3") (pintype "bidirectional"))
      (node (ref "U$383") (pin "3") (pinfunction "GREEN_3") (pintype "bidirectional"))
      (node (ref "U$415") (pin "3") (pinfunction "GREEN_3") (pintype "bidirectional"))
      (node (ref "U$447") (pin "3") (pinfunction "GREEN_3") (pintype "bidirectional"))
      (node (ref "U$479") (pin "3") (pinfunction "GREEN_3") (pintype "bidirectional"))
      (node (ref "U$5") (pin "9") (pinfunction "OUT9_9") (pintype "output"))
      (node (ref "U$511") (pin "3") (pinfunction "GREEN_3") (pintype "bidirectional"))
      (node (ref "U$63") (pin "3") (pinfunction "GREEN_3") (pintype "bidirectional"))
      (node (ref "U$95") (pin "3") (pinfunction "GREEN_3") (pintype "bidirectional"))
    )
    (net (code "142") (name "Net-(U$127-RED)") (class "Default")
      (node (ref "U$127") (pin "1") (pinfunction "RED_1") (pintype "bidirectional"))
      (node (ref "U$159") (pin "1") (pinfunction "RED_1") (pintype "bidirectional"))
      (node (ref "U$191") (pin "1") (pinfunction "RED_1") (pintype "bidirectional"))
      (node (ref "U$223") (pin "1") (pinfunction "RED_1") (pintype "bidirectional"))
      (node (ref "U$255") (pin "1") (pinfunction "RED_1") (pintype "bidirectional"))
      (node (ref "U$287") (pin "1") (pinfunction "RED_1") (pintype "bidirectional"))
      (node (ref "U$31") (pin "1") (pinfunction "RED_1") (pintype "bidirectional"))
      (node (ref "U$319") (pin "1") (pinfunction "RED_1") (pintype "bidirectional"))
      (node (ref "U$351") (pin "1") (pinfunction "RED_1") (pintype "bidirectional"))
      (node (ref "U$383") (pin "1") (pinfunction "RED_1") (pintype "bidirectional"))
      (node (ref "U$415") (pin "1") (pinfunction "RED_1") (pintype "bidirectional"))
      (node (ref "U$447") (pin "1") (pinfunction "RED_1") (pintype "bidirectional"))
      (node (ref "U$479") (pin "1") (pinfunction "RED_1") (pintype "bidirectional"))
      (node (ref "U$5") (pin "8") (pinfunction "OUT8_8") (pintype "output"))
      (node (ref "U$511") (pin "1") (pinfunction "RED_1") (pintype "bidirectional"))
      (node (ref "U$63") (pin "1") (pinfunction "RED_1") (pintype "bidirectional"))
      (node (ref "U$95") (pin "1") (pinfunction "RED_1") (pintype "bidirectional"))
    )
    (net (code "143") (name "Net-(U$128-BLUE)") (class "Default")
      (node (ref "U$128") (pin "4") (pinfunction "BLUE_4") (pintype "bidirectional"))
      (node (ref "U$160") (pin "4") (pinfunction "BLUE_4") (pintype "bidirectional"))
      (node (ref "U$192") (pin "4") (pinfunction "BLUE_4") (pintype "bidirectional"))
      (node (ref "U$224") (pin "4") (pinfunction "BLUE_4") (pintype "bidirectional"))
      (node (ref "U$256") (pin "4") (pinfunction "BLUE_4") (pintype "bidirectional"))
      (node (ref "U$288") (pin "4") (pinfunction "BLUE_4") (pintype "bidirectional"))
      (node (ref "U$32") (pin "4") (pinfunction "BLUE_4") (pintype "bidirectional"))
      (node (ref "U$320") (pin "4") (pinfunction "BLUE_4") (pintype "bidirectional"))
      (node (ref "U$352") (pin "4") (pinfunction "BLUE_4") (pintype "bidirectional"))
      (node (ref "U$384") (pin "4") (pinfunction "BLUE_4") (pintype "bidirectional"))
      (node (ref "U$416") (pin "4") (pinfunction "BLUE_4") (pintype "bidirectional"))
      (node (ref "U$448") (pin "4") (pinfunction "BLUE_4") (pintype "bidirectional"))
      (node (ref "U$480") (pin "4") (pinfunction "BLUE_4") (pintype "bidirectional"))
      (node (ref "U$5") (pin "13") (pinfunction "OUT13_13") (pintype "output"))
      (node (ref "U$512") (pin "4") (pinfunction "BLUE_4") (pintype "bidirectional"))
      (node (ref "U$64") (pin "4") (pinfunction "BLUE_4") (pintype "bidirectional"))
      (node (ref "U$96") (pin "4") (pinfunction "BLUE_4") (pintype "bidirectional"))
    )
    (net (code "144") (name "Net-(U$128-GREEN)") (class "Default")
      (node (ref "U$128") (pin "3") (pinfunction "GREEN_3") (pintype "bidirectional"))
      (node (ref "U$160") (pin "3") (pinfunction "GREEN_3") (pintype "bidirectional"))
      (node (ref "U$192") (pin "3") (pinfunction "GREEN_3") (pintype "bidirectional"))
      (node (ref "U$224") (pin "3") (pinfunction "GREEN_3") (pintype "bidirectional"))
      (node (ref "U$256") (pin "3") (pinfunction "GREEN_3") (pintype "bidirectional"))
      (node (ref "U$288") (pin "3") (pinfunction "GREEN_3") (pintype "bidirectional"))
      (node (ref "U$32") (pin "3") (pinfunction "GREEN_3") (pintype "bidirectional"))
      (node (ref "U$320") (pin "3") (pinfunction "GREEN_3") (pintype "bidirectional"))
      (node (ref "U$352") (pin "3") (pinfunction "GREEN_3") (pintype "bidirectional"))
      (node (ref "U$384") (pin "3") (pinfunction "GREEN_3") (pintype "bidirectional"))
      (node (ref "U$416") (pin "3") (pinfunction "GREEN_3") (pintype "bidirectional"))
      (node (ref "U$448") (pin "3") (pinfunction "GREEN_3") (pintype "bidirectional"))
      (node (ref "U$480") (pin "3") (pinfunction "GREEN_3") (pintype "bidirectional"))
      (node (ref "U$5") (pin "12") (pinfunction "OUT12_12") (pintype "output"))
      (node (ref "U$512") (pin "3") (pinfunction "GREEN_3") (pintype "bidirectional"))
      (node (ref "U$64") (pin "3") (pinfunction "GREEN_3") (pintype "bidirectional"))
      (node (ref "U$96") (pin "3") (pinfunction "GREEN_3") (pintype "bidirectional"))
    )
    (net (code "145") (name "Net-(U$128-RED)") (class "Default")
      (node (ref "U$128") (pin "1") (pinfunction "RED_1") (pintype "bidirectional"))
      (node (ref "U$160") (pin "1") (pinfunction "RED_1") (pintype "bidirectional"))
      (node (ref "U$192") (pin "1") (pinfunction "RED_1") (pintype "bidirectional"))
      (node (ref "U$224") (pin "1") (pinfunction "RED_1") (pintype "bidirectional"))
      (node (ref "U$256") (pin "1") (pinfunction "RED_1") (pintype "bidirectional"))
      (node (ref "U$288") (pin "1") (pinfunction "RED_1") (pintype "bidirectional"))
      (node (ref "U$32") (pin "1") (pinfunction "RED_1") (pintype "bidirectional"))
      (node (ref "U$320") (pin "1") (pinfunction "RED_1") (pintype "bidirectional"))
      (node (ref "U$352") (pin "1") (pinfunction "RED_1") (pintype "bidirectional"))
      (node (ref "U$384") (pin "1") (pinfunction "RED_1") (pintype "bidirectional"))
      (node (ref "U$416") (pin "1") (pinfunction "RED_1") (pintype "bidirectional"))
      (node (ref "U$448") (pin "1") (pinfunction "RED_1") (pintype "bidirectional"))
      (node (ref "U$480") (pin "1") (pinfunction "RED_1") (pintype "bidirectional"))
      (node (ref "U$5") (pin "11") (pinfunction "OUT11_11") (pintype "output"))
      (node (ref "U$512") (pin "1") (pinfunction "RED_1") (pintype "bidirectional"))
      (node (ref "U$64") (pin "1") (pinfunction "RED_1") (pintype "bidirectional"))
      (node (ref "U$96") (pin "1") (pinfunction "RED_1") (pintype "bidirectional"))
    )
    (net (code "146") (name "Net-(U$129-BLUE)") (class "Default")
      (node (ref "U$129") (pin "4") (pinfunction "BLUE_4") (pintype "bidirectional"))
      (node (ref "U$161") (pin "4") (pinfunction "BLUE_4") (pintype "bidirectional"))
      (node (ref "U$193") (pin "4") (pinfunction "BLUE_4") (pintype "bidirectional"))
      (node (ref "U$225") (pin "4") (pinfunction "BLUE_4") (pintype "bidirectional"))
      (node (ref "U$257") (pin "4") (pinfunction "BLUE_4") (pintype "bidirectional"))
      (node (ref "U$289") (pin "4") (pinfunction "BLUE_4") (pintype "bidirectional"))
      (node (ref "U$321") (pin "4") (pinfunction "BLUE_4") (pintype "bidirectional"))
      (node (ref "U$33") (pin "4") (pinfunction "BLUE_4") (pintype "bidirectional"))
      (node (ref "U$353") (pin "4") (pinfunction "BLUE_4") (pintype "bidirectional"))
      (node (ref "U$385") (pin "4") (pinfunction "BLUE_4") (pintype "bidirectional"))
      (node (ref "U$417") (pin "4") (pinfunction "BLUE_4") (pintype "bidirectional"))
      (node (ref "U$449") (pin "4") (pinfunction "BLUE_4") (pintype "bidirectional"))
      (node (ref "U$481") (pin "4") (pinfunction "BLUE_4") (pintype "bidirectional"))
      (node (ref "U$513") (pin "4") (pinfunction "BLUE_4") (pintype "bidirectional"))
      (node (ref "U$6") (pin "28") (pinfunction "OUT0_28") (pintype "output"))
      (node (ref "U$65") (pin "4") (pinfunction "BLUE_4") (pintype "bidirectional"))
      (node (ref "U$97") (pin "4") (pinfunction "BLUE_4") (pintype "bidirectional"))
    )
    (net (code "147") (name "Net-(U$129-GREEN)") (class "Default")
      (node (ref "U$129") (pin "3") (pinfunction "GREEN_3") (pintype "bidirectional"))
      (node (ref "U$161") (pin "3") (pinfunction "GREEN_3") (pintype "bidirectional"))
      (node (ref "U$193") (pin "3") (pinfunction "GREEN_3") (pintype "bidirectional"))
      (node (ref "U$225") (pin "3") (pinfunction "GREEN_3") (pintype "bidirectional"))
      (node (ref "U$257") (pin "3") (pinfunction "GREEN_3") (pintype "bidirectional"))
      (node (ref "U$289") (pin "3") (pinfunction "GREEN_3") (pintype "bidirectional"))
      (node (ref "U$321") (pin "3") (pinfunction "GREEN_3") (pintype "bidirectional"))
      (node (ref "U$33") (pin "3") (pinfunction "GREEN_3") (pintype "bidirectional"))
      (node (ref "U$353") (pin "3") (pinfunction "GREEN_3") (pintype "bidirectional"))
      (node (ref "U$385") (pin "3") (pinfunction "GREEN_3") (pintype "bidirectional"))
      (node (ref "U$417") (pin "3") (pinfunction "GREEN_3") (pintype "bidirectional"))
      (node (ref "U$449") (pin "3") (pinfunction "GREEN_3") (pintype "bidirectional"))
      (node (ref "U$481") (pin "3") (pinfunction "GREEN_3") (pintype "bidirectional"))
      (node (ref "U$5") (pin "15") (pinfunction "OUT15_15") (pintype "output"))
      (node (ref "U$513") (pin "3") (pinfunction "GREEN_3") (pintype "bidirectional"))
      (node (ref "U$65") (pin "3") (pinfunction "GREEN_3") (pintype "bidirectional"))
      (node (ref "U$97") (pin "3") (pinfunction "GREEN_3") (pintype "bidirectional"))
    )
    (net (code "148") (name "Net-(U$129-RED)") (class "Default")
      (node (ref "U$129") (pin "1") (pinfunction "RED_1") (pintype "bidirectional"))
      (node (ref "U$161") (pin "1") (pinfunction "RED_1") (pintype "bidirectional"))
      (node (ref "U$193") (pin "1") (pinfunction "RED_1") (pintype "bidirectional"))
      (node (ref "U$225") (pin "1") (pinfunction "RED_1") (pintype "bidirectional"))
      (node (ref "U$257") (pin "1") (pinfunction "RED_1") (pintype "bidirectional"))
      (node (ref "U$289") (pin "1") (pinfunction "RED_1") (pintype "bidirectional"))
      (node (ref "U$321") (pin "1") (pinfunction "RED_1") (pintype "bidirectional"))
      (node (ref "U$33") (pin "1") (pinfunction "RED_1") (pintype "bidirectional"))
      (node (ref "U$353") (pin "1") (pinfunction "RED_1") (pintype "bidirectional"))
      (node (ref "U$385") (pin "1") (pinfunction "RED_1") (pintype "bidirectional"))
      (node (ref "U$417") (pin "1") (pinfunction "RED_1") (pintype "bidirectional"))
      (node (ref "U$449") (pin "1") (pinfunction "RED_1") (pintype "bidirectional"))
      (node (ref "U$481") (pin "1") (pinfunction "RED_1") (pintype "bidirectional"))
      (node (ref "U$5") (pin "14") (pinfunction "OUT14_14") (pintype "output"))
      (node (ref "U$513") (pin "1") (pinfunction "RED_1") (pintype "bidirectional"))
      (node (ref "U$65") (pin "1") (pinfunction "RED_1") (pintype "bidirectional"))
      (node (ref "U$97") (pin "1") (pinfunction "RED_1") (pintype "bidirectional"))
    )
    (net (code "149") (name "Net-(U$130-BLUE)") (class "Default")
      (node (ref "U$130") (pin "4") (pinfunction "BLUE_4") (pintype "bidirectional"))
      (node (ref "U$162") (pin "4") (pinfunction "BLUE_4") (pintype "bidirectional"))
      (node (ref "U$194") (pin "4") (pinfunction "BLUE_4") (pintype "bidirectional"))
      (node (ref "U$226") (pin "4") (pinfunction "BLUE_4") (pintype "bidirectional"))
      (node (ref "U$258") (pin "4") (pinfunction "BLUE_4") (pintype "bidirectional"))
      (node (ref "U$290") (pin "4") (pinfunction "BLUE_4") (pintype "bidirectional"))
      (node (ref "U$322") (pin "4") (pinfunction "BLUE_4") (pintype "bidirectional"))
      (node (ref "U$34") (pin "4") (pinfunction "BLUE_4") (pintype "bidirectional"))
      (node (ref "U$354") (pin "4") (pinfunction "BLUE_4") (pintype "bidirectional"))
      (node (ref "U$386") (pin "4") (pinfunction "BLUE_4") (pintype "bidirectional"))
      (node (ref "U$418") (pin "4") (pinfunction "BLUE_4") (pintype "bidirectional"))
      (node (ref "U$450") (pin "4") (pinfunction "BLUE_4") (pintype "bidirectional"))
      (node (ref "U$482") (pin "4") (pinfunction "BLUE_4") (pintype "bidirectional"))
      (node (ref "U$514") (pin "4") (pinfunction "BLUE_4") (pintype "bidirectional"))
      (node (ref "U$6") (pin "3") (pinfunction "OUT3_3") (pintype "output"))
      (node (ref "U$66") (pin "4") (pinfunction "BLUE_4") (pintype "bidirectional"))
      (node (ref "U$98") (pin "4") (pinfunction "BLUE_4") (pintype "bidirectional"))
    )
    (net (code "150") (name "Net-(U$130-GREEN)") (class "Default")
      (node (ref "U$130") (pin "3") (pinfunction "GREEN_3") (pintype "bidirectional"))
      (node (ref "U$162") (pin "3") (pinfunction "GREEN_3") (pintype "bidirectional"))
      (node (ref "U$194") (pin "3") (pinfunction "GREEN_3") (pintype "bidirectional"))
      (node (ref "U$226") (pin "3") (pinfunction "GREEN_3") (pintype "bidirectional"))
      (node (ref "U$258") (pin "3") (pinfunction "GREEN_3") (pintype "bidirectional"))
      (node (ref "U$290") (pin "3") (pinfunction "GREEN_3") (pintype "bidirectional"))
      (node (ref "U$322") (pin "3") (pinfunction "GREEN_3") (pintype "bidirectional"))
      (node (ref "U$34") (pin "3") (pinfunction "GREEN_3") (pintype "bidirectional"))
      (node (ref "U$354") (pin "3") (pinfunction "GREEN_3") (pintype "bidirectional"))
      (node (ref "U$386") (pin "3") (pinfunction "GREEN_3") (pintype "bidirectional"))
      (node (ref "U$418") (pin "3") (pinfunction "GREEN_3") (pintype "bidirectional"))
      (node (ref "U$450") (pin "3") (pinfunction "GREEN_3") (pintype "bidirectional"))
      (node (ref "U$482") (pin "3") (pinfunction "GREEN_3") (pintype "bidirectional"))
      (node (ref "U$514") (pin "3") (pinfunction "GREEN_3") (pintype "bidirectional"))
      (node (ref "U$6") (pin "2") (pinfunction "OUT2_2") (pintype "output"))
      (node (ref "U$66") (pin "3") (pinfunction "GREEN_3") (pintype "bidirectional"))
      (node (ref "U$98") (pin "3") (pinfunction "GREEN_3") (pintype "bidirectional"))
    )
    (net (code "151") (name "Net-(U$130-RED)") (class "Default")
      (node (ref "U$130") (pin "1") (pinfunction "RED_1") (pintype "bidirectional"))
      (node (ref "U$162") (pin "1") (pinfunction "RED_1") (pintype "bidirectional"))
      (node (ref "U$194") (pin "1") (pinfunction "RED_1") (pintype "bidirectional"))
      (node (ref "U$226") (pin "1") (pinfunction "RED_1") (pintype "bidirectional"))
      (node (ref "U$258") (pin "1") (pinfunction "RED_1") (pintype "bidirectional"))
      (node (ref "U$290") (pin "1") (pinfunction "RED_1") (pintype "bidirectional"))
      (node (ref "U$322") (pin "1") (pinfunction "RED_1") (pintype "bidirectional"))
      (node (ref "U$34") (pin "1") (pinfunction "RED_1") (pintype "bidirectional"))
      (node (ref "U$354") (pin "1") (pinfunction "RED_1") (pintype "bidirectional"))
      (node (ref "U$386") (pin "1") (pinfunction "RED_1") (pintype "bidirectional"))
      (node (ref "U$418") (pin "1") (pinfunction "RED_1") (pintype "bidirectional"))
      (node (ref "U$450") (pin "1") (pinfunction "RED_1") (pintype "bidirectional"))
      (node (ref "U$482") (pin "1") (pinfunction "RED_1") (pintype "bidirectional"))
      (node (ref "U$514") (pin "1") (pinfunction "RED_1") (pintype "bidirectional"))
      (node (ref "U$6") (pin "1") (pinfunction "OUT1_1") (pintype "output"))
      (node (ref "U$66") (pin "1") (pinfunction "RED_1") (pintype "bidirectional"))
      (node (ref "U$98") (pin "1") (pinfunction "RED_1") (pintype "bidirectional"))
    )
    (net (code "152") (name "Net-(U$131-BLUE)") (class "Default")
      (node (ref "U$131") (pin "4") (pinfunction "BLUE_4") (pintype "bidirectional"))
      (node (ref "U$163") (pin "4") (pinfunction "BLUE_4") (pintype "bidirectional"))
      (node (ref "U$195") (pin "4") (pinfunction "BLUE_4") (pintype "bidirectional"))
      (node (ref "U$227") (pin "4") (pinfunction "BLUE_4") (pintype "bidirectional"))
      (node (ref "U$259") (pin "4") (pinfunction "BLUE_4") (pintype "bidirectional"))
      (node (ref "U$291") (pin "4") (pinfunction "BLUE_4") (pintype "bidirectional"))
      (node (ref "U$323") (pin "4") (pinfunction "BLUE_4") (pintype "bidirectional"))
      (node (ref "U$35") (pin "4") (pinfunction "BLUE_4") (pintype "bidirectional"))
      (node (ref "U$355") (pin "4") (pinfunction "BLUE_4") (pintype "bidirectional"))
      (node (ref "U$387") (pin "4") (pinfunction "BLUE_4") (pintype "bidirectional"))
      (node (ref "U$419") (pin "4") (pinfunction "BLUE_4") (pintype "bidirectional"))
      (node (ref "U$451") (pin "4") (pinfunction "BLUE_4") (pintype "bidirectional"))
      (node (ref "U$483") (pin "4") (pinfunction "BLUE_4") (pintype "bidirectional"))
      (node (ref "U$515") (pin "4") (pinfunction "BLUE_4") (pintype "bidirectional"))
      (node (ref "U$6") (pin "6") (pinfunction "OUT6_6") (pintype "output"))
      (node (ref "U$67") (pin "4") (pinfunction "BLUE_4") (pintype "bidirectional"))
      (node (ref "U$99") (pin "4") (pinfunction "BLUE_4") (pintype "bidirectional"))
    )
    (net (code "153") (name "Net-(U$131-GREEN)") (class "Default")
      (node (ref "U$131") (pin "3") (pinfunction "GREEN_3") (pintype "bidirectional"))
      (node (ref "U$163") (pin "3") (pinfunction "GREEN_3") (pintype "bidirectional"))
      (node (ref "U$195") (pin "3") (pinfunction "GREEN_3") (pintype "bidirectional"))
      (node (ref "U$227") (pin "3") (pinfunction "GREEN_3") (pintype "bidirectional"))
      (node (ref "U$259") (pin "3") (pinfunction "GREEN_3") (pintype "bidirectional"))
      (node (ref "U$291") (pin "3") (pinfunction "GREEN_3") (pintype "bidirectional"))
      (node (ref "U$323") (pin "3") (pinfunction "GREEN_3") (pintype "bidirectional"))
      (node (ref "U$35") (pin "3") (pinfunction "GREEN_3") (pintype "bidirectional"))
      (node (ref "U$355") (pin "3") (pinfunction "GREEN_3") (pintype "bidirectional"))
      (node (ref "U$387") (pin "3") (pinfunction "GREEN_3") (pintype "bidirectional"))
      (node (ref "U$419") (pin "3") (pinfunction "GREEN_3") (pintype "bidirectional"))
      (node (ref "U$451") (pin "3") (pinfunction "GREEN_3") (pintype "bidirectional"))
      (node (ref "U$483") (pin "3") (pinfunction "GREEN_3") (pintype "bidirectional"))
      (node (ref "U$515") (pin "3") (pinfunction "GREEN_3") (pintype "bidirectional"))
      (node (ref "U$6") (pin "5") (pinfunction "OUT5_5") (pintype "output"))
      (node (ref "U$67") (pin "3") (pinfunction "GREEN_3") (pintype "bidirectional"))
      (node (ref "U$99") (pin "3") (pinfunction "GREEN_3") (pintype "bidirectional"))
    )
    (net (code "154") (name "Net-(U$131-RED)") (class "Default")
      (node (ref "U$131") (pin "1") (pinfunction "RED_1") (pintype "bidirectional"))
      (node (ref "U$163") (pin "1") (pinfunction "RED_1") (pintype "bidirectional"))
      (node (ref "U$195") (pin "1") (pinfunction "RED_1") (pintype "bidirectional"))
      (node (ref "U$227") (pin "1") (pinfunction "RED_1") (pintype "bidirectional"))
      (node (ref "U$259") (pin "1") (pinfunction "RED_1") (pintype "bidirectional"))
      (node (ref "U$291") (pin "1") (pinfunction "RED_1") (pintype "bidirectional"))
      (node (ref "U$323") (pin "1") (pinfunction "RED_1") (pintype "bidirectional"))
      (node (ref "U$35") (pin "1") (pinfunction "RED_1") (pintype "bidirectional"))
      (node (ref "U$355") (pin "1") (pinfunction "RED_1") (pintype "bidirectional"))
      (node (ref "U$387") (pin "1") (pinfunction "RED_1") (pintype "bidirectional"))
      (node (ref "U$419") (pin "1") (pinfunction "RED_1") (pintype "bidirectional"))
      (node (ref "U$451") (pin "1") (pinfunction "RED_1") (pintype "bidirectional"))
      (node (ref "U$483") (pin "1") (pinfunction "RED_1") (pintype "bidirectional"))
      (node (ref "U$515") (pin "1") (pinfunction "RED_1") (pintype "bidirectional"))
      (node (ref "U$6") (pin "4") (pinfunction "OUT4_4") (pintype "output"))
      (node (ref "U$67") (pin "1") (pinfunction "RED_1") (pintype "bidirectional"))
      (node (ref "U$99") (pin "1") (pinfunction "RED_1") (pintype "bidirectional"))
    )
    (net (code "155") (name "unconnected-(IC1A-QS*-Pad10)") (class "Default")
      (node (ref "IC1") (pin "10") (pinfunction "QS*_10") (pintype "output"))
    )
    (net (code "156") (name "unconnected-(IC2A-QS*-Pad10)") (class "Default")
      (node (ref "IC2") (pin "10") (pinfunction "QS*_10") (pintype "output"))
    )
    (net (code "157") (name "unconnected-(IC2A-QS-Pad9)") (class "Default")
      (node (ref "IC2") (pin "9") (pinfunction "QS_9") (pintype "output"))
    )
    (net (code "158") (name "unconnected-(U$1-DCPRG-Pad19)") (class "Default")
      (node (ref "U$1") (pin "19") (pinfunction "DCPRG_19") (pintype "input"))
    )
    (net (code "159") (name "unconnected-(U$1-XERR-Pad16)") (class "Default")
      (node (ref "U$1") (pin "16") (pinfunction "XERR_16") (pintype "output"))
    )
    (net (code "160") (name "unconnected-(U$2-DCPRG-Pad19)") (class "Default")
      (node (ref "U$2") (pin "19") (pinfunction "DCPRG_19") (pintype "input"))
    )
    (net (code "161") (name "unconnected-(U$2-XERR-Pad16)") (class "Default")
      (node (ref "U$2") (pin "16") (pinfunction "XERR_16") (pintype "output"))
    )
    (net (code "162") (name "unconnected-(U$3-DCPRG-Pad19)") (class "Default")
      (node (ref "U$3") (pin "19") (pinfunction "DCPRG_19") (pintype "input"))
    )
    (net (code "163") (name "unconnected-(U$3-XERR-Pad16)") (class "Default")
      (node (ref "U$3") (pin "16") (pinfunction "XERR_16") (pintype "output"))
    )
    (net (code "164") (name "unconnected-(U$4-DCPRG-Pad19)") (class "Default")
      (node (ref "U$4") (pin "19") (pinfunction "DCPRG_19") (pintype "input"))
    )
    (net (code "165") (name "unconnected-(U$4-XERR-Pad16)") (class "Default")
      (node (ref "U$4") (pin "16") (pinfunction "XERR_16") (pintype "output"))
    )
    (net (code "166") (name "unconnected-(U$5-DCPRG-Pad19)") (class "Default")
      (node (ref "U$5") (pin "19") (pinfunction "DCPRG_19") (pintype "input"))
    )
    (net (code "167") (name "unconnected-(U$5-XERR-Pad16)") (class "Default")
      (node (ref "U$5") (pin "16") (pinfunction "XERR_16") (pintype "output"))
    )
    (net (code "168") (name "unconnected-(U$6-DCPRG-Pad19)") (class "Default")
      (node (ref "U$6") (pin "19") (pinfunction "DCPRG_19") (pintype "input"))
    )
    (net (code "169") (name "unconnected-(U$6-SOUT-Pad17)") (class "Default")
      (node (ref "U$6") (pin "17") (pinfunction "SOUT_17") (pintype "output"))
    )
    (net (code "170") (name "unconnected-(U$6-XERR-Pad16)") (class "Default")
      (node (ref "U$6") (pin "16") (pinfunction "XERR_16") (pintype "output"))
    )
  )
)
